# Lafferty1.net
KiCad netlist of a schematic drawn in EAGLE
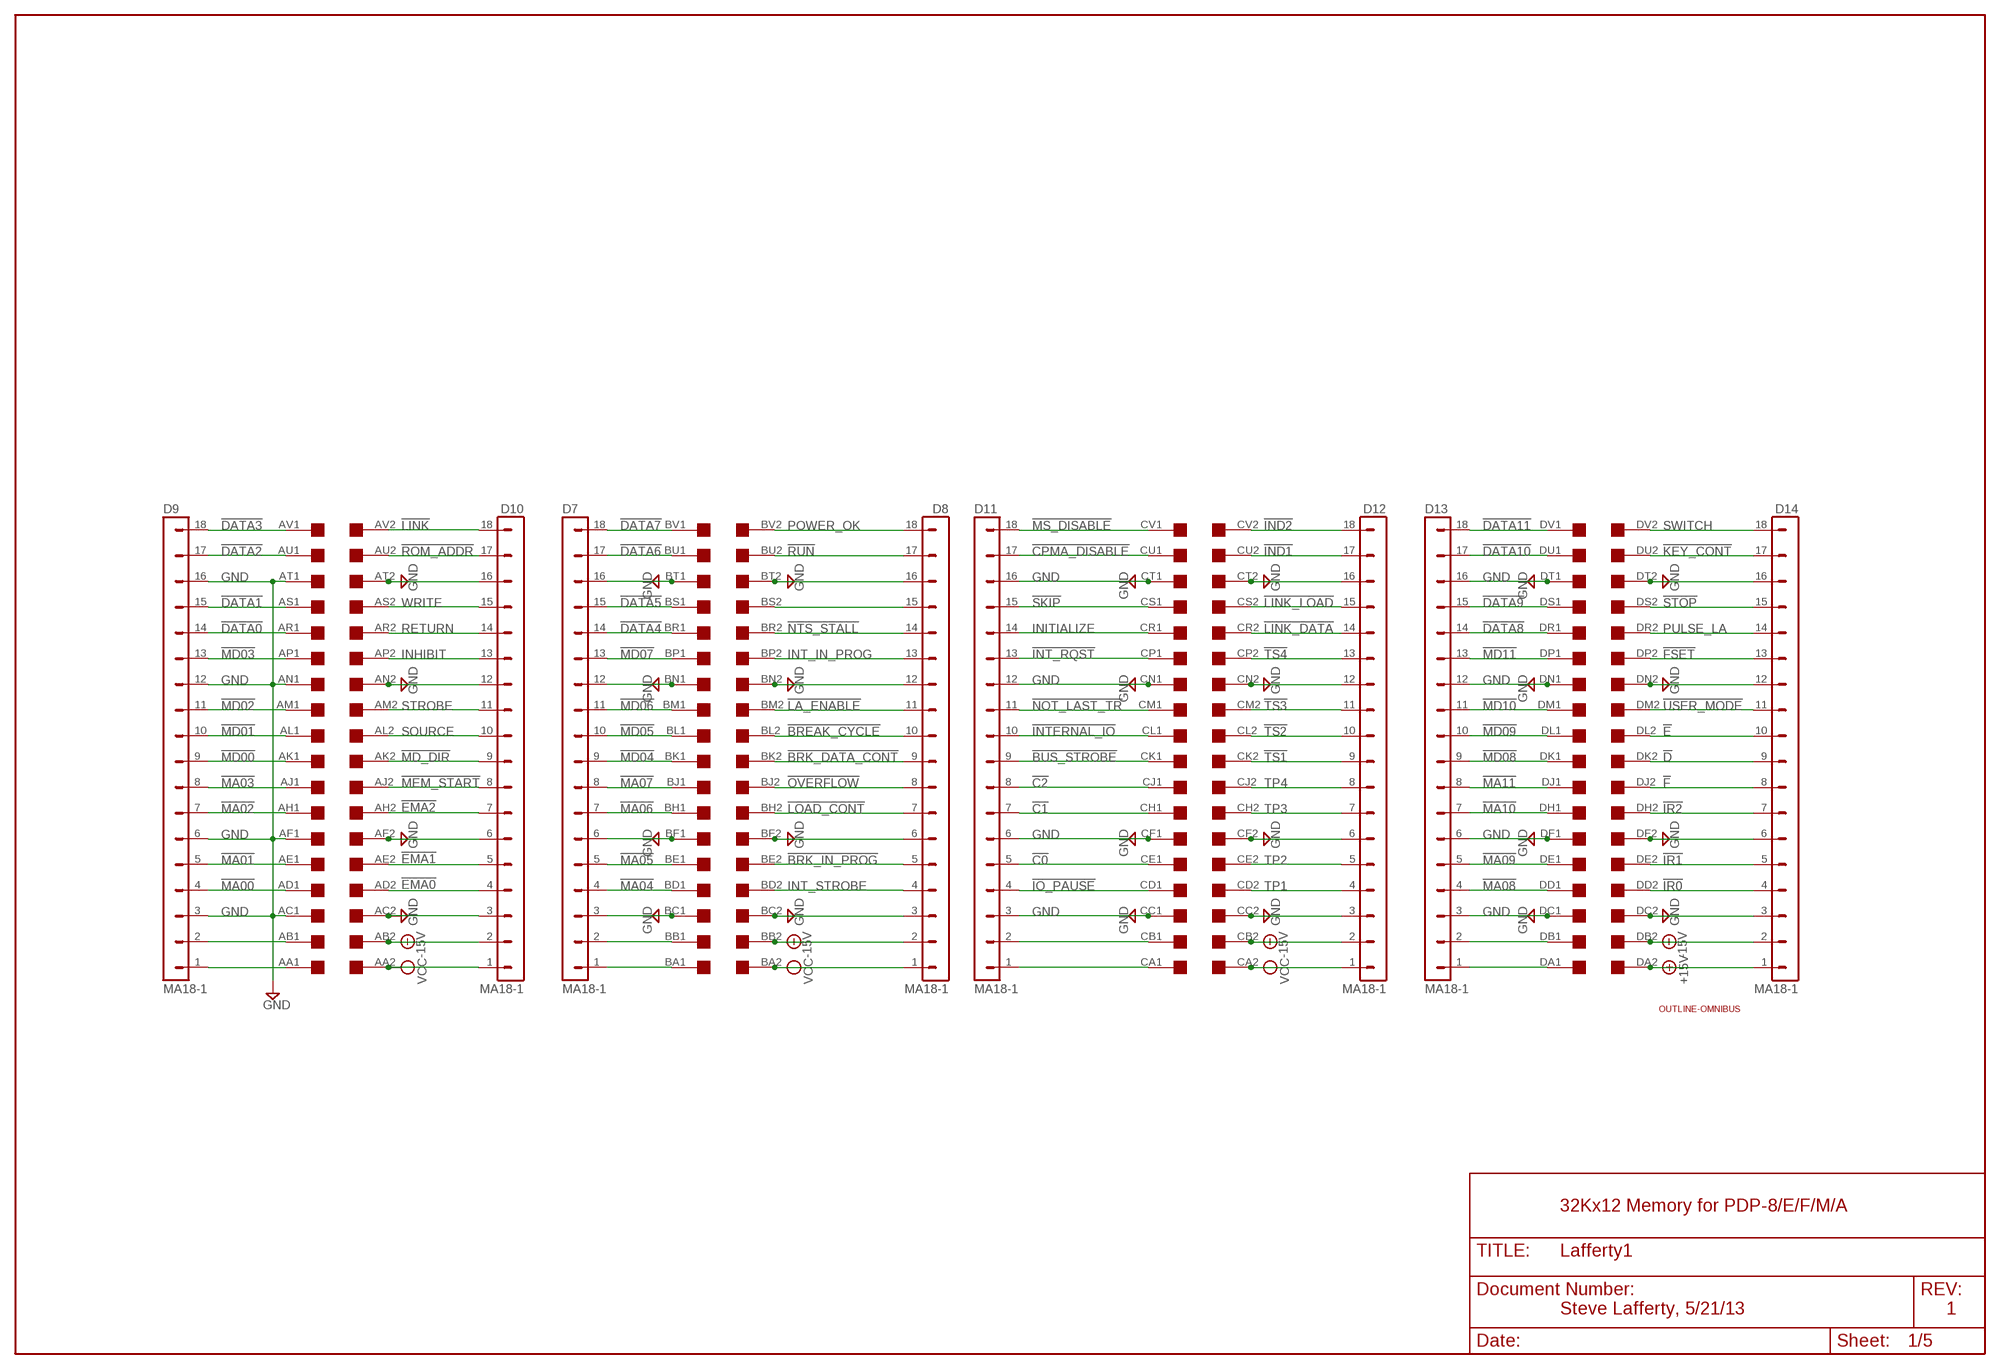
[diagram p0: schematic, sheet 1]
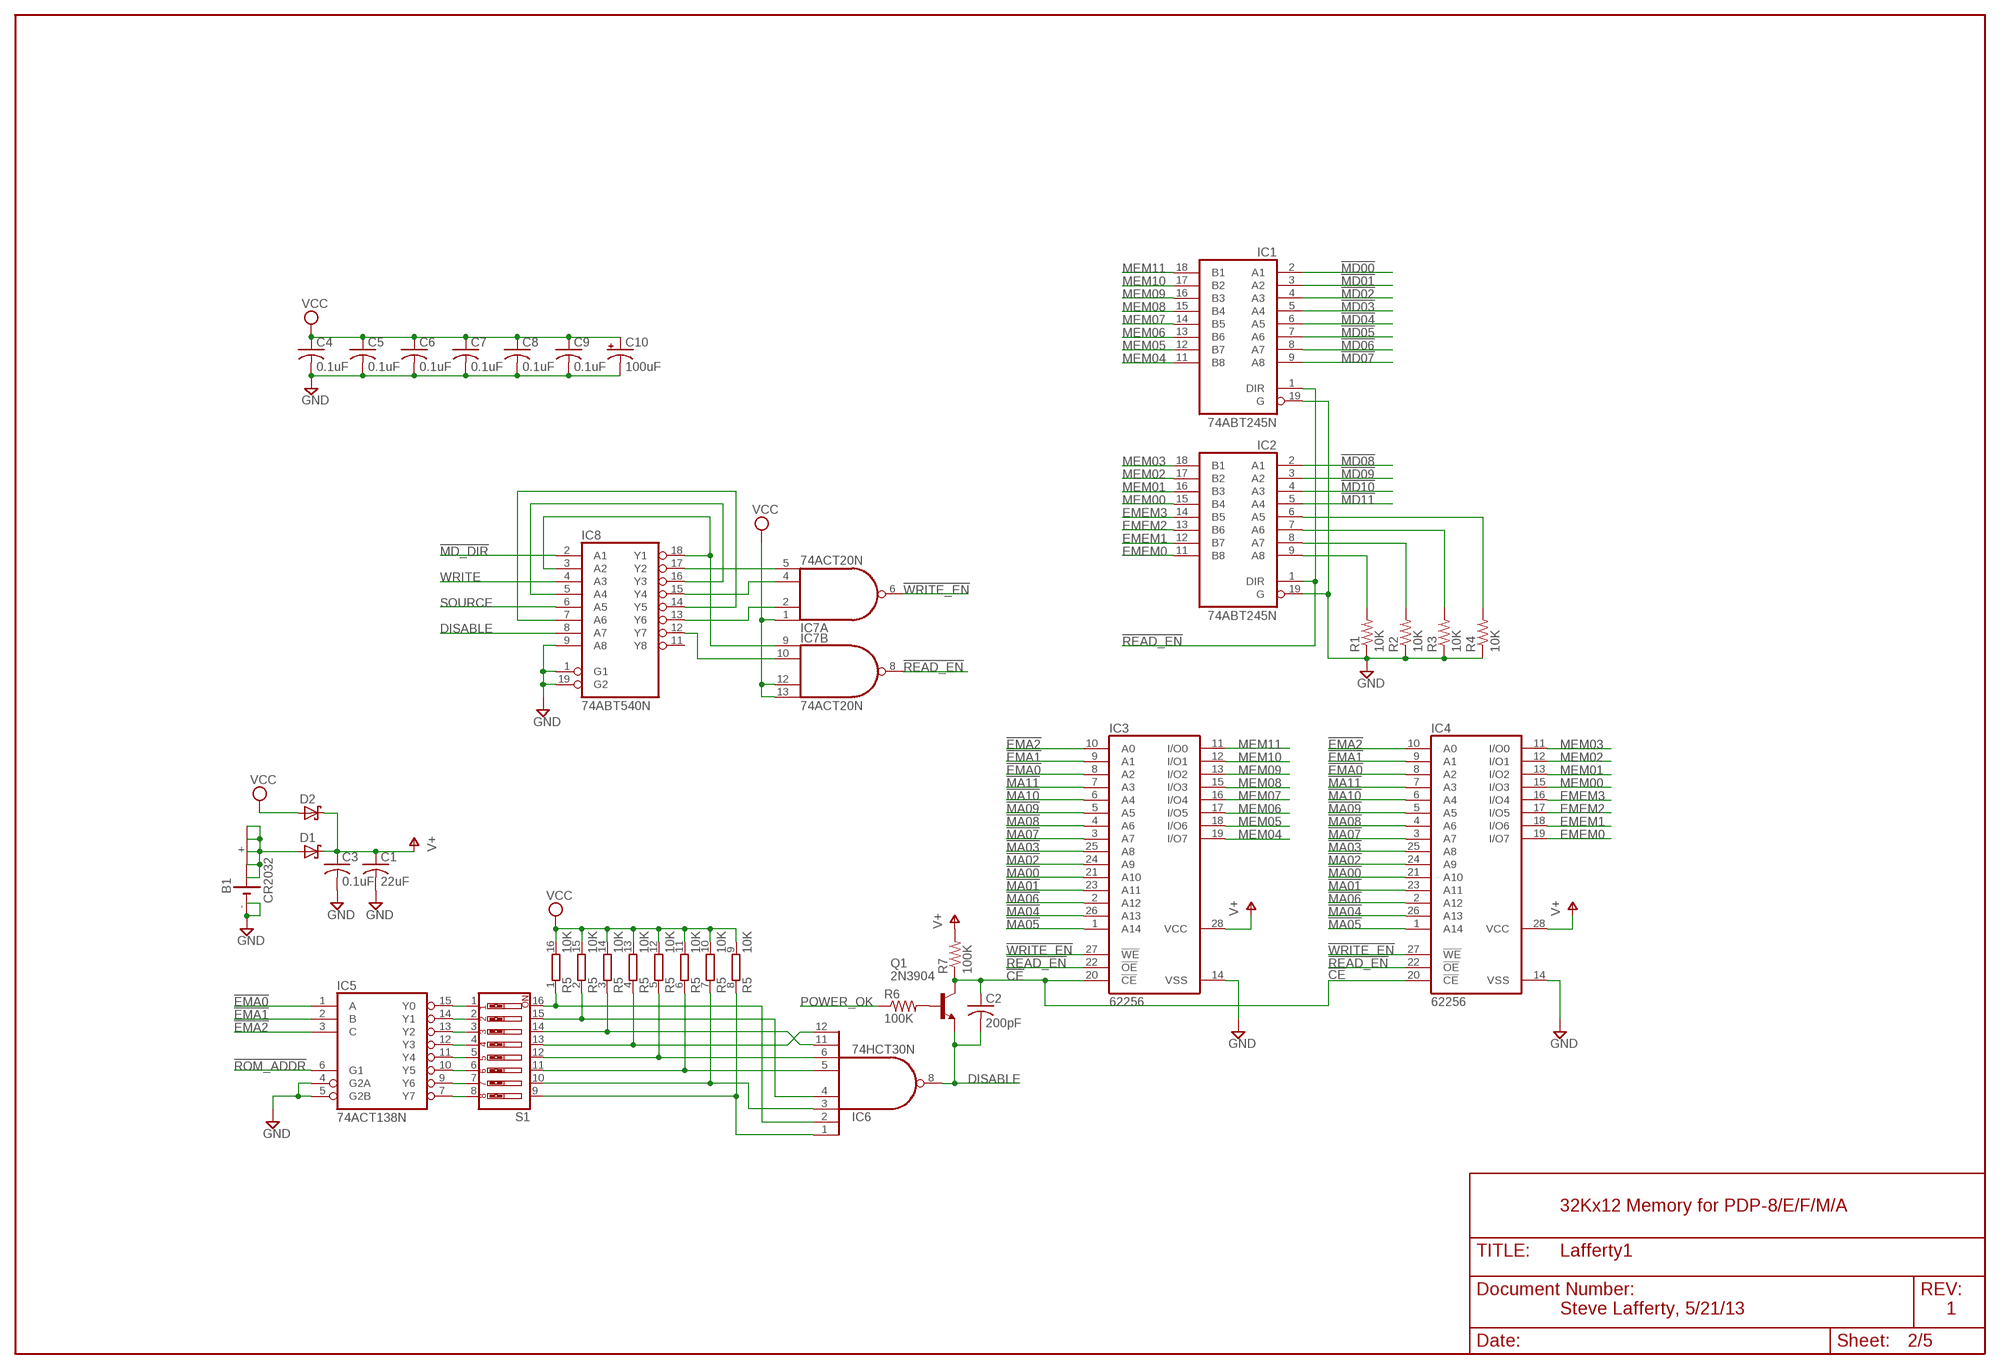
[diagram p1: schematic, sheet 2]
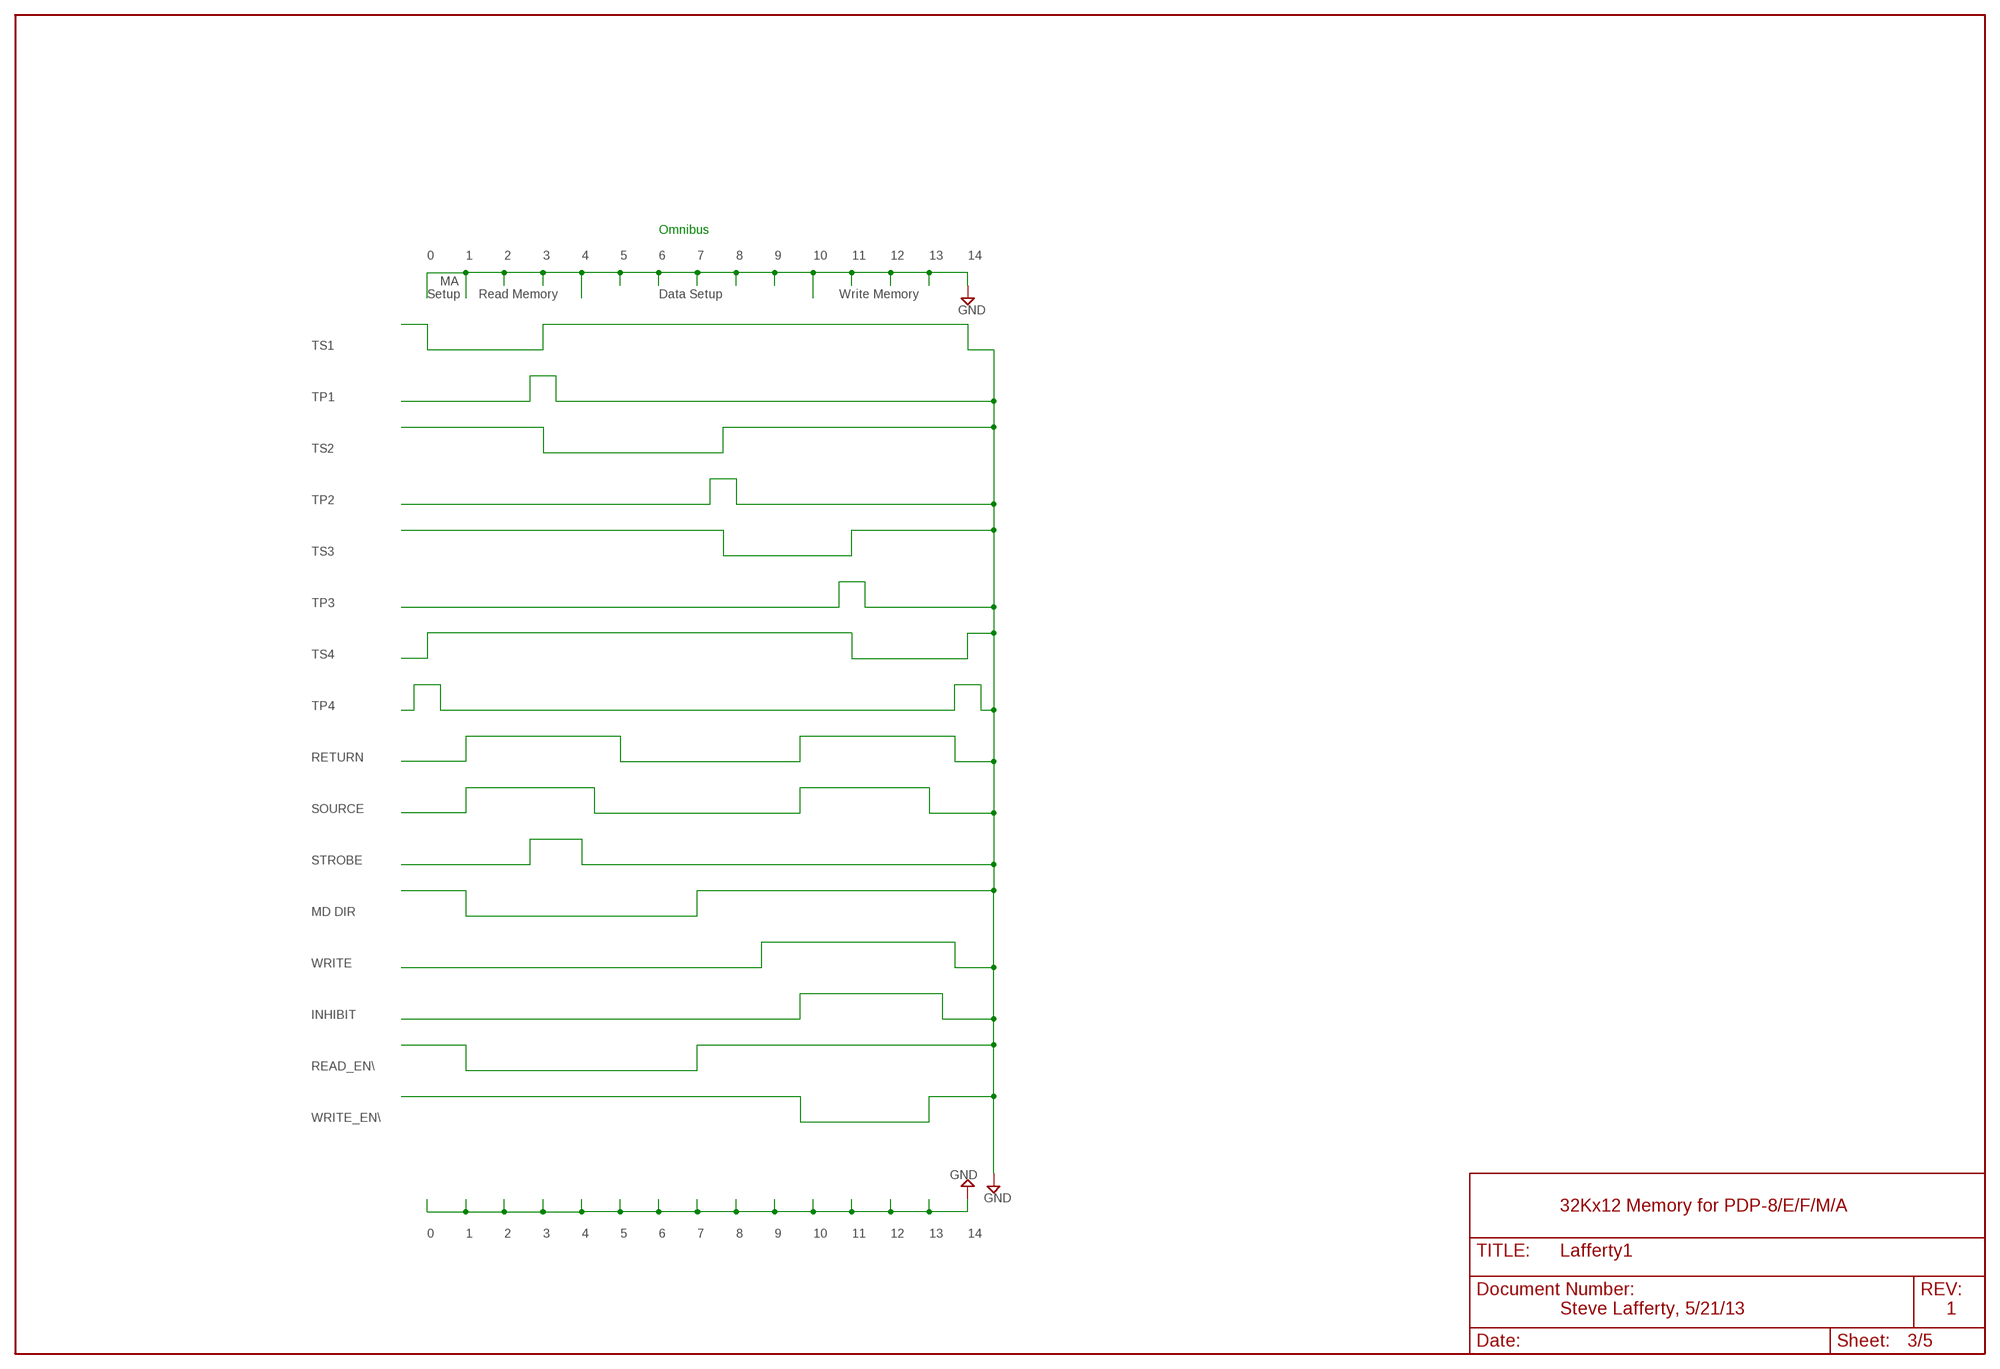
[diagram p2: schematic, sheet 3]
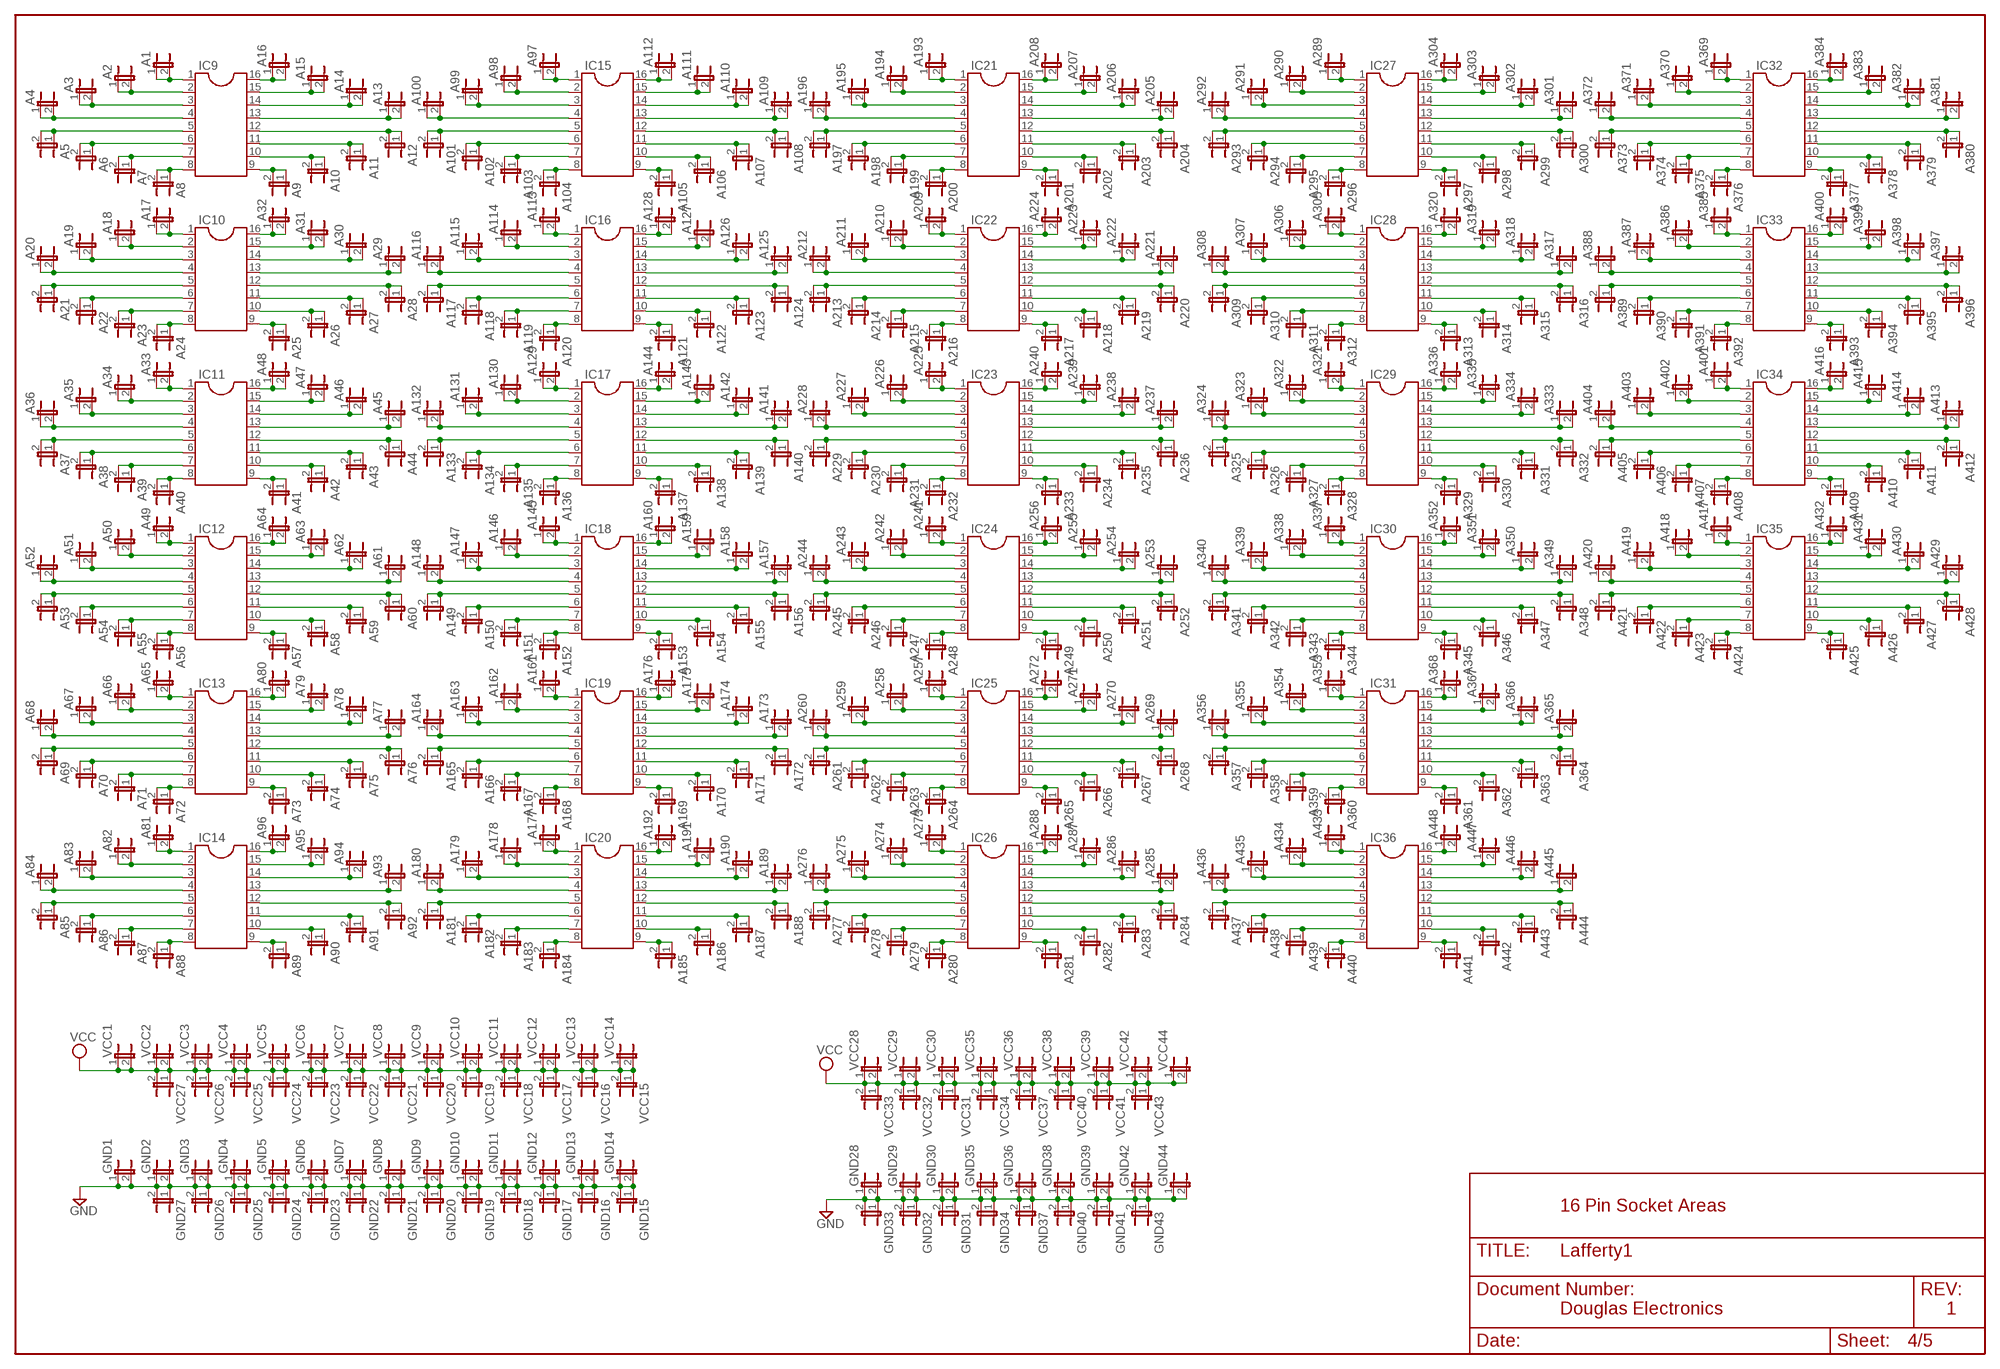
[diagram p3: schematic, sheet 4]
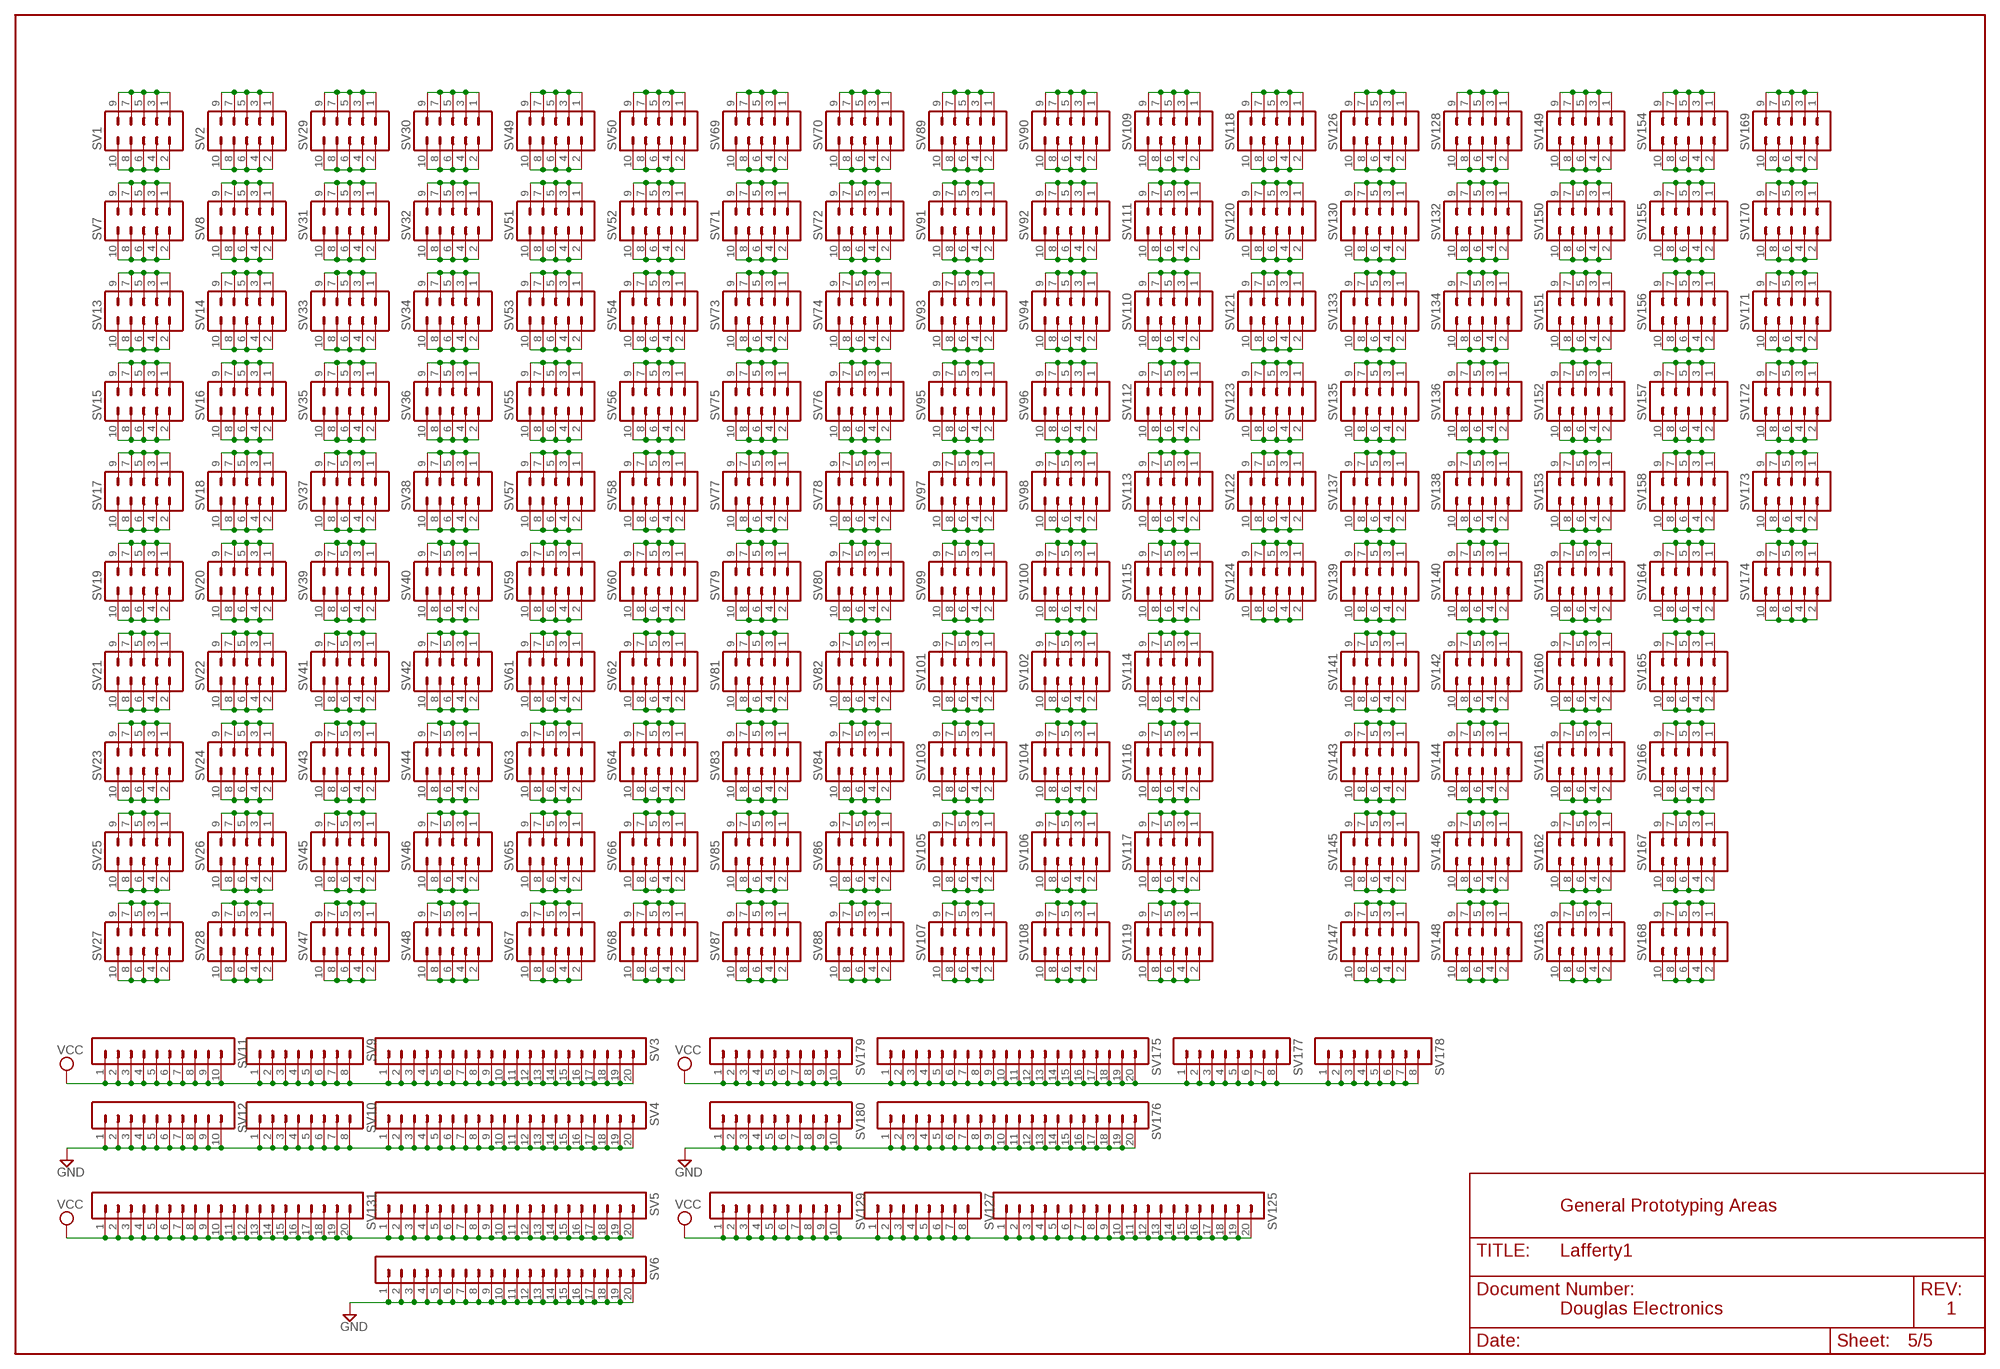
[diagram p4: schematic, sheet 5]

(export (version "E")
  (design (tool "Eeschema 10.0.6"))
  (components
    (comp (ref "B1")
      (value "CR2032")
      (footprint "eagle-import:B2430UNI")
      (libsource (lib "eagle-import") (part "B2430UNI"))
    )
    (comp (ref "C1")
      (value "22uF")
      (footprint "eagle-import:C050-025X075")
      (libsource (lib "eagle-import") (part "C-US050-025X075"))
    )
    (comp (ref "C2")
      (value "200pF")
      (footprint "eagle-import:C050-025X075")
      (libsource (lib "eagle-import") (part "C-US050-025X075"))
    )
    (comp (ref "C3")
      (value "0.1uF")
      (footprint "eagle-import:C050-025X075")
      (libsource (lib "eagle-import") (part "C-US050-025X075"))
    )
    (comp (ref "C4")
      (value "0.1uF")
      (footprint "eagle-import:C050-025X075")
      (libsource (lib "eagle-import") (part "C-US050-025X075"))
    )
    (comp (ref "C5")
      (value "0.1uF")
      (footprint "eagle-import:C050-025X075")
      (libsource (lib "eagle-import") (part "C-US050-025X075"))
    )
    (comp (ref "C6")
      (value "0.1uF")
      (footprint "eagle-import:C050-025X075")
      (libsource (lib "eagle-import") (part "C-US050-025X075"))
    )
    (comp (ref "C7")
      (value "0.1uF")
      (footprint "eagle-import:C050-025X075")
      (libsource (lib "eagle-import") (part "C-US050-025X075"))
    )
    (comp (ref "C8")
      (value "0.1uF")
      (footprint "eagle-import:C050-025X075")
      (libsource (lib "eagle-import") (part "C-US050-025X075"))
    )
    (comp (ref "C9")
      (value "0.1uF")
      (footprint "eagle-import:C050-025X075")
      (libsource (lib "eagle-import") (part "C-US050-025X075"))
    )
    (comp (ref "C10")
      (value "100uF")
      (footprint "eagle-import:E12-8")
      (libsource (lib "eagle-import") (part "CPOL-USE20-8AXIAL"))
    )
    (comp (ref "D1")
      (value "BAT19")
      (footprint "eagle-import:DO35-10")
      (libsource (lib "eagle-import") (part "BAT19"))
    )
    (comp (ref "D2")
      (value "BAT19")
      (footprint "eagle-import:DO35-10")
      (libsource (lib "eagle-import") (part "BAT19"))
    )
    (comp (ref "IC1")
      (value "74ABT245N")
      (footprint "eagle-import:DIL20")
      (libsource (lib "eagle-import") (part "74245NLS"))
    )
    (comp (ref "IC2")
      (value "74ABT245N")
      (footprint "eagle-import:DIL20")
      (libsource (lib "eagle-import") (part "74245NLS"))
    )
    (comp (ref "IC3")
      (value "62256")
      (footprint "eagle-import:DIL28-6")
      (libsource (lib "eagle-import") (part "58C256P"))
    )
    (comp (ref "IC4")
      (value "62256")
      (footprint "eagle-import:DIL28-6")
      (libsource (lib "eagle-import") (part "58C256P"))
    )
    (comp (ref "IC5")
      (value "74ACT138N")
      (footprint "eagle-import:DIL16")
      (libsource (lib "eagle-import") (part "74138NLS"))
    )
    (comp (ref "IC6")
      (value "74HCT30N")
      (footprint "eagle-import:DIL14")
      (libsource (lib "eagle-import") (part "7430NLS"))
    )
    (comp (ref "IC7")
      (value "74ACT20N")
      (footprint "eagle-import:DIL14")
      (libsource (lib "eagle-import") (part "7420NLS"))
    )
    (comp (ref "IC8")
      (value "74ABT540N")
      (footprint "eagle-import:DIL20")
      (libsource (lib "eagle-import") (part "74540NLS"))
    )
    (comp (ref "Q1")
      (value "2N3904")
      (footprint "eagle-import:TO92")
      (libsource (lib "eagle-import") (part "2N3904"))
    )
    (comp (ref "R1")
      (value "10K")
      (footprint "eagle-import:0207_10")
      (libsource (lib "eagle-import") (part "R-US_0207/10"))
    )
    (comp (ref "R2")
      (value "10K")
      (footprint "eagle-import:0207_10")
      (libsource (lib "eagle-import") (part "R-US_0207/10"))
    )
    (comp (ref "R3")
      (value "10K")
      (footprint "eagle-import:0207_10")
      (libsource (lib "eagle-import") (part "R-US_0207/10"))
    )
    (comp (ref "R4")
      (value "10K")
      (footprint "eagle-import:0207_10")
      (libsource (lib "eagle-import") (part "R-US_0207/10"))
    )
    (comp (ref "R5")
      (value "10K")
      (footprint "eagle-import:DIL16")
      (libsource (lib "eagle-import") (part "8R-P"))
    )
    (comp (ref "R6")
      (value "100K")
      (footprint "eagle-import:0207_10")
      (libsource (lib "eagle-import") (part "R-US_0207/10"))
    )
    (comp (ref "R7")
      (value "100K")
      (footprint "eagle-import:0207_10")
      (libsource (lib "eagle-import") (part "R-US_0207/10"))
    )
    (comp (ref "S1")
      (value "SW_DIP-8")
      (footprint "eagle-import:EDG-08")
      (libsource (lib "eagle-import") (part "SW_DIP-8"))
    )
    (comp (ref "D7")
      (value "MA18-1")
      (footprint "eagle-import:MA18-1")
      (libsource (lib "eagle-import") (part "MA18-1"))
    )
    (comp (ref "D8")
      (value "MA18-1")
      (footprint "eagle-import:MA18-1")
      (libsource (lib "eagle-import") (part "MA18-1"))
    )
    (comp (ref "D9")
      (value "MA18-1")
      (footprint "eagle-import:MA18-1")
      (libsource (lib "eagle-import") (part "MA18-1"))
    )
    (comp (ref "D10")
      (value "MA18-1")
      (footprint "eagle-import:MA18-1")
      (libsource (lib "eagle-import") (part "MA18-1"))
    )
    (comp (ref "D11")
      (value "MA18-1")
      (footprint "eagle-import:MA18-1")
      (libsource (lib "eagle-import") (part "MA18-1"))
    )
    (comp (ref "D12")
      (value "MA18-1")
      (footprint "eagle-import:MA18-1")
      (libsource (lib "eagle-import") (part "MA18-1"))
    )
    (comp (ref "D13")
      (value "MA18-1")
      (footprint "eagle-import:MA18-1")
      (libsource (lib "eagle-import") (part "MA18-1"))
    )
    (comp (ref "D14")
      (value "MA18-1")
      (footprint "eagle-import:MA18-1")
      (libsource (lib "eagle-import") (part "MA18-1"))
    )
    (comp (ref "U$1")
      (value "OUTLINE-OMNIBUS")
      (footprint "eagle-import:OMNIBUS")
      (libsource (lib "eagle-import") (part "OUTLINE-OMNIBUS"))
    )
    (comp (ref "U$2")
      (value "QUAD")
      (footprint "eagle-import:EDGE-CON8")
      (libsource (lib "eagle-import") (part "QUAD"))
    )
    (comp (ref "SV1")
      (value "MA05-2")
      (footprint "eagle-import:MA05-2")
      (libsource (lib "eagle-import") (part "MA05-2"))
    )
    (comp (ref "SV2")
      (value "MA05-2")
      (footprint "eagle-import:MA05-2")
      (libsource (lib "eagle-import") (part "MA05-2"))
    )
    (comp (ref "SV3")
      (value "MA20-1")
      (footprint "eagle-import:MA20-1")
      (libsource (lib "eagle-import") (part "MA20-1"))
    )
    (comp (ref "SV4")
      (value "MA20-1")
      (footprint "eagle-import:MA20-1")
      (libsource (lib "eagle-import") (part "MA20-1"))
    )
    (comp (ref "SV5")
      (value "MA20-1")
      (footprint "eagle-import:MA20-1")
      (libsource (lib "eagle-import") (part "MA20-1"))
    )
    (comp (ref "SV6")
      (value "MA20-1")
      (footprint "eagle-import:MA20-1")
      (libsource (lib "eagle-import") (part "MA20-1"))
    )
    (comp (ref "SV7")
      (value "MA05-2")
      (footprint "eagle-import:MA05-2")
      (libsource (lib "eagle-import") (part "MA05-2"))
    )
    (comp (ref "SV8")
      (value "MA05-2")
      (footprint "eagle-import:MA05-2")
      (libsource (lib "eagle-import") (part "MA05-2"))
    )
    (comp (ref "SV9")
      (value "MA08-1")
      (footprint "eagle-import:MA08-1")
      (libsource (lib "eagle-import") (part "MA08-1"))
    )
    (comp (ref "SV10")
      (value "MA08-1")
      (footprint "eagle-import:MA08-1")
      (libsource (lib "eagle-import") (part "MA08-1"))
    )
    (comp (ref "SV11")
      (value "MA10-1")
      (footprint "eagle-import:MA10-1")
      (libsource (lib "eagle-import") (part "MA10-1"))
    )
    (comp (ref "SV12")
      (value "MA10-1")
      (footprint "eagle-import:MA10-1")
      (libsource (lib "eagle-import") (part "MA10-1"))
    )
    (comp (ref "SV13")
      (value "MA05-2")
      (footprint "eagle-import:MA05-2")
      (libsource (lib "eagle-import") (part "MA05-2"))
    )
    (comp (ref "SV14")
      (value "MA05-2")
      (footprint "eagle-import:MA05-2")
      (libsource (lib "eagle-import") (part "MA05-2"))
    )
    (comp (ref "SV15")
      (value "MA05-2")
      (footprint "eagle-import:MA05-2")
      (libsource (lib "eagle-import") (part "MA05-2"))
    )
    (comp (ref "SV16")
      (value "MA05-2")
      (footprint "eagle-import:MA05-2")
      (libsource (lib "eagle-import") (part "MA05-2"))
    )
    (comp (ref "SV17")
      (value "MA05-2")
      (footprint "eagle-import:MA05-2")
      (libsource (lib "eagle-import") (part "MA05-2"))
    )
    (comp (ref "SV18")
      (value "MA05-2")
      (footprint "eagle-import:MA05-2")
      (libsource (lib "eagle-import") (part "MA05-2"))
    )
    (comp (ref "SV19")
      (value "MA05-2")
      (footprint "eagle-import:MA05-2")
      (libsource (lib "eagle-import") (part "MA05-2"))
    )
    (comp (ref "SV20")
      (value "MA05-2")
      (footprint "eagle-import:MA05-2")
      (libsource (lib "eagle-import") (part "MA05-2"))
    )
    (comp (ref "SV21")
      (value "MA05-2")
      (footprint "eagle-import:MA05-2")
      (libsource (lib "eagle-import") (part "MA05-2"))
    )
    (comp (ref "SV22")
      (value "MA05-2")
      (footprint "eagle-import:MA05-2")
      (libsource (lib "eagle-import") (part "MA05-2"))
    )
    (comp (ref "SV23")
      (value "MA05-2")
      (footprint "eagle-import:MA05-2")
      (libsource (lib "eagle-import") (part "MA05-2"))
    )
    (comp (ref "SV24")
      (value "MA05-2")
      (footprint "eagle-import:MA05-2")
      (libsource (lib "eagle-import") (part "MA05-2"))
    )
    (comp (ref "SV25")
      (value "MA05-2")
      (footprint "eagle-import:MA05-2")
      (libsource (lib "eagle-import") (part "MA05-2"))
    )
    (comp (ref "SV26")
      (value "MA05-2")
      (footprint "eagle-import:MA05-2")
      (libsource (lib "eagle-import") (part "MA05-2"))
    )
    (comp (ref "SV27")
      (value "MA05-2")
      (footprint "eagle-import:MA05-2")
      (libsource (lib "eagle-import") (part "MA05-2"))
    )
    (comp (ref "SV28")
      (value "MA05-2")
      (footprint "eagle-import:MA05-2")
      (libsource (lib "eagle-import") (part "MA05-2"))
    )
    (comp (ref "SV29")
      (value "MA05-2")
      (footprint "eagle-import:MA05-2")
      (libsource (lib "eagle-import") (part "MA05-2"))
    )
    (comp (ref "SV30")
      (value "MA05-2")
      (footprint "eagle-import:MA05-2")
      (libsource (lib "eagle-import") (part "MA05-2"))
    )
    (comp (ref "SV31")
      (value "MA05-2")
      (footprint "eagle-import:MA05-2")
      (libsource (lib "eagle-import") (part "MA05-2"))
    )
    (comp (ref "SV32")
      (value "MA05-2")
      (footprint "eagle-import:MA05-2")
      (libsource (lib "eagle-import") (part "MA05-2"))
    )
    (comp (ref "SV33")
      (value "MA05-2")
      (footprint "eagle-import:MA05-2")
      (libsource (lib "eagle-import") (part "MA05-2"))
    )
    (comp (ref "SV34")
      (value "MA05-2")
      (footprint "eagle-import:MA05-2")
      (libsource (lib "eagle-import") (part "MA05-2"))
    )
    (comp (ref "SV35")
      (value "MA05-2")
      (footprint "eagle-import:MA05-2")
      (libsource (lib "eagle-import") (part "MA05-2"))
    )
    (comp (ref "SV36")
      (value "MA05-2")
      (footprint "eagle-import:MA05-2")
      (libsource (lib "eagle-import") (part "MA05-2"))
    )
    (comp (ref "SV37")
      (value "MA05-2")
      (footprint "eagle-import:MA05-2")
      (libsource (lib "eagle-import") (part "MA05-2"))
    )
    (comp (ref "SV38")
      (value "MA05-2")
      (footprint "eagle-import:MA05-2")
      (libsource (lib "eagle-import") (part "MA05-2"))
    )
    (comp (ref "SV39")
      (value "MA05-2")
      (footprint "eagle-import:MA05-2")
      (libsource (lib "eagle-import") (part "MA05-2"))
    )
    (comp (ref "SV40")
      (value "MA05-2")
      (footprint "eagle-import:MA05-2")
      (libsource (lib "eagle-import") (part "MA05-2"))
    )
    (comp (ref "SV41")
      (value "MA05-2")
      (footprint "eagle-import:MA05-2")
      (libsource (lib "eagle-import") (part "MA05-2"))
    )
    (comp (ref "SV42")
      (value "MA05-2")
      (footprint "eagle-import:MA05-2")
      (libsource (lib "eagle-import") (part "MA05-2"))
    )
    (comp (ref "SV43")
      (value "MA05-2")
      (footprint "eagle-import:MA05-2")
      (libsource (lib "eagle-import") (part "MA05-2"))
    )
    (comp (ref "SV44")
      (value "MA05-2")
      (footprint "eagle-import:MA05-2")
      (libsource (lib "eagle-import") (part "MA05-2"))
    )
    (comp (ref "SV45")
      (value "MA05-2")
      (footprint "eagle-import:MA05-2")
      (libsource (lib "eagle-import") (part "MA05-2"))
    )
    (comp (ref "SV46")
      (value "MA05-2")
      (footprint "eagle-import:MA05-2")
      (libsource (lib "eagle-import") (part "MA05-2"))
    )
    (comp (ref "SV47")
      (value "MA05-2")
      (footprint "eagle-import:MA05-2")
      (libsource (lib "eagle-import") (part "MA05-2"))
    )
    (comp (ref "SV48")
      (value "MA05-2")
      (footprint "eagle-import:MA05-2")
      (libsource (lib "eagle-import") (part "MA05-2"))
    )
    (comp (ref "SV49")
      (value "MA05-2")
      (footprint "eagle-import:MA05-2")
      (libsource (lib "eagle-import") (part "MA05-2"))
    )
    (comp (ref "SV50")
      (value "MA05-2")
      (footprint "eagle-import:MA05-2")
      (libsource (lib "eagle-import") (part "MA05-2"))
    )
    (comp (ref "SV51")
      (value "MA05-2")
      (footprint "eagle-import:MA05-2")
      (libsource (lib "eagle-import") (part "MA05-2"))
    )
    (comp (ref "SV52")
      (value "MA05-2")
      (footprint "eagle-import:MA05-2")
      (libsource (lib "eagle-import") (part "MA05-2"))
    )
    (comp (ref "SV53")
      (value "MA05-2")
      (footprint "eagle-import:MA05-2")
      (libsource (lib "eagle-import") (part "MA05-2"))
    )
    (comp (ref "SV54")
      (value "MA05-2")
      (footprint "eagle-import:MA05-2")
      (libsource (lib "eagle-import") (part "MA05-2"))
    )
    (comp (ref "SV55")
      (value "MA05-2")
      (footprint "eagle-import:MA05-2")
      (libsource (lib "eagle-import") (part "MA05-2"))
    )
    (comp (ref "SV56")
      (value "MA05-2")
      (footprint "eagle-import:MA05-2")
      (libsource (lib "eagle-import") (part "MA05-2"))
    )
    (comp (ref "SV57")
      (value "MA05-2")
      (footprint "eagle-import:MA05-2")
      (libsource (lib "eagle-import") (part "MA05-2"))
    )
    (comp (ref "SV58")
      (value "MA05-2")
      (footprint "eagle-import:MA05-2")
      (libsource (lib "eagle-import") (part "MA05-2"))
    )
    (comp (ref "SV59")
      (value "MA05-2")
      (footprint "eagle-import:MA05-2")
      (libsource (lib "eagle-import") (part "MA05-2"))
    )
    (comp (ref "SV60")
      (value "MA05-2")
      (footprint "eagle-import:MA05-2")
      (libsource (lib "eagle-import") (part "MA05-2"))
    )
    (comp (ref "SV61")
      (value "MA05-2")
      (footprint "eagle-import:MA05-2")
      (libsource (lib "eagle-import") (part "MA05-2"))
    )
    (comp (ref "SV62")
      (value "MA05-2")
      (footprint "eagle-import:MA05-2")
      (libsource (lib "eagle-import") (part "MA05-2"))
    )
    (comp (ref "SV63")
      (value "MA05-2")
      (footprint "eagle-import:MA05-2")
      (libsource (lib "eagle-import") (part "MA05-2"))
    )
    (comp (ref "SV64")
      (value "MA05-2")
      (footprint "eagle-import:MA05-2")
      (libsource (lib "eagle-import") (part "MA05-2"))
    )
    (comp (ref "SV65")
      (value "MA05-2")
      (footprint "eagle-import:MA05-2")
      (libsource (lib "eagle-import") (part "MA05-2"))
    )
    (comp (ref "SV66")
      (value "MA05-2")
      (footprint "eagle-import:MA05-2")
      (libsource (lib "eagle-import") (part "MA05-2"))
    )
    (comp (ref "SV67")
      (value "MA05-2")
      (footprint "eagle-import:MA05-2")
      (libsource (lib "eagle-import") (part "MA05-2"))
    )
    (comp (ref "SV68")
      (value "MA05-2")
      (footprint "eagle-import:MA05-2")
      (libsource (lib "eagle-import") (part "MA05-2"))
    )
    (comp (ref "SV69")
      (value "MA05-2")
      (footprint "eagle-import:MA05-2")
      (libsource (lib "eagle-import") (part "MA05-2"))
    )
    (comp (ref "SV70")
      (value "MA05-2")
      (footprint "eagle-import:MA05-2")
      (libsource (lib "eagle-import") (part "MA05-2"))
    )
    (comp (ref "SV71")
      (value "MA05-2")
      (footprint "eagle-import:MA05-2")
      (libsource (lib "eagle-import") (part "MA05-2"))
    )
    (comp (ref "SV72")
      (value "MA05-2")
      (footprint "eagle-import:MA05-2")
      (libsource (lib "eagle-import") (part "MA05-2"))
    )
    (comp (ref "SV73")
      (value "MA05-2")
      (footprint "eagle-import:MA05-2")
      (libsource (lib "eagle-import") (part "MA05-2"))
    )
    (comp (ref "SV74")
      (value "MA05-2")
      (footprint "eagle-import:MA05-2")
      (libsource (lib "eagle-import") (part "MA05-2"))
    )
    (comp (ref "SV75")
      (value "MA05-2")
      (footprint "eagle-import:MA05-2")
      (libsource (lib "eagle-import") (part "MA05-2"))
    )
    (comp (ref "SV76")
      (value "MA05-2")
      (footprint "eagle-import:MA05-2")
      (libsource (lib "eagle-import") (part "MA05-2"))
    )
    (comp (ref "SV77")
      (value "MA05-2")
      (footprint "eagle-import:MA05-2")
      (libsource (lib "eagle-import") (part "MA05-2"))
    )
    (comp (ref "SV78")
      (value "MA05-2")
      (footprint "eagle-import:MA05-2")
      (libsource (lib "eagle-import") (part "MA05-2"))
    )
    (comp (ref "SV79")
      (value "MA05-2")
      (footprint "eagle-import:MA05-2")
      (libsource (lib "eagle-import") (part "MA05-2"))
    )
    (comp (ref "SV80")
      (value "MA05-2")
      (footprint "eagle-import:MA05-2")
      (libsource (lib "eagle-import") (part "MA05-2"))
    )
    (comp (ref "SV81")
      (value "MA05-2")
      (footprint "eagle-import:MA05-2")
      (libsource (lib "eagle-import") (part "MA05-2"))
    )
    (comp (ref "SV82")
      (value "MA05-2")
      (footprint "eagle-import:MA05-2")
      (libsource (lib "eagle-import") (part "MA05-2"))
    )
    (comp (ref "SV83")
      (value "MA05-2")
      (footprint "eagle-import:MA05-2")
      (libsource (lib "eagle-import") (part "MA05-2"))
    )
    (comp (ref "SV84")
      (value "MA05-2")
      (footprint "eagle-import:MA05-2")
      (libsource (lib "eagle-import") (part "MA05-2"))
    )
    (comp (ref "SV85")
      (value "MA05-2")
      (footprint "eagle-import:MA05-2")
      (libsource (lib "eagle-import") (part "MA05-2"))
    )
    (comp (ref "SV86")
      (value "MA05-2")
      (footprint "eagle-import:MA05-2")
      (libsource (lib "eagle-import") (part "MA05-2"))
    )
    (comp (ref "SV87")
      (value "MA05-2")
      (footprint "eagle-import:MA05-2")
      (libsource (lib "eagle-import") (part "MA05-2"))
    )
    (comp (ref "SV88")
      (value "MA05-2")
      (footprint "eagle-import:MA05-2")
      (libsource (lib "eagle-import") (part "MA05-2"))
    )
    (comp (ref "SV89")
      (value "MA05-2")
      (footprint "eagle-import:MA05-2")
      (libsource (lib "eagle-import") (part "MA05-2"))
    )
    (comp (ref "SV90")
      (value "MA05-2")
      (footprint "eagle-import:MA05-2")
      (libsource (lib "eagle-import") (part "MA05-2"))
    )
    (comp (ref "SV91")
      (value "MA05-2")
      (footprint "eagle-import:MA05-2")
      (libsource (lib "eagle-import") (part "MA05-2"))
    )
    (comp (ref "SV92")
      (value "MA05-2")
      (footprint "eagle-import:MA05-2")
      (libsource (lib "eagle-import") (part "MA05-2"))
    )
    (comp (ref "SV93")
      (value "MA05-2")
      (footprint "eagle-import:MA05-2")
      (libsource (lib "eagle-import") (part "MA05-2"))
    )
    (comp (ref "SV94")
      (value "MA05-2")
      (footprint "eagle-import:MA05-2")
      (libsource (lib "eagle-import") (part "MA05-2"))
    )
    (comp (ref "SV95")
      (value "MA05-2")
      (footprint "eagle-import:MA05-2")
      (libsource (lib "eagle-import") (part "MA05-2"))
    )
    (comp (ref "SV96")
      (value "MA05-2")
      (footprint "eagle-import:MA05-2")
      (libsource (lib "eagle-import") (part "MA05-2"))
    )
    (comp (ref "SV97")
      (value "MA05-2")
      (footprint "eagle-import:MA05-2")
      (libsource (lib "eagle-import") (part "MA05-2"))
    )
    (comp (ref "SV98")
      (value "MA05-2")
      (footprint "eagle-import:MA05-2")
      (libsource (lib "eagle-import") (part "MA05-2"))
    )
    (comp (ref "SV99")
      (value "MA05-2")
      (footprint "eagle-import:MA05-2")
      (libsource (lib "eagle-import") (part "MA05-2"))
    )
    (comp (ref "SV100")
      (value "MA05-2")
      (footprint "eagle-import:MA05-2")
      (libsource (lib "eagle-import") (part "MA05-2"))
    )
    (comp (ref "SV101")
      (value "MA05-2")
      (footprint "eagle-import:MA05-2")
      (libsource (lib "eagle-import") (part "MA05-2"))
    )
    (comp (ref "SV102")
      (value "MA05-2")
      (footprint "eagle-import:MA05-2")
      (libsource (lib "eagle-import") (part "MA05-2"))
    )
    (comp (ref "SV103")
      (value "MA05-2")
      (footprint "eagle-import:MA05-2")
      (libsource (lib "eagle-import") (part "MA05-2"))
    )
    (comp (ref "SV104")
      (value "MA05-2")
      (footprint "eagle-import:MA05-2")
      (libsource (lib "eagle-import") (part "MA05-2"))
    )
    (comp (ref "SV105")
      (value "MA05-2")
      (footprint "eagle-import:MA05-2")
      (libsource (lib "eagle-import") (part "MA05-2"))
    )
    (comp (ref "SV106")
      (value "MA05-2")
      (footprint "eagle-import:MA05-2")
      (libsource (lib "eagle-import") (part "MA05-2"))
    )
    (comp (ref "SV107")
      (value "MA05-2")
      (footprint "eagle-import:MA05-2")
      (libsource (lib "eagle-import") (part "MA05-2"))
    )
    (comp (ref "SV108")
      (value "MA05-2")
      (footprint "eagle-import:MA05-2")
      (libsource (lib "eagle-import") (part "MA05-2"))
    )
    (comp (ref "SV109")
      (value "MA05-2")
      (footprint "eagle-import:MA05-2")
      (libsource (lib "eagle-import") (part "MA05-2"))
    )
    (comp (ref "SV110")
      (value "MA05-2")
      (footprint "eagle-import:MA05-2")
      (libsource (lib "eagle-import") (part "MA05-2"))
    )
    (comp (ref "SV111")
      (value "MA05-2")
      (footprint "eagle-import:MA05-2")
      (libsource (lib "eagle-import") (part "MA05-2"))
    )
    (comp (ref "SV112")
      (value "MA05-2")
      (footprint "eagle-import:MA05-2")
      (libsource (lib "eagle-import") (part "MA05-2"))
    )
    (comp (ref "SV113")
      (value "MA05-2")
      (footprint "eagle-import:MA05-2")
      (libsource (lib "eagle-import") (part "MA05-2"))
    )
    (comp (ref "SV114")
      (value "MA05-2")
      (footprint "eagle-import:MA05-2")
      (libsource (lib "eagle-import") (part "MA05-2"))
    )
    (comp (ref "SV115")
      (value "MA05-2")
      (footprint "eagle-import:MA05-2")
      (libsource (lib "eagle-import") (part "MA05-2"))
    )
    (comp (ref "SV116")
      (value "MA05-2")
      (footprint "eagle-import:MA05-2")
      (libsource (lib "eagle-import") (part "MA05-2"))
    )
    (comp (ref "SV117")
      (value "MA05-2")
      (footprint "eagle-import:MA05-2")
      (libsource (lib "eagle-import") (part "MA05-2"))
    )
    (comp (ref "SV118")
      (value "MA05-2")
      (footprint "eagle-import:MA05-2")
      (libsource (lib "eagle-import") (part "MA05-2"))
    )
    (comp (ref "SV119")
      (value "MA05-2")
      (footprint "eagle-import:MA05-2")
      (libsource (lib "eagle-import") (part "MA05-2"))
    )
    (comp (ref "SV120")
      (value "MA05-2")
      (footprint "eagle-import:MA05-2")
      (libsource (lib "eagle-import") (part "MA05-2"))
    )
    (comp (ref "SV121")
      (value "MA05-2")
      (footprint "eagle-import:MA05-2")
      (libsource (lib "eagle-import") (part "MA05-2"))
    )
    (comp (ref "SV122")
      (value "MA05-2")
      (footprint "eagle-import:MA05-2")
      (libsource (lib "eagle-import") (part "MA05-2"))
    )
    (comp (ref "SV123")
      (value "MA05-2")
      (footprint "eagle-import:MA05-2")
      (libsource (lib "eagle-import") (part "MA05-2"))
    )
    (comp (ref "SV124")
      (value "MA05-2")
      (footprint "eagle-import:MA05-2")
      (libsource (lib "eagle-import") (part "MA05-2"))
    )
    (comp (ref "SV125")
      (value "MA20-1")
      (footprint "eagle-import:MA20-1")
      (libsource (lib "eagle-import") (part "MA20-1"))
    )
    (comp (ref "SV126")
      (value "MA05-2")
      (footprint "eagle-import:MA05-2")
      (libsource (lib "eagle-import") (part "MA05-2"))
    )
    (comp (ref "SV127")
      (value "MA08-1")
      (footprint "eagle-import:MA08-1")
      (libsource (lib "eagle-import") (part "MA08-1"))
    )
    (comp (ref "SV128")
      (value "MA05-2")
      (footprint "eagle-import:MA05-2")
      (libsource (lib "eagle-import") (part "MA05-2"))
    )
    (comp (ref "SV129")
      (value "MA10-1")
      (footprint "eagle-import:MA10-1")
      (libsource (lib "eagle-import") (part "MA10-1"))
    )
    (comp (ref "SV130")
      (value "MA05-2")
      (footprint "eagle-import:MA05-2")
      (libsource (lib "eagle-import") (part "MA05-2"))
    )
    (comp (ref "SV131")
      (value "MA20-1")
      (footprint "eagle-import:MA20-1")
      (libsource (lib "eagle-import") (part "MA20-1"))
    )
    (comp (ref "SV132")
      (value "MA05-2")
      (footprint "eagle-import:MA05-2")
      (libsource (lib "eagle-import") (part "MA05-2"))
    )
    (comp (ref "SV133")
      (value "MA05-2")
      (footprint "eagle-import:MA05-2")
      (libsource (lib "eagle-import") (part "MA05-2"))
    )
    (comp (ref "SV134")
      (value "MA05-2")
      (footprint "eagle-import:MA05-2")
      (libsource (lib "eagle-import") (part "MA05-2"))
    )
    (comp (ref "SV135")
      (value "MA05-2")
      (footprint "eagle-import:MA05-2")
      (libsource (lib "eagle-import") (part "MA05-2"))
    )
    (comp (ref "SV136")
      (value "MA05-2")
      (footprint "eagle-import:MA05-2")
      (libsource (lib "eagle-import") (part "MA05-2"))
    )
    (comp (ref "SV137")
      (value "MA05-2")
      (footprint "eagle-import:MA05-2")
      (libsource (lib "eagle-import") (part "MA05-2"))
    )
    (comp (ref "SV138")
      (value "MA05-2")
      (footprint "eagle-import:MA05-2")
      (libsource (lib "eagle-import") (part "MA05-2"))
    )
    (comp (ref "SV139")
      (value "MA05-2")
      (footprint "eagle-import:MA05-2")
      (libsource (lib "eagle-import") (part "MA05-2"))
    )
    (comp (ref "SV140")
      (value "MA05-2")
      (footprint "eagle-import:MA05-2")
      (libsource (lib "eagle-import") (part "MA05-2"))
    )
    (comp (ref "SV141")
      (value "MA05-2")
      (footprint "eagle-import:MA05-2")
      (libsource (lib "eagle-import") (part "MA05-2"))
    )
    (comp (ref "SV142")
      (value "MA05-2")
      (footprint "eagle-import:MA05-2")
      (libsource (lib "eagle-import") (part "MA05-2"))
    )
    (comp (ref "SV143")
      (value "MA05-2")
      (footprint "eagle-import:MA05-2")
      (libsource (lib "eagle-import") (part "MA05-2"))
    )
    (comp (ref "SV144")
      (value "MA05-2")
      (footprint "eagle-import:MA05-2")
      (libsource (lib "eagle-import") (part "MA05-2"))
    )
    (comp (ref "SV145")
      (value "MA05-2")
      (footprint "eagle-import:MA05-2")
      (libsource (lib "eagle-import") (part "MA05-2"))
    )
    (comp (ref "SV146")
      (value "MA05-2")
      (footprint "eagle-import:MA05-2")
      (libsource (lib "eagle-import") (part "MA05-2"))
    )
    (comp (ref "SV147")
      (value "MA05-2")
      (footprint "eagle-import:MA05-2")
      (libsource (lib "eagle-import") (part "MA05-2"))
    )
    (comp (ref "SV148")
      (value "MA05-2")
      (footprint "eagle-import:MA05-2")
      (libsource (lib "eagle-import") (part "MA05-2"))
    )
    (comp (ref "SV149")
      (value "MA05-2")
      (footprint "eagle-import:MA05-2")
      (libsource (lib "eagle-import") (part "MA05-2"))
    )
    (comp (ref "SV150")
      (value "MA05-2")
      (footprint "eagle-import:MA05-2")
      (libsource (lib "eagle-import") (part "MA05-2"))
    )
    (comp (ref "SV151")
      (value "MA05-2")
      (footprint "eagle-import:MA05-2")
      (libsource (lib "eagle-import") (part "MA05-2"))
    )
    (comp (ref "SV152")
      (value "MA05-2")
      (footprint "eagle-import:MA05-2")
      (libsource (lib "eagle-import") (part "MA05-2"))
    )
    (comp (ref "SV153")
      (value "MA05-2")
      (footprint "eagle-import:MA05-2")
      (libsource (lib "eagle-import") (part "MA05-2"))
    )
    (comp (ref "SV154")
      (value "MA05-2")
      (footprint "eagle-import:MA05-2")
      (libsource (lib "eagle-import") (part "MA05-2"))
    )
    (comp (ref "SV155")
      (value "MA05-2")
      (footprint "eagle-import:MA05-2")
      (libsource (lib "eagle-import") (part "MA05-2"))
    )
    (comp (ref "SV156")
      (value "MA05-2")
      (footprint "eagle-import:MA05-2")
      (libsource (lib "eagle-import") (part "MA05-2"))
    )
    (comp (ref "SV157")
      (value "MA05-2")
      (footprint "eagle-import:MA05-2")
      (libsource (lib "eagle-import") (part "MA05-2"))
    )
    (comp (ref "SV158")
      (value "MA05-2")
      (footprint "eagle-import:MA05-2")
      (libsource (lib "eagle-import") (part "MA05-2"))
    )
    (comp (ref "SV159")
      (value "MA05-2")
      (footprint "eagle-import:MA05-2")
      (libsource (lib "eagle-import") (part "MA05-2"))
    )
    (comp (ref "SV160")
      (value "MA05-2")
      (footprint "eagle-import:MA05-2")
      (libsource (lib "eagle-import") (part "MA05-2"))
    )
    (comp (ref "SV161")
      (value "MA05-2")
      (footprint "eagle-import:MA05-2")
      (libsource (lib "eagle-import") (part "MA05-2"))
    )
    (comp (ref "SV162")
      (value "MA05-2")
      (footprint "eagle-import:MA05-2")
      (libsource (lib "eagle-import") (part "MA05-2"))
    )
    (comp (ref "SV163")
      (value "MA05-2")
      (footprint "eagle-import:MA05-2")
      (libsource (lib "eagle-import") (part "MA05-2"))
    )
    (comp (ref "SV164")
      (value "MA05-2")
      (footprint "eagle-import:MA05-2")
      (libsource (lib "eagle-import") (part "MA05-2"))
    )
    (comp (ref "SV165")
      (value "MA05-2")
      (footprint "eagle-import:MA05-2")
      (libsource (lib "eagle-import") (part "MA05-2"))
    )
    (comp (ref "SV166")
      (value "MA05-2")
      (footprint "eagle-import:MA05-2")
      (libsource (lib "eagle-import") (part "MA05-2"))
    )
    (comp (ref "SV167")
      (value "MA05-2")
      (footprint "eagle-import:MA05-2")
      (libsource (lib "eagle-import") (part "MA05-2"))
    )
    (comp (ref "SV168")
      (value "MA05-2")
      (footprint "eagle-import:MA05-2")
      (libsource (lib "eagle-import") (part "MA05-2"))
    )
    (comp (ref "SV169")
      (value "MA05-2")
      (footprint "eagle-import:MA05-2")
      (libsource (lib "eagle-import") (part "MA05-2"))
    )
    (comp (ref "SV170")
      (value "MA05-2")
      (footprint "eagle-import:MA05-2")
      (libsource (lib "eagle-import") (part "MA05-2"))
    )
    (comp (ref "SV171")
      (value "MA05-2")
      (footprint "eagle-import:MA05-2")
      (libsource (lib "eagle-import") (part "MA05-2"))
    )
    (comp (ref "SV172")
      (value "MA05-2")
      (footprint "eagle-import:MA05-2")
      (libsource (lib "eagle-import") (part "MA05-2"))
    )
    (comp (ref "SV173")
      (value "MA05-2")
      (footprint "eagle-import:MA05-2")
      (libsource (lib "eagle-import") (part "MA05-2"))
    )
    (comp (ref "SV174")
      (value "MA05-2")
      (footprint "eagle-import:MA05-2")
      (libsource (lib "eagle-import") (part "MA05-2"))
    )
    (comp (ref "SV175")
      (value "MA20-1")
      (footprint "eagle-import:MA20-1")
      (libsource (lib "eagle-import") (part "MA20-1"))
    )
    (comp (ref "SV176")
      (value "MA20-1")
      (footprint "eagle-import:MA20-1")
      (libsource (lib "eagle-import") (part "MA20-1"))
    )
    (comp (ref "SV177")
      (value "MA08-1")
      (footprint "eagle-import:MA08-1")
      (libsource (lib "eagle-import") (part "MA08-1"))
    )
    (comp (ref "SV178")
      (value "MA08-1")
      (footprint "eagle-import:MA08-1")
      (libsource (lib "eagle-import") (part "MA08-1"))
    )
    (comp (ref "SV179")
      (value "MA10-1")
      (footprint "eagle-import:MA10-1")
      (libsource (lib "eagle-import") (part "MA10-1"))
    )
    (comp (ref "SV180")
      (value "MA10-1")
      (footprint "eagle-import:MA10-1")
      (libsource (lib "eagle-import") (part "MA10-1"))
    )
    (comp (ref "A1")
      (value "JP1E")
      (footprint "eagle-import:JP1")
      (libsource (lib "eagle-import") (part "JP1E"))
    )
    (comp (ref "A2")
      (value "JP1E")
      (footprint "eagle-import:JP1")
      (libsource (lib "eagle-import") (part "JP1E"))
    )
    (comp (ref "A3")
      (value "JP1E")
      (footprint "eagle-import:JP1")
      (libsource (lib "eagle-import") (part "JP1E"))
    )
    (comp (ref "A4")
      (value "JP1E")
      (footprint "eagle-import:JP1")
      (libsource (lib "eagle-import") (part "JP1E"))
    )
    (comp (ref "A5")
      (value "JP1E")
      (footprint "eagle-import:JP1")
      (libsource (lib "eagle-import") (part "JP1E"))
    )
    (comp (ref "A6")
      (value "JP1E")
      (footprint "eagle-import:JP1")
      (libsource (lib "eagle-import") (part "JP1E"))
    )
    (comp (ref "A7")
      (value "JP1E")
      (footprint "eagle-import:JP1")
      (libsource (lib "eagle-import") (part "JP1E"))
    )
    (comp (ref "A8")
      (value "JP1E")
      (footprint "eagle-import:JP1")
      (libsource (lib "eagle-import") (part "JP1E"))
    )
    (comp (ref "A9")
      (value "JP1E")
      (footprint "eagle-import:JP1")
      (libsource (lib "eagle-import") (part "JP1E"))
    )
    (comp (ref "A10")
      (value "JP1E")
      (footprint "eagle-import:JP1")
      (libsource (lib "eagle-import") (part "JP1E"))
    )
    (comp (ref "A11")
      (value "JP1E")
      (footprint "eagle-import:JP1")
      (libsource (lib "eagle-import") (part "JP1E"))
    )
    (comp (ref "A12")
      (value "JP1E")
      (footprint "eagle-import:JP1")
      (libsource (lib "eagle-import") (part "JP1E"))
    )
    (comp (ref "A13")
      (value "JP1E")
      (footprint "eagle-import:JP1")
      (libsource (lib "eagle-import") (part "JP1E"))
    )
    (comp (ref "A14")
      (value "JP1E")
      (footprint "eagle-import:JP1")
      (libsource (lib "eagle-import") (part "JP1E"))
    )
    (comp (ref "A15")
      (value "JP1E")
      (footprint "eagle-import:JP1")
      (libsource (lib "eagle-import") (part "JP1E"))
    )
    (comp (ref "A16")
      (value "JP1E")
      (footprint "eagle-import:JP1")
      (libsource (lib "eagle-import") (part "JP1E"))
    )
    (comp (ref "A17")
      (value "JP1E")
      (footprint "eagle-import:JP1")
      (libsource (lib "eagle-import") (part "JP1E"))
    )
    (comp (ref "A18")
      (value "JP1E")
      (footprint "eagle-import:JP1")
      (libsource (lib "eagle-import") (part "JP1E"))
    )
    (comp (ref "A19")
      (value "JP1E")
      (footprint "eagle-import:JP1")
      (libsource (lib "eagle-import") (part "JP1E"))
    )
    (comp (ref "A20")
      (value "JP1E")
      (footprint "eagle-import:JP1")
      (libsource (lib "eagle-import") (part "JP1E"))
    )
    (comp (ref "A21")
      (value "JP1E")
      (footprint "eagle-import:JP1")
      (libsource (lib "eagle-import") (part "JP1E"))
    )
    (comp (ref "A22")
      (value "JP1E")
      (footprint "eagle-import:JP1")
      (libsource (lib "eagle-import") (part "JP1E"))
    )
    (comp (ref "A23")
      (value "JP1E")
      (footprint "eagle-import:JP1")
      (libsource (lib "eagle-import") (part "JP1E"))
    )
    (comp (ref "A24")
      (value "JP1E")
      (footprint "eagle-import:JP1")
      (libsource (lib "eagle-import") (part "JP1E"))
    )
    (comp (ref "A25")
      (value "JP1E")
      (footprint "eagle-import:JP1")
      (libsource (lib "eagle-import") (part "JP1E"))
    )
    (comp (ref "A26")
      (value "JP1E")
      (footprint "eagle-import:JP1")
      (libsource (lib "eagle-import") (part "JP1E"))
    )
    (comp (ref "A27")
      (value "JP1E")
      (footprint "eagle-import:JP1")
      (libsource (lib "eagle-import") (part "JP1E"))
    )
    (comp (ref "A28")
      (value "JP1E")
      (footprint "eagle-import:JP1")
      (libsource (lib "eagle-import") (part "JP1E"))
    )
    (comp (ref "A29")
      (value "JP1E")
      (footprint "eagle-import:JP1")
      (libsource (lib "eagle-import") (part "JP1E"))
    )
    (comp (ref "A30")
      (value "JP1E")
      (footprint "eagle-import:JP1")
      (libsource (lib "eagle-import") (part "JP1E"))
    )
    (comp (ref "A31")
      (value "JP1E")
      (footprint "eagle-import:JP1")
      (libsource (lib "eagle-import") (part "JP1E"))
    )
    (comp (ref "A32")
      (value "JP1E")
      (footprint "eagle-import:JP1")
      (libsource (lib "eagle-import") (part "JP1E"))
    )
    (comp (ref "A33")
      (value "JP1E")
      (footprint "eagle-import:JP1")
      (libsource (lib "eagle-import") (part "JP1E"))
    )
    (comp (ref "A34")
      (value "JP1E")
      (footprint "eagle-import:JP1")
      (libsource (lib "eagle-import") (part "JP1E"))
    )
    (comp (ref "A35")
      (value "JP1E")
      (footprint "eagle-import:JP1")
      (libsource (lib "eagle-import") (part "JP1E"))
    )
    (comp (ref "A36")
      (value "JP1E")
      (footprint "eagle-import:JP1")
      (libsource (lib "eagle-import") (part "JP1E"))
    )
    (comp (ref "A37")
      (value "JP1E")
      (footprint "eagle-import:JP1")
      (libsource (lib "eagle-import") (part "JP1E"))
    )
    (comp (ref "A38")
      (value "JP1E")
      (footprint "eagle-import:JP1")
      (libsource (lib "eagle-import") (part "JP1E"))
    )
    (comp (ref "A39")
      (value "JP1E")
      (footprint "eagle-import:JP1")
      (libsource (lib "eagle-import") (part "JP1E"))
    )
    (comp (ref "A40")
      (value "JP1E")
      (footprint "eagle-import:JP1")
      (libsource (lib "eagle-import") (part "JP1E"))
    )
    (comp (ref "A41")
      (value "JP1E")
      (footprint "eagle-import:JP1")
      (libsource (lib "eagle-import") (part "JP1E"))
    )
    (comp (ref "A42")
      (value "JP1E")
      (footprint "eagle-import:JP1")
      (libsource (lib "eagle-import") (part "JP1E"))
    )
    (comp (ref "A43")
      (value "JP1E")
      (footprint "eagle-import:JP1")
      (libsource (lib "eagle-import") (part "JP1E"))
    )
    (comp (ref "A44")
      (value "JP1E")
      (footprint "eagle-import:JP1")
      (libsource (lib "eagle-import") (part "JP1E"))
    )
    (comp (ref "A45")
      (value "JP1E")
      (footprint "eagle-import:JP1")
      (libsource (lib "eagle-import") (part "JP1E"))
    )
    (comp (ref "A46")
      (value "JP1E")
      (footprint "eagle-import:JP1")
      (libsource (lib "eagle-import") (part "JP1E"))
    )
    (comp (ref "A47")
      (value "JP1E")
      (footprint "eagle-import:JP1")
      (libsource (lib "eagle-import") (part "JP1E"))
    )
    (comp (ref "A48")
      (value "JP1E")
      (footprint "eagle-import:JP1")
      (libsource (lib "eagle-import") (part "JP1E"))
    )
    (comp (ref "A49")
      (value "JP1E")
      (footprint "eagle-import:JP1")
      (libsource (lib "eagle-import") (part "JP1E"))
    )
    (comp (ref "A50")
      (value "JP1E")
      (footprint "eagle-import:JP1")
      (libsource (lib "eagle-import") (part "JP1E"))
    )
    (comp (ref "A51")
      (value "JP1E")
      (footprint "eagle-import:JP1")
      (libsource (lib "eagle-import") (part "JP1E"))
    )
    (comp (ref "A52")
      (value "JP1E")
      (footprint "eagle-import:JP1")
      (libsource (lib "eagle-import") (part "JP1E"))
    )
    (comp (ref "A53")
      (value "JP1E")
      (footprint "eagle-import:JP1")
      (libsource (lib "eagle-import") (part "JP1E"))
    )
    (comp (ref "A54")
      (value "JP1E")
      (footprint "eagle-import:JP1")
      (libsource (lib "eagle-import") (part "JP1E"))
    )
    (comp (ref "A55")
      (value "JP1E")
      (footprint "eagle-import:JP1")
      (libsource (lib "eagle-import") (part "JP1E"))
    )
    (comp (ref "A56")
      (value "JP1E")
      (footprint "eagle-import:JP1")
      (libsource (lib "eagle-import") (part "JP1E"))
    )
    (comp (ref "A57")
      (value "JP1E")
      (footprint "eagle-import:JP1")
      (libsource (lib "eagle-import") (part "JP1E"))
    )
    (comp (ref "A58")
      (value "JP1E")
      (footprint "eagle-import:JP1")
      (libsource (lib "eagle-import") (part "JP1E"))
    )
    (comp (ref "A59")
      (value "JP1E")
      (footprint "eagle-import:JP1")
      (libsource (lib "eagle-import") (part "JP1E"))
    )
    (comp (ref "A60")
      (value "JP1E")
      (footprint "eagle-import:JP1")
      (libsource (lib "eagle-import") (part "JP1E"))
    )
    (comp (ref "A61")
      (value "JP1E")
      (footprint "eagle-import:JP1")
      (libsource (lib "eagle-import") (part "JP1E"))
    )
    (comp (ref "A62")
      (value "JP1E")
      (footprint "eagle-import:JP1")
      (libsource (lib "eagle-import") (part "JP1E"))
    )
    (comp (ref "A63")
      (value "JP1E")
      (footprint "eagle-import:JP1")
      (libsource (lib "eagle-import") (part "JP1E"))
    )
    (comp (ref "A64")
      (value "JP1E")
      (footprint "eagle-import:JP1")
      (libsource (lib "eagle-import") (part "JP1E"))
    )
    (comp (ref "A65")
      (value "JP1E")
      (footprint "eagle-import:JP1")
      (libsource (lib "eagle-import") (part "JP1E"))
    )
    (comp (ref "A66")
      (value "JP1E")
      (footprint "eagle-import:JP1")
      (libsource (lib "eagle-import") (part "JP1E"))
    )
    (comp (ref "A67")
      (value "JP1E")
      (footprint "eagle-import:JP1")
      (libsource (lib "eagle-import") (part "JP1E"))
    )
    (comp (ref "A68")
      (value "JP1E")
      (footprint "eagle-import:JP1")
      (libsource (lib "eagle-import") (part "JP1E"))
    )
    (comp (ref "A69")
      (value "JP1E")
      (footprint "eagle-import:JP1")
      (libsource (lib "eagle-import") (part "JP1E"))
    )
    (comp (ref "A70")
      (value "JP1E")
      (footprint "eagle-import:JP1")
      (libsource (lib "eagle-import") (part "JP1E"))
    )
    (comp (ref "A71")
      (value "JP1E")
      (footprint "eagle-import:JP1")
      (libsource (lib "eagle-import") (part "JP1E"))
    )
    (comp (ref "A72")
      (value "JP1E")
      (footprint "eagle-import:JP1")
      (libsource (lib "eagle-import") (part "JP1E"))
    )
    (comp (ref "A73")
      (value "JP1E")
      (footprint "eagle-import:JP1")
      (libsource (lib "eagle-import") (part "JP1E"))
    )
    (comp (ref "A74")
      (value "JP1E")
      (footprint "eagle-import:JP1")
      (libsource (lib "eagle-import") (part "JP1E"))
    )
    (comp (ref "A75")
      (value "JP1E")
      (footprint "eagle-import:JP1")
      (libsource (lib "eagle-import") (part "JP1E"))
    )
    (comp (ref "A76")
      (value "JP1E")
      (footprint "eagle-import:JP1")
      (libsource (lib "eagle-import") (part "JP1E"))
    )
    (comp (ref "A77")
      (value "JP1E")
      (footprint "eagle-import:JP1")
      (libsource (lib "eagle-import") (part "JP1E"))
    )
    (comp (ref "A78")
      (value "JP1E")
      (footprint "eagle-import:JP1")
      (libsource (lib "eagle-import") (part "JP1E"))
    )
    (comp (ref "A79")
      (value "JP1E")
      (footprint "eagle-import:JP1")
      (libsource (lib "eagle-import") (part "JP1E"))
    )
    (comp (ref "A80")
      (value "JP1E")
      (footprint "eagle-import:JP1")
      (libsource (lib "eagle-import") (part "JP1E"))
    )
    (comp (ref "A81")
      (value "JP1E")
      (footprint "eagle-import:JP1")
      (libsource (lib "eagle-import") (part "JP1E"))
    )
    (comp (ref "A82")
      (value "JP1E")
      (footprint "eagle-import:JP1")
      (libsource (lib "eagle-import") (part "JP1E"))
    )
    (comp (ref "A83")
      (value "JP1E")
      (footprint "eagle-import:JP1")
      (libsource (lib "eagle-import") (part "JP1E"))
    )
    (comp (ref "A84")
      (value "JP1E")
      (footprint "eagle-import:JP1")
      (libsource (lib "eagle-import") (part "JP1E"))
    )
    (comp (ref "A85")
      (value "JP1E")
      (footprint "eagle-import:JP1")
      (libsource (lib "eagle-import") (part "JP1E"))
    )
    (comp (ref "A86")
      (value "JP1E")
      (footprint "eagle-import:JP1")
      (libsource (lib "eagle-import") (part "JP1E"))
    )
    (comp (ref "A87")
      (value "JP1E")
      (footprint "eagle-import:JP1")
      (libsource (lib "eagle-import") (part "JP1E"))
    )
    (comp (ref "A88")
      (value "JP1E")
      (footprint "eagle-import:JP1")
      (libsource (lib "eagle-import") (part "JP1E"))
    )
    (comp (ref "A89")
      (value "JP1E")
      (footprint "eagle-import:JP1")
      (libsource (lib "eagle-import") (part "JP1E"))
    )
    (comp (ref "A90")
      (value "JP1E")
      (footprint "eagle-import:JP1")
      (libsource (lib "eagle-import") (part "JP1E"))
    )
    (comp (ref "A91")
      (value "JP1E")
      (footprint "eagle-import:JP1")
      (libsource (lib "eagle-import") (part "JP1E"))
    )
    (comp (ref "A92")
      (value "JP1E")
      (footprint "eagle-import:JP1")
      (libsource (lib "eagle-import") (part "JP1E"))
    )
    (comp (ref "A93")
      (value "JP1E")
      (footprint "eagle-import:JP1")
      (libsource (lib "eagle-import") (part "JP1E"))
    )
    (comp (ref "A94")
      (value "JP1E")
      (footprint "eagle-import:JP1")
      (libsource (lib "eagle-import") (part "JP1E"))
    )
    (comp (ref "A95")
      (value "JP1E")
      (footprint "eagle-import:JP1")
      (libsource (lib "eagle-import") (part "JP1E"))
    )
    (comp (ref "A96")
      (value "JP1E")
      (footprint "eagle-import:JP1")
      (libsource (lib "eagle-import") (part "JP1E"))
    )
    (comp (ref "A97")
      (value "JP1E")
      (footprint "eagle-import:JP1")
      (libsource (lib "eagle-import") (part "JP1E"))
    )
    (comp (ref "A98")
      (value "JP1E")
      (footprint "eagle-import:JP1")
      (libsource (lib "eagle-import") (part "JP1E"))
    )
    (comp (ref "A99")
      (value "JP1E")
      (footprint "eagle-import:JP1")
      (libsource (lib "eagle-import") (part "JP1E"))
    )
    (comp (ref "A100")
      (value "JP1E")
      (footprint "eagle-import:JP1")
      (libsource (lib "eagle-import") (part "JP1E"))
    )
    (comp (ref "A101")
      (value "JP1E")
      (footprint "eagle-import:JP1")
      (libsource (lib "eagle-import") (part "JP1E"))
    )
    (comp (ref "A102")
      (value "JP1E")
      (footprint "eagle-import:JP1")
      (libsource (lib "eagle-import") (part "JP1E"))
    )
    (comp (ref "A103")
      (value "JP1E")
      (footprint "eagle-import:JP1")
      (libsource (lib "eagle-import") (part "JP1E"))
    )
    (comp (ref "A104")
      (value "JP1E")
      (footprint "eagle-import:JP1")
      (libsource (lib "eagle-import") (part "JP1E"))
    )
    (comp (ref "A105")
      (value "JP1E")
      (footprint "eagle-import:JP1")
      (libsource (lib "eagle-import") (part "JP1E"))
    )
    (comp (ref "A106")
      (value "JP1E")
      (footprint "eagle-import:JP1")
      (libsource (lib "eagle-import") (part "JP1E"))
    )
    (comp (ref "A107")
      (value "JP1E")
      (footprint "eagle-import:JP1")
      (libsource (lib "eagle-import") (part "JP1E"))
    )
    (comp (ref "A108")
      (value "JP1E")
      (footprint "eagle-import:JP1")
      (libsource (lib "eagle-import") (part "JP1E"))
    )
    (comp (ref "A109")
      (value "JP1E")
      (footprint "eagle-import:JP1")
      (libsource (lib "eagle-import") (part "JP1E"))
    )
    (comp (ref "A110")
      (value "JP1E")
      (footprint "eagle-import:JP1")
      (libsource (lib "eagle-import") (part "JP1E"))
    )
    (comp (ref "A111")
      (value "JP1E")
      (footprint "eagle-import:JP1")
      (libsource (lib "eagle-import") (part "JP1E"))
    )
    (comp (ref "A112")
      (value "JP1E")
      (footprint "eagle-import:JP1")
      (libsource (lib "eagle-import") (part "JP1E"))
    )
    (comp (ref "A113")
      (value "JP1E")
      (footprint "eagle-import:JP1")
      (libsource (lib "eagle-import") (part "JP1E"))
    )
    (comp (ref "A114")
      (value "JP1E")
      (footprint "eagle-import:JP1")
      (libsource (lib "eagle-import") (part "JP1E"))
    )
    (comp (ref "A115")
      (value "JP1E")
      (footprint "eagle-import:JP1")
      (libsource (lib "eagle-import") (part "JP1E"))
    )
    (comp (ref "A116")
      (value "JP1E")
      (footprint "eagle-import:JP1")
      (libsource (lib "eagle-import") (part "JP1E"))
    )
    (comp (ref "A117")
      (value "JP1E")
      (footprint "eagle-import:JP1")
      (libsource (lib "eagle-import") (part "JP1E"))
    )
    (comp (ref "A118")
      (value "JP1E")
      (footprint "eagle-import:JP1")
      (libsource (lib "eagle-import") (part "JP1E"))
    )
    (comp (ref "A119")
      (value "JP1E")
      (footprint "eagle-import:JP1")
      (libsource (lib "eagle-import") (part "JP1E"))
    )
    (comp (ref "A120")
      (value "JP1E")
      (footprint "eagle-import:JP1")
      (libsource (lib "eagle-import") (part "JP1E"))
    )
    (comp (ref "A121")
      (value "JP1E")
      (footprint "eagle-import:JP1")
      (libsource (lib "eagle-import") (part "JP1E"))
    )
    (comp (ref "A122")
      (value "JP1E")
      (footprint "eagle-import:JP1")
      (libsource (lib "eagle-import") (part "JP1E"))
    )
    (comp (ref "A123")
      (value "JP1E")
      (footprint "eagle-import:JP1")
      (libsource (lib "eagle-import") (part "JP1E"))
    )
    (comp (ref "A124")
      (value "JP1E")
      (footprint "eagle-import:JP1")
      (libsource (lib "eagle-import") (part "JP1E"))
    )
    (comp (ref "A125")
      (value "JP1E")
      (footprint "eagle-import:JP1")
      (libsource (lib "eagle-import") (part "JP1E"))
    )
    (comp (ref "A126")
      (value "JP1E")
      (footprint "eagle-import:JP1")
      (libsource (lib "eagle-import") (part "JP1E"))
    )
    (comp (ref "A127")
      (value "JP1E")
      (footprint "eagle-import:JP1")
      (libsource (lib "eagle-import") (part "JP1E"))
    )
    (comp (ref "A128")
      (value "JP1E")
      (footprint "eagle-import:JP1")
      (libsource (lib "eagle-import") (part "JP1E"))
    )
    (comp (ref "A129")
      (value "JP1E")
      (footprint "eagle-import:JP1")
      (libsource (lib "eagle-import") (part "JP1E"))
    )
    (comp (ref "A130")
      (value "JP1E")
      (footprint "eagle-import:JP1")
      (libsource (lib "eagle-import") (part "JP1E"))
    )
    (comp (ref "A131")
      (value "JP1E")
      (footprint "eagle-import:JP1")
      (libsource (lib "eagle-import") (part "JP1E"))
    )
    (comp (ref "A132")
      (value "JP1E")
      (footprint "eagle-import:JP1")
      (libsource (lib "eagle-import") (part "JP1E"))
    )
    (comp (ref "A133")
      (value "JP1E")
      (footprint "eagle-import:JP1")
      (libsource (lib "eagle-import") (part "JP1E"))
    )
    (comp (ref "A134")
      (value "JP1E")
      (footprint "eagle-import:JP1")
      (libsource (lib "eagle-import") (part "JP1E"))
    )
    (comp (ref "A135")
      (value "JP1E")
      (footprint "eagle-import:JP1")
      (libsource (lib "eagle-import") (part "JP1E"))
    )
    (comp (ref "A136")
      (value "JP1E")
      (footprint "eagle-import:JP1")
      (libsource (lib "eagle-import") (part "JP1E"))
    )
    (comp (ref "A137")
      (value "JP1E")
      (footprint "eagle-import:JP1")
      (libsource (lib "eagle-import") (part "JP1E"))
    )
    (comp (ref "A138")
      (value "JP1E")
      (footprint "eagle-import:JP1")
      (libsource (lib "eagle-import") (part "JP1E"))
    )
    (comp (ref "A139")
      (value "JP1E")
      (footprint "eagle-import:JP1")
      (libsource (lib "eagle-import") (part "JP1E"))
    )
    (comp (ref "A140")
      (value "JP1E")
      (footprint "eagle-import:JP1")
      (libsource (lib "eagle-import") (part "JP1E"))
    )
    (comp (ref "A141")
      (value "JP1E")
      (footprint "eagle-import:JP1")
      (libsource (lib "eagle-import") (part "JP1E"))
    )
    (comp (ref "A142")
      (value "JP1E")
      (footprint "eagle-import:JP1")
      (libsource (lib "eagle-import") (part "JP1E"))
    )
    (comp (ref "A143")
      (value "JP1E")
      (footprint "eagle-import:JP1")
      (libsource (lib "eagle-import") (part "JP1E"))
    )
    (comp (ref "A144")
      (value "JP1E")
      (footprint "eagle-import:JP1")
      (libsource (lib "eagle-import") (part "JP1E"))
    )
    (comp (ref "A145")
      (value "JP1E")
      (footprint "eagle-import:JP1")
      (libsource (lib "eagle-import") (part "JP1E"))
    )
    (comp (ref "A146")
      (value "JP1E")
      (footprint "eagle-import:JP1")
      (libsource (lib "eagle-import") (part "JP1E"))
    )
    (comp (ref "A147")
      (value "JP1E")
      (footprint "eagle-import:JP1")
      (libsource (lib "eagle-import") (part "JP1E"))
    )
    (comp (ref "A148")
      (value "JP1E")
      (footprint "eagle-import:JP1")
      (libsource (lib "eagle-import") (part "JP1E"))
    )
    (comp (ref "A149")
      (value "JP1E")
      (footprint "eagle-import:JP1")
      (libsource (lib "eagle-import") (part "JP1E"))
    )
    (comp (ref "A150")
      (value "JP1E")
      (footprint "eagle-import:JP1")
      (libsource (lib "eagle-import") (part "JP1E"))
    )
    (comp (ref "A151")
      (value "JP1E")
      (footprint "eagle-import:JP1")
      (libsource (lib "eagle-import") (part "JP1E"))
    )
    (comp (ref "A152")
      (value "JP1E")
      (footprint "eagle-import:JP1")
      (libsource (lib "eagle-import") (part "JP1E"))
    )
    (comp (ref "A153")
      (value "JP1E")
      (footprint "eagle-import:JP1")
      (libsource (lib "eagle-import") (part "JP1E"))
    )
    (comp (ref "A154")
      (value "JP1E")
      (footprint "eagle-import:JP1")
      (libsource (lib "eagle-import") (part "JP1E"))
    )
    (comp (ref "A155")
      (value "JP1E")
      (footprint "eagle-import:JP1")
      (libsource (lib "eagle-import") (part "JP1E"))
    )
    (comp (ref "A156")
      (value "JP1E")
      (footprint "eagle-import:JP1")
      (libsource (lib "eagle-import") (part "JP1E"))
    )
    (comp (ref "A157")
      (value "JP1E")
      (footprint "eagle-import:JP1")
      (libsource (lib "eagle-import") (part "JP1E"))
    )
    (comp (ref "A158")
      (value "JP1E")
      (footprint "eagle-import:JP1")
      (libsource (lib "eagle-import") (part "JP1E"))
    )
    (comp (ref "A159")
      (value "JP1E")
      (footprint "eagle-import:JP1")
      (libsource (lib "eagle-import") (part "JP1E"))
    )
    (comp (ref "A160")
      (value "JP1E")
      (footprint "eagle-import:JP1")
      (libsource (lib "eagle-import") (part "JP1E"))
    )
    (comp (ref "A161")
      (value "JP1E")
      (footprint "eagle-import:JP1")
      (libsource (lib "eagle-import") (part "JP1E"))
    )
    (comp (ref "A162")
      (value "JP1E")
      (footprint "eagle-import:JP1")
      (libsource (lib "eagle-import") (part "JP1E"))
    )
    (comp (ref "A163")
      (value "JP1E")
      (footprint "eagle-import:JP1")
      (libsource (lib "eagle-import") (part "JP1E"))
    )
    (comp (ref "A164")
      (value "JP1E")
      (footprint "eagle-import:JP1")
      (libsource (lib "eagle-import") (part "JP1E"))
    )
    (comp (ref "A165")
      (value "JP1E")
      (footprint "eagle-import:JP1")
      (libsource (lib "eagle-import") (part "JP1E"))
    )
    (comp (ref "A166")
      (value "JP1E")
      (footprint "eagle-import:JP1")
      (libsource (lib "eagle-import") (part "JP1E"))
    )
    (comp (ref "A167")
      (value "JP1E")
      (footprint "eagle-import:JP1")
      (libsource (lib "eagle-import") (part "JP1E"))
    )
    (comp (ref "A168")
      (value "JP1E")
      (footprint "eagle-import:JP1")
      (libsource (lib "eagle-import") (part "JP1E"))
    )
    (comp (ref "A169")
      (value "JP1E")
      (footprint "eagle-import:JP1")
      (libsource (lib "eagle-import") (part "JP1E"))
    )
    (comp (ref "A170")
      (value "JP1E")
      (footprint "eagle-import:JP1")
      (libsource (lib "eagle-import") (part "JP1E"))
    )
    (comp (ref "A171")
      (value "JP1E")
      (footprint "eagle-import:JP1")
      (libsource (lib "eagle-import") (part "JP1E"))
    )
    (comp (ref "A172")
      (value "JP1E")
      (footprint "eagle-import:JP1")
      (libsource (lib "eagle-import") (part "JP1E"))
    )
    (comp (ref "A173")
      (value "JP1E")
      (footprint "eagle-import:JP1")
      (libsource (lib "eagle-import") (part "JP1E"))
    )
    (comp (ref "A174")
      (value "JP1E")
      (footprint "eagle-import:JP1")
      (libsource (lib "eagle-import") (part "JP1E"))
    )
    (comp (ref "A175")
      (value "JP1E")
      (footprint "eagle-import:JP1")
      (libsource (lib "eagle-import") (part "JP1E"))
    )
    (comp (ref "A176")
      (value "JP1E")
      (footprint "eagle-import:JP1")
      (libsource (lib "eagle-import") (part "JP1E"))
    )
    (comp (ref "A177")
      (value "JP1E")
      (footprint "eagle-import:JP1")
      (libsource (lib "eagle-import") (part "JP1E"))
    )
    (comp (ref "A178")
      (value "JP1E")
      (footprint "eagle-import:JP1")
      (libsource (lib "eagle-import") (part "JP1E"))
    )
    (comp (ref "A179")
      (value "JP1E")
      (footprint "eagle-import:JP1")
      (libsource (lib "eagle-import") (part "JP1E"))
    )
    (comp (ref "A180")
      (value "JP1E")
      (footprint "eagle-import:JP1")
      (libsource (lib "eagle-import") (part "JP1E"))
    )
    (comp (ref "A181")
      (value "JP1E")
      (footprint "eagle-import:JP1")
      (libsource (lib "eagle-import") (part "JP1E"))
    )
    (comp (ref "A182")
      (value "JP1E")
      (footprint "eagle-import:JP1")
      (libsource (lib "eagle-import") (part "JP1E"))
    )
    (comp (ref "A183")
      (value "JP1E")
      (footprint "eagle-import:JP1")
      (libsource (lib "eagle-import") (part "JP1E"))
    )
    (comp (ref "A184")
      (value "JP1E")
      (footprint "eagle-import:JP1")
      (libsource (lib "eagle-import") (part "JP1E"))
    )
    (comp (ref "A185")
      (value "JP1E")
      (footprint "eagle-import:JP1")
      (libsource (lib "eagle-import") (part "JP1E"))
    )
    (comp (ref "A186")
      (value "JP1E")
      (footprint "eagle-import:JP1")
      (libsource (lib "eagle-import") (part "JP1E"))
    )
    (comp (ref "A187")
      (value "JP1E")
      (footprint "eagle-import:JP1")
      (libsource (lib "eagle-import") (part "JP1E"))
    )
    (comp (ref "A188")
      (value "JP1E")
      (footprint "eagle-import:JP1")
      (libsource (lib "eagle-import") (part "JP1E"))
    )
    (comp (ref "A189")
      (value "JP1E")
      (footprint "eagle-import:JP1")
      (libsource (lib "eagle-import") (part "JP1E"))
    )
    (comp (ref "A190")
      (value "JP1E")
      (footprint "eagle-import:JP1")
      (libsource (lib "eagle-import") (part "JP1E"))
    )
    (comp (ref "A191")
      (value "JP1E")
      (footprint "eagle-import:JP1")
      (libsource (lib "eagle-import") (part "JP1E"))
    )
    (comp (ref "A192")
      (value "JP1E")
      (footprint "eagle-import:JP1")
      (libsource (lib "eagle-import") (part "JP1E"))
    )
    (comp (ref "A193")
      (value "JP1E")
      (footprint "eagle-import:JP1")
      (libsource (lib "eagle-import") (part "JP1E"))
    )
    (comp (ref "A194")
      (value "JP1E")
      (footprint "eagle-import:JP1")
      (libsource (lib "eagle-import") (part "JP1E"))
    )
    (comp (ref "A195")
      (value "JP1E")
      (footprint "eagle-import:JP1")
      (libsource (lib "eagle-import") (part "JP1E"))
    )
    (comp (ref "A196")
      (value "JP1E")
      (footprint "eagle-import:JP1")
      (libsource (lib "eagle-import") (part "JP1E"))
    )
    (comp (ref "A197")
      (value "JP1E")
      (footprint "eagle-import:JP1")
      (libsource (lib "eagle-import") (part "JP1E"))
    )
    (comp (ref "A198")
      (value "JP1E")
      (footprint "eagle-import:JP1")
      (libsource (lib "eagle-import") (part "JP1E"))
    )
    (comp (ref "A199")
      (value "JP1E")
      (footprint "eagle-import:JP1")
      (libsource (lib "eagle-import") (part "JP1E"))
    )
    (comp (ref "A200")
      (value "JP1E")
      (footprint "eagle-import:JP1")
      (libsource (lib "eagle-import") (part "JP1E"))
    )
    (comp (ref "A201")
      (value "JP1E")
      (footprint "eagle-import:JP1")
      (libsource (lib "eagle-import") (part "JP1E"))
    )
    (comp (ref "A202")
      (value "JP1E")
      (footprint "eagle-import:JP1")
      (libsource (lib "eagle-import") (part "JP1E"))
    )
    (comp (ref "A203")
      (value "JP1E")
      (footprint "eagle-import:JP1")
      (libsource (lib "eagle-import") (part "JP1E"))
    )
    (comp (ref "A204")
      (value "JP1E")
      (footprint "eagle-import:JP1")
      (libsource (lib "eagle-import") (part "JP1E"))
    )
    (comp (ref "A205")
      (value "JP1E")
      (footprint "eagle-import:JP1")
      (libsource (lib "eagle-import") (part "JP1E"))
    )
    (comp (ref "A206")
      (value "JP1E")
      (footprint "eagle-import:JP1")
      (libsource (lib "eagle-import") (part "JP1E"))
    )
    (comp (ref "A207")
      (value "JP1E")
      (footprint "eagle-import:JP1")
      (libsource (lib "eagle-import") (part "JP1E"))
    )
    (comp (ref "A208")
      (value "JP1E")
      (footprint "eagle-import:JP1")
      (libsource (lib "eagle-import") (part "JP1E"))
    )
    (comp (ref "A209")
      (value "JP1E")
      (footprint "eagle-import:JP1")
      (libsource (lib "eagle-import") (part "JP1E"))
    )
    (comp (ref "A210")
      (value "JP1E")
      (footprint "eagle-import:JP1")
      (libsource (lib "eagle-import") (part "JP1E"))
    )
    (comp (ref "A211")
      (value "JP1E")
      (footprint "eagle-import:JP1")
      (libsource (lib "eagle-import") (part "JP1E"))
    )
    (comp (ref "A212")
      (value "JP1E")
      (footprint "eagle-import:JP1")
      (libsource (lib "eagle-import") (part "JP1E"))
    )
    (comp (ref "A213")
      (value "JP1E")
      (footprint "eagle-import:JP1")
      (libsource (lib "eagle-import") (part "JP1E"))
    )
    (comp (ref "A214")
      (value "JP1E")
      (footprint "eagle-import:JP1")
      (libsource (lib "eagle-import") (part "JP1E"))
    )
    (comp (ref "A215")
      (value "JP1E")
      (footprint "eagle-import:JP1")
      (libsource (lib "eagle-import") (part "JP1E"))
    )
    (comp (ref "A216")
      (value "JP1E")
      (footprint "eagle-import:JP1")
      (libsource (lib "eagle-import") (part "JP1E"))
    )
    (comp (ref "A217")
      (value "JP1E")
      (footprint "eagle-import:JP1")
      (libsource (lib "eagle-import") (part "JP1E"))
    )
    (comp (ref "A218")
      (value "JP1E")
      (footprint "eagle-import:JP1")
      (libsource (lib "eagle-import") (part "JP1E"))
    )
    (comp (ref "A219")
      (value "JP1E")
      (footprint "eagle-import:JP1")
      (libsource (lib "eagle-import") (part "JP1E"))
    )
    (comp (ref "A220")
      (value "JP1E")
      (footprint "eagle-import:JP1")
      (libsource (lib "eagle-import") (part "JP1E"))
    )
    (comp (ref "A221")
      (value "JP1E")
      (footprint "eagle-import:JP1")
      (libsource (lib "eagle-import") (part "JP1E"))
    )
    (comp (ref "A222")
      (value "JP1E")
      (footprint "eagle-import:JP1")
      (libsource (lib "eagle-import") (part "JP1E"))
    )
    (comp (ref "A223")
      (value "JP1E")
      (footprint "eagle-import:JP1")
      (libsource (lib "eagle-import") (part "JP1E"))
    )
    (comp (ref "A224")
      (value "JP1E")
      (footprint "eagle-import:JP1")
      (libsource (lib "eagle-import") (part "JP1E"))
    )
    (comp (ref "A225")
      (value "JP1E")
      (footprint "eagle-import:JP1")
      (libsource (lib "eagle-import") (part "JP1E"))
    )
    (comp (ref "A226")
      (value "JP1E")
      (footprint "eagle-import:JP1")
      (libsource (lib "eagle-import") (part "JP1E"))
    )
    (comp (ref "A227")
      (value "JP1E")
      (footprint "eagle-import:JP1")
      (libsource (lib "eagle-import") (part "JP1E"))
    )
    (comp (ref "A228")
      (value "JP1E")
      (footprint "eagle-import:JP1")
      (libsource (lib "eagle-import") (part "JP1E"))
    )
    (comp (ref "A229")
      (value "JP1E")
      (footprint "eagle-import:JP1")
      (libsource (lib "eagle-import") (part "JP1E"))
    )
    (comp (ref "A230")
      (value "JP1E")
      (footprint "eagle-import:JP1")
      (libsource (lib "eagle-import") (part "JP1E"))
    )
    (comp (ref "A231")
      (value "JP1E")
      (footprint "eagle-import:JP1")
      (libsource (lib "eagle-import") (part "JP1E"))
    )
    (comp (ref "A232")
      (value "JP1E")
      (footprint "eagle-import:JP1")
      (libsource (lib "eagle-import") (part "JP1E"))
    )
    (comp (ref "A233")
      (value "JP1E")
      (footprint "eagle-import:JP1")
      (libsource (lib "eagle-import") (part "JP1E"))
    )
    (comp (ref "A234")
      (value "JP1E")
      (footprint "eagle-import:JP1")
      (libsource (lib "eagle-import") (part "JP1E"))
    )
    (comp (ref "A235")
      (value "JP1E")
      (footprint "eagle-import:JP1")
      (libsource (lib "eagle-import") (part "JP1E"))
    )
    (comp (ref "A236")
      (value "JP1E")
      (footprint "eagle-import:JP1")
      (libsource (lib "eagle-import") (part "JP1E"))
    )
    (comp (ref "A237")
      (value "JP1E")
      (footprint "eagle-import:JP1")
      (libsource (lib "eagle-import") (part "JP1E"))
    )
    (comp (ref "A238")
      (value "JP1E")
      (footprint "eagle-import:JP1")
      (libsource (lib "eagle-import") (part "JP1E"))
    )
    (comp (ref "A239")
      (value "JP1E")
      (footprint "eagle-import:JP1")
      (libsource (lib "eagle-import") (part "JP1E"))
    )
    (comp (ref "A240")
      (value "JP1E")
      (footprint "eagle-import:JP1")
      (libsource (lib "eagle-import") (part "JP1E"))
    )
    (comp (ref "A241")
      (value "JP1E")
      (footprint "eagle-import:JP1")
      (libsource (lib "eagle-import") (part "JP1E"))
    )
    (comp (ref "A242")
      (value "JP1E")
      (footprint "eagle-import:JP1")
      (libsource (lib "eagle-import") (part "JP1E"))
    )
    (comp (ref "A243")
      (value "JP1E")
      (footprint "eagle-import:JP1")
      (libsource (lib "eagle-import") (part "JP1E"))
    )
    (comp (ref "A244")
      (value "JP1E")
      (footprint "eagle-import:JP1")
      (libsource (lib "eagle-import") (part "JP1E"))
    )
    (comp (ref "A245")
      (value "JP1E")
      (footprint "eagle-import:JP1")
      (libsource (lib "eagle-import") (part "JP1E"))
    )
    (comp (ref "A246")
      (value "JP1E")
      (footprint "eagle-import:JP1")
      (libsource (lib "eagle-import") (part "JP1E"))
    )
    (comp (ref "A247")
      (value "JP1E")
      (footprint "eagle-import:JP1")
      (libsource (lib "eagle-import") (part "JP1E"))
    )
    (comp (ref "A248")
      (value "JP1E")
      (footprint "eagle-import:JP1")
      (libsource (lib "eagle-import") (part "JP1E"))
    )
    (comp (ref "A249")
      (value "JP1E")
      (footprint "eagle-import:JP1")
      (libsource (lib "eagle-import") (part "JP1E"))
    )
    (comp (ref "A250")
      (value "JP1E")
      (footprint "eagle-import:JP1")
      (libsource (lib "eagle-import") (part "JP1E"))
    )
    (comp (ref "A251")
      (value "JP1E")
      (footprint "eagle-import:JP1")
      (libsource (lib "eagle-import") (part "JP1E"))
    )
    (comp (ref "A252")
      (value "JP1E")
      (footprint "eagle-import:JP1")
      (libsource (lib "eagle-import") (part "JP1E"))
    )
    (comp (ref "A253")
      (value "JP1E")
      (footprint "eagle-import:JP1")
      (libsource (lib "eagle-import") (part "JP1E"))
    )
    (comp (ref "A254")
      (value "JP1E")
      (footprint "eagle-import:JP1")
      (libsource (lib "eagle-import") (part "JP1E"))
    )
    (comp (ref "A255")
      (value "JP1E")
      (footprint "eagle-import:JP1")
      (libsource (lib "eagle-import") (part "JP1E"))
    )
    (comp (ref "A256")
      (value "JP1E")
      (footprint "eagle-import:JP1")
      (libsource (lib "eagle-import") (part "JP1E"))
    )
    (comp (ref "A257")
      (value "JP1E")
      (footprint "eagle-import:JP1")
      (libsource (lib "eagle-import") (part "JP1E"))
    )
    (comp (ref "A258")
      (value "JP1E")
      (footprint "eagle-import:JP1")
      (libsource (lib "eagle-import") (part "JP1E"))
    )
    (comp (ref "A259")
      (value "JP1E")
      (footprint "eagle-import:JP1")
      (libsource (lib "eagle-import") (part "JP1E"))
    )
    (comp (ref "A260")
      (value "JP1E")
      (footprint "eagle-import:JP1")
      (libsource (lib "eagle-import") (part "JP1E"))
    )
    (comp (ref "A261")
      (value "JP1E")
      (footprint "eagle-import:JP1")
      (libsource (lib "eagle-import") (part "JP1E"))
    )
    (comp (ref "A262")
      (value "JP1E")
      (footprint "eagle-import:JP1")
      (libsource (lib "eagle-import") (part "JP1E"))
    )
    (comp (ref "A263")
      (value "JP1E")
      (footprint "eagle-import:JP1")
      (libsource (lib "eagle-import") (part "JP1E"))
    )
    (comp (ref "A264")
      (value "JP1E")
      (footprint "eagle-import:JP1")
      (libsource (lib "eagle-import") (part "JP1E"))
    )
    (comp (ref "A265")
      (value "JP1E")
      (footprint "eagle-import:JP1")
      (libsource (lib "eagle-import") (part "JP1E"))
    )
    (comp (ref "A266")
      (value "JP1E")
      (footprint "eagle-import:JP1")
      (libsource (lib "eagle-import") (part "JP1E"))
    )
    (comp (ref "A267")
      (value "JP1E")
      (footprint "eagle-import:JP1")
      (libsource (lib "eagle-import") (part "JP1E"))
    )
    (comp (ref "A268")
      (value "JP1E")
      (footprint "eagle-import:JP1")
      (libsource (lib "eagle-import") (part "JP1E"))
    )
    (comp (ref "A269")
      (value "JP1E")
      (footprint "eagle-import:JP1")
      (libsource (lib "eagle-import") (part "JP1E"))
    )
    (comp (ref "A270")
      (value "JP1E")
      (footprint "eagle-import:JP1")
      (libsource (lib "eagle-import") (part "JP1E"))
    )
    (comp (ref "A271")
      (value "JP1E")
      (footprint "eagle-import:JP1")
      (libsource (lib "eagle-import") (part "JP1E"))
    )
    (comp (ref "A272")
      (value "JP1E")
      (footprint "eagle-import:JP1")
      (libsource (lib "eagle-import") (part "JP1E"))
    )
    (comp (ref "A273")
      (value "JP1E")
      (footprint "eagle-import:JP1")
      (libsource (lib "eagle-import") (part "JP1E"))
    )
    (comp (ref "A274")
      (value "JP1E")
      (footprint "eagle-import:JP1")
      (libsource (lib "eagle-import") (part "JP1E"))
    )
    (comp (ref "A275")
      (value "JP1E")
      (footprint "eagle-import:JP1")
      (libsource (lib "eagle-import") (part "JP1E"))
    )
    (comp (ref "A276")
      (value "JP1E")
      (footprint "eagle-import:JP1")
      (libsource (lib "eagle-import") (part "JP1E"))
    )
    (comp (ref "A277")
      (value "JP1E")
      (footprint "eagle-import:JP1")
      (libsource (lib "eagle-import") (part "JP1E"))
    )
    (comp (ref "A278")
      (value "JP1E")
      (footprint "eagle-import:JP1")
      (libsource (lib "eagle-import") (part "JP1E"))
    )
    (comp (ref "A279")
      (value "JP1E")
      (footprint "eagle-import:JP1")
      (libsource (lib "eagle-import") (part "JP1E"))
    )
    (comp (ref "A280")
      (value "JP1E")
      (footprint "eagle-import:JP1")
      (libsource (lib "eagle-import") (part "JP1E"))
    )
    (comp (ref "A281")
      (value "JP1E")
      (footprint "eagle-import:JP1")
      (libsource (lib "eagle-import") (part "JP1E"))
    )
    (comp (ref "A282")
      (value "JP1E")
      (footprint "eagle-import:JP1")
      (libsource (lib "eagle-import") (part "JP1E"))
    )
    (comp (ref "A283")
      (value "JP1E")
      (footprint "eagle-import:JP1")
      (libsource (lib "eagle-import") (part "JP1E"))
    )
    (comp (ref "A284")
      (value "JP1E")
      (footprint "eagle-import:JP1")
      (libsource (lib "eagle-import") (part "JP1E"))
    )
    (comp (ref "A285")
      (value "JP1E")
      (footprint "eagle-import:JP1")
      (libsource (lib "eagle-import") (part "JP1E"))
    )
    (comp (ref "A286")
      (value "JP1E")
      (footprint "eagle-import:JP1")
      (libsource (lib "eagle-import") (part "JP1E"))
    )
    (comp (ref "A287")
      (value "JP1E")
      (footprint "eagle-import:JP1")
      (libsource (lib "eagle-import") (part "JP1E"))
    )
    (comp (ref "A288")
      (value "JP1E")
      (footprint "eagle-import:JP1")
      (libsource (lib "eagle-import") (part "JP1E"))
    )
    (comp (ref "A289")
      (value "JP1E")
      (footprint "eagle-import:JP1")
      (libsource (lib "eagle-import") (part "JP1E"))
    )
    (comp (ref "A290")
      (value "JP1E")
      (footprint "eagle-import:JP1")
      (libsource (lib "eagle-import") (part "JP1E"))
    )
    (comp (ref "A291")
      (value "JP1E")
      (footprint "eagle-import:JP1")
      (libsource (lib "eagle-import") (part "JP1E"))
    )
    (comp (ref "A292")
      (value "JP1E")
      (footprint "eagle-import:JP1")
      (libsource (lib "eagle-import") (part "JP1E"))
    )
    (comp (ref "A293")
      (value "JP1E")
      (footprint "eagle-import:JP1")
      (libsource (lib "eagle-import") (part "JP1E"))
    )
    (comp (ref "A294")
      (value "JP1E")
      (footprint "eagle-import:JP1")
      (libsource (lib "eagle-import") (part "JP1E"))
    )
    (comp (ref "A295")
      (value "JP1E")
      (footprint "eagle-import:JP1")
      (libsource (lib "eagle-import") (part "JP1E"))
    )
    (comp (ref "A296")
      (value "JP1E")
      (footprint "eagle-import:JP1")
      (libsource (lib "eagle-import") (part "JP1E"))
    )
    (comp (ref "A297")
      (value "JP1E")
      (footprint "eagle-import:JP1")
      (libsource (lib "eagle-import") (part "JP1E"))
    )
    (comp (ref "A298")
      (value "JP1E")
      (footprint "eagle-import:JP1")
      (libsource (lib "eagle-import") (part "JP1E"))
    )
    (comp (ref "A299")
      (value "JP1E")
      (footprint "eagle-import:JP1")
      (libsource (lib "eagle-import") (part "JP1E"))
    )
    (comp (ref "A300")
      (value "JP1E")
      (footprint "eagle-import:JP1")
      (libsource (lib "eagle-import") (part "JP1E"))
    )
    (comp (ref "A301")
      (value "JP1E")
      (footprint "eagle-import:JP1")
      (libsource (lib "eagle-import") (part "JP1E"))
    )
    (comp (ref "A302")
      (value "JP1E")
      (footprint "eagle-import:JP1")
      (libsource (lib "eagle-import") (part "JP1E"))
    )
    (comp (ref "A303")
      (value "JP1E")
      (footprint "eagle-import:JP1")
      (libsource (lib "eagle-import") (part "JP1E"))
    )
    (comp (ref "A304")
      (value "JP1E")
      (footprint "eagle-import:JP1")
      (libsource (lib "eagle-import") (part "JP1E"))
    )
    (comp (ref "A305")
      (value "JP1E")
      (footprint "eagle-import:JP1")
      (libsource (lib "eagle-import") (part "JP1E"))
    )
    (comp (ref "A306")
      (value "JP1E")
      (footprint "eagle-import:JP1")
      (libsource (lib "eagle-import") (part "JP1E"))
    )
    (comp (ref "A307")
      (value "JP1E")
      (footprint "eagle-import:JP1")
      (libsource (lib "eagle-import") (part "JP1E"))
    )
    (comp (ref "A308")
      (value "JP1E")
      (footprint "eagle-import:JP1")
      (libsource (lib "eagle-import") (part "JP1E"))
    )
    (comp (ref "A309")
      (value "JP1E")
      (footprint "eagle-import:JP1")
      (libsource (lib "eagle-import") (part "JP1E"))
    )
    (comp (ref "A310")
      (value "JP1E")
      (footprint "eagle-import:JP1")
      (libsource (lib "eagle-import") (part "JP1E"))
    )
    (comp (ref "A311")
      (value "JP1E")
      (footprint "eagle-import:JP1")
      (libsource (lib "eagle-import") (part "JP1E"))
    )
    (comp (ref "A312")
      (value "JP1E")
      (footprint "eagle-import:JP1")
      (libsource (lib "eagle-import") (part "JP1E"))
    )
    (comp (ref "A313")
      (value "JP1E")
      (footprint "eagle-import:JP1")
      (libsource (lib "eagle-import") (part "JP1E"))
    )
    (comp (ref "A314")
      (value "JP1E")
      (footprint "eagle-import:JP1")
      (libsource (lib "eagle-import") (part "JP1E"))
    )
    (comp (ref "A315")
      (value "JP1E")
      (footprint "eagle-import:JP1")
      (libsource (lib "eagle-import") (part "JP1E"))
    )
    (comp (ref "A316")
      (value "JP1E")
      (footprint "eagle-import:JP1")
      (libsource (lib "eagle-import") (part "JP1E"))
    )
    (comp (ref "A317")
      (value "JP1E")
      (footprint "eagle-import:JP1")
      (libsource (lib "eagle-import") (part "JP1E"))
    )
    (comp (ref "A318")
      (value "JP1E")
      (footprint "eagle-import:JP1")
      (libsource (lib "eagle-import") (part "JP1E"))
    )
    (comp (ref "A319")
      (value "JP1E")
      (footprint "eagle-import:JP1")
      (libsource (lib "eagle-import") (part "JP1E"))
    )
    (comp (ref "A320")
      (value "JP1E")
      (footprint "eagle-import:JP1")
      (libsource (lib "eagle-import") (part "JP1E"))
    )
    (comp (ref "A321")
      (value "JP1E")
      (footprint "eagle-import:JP1")
      (libsource (lib "eagle-import") (part "JP1E"))
    )
    (comp (ref "A322")
      (value "JP1E")
      (footprint "eagle-import:JP1")
      (libsource (lib "eagle-import") (part "JP1E"))
    )
    (comp (ref "A323")
      (value "JP1E")
      (footprint "eagle-import:JP1")
      (libsource (lib "eagle-import") (part "JP1E"))
    )
    (comp (ref "A324")
      (value "JP1E")
      (footprint "eagle-import:JP1")
      (libsource (lib "eagle-import") (part "JP1E"))
    )
    (comp (ref "A325")
      (value "JP1E")
      (footprint "eagle-import:JP1")
      (libsource (lib "eagle-import") (part "JP1E"))
    )
    (comp (ref "A326")
      (value "JP1E")
      (footprint "eagle-import:JP1")
      (libsource (lib "eagle-import") (part "JP1E"))
    )
    (comp (ref "A327")
      (value "JP1E")
      (footprint "eagle-import:JP1")
      (libsource (lib "eagle-import") (part "JP1E"))
    )
    (comp (ref "A328")
      (value "JP1E")
      (footprint "eagle-import:JP1")
      (libsource (lib "eagle-import") (part "JP1E"))
    )
    (comp (ref "A329")
      (value "JP1E")
      (footprint "eagle-import:JP1")
      (libsource (lib "eagle-import") (part "JP1E"))
    )
    (comp (ref "A330")
      (value "JP1E")
      (footprint "eagle-import:JP1")
      (libsource (lib "eagle-import") (part "JP1E"))
    )
    (comp (ref "A331")
      (value "JP1E")
      (footprint "eagle-import:JP1")
      (libsource (lib "eagle-import") (part "JP1E"))
    )
    (comp (ref "A332")
      (value "JP1E")
      (footprint "eagle-import:JP1")
      (libsource (lib "eagle-import") (part "JP1E"))
    )
    (comp (ref "A333")
      (value "JP1E")
      (footprint "eagle-import:JP1")
      (libsource (lib "eagle-import") (part "JP1E"))
    )
    (comp (ref "A334")
      (value "JP1E")
      (footprint "eagle-import:JP1")
      (libsource (lib "eagle-import") (part "JP1E"))
    )
    (comp (ref "A335")
      (value "JP1E")
      (footprint "eagle-import:JP1")
      (libsource (lib "eagle-import") (part "JP1E"))
    )
    (comp (ref "A336")
      (value "JP1E")
      (footprint "eagle-import:JP1")
      (libsource (lib "eagle-import") (part "JP1E"))
    )
    (comp (ref "A337")
      (value "JP1E")
      (footprint "eagle-import:JP1")
      (libsource (lib "eagle-import") (part "JP1E"))
    )
    (comp (ref "A338")
      (value "JP1E")
      (footprint "eagle-import:JP1")
      (libsource (lib "eagle-import") (part "JP1E"))
    )
    (comp (ref "A339")
      (value "JP1E")
      (footprint "eagle-import:JP1")
      (libsource (lib "eagle-import") (part "JP1E"))
    )
    (comp (ref "A340")
      (value "JP1E")
      (footprint "eagle-import:JP1")
      (libsource (lib "eagle-import") (part "JP1E"))
    )
    (comp (ref "A341")
      (value "JP1E")
      (footprint "eagle-import:JP1")
      (libsource (lib "eagle-import") (part "JP1E"))
    )
    (comp (ref "A342")
      (value "JP1E")
      (footprint "eagle-import:JP1")
      (libsource (lib "eagle-import") (part "JP1E"))
    )
    (comp (ref "A343")
      (value "JP1E")
      (footprint "eagle-import:JP1")
      (libsource (lib "eagle-import") (part "JP1E"))
    )
    (comp (ref "A344")
      (value "JP1E")
      (footprint "eagle-import:JP1")
      (libsource (lib "eagle-import") (part "JP1E"))
    )
    (comp (ref "A345")
      (value "JP1E")
      (footprint "eagle-import:JP1")
      (libsource (lib "eagle-import") (part "JP1E"))
    )
    (comp (ref "A346")
      (value "JP1E")
      (footprint "eagle-import:JP1")
      (libsource (lib "eagle-import") (part "JP1E"))
    )
    (comp (ref "A347")
      (value "JP1E")
      (footprint "eagle-import:JP1")
      (libsource (lib "eagle-import") (part "JP1E"))
    )
    (comp (ref "A348")
      (value "JP1E")
      (footprint "eagle-import:JP1")
      (libsource (lib "eagle-import") (part "JP1E"))
    )
    (comp (ref "A349")
      (value "JP1E")
      (footprint "eagle-import:JP1")
      (libsource (lib "eagle-import") (part "JP1E"))
    )
    (comp (ref "A350")
      (value "JP1E")
      (footprint "eagle-import:JP1")
      (libsource (lib "eagle-import") (part "JP1E"))
    )
    (comp (ref "A351")
      (value "JP1E")
      (footprint "eagle-import:JP1")
      (libsource (lib "eagle-import") (part "JP1E"))
    )
    (comp (ref "A352")
      (value "JP1E")
      (footprint "eagle-import:JP1")
      (libsource (lib "eagle-import") (part "JP1E"))
    )
    (comp (ref "A353")
      (value "JP1E")
      (footprint "eagle-import:JP1")
      (libsource (lib "eagle-import") (part "JP1E"))
    )
    (comp (ref "A354")
      (value "JP1E")
      (footprint "eagle-import:JP1")
      (libsource (lib "eagle-import") (part "JP1E"))
    )
    (comp (ref "A355")
      (value "JP1E")
      (footprint "eagle-import:JP1")
      (libsource (lib "eagle-import") (part "JP1E"))
    )
    (comp (ref "A356")
      (value "JP1E")
      (footprint "eagle-import:JP1")
      (libsource (lib "eagle-import") (part "JP1E"))
    )
    (comp (ref "A357")
      (value "JP1E")
      (footprint "eagle-import:JP1")
      (libsource (lib "eagle-import") (part "JP1E"))
    )
    (comp (ref "A358")
      (value "JP1E")
      (footprint "eagle-import:JP1")
      (libsource (lib "eagle-import") (part "JP1E"))
    )
    (comp (ref "A359")
      (value "JP1E")
      (footprint "eagle-import:JP1")
      (libsource (lib "eagle-import") (part "JP1E"))
    )
    (comp (ref "A360")
      (value "JP1E")
      (footprint "eagle-import:JP1")
      (libsource (lib "eagle-import") (part "JP1E"))
    )
    (comp (ref "A361")
      (value "JP1E")
      (footprint "eagle-import:JP1")
      (libsource (lib "eagle-import") (part "JP1E"))
    )
    (comp (ref "A362")
      (value "JP1E")
      (footprint "eagle-import:JP1")
      (libsource (lib "eagle-import") (part "JP1E"))
    )
    (comp (ref "A363")
      (value "JP1E")
      (footprint "eagle-import:JP1")
      (libsource (lib "eagle-import") (part "JP1E"))
    )
    (comp (ref "A364")
      (value "JP1E")
      (footprint "eagle-import:JP1")
      (libsource (lib "eagle-import") (part "JP1E"))
    )
    (comp (ref "A365")
      (value "JP1E")
      (footprint "eagle-import:JP1")
      (libsource (lib "eagle-import") (part "JP1E"))
    )
    (comp (ref "A366")
      (value "JP1E")
      (footprint "eagle-import:JP1")
      (libsource (lib "eagle-import") (part "JP1E"))
    )
    (comp (ref "A367")
      (value "JP1E")
      (footprint "eagle-import:JP1")
      (libsource (lib "eagle-import") (part "JP1E"))
    )
    (comp (ref "A368")
      (value "JP1E")
      (footprint "eagle-import:JP1")
      (libsource (lib "eagle-import") (part "JP1E"))
    )
    (comp (ref "A369")
      (value "JP1E")
      (footprint "eagle-import:JP1")
      (libsource (lib "eagle-import") (part "JP1E"))
    )
    (comp (ref "A370")
      (value "JP1E")
      (footprint "eagle-import:JP1")
      (libsource (lib "eagle-import") (part "JP1E"))
    )
    (comp (ref "A371")
      (value "JP1E")
      (footprint "eagle-import:JP1")
      (libsource (lib "eagle-import") (part "JP1E"))
    )
    (comp (ref "A372")
      (value "JP1E")
      (footprint "eagle-import:JP1")
      (libsource (lib "eagle-import") (part "JP1E"))
    )
    (comp (ref "A373")
      (value "JP1E")
      (footprint "eagle-import:JP1")
      (libsource (lib "eagle-import") (part "JP1E"))
    )
    (comp (ref "A374")
      (value "JP1E")
      (footprint "eagle-import:JP1")
      (libsource (lib "eagle-import") (part "JP1E"))
    )
    (comp (ref "A375")
      (value "JP1E")
      (footprint "eagle-import:JP1")
      (libsource (lib "eagle-import") (part "JP1E"))
    )
    (comp (ref "A376")
      (value "JP1E")
      (footprint "eagle-import:JP1")
      (libsource (lib "eagle-import") (part "JP1E"))
    )
    (comp (ref "A377")
      (value "JP1E")
      (footprint "eagle-import:JP1")
      (libsource (lib "eagle-import") (part "JP1E"))
    )
    (comp (ref "A378")
      (value "JP1E")
      (footprint "eagle-import:JP1")
      (libsource (lib "eagle-import") (part "JP1E"))
    )
    (comp (ref "A379")
      (value "JP1E")
      (footprint "eagle-import:JP1")
      (libsource (lib "eagle-import") (part "JP1E"))
    )
    (comp (ref "A380")
      (value "JP1E")
      (footprint "eagle-import:JP1")
      (libsource (lib "eagle-import") (part "JP1E"))
    )
    (comp (ref "A381")
      (value "JP1E")
      (footprint "eagle-import:JP1")
      (libsource (lib "eagle-import") (part "JP1E"))
    )
    (comp (ref "A382")
      (value "JP1E")
      (footprint "eagle-import:JP1")
      (libsource (lib "eagle-import") (part "JP1E"))
    )
    (comp (ref "A383")
      (value "JP1E")
      (footprint "eagle-import:JP1")
      (libsource (lib "eagle-import") (part "JP1E"))
    )
    (comp (ref "A384")
      (value "JP1E")
      (footprint "eagle-import:JP1")
      (libsource (lib "eagle-import") (part "JP1E"))
    )
    (comp (ref "A385")
      (value "JP1E")
      (footprint "eagle-import:JP1")
      (libsource (lib "eagle-import") (part "JP1E"))
    )
    (comp (ref "A386")
      (value "JP1E")
      (footprint "eagle-import:JP1")
      (libsource (lib "eagle-import") (part "JP1E"))
    )
    (comp (ref "A387")
      (value "JP1E")
      (footprint "eagle-import:JP1")
      (libsource (lib "eagle-import") (part "JP1E"))
    )
    (comp (ref "A388")
      (value "JP1E")
      (footprint "eagle-import:JP1")
      (libsource (lib "eagle-import") (part "JP1E"))
    )
    (comp (ref "A389")
      (value "JP1E")
      (footprint "eagle-import:JP1")
      (libsource (lib "eagle-import") (part "JP1E"))
    )
    (comp (ref "A390")
      (value "JP1E")
      (footprint "eagle-import:JP1")
      (libsource (lib "eagle-import") (part "JP1E"))
    )
    (comp (ref "A391")
      (value "JP1E")
      (footprint "eagle-import:JP1")
      (libsource (lib "eagle-import") (part "JP1E"))
    )
    (comp (ref "A392")
      (value "JP1E")
      (footprint "eagle-import:JP1")
      (libsource (lib "eagle-import") (part "JP1E"))
    )
    (comp (ref "A393")
      (value "JP1E")
      (footprint "eagle-import:JP1")
      (libsource (lib "eagle-import") (part "JP1E"))
    )
    (comp (ref "A394")
      (value "JP1E")
      (footprint "eagle-import:JP1")
      (libsource (lib "eagle-import") (part "JP1E"))
    )
    (comp (ref "A395")
      (value "JP1E")
      (footprint "eagle-import:JP1")
      (libsource (lib "eagle-import") (part "JP1E"))
    )
    (comp (ref "A396")
      (value "JP1E")
      (footprint "eagle-import:JP1")
      (libsource (lib "eagle-import") (part "JP1E"))
    )
    (comp (ref "A397")
      (value "JP1E")
      (footprint "eagle-import:JP1")
      (libsource (lib "eagle-import") (part "JP1E"))
    )
    (comp (ref "A398")
      (value "JP1E")
      (footprint "eagle-import:JP1")
      (libsource (lib "eagle-import") (part "JP1E"))
    )
    (comp (ref "A399")
      (value "JP1E")
      (footprint "eagle-import:JP1")
      (libsource (lib "eagle-import") (part "JP1E"))
    )
    (comp (ref "A400")
      (value "JP1E")
      (footprint "eagle-import:JP1")
      (libsource (lib "eagle-import") (part "JP1E"))
    )
    (comp (ref "A401")
      (value "JP1E")
      (footprint "eagle-import:JP1")
      (libsource (lib "eagle-import") (part "JP1E"))
    )
    (comp (ref "A402")
      (value "JP1E")
      (footprint "eagle-import:JP1")
      (libsource (lib "eagle-import") (part "JP1E"))
    )
    (comp (ref "A403")
      (value "JP1E")
      (footprint "eagle-import:JP1")
      (libsource (lib "eagle-import") (part "JP1E"))
    )
    (comp (ref "A404")
      (value "JP1E")
      (footprint "eagle-import:JP1")
      (libsource (lib "eagle-import") (part "JP1E"))
    )
    (comp (ref "A405")
      (value "JP1E")
      (footprint "eagle-import:JP1")
      (libsource (lib "eagle-import") (part "JP1E"))
    )
    (comp (ref "A406")
      (value "JP1E")
      (footprint "eagle-import:JP1")
      (libsource (lib "eagle-import") (part "JP1E"))
    )
    (comp (ref "A407")
      (value "JP1E")
      (footprint "eagle-import:JP1")
      (libsource (lib "eagle-import") (part "JP1E"))
    )
    (comp (ref "A408")
      (value "JP1E")
      (footprint "eagle-import:JP1")
      (libsource (lib "eagle-import") (part "JP1E"))
    )
    (comp (ref "A409")
      (value "JP1E")
      (footprint "eagle-import:JP1")
      (libsource (lib "eagle-import") (part "JP1E"))
    )
    (comp (ref "A410")
      (value "JP1E")
      (footprint "eagle-import:JP1")
      (libsource (lib "eagle-import") (part "JP1E"))
    )
    (comp (ref "A411")
      (value "JP1E")
      (footprint "eagle-import:JP1")
      (libsource (lib "eagle-import") (part "JP1E"))
    )
    (comp (ref "A412")
      (value "JP1E")
      (footprint "eagle-import:JP1")
      (libsource (lib "eagle-import") (part "JP1E"))
    )
    (comp (ref "A413")
      (value "JP1E")
      (footprint "eagle-import:JP1")
      (libsource (lib "eagle-import") (part "JP1E"))
    )
    (comp (ref "A414")
      (value "JP1E")
      (footprint "eagle-import:JP1")
      (libsource (lib "eagle-import") (part "JP1E"))
    )
    (comp (ref "A415")
      (value "JP1E")
      (footprint "eagle-import:JP1")
      (libsource (lib "eagle-import") (part "JP1E"))
    )
    (comp (ref "A416")
      (value "JP1E")
      (footprint "eagle-import:JP1")
      (libsource (lib "eagle-import") (part "JP1E"))
    )
    (comp (ref "A417")
      (value "JP1E")
      (footprint "eagle-import:JP1")
      (libsource (lib "eagle-import") (part "JP1E"))
    )
    (comp (ref "A418")
      (value "JP1E")
      (footprint "eagle-import:JP1")
      (libsource (lib "eagle-import") (part "JP1E"))
    )
    (comp (ref "A419")
      (value "JP1E")
      (footprint "eagle-import:JP1")
      (libsource (lib "eagle-import") (part "JP1E"))
    )
    (comp (ref "A420")
      (value "JP1E")
      (footprint "eagle-import:JP1")
      (libsource (lib "eagle-import") (part "JP1E"))
    )
    (comp (ref "A421")
      (value "JP1E")
      (footprint "eagle-import:JP1")
      (libsource (lib "eagle-import") (part "JP1E"))
    )
    (comp (ref "A422")
      (value "JP1E")
      (footprint "eagle-import:JP1")
      (libsource (lib "eagle-import") (part "JP1E"))
    )
    (comp (ref "A423")
      (value "JP1E")
      (footprint "eagle-import:JP1")
      (libsource (lib "eagle-import") (part "JP1E"))
    )
    (comp (ref "A424")
      (value "JP1E")
      (footprint "eagle-import:JP1")
      (libsource (lib "eagle-import") (part "JP1E"))
    )
    (comp (ref "A425")
      (value "JP1E")
      (footprint "eagle-import:JP1")
      (libsource (lib "eagle-import") (part "JP1E"))
    )
    (comp (ref "A426")
      (value "JP1E")
      (footprint "eagle-import:JP1")
      (libsource (lib "eagle-import") (part "JP1E"))
    )
    (comp (ref "A427")
      (value "JP1E")
      (footprint "eagle-import:JP1")
      (libsource (lib "eagle-import") (part "JP1E"))
    )
    (comp (ref "A428")
      (value "JP1E")
      (footprint "eagle-import:JP1")
      (libsource (lib "eagle-import") (part "JP1E"))
    )
    (comp (ref "A429")
      (value "JP1E")
      (footprint "eagle-import:JP1")
      (libsource (lib "eagle-import") (part "JP1E"))
    )
    (comp (ref "A430")
      (value "JP1E")
      (footprint "eagle-import:JP1")
      (libsource (lib "eagle-import") (part "JP1E"))
    )
    (comp (ref "A431")
      (value "JP1E")
      (footprint "eagle-import:JP1")
      (libsource (lib "eagle-import") (part "JP1E"))
    )
    (comp (ref "A432")
      (value "JP1E")
      (footprint "eagle-import:JP1")
      (libsource (lib "eagle-import") (part "JP1E"))
    )
    (comp (ref "A433")
      (value "JP1E")
      (footprint "eagle-import:JP1")
      (libsource (lib "eagle-import") (part "JP1E"))
    )
    (comp (ref "A434")
      (value "JP1E")
      (footprint "eagle-import:JP1")
      (libsource (lib "eagle-import") (part "JP1E"))
    )
    (comp (ref "A435")
      (value "JP1E")
      (footprint "eagle-import:JP1")
      (libsource (lib "eagle-import") (part "JP1E"))
    )
    (comp (ref "A436")
      (value "JP1E")
      (footprint "eagle-import:JP1")
      (libsource (lib "eagle-import") (part "JP1E"))
    )
    (comp (ref "A437")
      (value "JP1E")
      (footprint "eagle-import:JP1")
      (libsource (lib "eagle-import") (part "JP1E"))
    )
    (comp (ref "A438")
      (value "JP1E")
      (footprint "eagle-import:JP1")
      (libsource (lib "eagle-import") (part "JP1E"))
    )
    (comp (ref "A439")
      (value "JP1E")
      (footprint "eagle-import:JP1")
      (libsource (lib "eagle-import") (part "JP1E"))
    )
    (comp (ref "A440")
      (value "JP1E")
      (footprint "eagle-import:JP1")
      (libsource (lib "eagle-import") (part "JP1E"))
    )
    (comp (ref "A441")
      (value "JP1E")
      (footprint "eagle-import:JP1")
      (libsource (lib "eagle-import") (part "JP1E"))
    )
    (comp (ref "A442")
      (value "JP1E")
      (footprint "eagle-import:JP1")
      (libsource (lib "eagle-import") (part "JP1E"))
    )
    (comp (ref "A443")
      (value "JP1E")
      (footprint "eagle-import:JP1")
      (libsource (lib "eagle-import") (part "JP1E"))
    )
    (comp (ref "A444")
      (value "JP1E")
      (footprint "eagle-import:JP1")
      (libsource (lib "eagle-import") (part "JP1E"))
    )
    (comp (ref "A445")
      (value "JP1E")
      (footprint "eagle-import:JP1")
      (libsource (lib "eagle-import") (part "JP1E"))
    )
    (comp (ref "A446")
      (value "JP1E")
      (footprint "eagle-import:JP1")
      (libsource (lib "eagle-import") (part "JP1E"))
    )
    (comp (ref "A447")
      (value "JP1E")
      (footprint "eagle-import:JP1")
      (libsource (lib "eagle-import") (part "JP1E"))
    )
    (comp (ref "A448")
      (value "JP1E")
      (footprint "eagle-import:JP1")
      (libsource (lib "eagle-import") (part "JP1E"))
    )
    (comp (ref "GND1")
      (value "JP1E")
      (footprint "eagle-import:JP1")
      (libsource (lib "eagle-import") (part "JP1E"))
    )
    (comp (ref "GND2")
      (value "JP1E")
      (footprint "eagle-import:JP1")
      (libsource (lib "eagle-import") (part "JP1E"))
    )
    (comp (ref "GND3")
      (value "JP1E")
      (footprint "eagle-import:JP1")
      (libsource (lib "eagle-import") (part "JP1E"))
    )
    (comp (ref "GND4")
      (value "JP1E")
      (footprint "eagle-import:JP1")
      (libsource (lib "eagle-import") (part "JP1E"))
    )
    (comp (ref "GND5")
      (value "JP1E")
      (footprint "eagle-import:JP1")
      (libsource (lib "eagle-import") (part "JP1E"))
    )
    (comp (ref "GND6")
      (value "JP1E")
      (footprint "eagle-import:JP1")
      (libsource (lib "eagle-import") (part "JP1E"))
    )
    (comp (ref "GND7")
      (value "JP1E")
      (footprint "eagle-import:JP1")
      (libsource (lib "eagle-import") (part "JP1E"))
    )
    (comp (ref "GND8")
      (value "JP1E")
      (footprint "eagle-import:JP1")
      (libsource (lib "eagle-import") (part "JP1E"))
    )
    (comp (ref "GND9")
      (value "JP1E")
      (footprint "eagle-import:JP1")
      (libsource (lib "eagle-import") (part "JP1E"))
    )
    (comp (ref "GND10")
      (value "JP1E")
      (footprint "eagle-import:JP1")
      (libsource (lib "eagle-import") (part "JP1E"))
    )
    (comp (ref "GND11")
      (value "JP1E")
      (footprint "eagle-import:JP1")
      (libsource (lib "eagle-import") (part "JP1E"))
    )
    (comp (ref "GND12")
      (value "JP1E")
      (footprint "eagle-import:JP1")
      (libsource (lib "eagle-import") (part "JP1E"))
    )
    (comp (ref "GND13")
      (value "JP1E")
      (footprint "eagle-import:JP1")
      (libsource (lib "eagle-import") (part "JP1E"))
    )
    (comp (ref "GND14")
      (value "JP1E")
      (footprint "eagle-import:JP1")
      (libsource (lib "eagle-import") (part "JP1E"))
    )
    (comp (ref "GND15")
      (value "JP1E")
      (footprint "eagle-import:JP1")
      (libsource (lib "eagle-import") (part "JP1E"))
    )
    (comp (ref "GND16")
      (value "JP1E")
      (footprint "eagle-import:JP1")
      (libsource (lib "eagle-import") (part "JP1E"))
    )
    (comp (ref "GND17")
      (value "JP1E")
      (footprint "eagle-import:JP1")
      (libsource (lib "eagle-import") (part "JP1E"))
    )
    (comp (ref "GND18")
      (value "JP1E")
      (footprint "eagle-import:JP1")
      (libsource (lib "eagle-import") (part "JP1E"))
    )
    (comp (ref "GND19")
      (value "JP1E")
      (footprint "eagle-import:JP1")
      (libsource (lib "eagle-import") (part "JP1E"))
    )
    (comp (ref "GND20")
      (value "JP1E")
      (footprint "eagle-import:JP1")
      (libsource (lib "eagle-import") (part "JP1E"))
    )
    (comp (ref "GND21")
      (value "JP1E")
      (footprint "eagle-import:JP1")
      (libsource (lib "eagle-import") (part "JP1E"))
    )
    (comp (ref "GND22")
      (value "JP1E")
      (footprint "eagle-import:JP1")
      (libsource (lib "eagle-import") (part "JP1E"))
    )
    (comp (ref "GND23")
      (value "JP1E")
      (footprint "eagle-import:JP1")
      (libsource (lib "eagle-import") (part "JP1E"))
    )
    (comp (ref "GND24")
      (value "JP1E")
      (footprint "eagle-import:JP1")
      (libsource (lib "eagle-import") (part "JP1E"))
    )
    (comp (ref "GND25")
      (value "JP1E")
      (footprint "eagle-import:JP1")
      (libsource (lib "eagle-import") (part "JP1E"))
    )
    (comp (ref "GND26")
      (value "JP1E")
      (footprint "eagle-import:JP1")
      (libsource (lib "eagle-import") (part "JP1E"))
    )
    (comp (ref "GND27")
      (value "JP1E")
      (footprint "eagle-import:JP1")
      (libsource (lib "eagle-import") (part "JP1E"))
    )
    (comp (ref "GND28")
      (value "JP1E")
      (footprint "eagle-import:JP1")
      (libsource (lib "eagle-import") (part "JP1E"))
    )
    (comp (ref "GND29")
      (value "JP1E")
      (footprint "eagle-import:JP1")
      (libsource (lib "eagle-import") (part "JP1E"))
    )
    (comp (ref "GND30")
      (value "JP1E")
      (footprint "eagle-import:JP1")
      (libsource (lib "eagle-import") (part "JP1E"))
    )
    (comp (ref "GND31")
      (value "JP1E")
      (footprint "eagle-import:JP1")
      (libsource (lib "eagle-import") (part "JP1E"))
    )
    (comp (ref "GND32")
      (value "JP1E")
      (footprint "eagle-import:JP1")
      (libsource (lib "eagle-import") (part "JP1E"))
    )
    (comp (ref "GND33")
      (value "JP1E")
      (footprint "eagle-import:JP1")
      (libsource (lib "eagle-import") (part "JP1E"))
    )
    (comp (ref "GND34")
      (value "JP1E")
      (footprint "eagle-import:JP1")
      (libsource (lib "eagle-import") (part "JP1E"))
    )
    (comp (ref "GND35")
      (value "JP1E")
      (footprint "eagle-import:JP1")
      (libsource (lib "eagle-import") (part "JP1E"))
    )
    (comp (ref "GND36")
      (value "JP1E")
      (footprint "eagle-import:JP1")
      (libsource (lib "eagle-import") (part "JP1E"))
    )
    (comp (ref "GND37")
      (value "JP1E")
      (footprint "eagle-import:JP1")
      (libsource (lib "eagle-import") (part "JP1E"))
    )
    (comp (ref "GND38")
      (value "JP1E")
      (footprint "eagle-import:JP1")
      (libsource (lib "eagle-import") (part "JP1E"))
    )
    (comp (ref "GND39")
      (value "JP1E")
      (footprint "eagle-import:JP1")
      (libsource (lib "eagle-import") (part "JP1E"))
    )
    (comp (ref "GND40")
      (value "JP1E")
      (footprint "eagle-import:JP1")
      (libsource (lib "eagle-import") (part "JP1E"))
    )
    (comp (ref "GND41")
      (value "JP1E")
      (footprint "eagle-import:JP1")
      (libsource (lib "eagle-import") (part "JP1E"))
    )
    (comp (ref "GND42")
      (value "JP1E")
      (footprint "eagle-import:JP1")
      (libsource (lib "eagle-import") (part "JP1E"))
    )
    (comp (ref "GND43")
      (value "JP1E")
      (footprint "eagle-import:JP1")
      (libsource (lib "eagle-import") (part "JP1E"))
    )
    (comp (ref "GND44")
      (value "JP1E")
      (footprint "eagle-import:JP1")
      (libsource (lib "eagle-import") (part "JP1E"))
    )
    (comp (ref "IC9")
      (value "DIL16")
      (footprint "eagle-import:DIL16")
      (libsource (lib "eagle-import") (part "DIL16"))
    )
    (comp (ref "IC10")
      (value "DIL16")
      (footprint "eagle-import:DIL16")
      (libsource (lib "eagle-import") (part "DIL16"))
    )
    (comp (ref "IC11")
      (value "DIL16")
      (footprint "eagle-import:DIL16")
      (libsource (lib "eagle-import") (part "DIL16"))
    )
    (comp (ref "IC12")
      (value "DIL16")
      (footprint "eagle-import:DIL16")
      (libsource (lib "eagle-import") (part "DIL16"))
    )
    (comp (ref "IC13")
      (value "DIL16")
      (footprint "eagle-import:DIL16")
      (libsource (lib "eagle-import") (part "DIL16"))
    )
    (comp (ref "IC14")
      (value "DIL16")
      (footprint "eagle-import:DIL16")
      (libsource (lib "eagle-import") (part "DIL16"))
    )
    (comp (ref "IC15")
      (value "DIL16")
      (footprint "eagle-import:DIL16")
      (libsource (lib "eagle-import") (part "DIL16"))
    )
    (comp (ref "IC16")
      (value "DIL16")
      (footprint "eagle-import:DIL16")
      (libsource (lib "eagle-import") (part "DIL16"))
    )
    (comp (ref "IC17")
      (value "DIL16")
      (footprint "eagle-import:DIL16")
      (libsource (lib "eagle-import") (part "DIL16"))
    )
    (comp (ref "IC18")
      (value "DIL16")
      (footprint "eagle-import:DIL16")
      (libsource (lib "eagle-import") (part "DIL16"))
    )
    (comp (ref "IC19")
      (value "DIL16")
      (footprint "eagle-import:DIL16")
      (libsource (lib "eagle-import") (part "DIL16"))
    )
    (comp (ref "IC20")
      (value "DIL16")
      (footprint "eagle-import:DIL16")
      (libsource (lib "eagle-import") (part "DIL16"))
    )
    (comp (ref "IC21")
      (value "DIL16")
      (footprint "eagle-import:DIL16")
      (libsource (lib "eagle-import") (part "DIL16"))
    )
    (comp (ref "IC22")
      (value "DIL16")
      (footprint "eagle-import:DIL16")
      (libsource (lib "eagle-import") (part "DIL16"))
    )
    (comp (ref "IC23")
      (value "DIL16")
      (footprint "eagle-import:DIL16")
      (libsource (lib "eagle-import") (part "DIL16"))
    )
    (comp (ref "IC24")
      (value "DIL16")
      (footprint "eagle-import:DIL16")
      (libsource (lib "eagle-import") (part "DIL16"))
    )
    (comp (ref "IC25")
      (value "DIL16")
      (footprint "eagle-import:DIL16")
      (libsource (lib "eagle-import") (part "DIL16"))
    )
    (comp (ref "IC26")
      (value "DIL16")
      (footprint "eagle-import:DIL16")
      (libsource (lib "eagle-import") (part "DIL16"))
    )
    (comp (ref "IC27")
      (value "DIL16")
      (footprint "eagle-import:DIL16")
      (libsource (lib "eagle-import") (part "DIL16"))
    )
    (comp (ref "IC28")
      (value "DIL16")
      (footprint "eagle-import:DIL16")
      (libsource (lib "eagle-import") (part "DIL16"))
    )
    (comp (ref "IC29")
      (value "DIL16")
      (footprint "eagle-import:DIL16")
      (libsource (lib "eagle-import") (part "DIL16"))
    )
    (comp (ref "IC30")
      (value "DIL16")
      (footprint "eagle-import:DIL16")
      (libsource (lib "eagle-import") (part "DIL16"))
    )
    (comp (ref "IC31")
      (value "DIL16")
      (footprint "eagle-import:DIL16")
      (libsource (lib "eagle-import") (part "DIL16"))
    )
    (comp (ref "IC32")
      (value "DIL16")
      (footprint "eagle-import:DIL16")
      (libsource (lib "eagle-import") (part "DIL16"))
    )
    (comp (ref "IC33")
      (value "DIL16")
      (footprint "eagle-import:DIL16")
      (libsource (lib "eagle-import") (part "DIL16"))
    )
    (comp (ref "IC34")
      (value "DIL16")
      (footprint "eagle-import:DIL16")
      (libsource (lib "eagle-import") (part "DIL16"))
    )
    (comp (ref "IC35")
      (value "DIL16")
      (footprint "eagle-import:DIL16")
      (libsource (lib "eagle-import") (part "DIL16"))
    )
    (comp (ref "IC36")
      (value "DIL16")
      (footprint "eagle-import:DIL16")
      (libsource (lib "eagle-import") (part "DIL16"))
    )
    (comp (ref "VCC1")
      (value "JP1E")
      (footprint "eagle-import:JP1")
      (libsource (lib "eagle-import") (part "JP1E"))
    )
    (comp (ref "VCC2")
      (value "JP1E")
      (footprint "eagle-import:JP1")
      (libsource (lib "eagle-import") (part "JP1E"))
    )
    (comp (ref "VCC3")
      (value "JP1E")
      (footprint "eagle-import:JP1")
      (libsource (lib "eagle-import") (part "JP1E"))
    )
    (comp (ref "VCC4")
      (value "JP1E")
      (footprint "eagle-import:JP1")
      (libsource (lib "eagle-import") (part "JP1E"))
    )
    (comp (ref "VCC5")
      (value "JP1E")
      (footprint "eagle-import:JP1")
      (libsource (lib "eagle-import") (part "JP1E"))
    )
    (comp (ref "VCC6")
      (value "JP1E")
      (footprint "eagle-import:JP1")
      (libsource (lib "eagle-import") (part "JP1E"))
    )
    (comp (ref "VCC7")
      (value "JP1E")
      (footprint "eagle-import:JP1")
      (libsource (lib "eagle-import") (part "JP1E"))
    )
    (comp (ref "VCC8")
      (value "JP1E")
      (footprint "eagle-import:JP1")
      (libsource (lib "eagle-import") (part "JP1E"))
    )
    (comp (ref "VCC9")
      (value "JP1E")
      (footprint "eagle-import:JP1")
      (libsource (lib "eagle-import") (part "JP1E"))
    )
    (comp (ref "VCC10")
      (value "JP1E")
      (footprint "eagle-import:JP1")
      (libsource (lib "eagle-import") (part "JP1E"))
    )
    (comp (ref "VCC11")
      (value "JP1E")
      (footprint "eagle-import:JP1")
      (libsource (lib "eagle-import") (part "JP1E"))
    )
    (comp (ref "VCC12")
      (value "JP1E")
      (footprint "eagle-import:JP1")
      (libsource (lib "eagle-import") (part "JP1E"))
    )
    (comp (ref "VCC13")
      (value "JP1E")
      (footprint "eagle-import:JP1")
      (libsource (lib "eagle-import") (part "JP1E"))
    )
    (comp (ref "VCC14")
      (value "JP1E")
      (footprint "eagle-import:JP1")
      (libsource (lib "eagle-import") (part "JP1E"))
    )
    (comp (ref "VCC15")
      (value "JP1E")
      (footprint "eagle-import:JP1")
      (libsource (lib "eagle-import") (part "JP1E"))
    )
    (comp (ref "VCC16")
      (value "JP1E")
      (footprint "eagle-import:JP1")
      (libsource (lib "eagle-import") (part "JP1E"))
    )
    (comp (ref "VCC17")
      (value "JP1E")
      (footprint "eagle-import:JP1")
      (libsource (lib "eagle-import") (part "JP1E"))
    )
    (comp (ref "VCC18")
      (value "JP1E")
      (footprint "eagle-import:JP1")
      (libsource (lib "eagle-import") (part "JP1E"))
    )
    (comp (ref "VCC19")
      (value "JP1E")
      (footprint "eagle-import:JP1")
      (libsource (lib "eagle-import") (part "JP1E"))
    )
    (comp (ref "VCC20")
      (value "JP1E")
      (footprint "eagle-import:JP1")
      (libsource (lib "eagle-import") (part "JP1E"))
    )
    (comp (ref "VCC21")
      (value "JP1E")
      (footprint "eagle-import:JP1")
      (libsource (lib "eagle-import") (part "JP1E"))
    )
    (comp (ref "VCC22")
      (value "JP1E")
      (footprint "eagle-import:JP1")
      (libsource (lib "eagle-import") (part "JP1E"))
    )
    (comp (ref "VCC23")
      (value "JP1E")
      (footprint "eagle-import:JP1")
      (libsource (lib "eagle-import") (part "JP1E"))
    )
    (comp (ref "VCC24")
      (value "JP1E")
      (footprint "eagle-import:JP1")
      (libsource (lib "eagle-import") (part "JP1E"))
    )
    (comp (ref "VCC25")
      (value "JP1E")
      (footprint "eagle-import:JP1")
      (libsource (lib "eagle-import") (part "JP1E"))
    )
    (comp (ref "VCC26")
      (value "JP1E")
      (footprint "eagle-import:JP1")
      (libsource (lib "eagle-import") (part "JP1E"))
    )
    (comp (ref "VCC27")
      (value "JP1E")
      (footprint "eagle-import:JP1")
      (libsource (lib "eagle-import") (part "JP1E"))
    )
    (comp (ref "VCC28")
      (value "JP1E")
      (footprint "eagle-import:JP1")
      (libsource (lib "eagle-import") (part "JP1E"))
    )
    (comp (ref "VCC29")
      (value "JP1E")
      (footprint "eagle-import:JP1")
      (libsource (lib "eagle-import") (part "JP1E"))
    )
    (comp (ref "VCC30")
      (value "JP1E")
      (footprint "eagle-import:JP1")
      (libsource (lib "eagle-import") (part "JP1E"))
    )
    (comp (ref "VCC31")
      (value "JP1E")
      (footprint "eagle-import:JP1")
      (libsource (lib "eagle-import") (part "JP1E"))
    )
    (comp (ref "VCC32")
      (value "JP1E")
      (footprint "eagle-import:JP1")
      (libsource (lib "eagle-import") (part "JP1E"))
    )
    (comp (ref "VCC33")
      (value "JP1E")
      (footprint "eagle-import:JP1")
      (libsource (lib "eagle-import") (part "JP1E"))
    )
    (comp (ref "VCC34")
      (value "JP1E")
      (footprint "eagle-import:JP1")
      (libsource (lib "eagle-import") (part "JP1E"))
    )
    (comp (ref "VCC35")
      (value "JP1E")
      (footprint "eagle-import:JP1")
      (libsource (lib "eagle-import") (part "JP1E"))
    )
    (comp (ref "VCC36")
      (value "JP1E")
      (footprint "eagle-import:JP1")
      (libsource (lib "eagle-import") (part "JP1E"))
    )
    (comp (ref "VCC37")
      (value "JP1E")
      (footprint "eagle-import:JP1")
      (libsource (lib "eagle-import") (part "JP1E"))
    )
    (comp (ref "VCC38")
      (value "JP1E")
      (footprint "eagle-import:JP1")
      (libsource (lib "eagle-import") (part "JP1E"))
    )
    (comp (ref "VCC39")
      (value "JP1E")
      (footprint "eagle-import:JP1")
      (libsource (lib "eagle-import") (part "JP1E"))
    )
    (comp (ref "VCC40")
      (value "JP1E")
      (footprint "eagle-import:JP1")
      (libsource (lib "eagle-import") (part "JP1E"))
    )
    (comp (ref "VCC41")
      (value "JP1E")
      (footprint "eagle-import:JP1")
      (libsource (lib "eagle-import") (part "JP1E"))
    )
    (comp (ref "VCC42")
      (value "JP1E")
      (footprint "eagle-import:JP1")
      (libsource (lib "eagle-import") (part "JP1E"))
    )
    (comp (ref "VCC43")
      (value "JP1E")
      (footprint "eagle-import:JP1")
      (libsource (lib "eagle-import") (part "JP1E"))
    )
    (comp (ref "VCC44")
      (value "JP1E")
      (footprint "eagle-import:JP1")
      (libsource (lib "eagle-import") (part "JP1E"))
    )
  )
  (nets
    (net (code "1") (name "+15V") (class "Default")
      (node (ref "D14") (pin "1") (pinfunction "1_1") (pintype "passive"))
      (node (ref "U$2") (pin "DA2") (pinfunction "1_DA2") (pintype "passive"))
    )
    (net (code "2") (name "-15V") (class "Default")
      (node (ref "D10") (pin "2") (pinfunction "2_2") (pintype "passive"))
      (node (ref "D12") (pin "2") (pinfunction "2_2") (pintype "passive"))
      (node (ref "D14") (pin "2") (pinfunction "2_2") (pintype "passive"))
      (node (ref "D8") (pin "2") (pinfunction "2_2") (pintype "passive"))
      (node (ref "U$2") (pin "AB2") (pinfunction "1_AB2") (pintype "passive"))
      (node (ref "U$2") (pin "BB2") (pinfunction "1_BB2") (pintype "passive"))
      (node (ref "U$2") (pin "CB2") (pinfunction "1_CB2") (pintype "passive"))
      (node (ref "U$2") (pin "DB2") (pinfunction "1_DB2") (pintype "passive"))
    )
    (net (code "3") (name "DISABLE") (class "Default")
      (node (ref "C2") (pin "2") (pinfunction "2_2") (pintype "passive"))
      (node (ref "IC6") (pin "8") (pinfunction "O_8") (pintype "output"))
      (node (ref "IC8") (pin "8") (pinfunction "A7_8") (pintype "input"))
      (node (ref "Q1") (pin "3") (pinfunction "E_3") (pintype "passive"))
    )
    (net (code "4") (name "EMEM0") (class "Default")
      (node (ref "IC2") (pin "11") (pinfunction "B8_11") (pintype "bidirectional"))
      (node (ref "IC4") (pin "19") (pinfunction "I/O7_19") (pintype "tri_state"))
    )
    (net (code "5") (name "EMEM1") (class "Default")
      (node (ref "IC2") (pin "12") (pinfunction "B7_12") (pintype "bidirectional"))
      (node (ref "IC4") (pin "18") (pinfunction "I/O6_18") (pintype "tri_state"))
    )
    (net (code "6") (name "EMEM2") (class "Default")
      (node (ref "IC2") (pin "13") (pinfunction "B6_13") (pintype "bidirectional"))
      (node (ref "IC4") (pin "17") (pinfunction "I/O5_17") (pintype "tri_state"))
    )
    (net (code "7") (name "EMEM3") (class "Default")
      (node (ref "IC2") (pin "14") (pinfunction "B5_14") (pintype "bidirectional"))
      (node (ref "IC4") (pin "16") (pinfunction "I/O4_16") (pintype "tri_state"))
    )
    (net (code "8") (name "GND") (class "Default")
      (node (ref "B1") (pin "-") (pinfunction "-_-") (pintype "passive"))
      (node (ref "B1") (pin "-@1") (pinfunction "-_-@1") (pintype "passive"))
      (node (ref "C1") (pin "2") (pinfunction "2_2") (pintype "passive"))
      (node (ref "C10") (pin "-") (pinfunction "-_-") (pintype "passive"))
      (node (ref "C3") (pin "2") (pinfunction "2_2") (pintype "passive"))
      (node (ref "C4") (pin "2") (pinfunction "2_2") (pintype "passive"))
      (node (ref "C5") (pin "2") (pinfunction "2_2") (pintype "passive"))
      (node (ref "C6") (pin "2") (pinfunction "2_2") (pintype "passive"))
      (node (ref "C7") (pin "2") (pinfunction "2_2") (pintype "passive"))
      (node (ref "C8") (pin "2") (pinfunction "2_2") (pintype "passive"))
      (node (ref "C9") (pin "2") (pinfunction "2_2") (pintype "passive"))
      (node (ref "D10") (pin "12") (pinfunction "12_12") (pintype "passive"))
      (node (ref "D10") (pin "16") (pinfunction "16_16") (pintype "passive"))
      (node (ref "D10") (pin "3") (pinfunction "3_3") (pintype "passive"))
      (node (ref "D10") (pin "6") (pinfunction "6_6") (pintype "passive"))
      (node (ref "D11") (pin "12") (pinfunction "12_12") (pintype "passive"))
      (node (ref "D11") (pin "16") (pinfunction "16_16") (pintype "passive"))
      (node (ref "D11") (pin "3") (pinfunction "3_3") (pintype "passive"))
      (node (ref "D11") (pin "6") (pinfunction "6_6") (pintype "passive"))
      (node (ref "D12") (pin "12") (pinfunction "12_12") (pintype "passive"))
      (node (ref "D12") (pin "16") (pinfunction "16_16") (pintype "passive"))
      (node (ref "D12") (pin "3") (pinfunction "3_3") (pintype "passive"))
      (node (ref "D12") (pin "6") (pinfunction "6_6") (pintype "passive"))
      (node (ref "D13") (pin "12") (pinfunction "12_12") (pintype "passive"))
      (node (ref "D13") (pin "16") (pinfunction "16_16") (pintype "passive"))
      (node (ref "D13") (pin "3") (pinfunction "3_3") (pintype "passive"))
      (node (ref "D13") (pin "6") (pinfunction "6_6") (pintype "passive"))
      (node (ref "D14") (pin "12") (pinfunction "12_12") (pintype "passive"))
      (node (ref "D14") (pin "16") (pinfunction "16_16") (pintype "passive"))
      (node (ref "D14") (pin "3") (pinfunction "3_3") (pintype "passive"))
      (node (ref "D14") (pin "6") (pinfunction "6_6") (pintype "passive"))
      (node (ref "D7") (pin "12") (pinfunction "12_12") (pintype "passive"))
      (node (ref "D7") (pin "16") (pinfunction "16_16") (pintype "passive"))
      (node (ref "D7") (pin "3") (pinfunction "3_3") (pintype "passive"))
      (node (ref "D7") (pin "6") (pinfunction "6_6") (pintype "passive"))
      (node (ref "D8") (pin "12") (pinfunction "12_12") (pintype "passive"))
      (node (ref "D8") (pin "16") (pinfunction "16_16") (pintype "passive"))
      (node (ref "D8") (pin "3") (pinfunction "3_3") (pintype "passive"))
      (node (ref "D8") (pin "6") (pinfunction "6_6") (pintype "passive"))
      (node (ref "D9") (pin "12") (pinfunction "12_12") (pintype "passive"))
      (node (ref "D9") (pin "16") (pinfunction "16_16") (pintype "passive"))
      (node (ref "D9") (pin "3") (pinfunction "3_3") (pintype "passive"))
      (node (ref "D9") (pin "6") (pinfunction "6_6") (pintype "passive"))
      (node (ref "GND1") (pin "1") (pinfunction "1_1") (pintype "passive"))
      (node (ref "GND1") (pin "2") (pinfunction "2_2") (pintype "passive"))
      (node (ref "GND10") (pin "1") (pinfunction "1_1") (pintype "passive"))
      (node (ref "GND10") (pin "2") (pinfunction "2_2") (pintype "passive"))
      (node (ref "GND11") (pin "1") (pinfunction "1_1") (pintype "passive"))
      (node (ref "GND11") (pin "2") (pinfunction "2_2") (pintype "passive"))
      (node (ref "GND12") (pin "1") (pinfunction "1_1") (pintype "passive"))
      (node (ref "GND12") (pin "2") (pinfunction "2_2") (pintype "passive"))
      (node (ref "GND13") (pin "1") (pinfunction "1_1") (pintype "passive"))
      (node (ref "GND13") (pin "2") (pinfunction "2_2") (pintype "passive"))
      (node (ref "GND14") (pin "1") (pinfunction "1_1") (pintype "passive"))
      (node (ref "GND14") (pin "2") (pinfunction "2_2") (pintype "passive"))
      (node (ref "GND15") (pin "1") (pinfunction "1_1") (pintype "passive"))
      (node (ref "GND15") (pin "2") (pinfunction "2_2") (pintype "passive"))
      (node (ref "GND16") (pin "1") (pinfunction "1_1") (pintype "passive"))
      (node (ref "GND16") (pin "2") (pinfunction "2_2") (pintype "passive"))
      (node (ref "GND17") (pin "1") (pinfunction "1_1") (pintype "passive"))
      (node (ref "GND17") (pin "2") (pinfunction "2_2") (pintype "passive"))
      (node (ref "GND18") (pin "1") (pinfunction "1_1") (pintype "passive"))
      (node (ref "GND18") (pin "2") (pinfunction "2_2") (pintype "passive"))
      (node (ref "GND19") (pin "1") (pinfunction "1_1") (pintype "passive"))
      (node (ref "GND19") (pin "2") (pinfunction "2_2") (pintype "passive"))
      (node (ref "GND2") (pin "1") (pinfunction "1_1") (pintype "passive"))
      (node (ref "GND2") (pin "2") (pinfunction "2_2") (pintype "passive"))
      (node (ref "GND20") (pin "1") (pinfunction "1_1") (pintype "passive"))
      (node (ref "GND20") (pin "2") (pinfunction "2_2") (pintype "passive"))
      (node (ref "GND21") (pin "1") (pinfunction "1_1") (pintype "passive"))
      (node (ref "GND21") (pin "2") (pinfunction "2_2") (pintype "passive"))
      (node (ref "GND22") (pin "1") (pinfunction "1_1") (pintype "passive"))
      (node (ref "GND22") (pin "2") (pinfunction "2_2") (pintype "passive"))
      (node (ref "GND23") (pin "1") (pinfunction "1_1") (pintype "passive"))
      (node (ref "GND23") (pin "2") (pinfunction "2_2") (pintype "passive"))
      (node (ref "GND24") (pin "1") (pinfunction "1_1") (pintype "passive"))
      (node (ref "GND24") (pin "2") (pinfunction "2_2") (pintype "passive"))
      (node (ref "GND25") (pin "1") (pinfunction "1_1") (pintype "passive"))
      (node (ref "GND25") (pin "2") (pinfunction "2_2") (pintype "passive"))
      (node (ref "GND26") (pin "1") (pinfunction "1_1") (pintype "passive"))
      (node (ref "GND26") (pin "2") (pinfunction "2_2") (pintype "passive"))
      (node (ref "GND27") (pin "1") (pinfunction "1_1") (pintype "passive"))
      (node (ref "GND27") (pin "2") (pinfunction "2_2") (pintype "passive"))
      (node (ref "GND28") (pin "1") (pinfunction "1_1") (pintype "passive"))
      (node (ref "GND28") (pin "2") (pinfunction "2_2") (pintype "passive"))
      (node (ref "GND29") (pin "1") (pinfunction "1_1") (pintype "passive"))
      (node (ref "GND29") (pin "2") (pinfunction "2_2") (pintype "passive"))
      (node (ref "GND3") (pin "1") (pinfunction "1_1") (pintype "passive"))
      (node (ref "GND3") (pin "2") (pinfunction "2_2") (pintype "passive"))
      (node (ref "GND30") (pin "1") (pinfunction "1_1") (pintype "passive"))
      (node (ref "GND30") (pin "2") (pinfunction "2_2") (pintype "passive"))
      (node (ref "GND31") (pin "1") (pinfunction "1_1") (pintype "passive"))
      (node (ref "GND31") (pin "2") (pinfunction "2_2") (pintype "passive"))
      (node (ref "GND32") (pin "1") (pinfunction "1_1") (pintype "passive"))
      (node (ref "GND32") (pin "2") (pinfunction "2_2") (pintype "passive"))
      (node (ref "GND33") (pin "1") (pinfunction "1_1") (pintype "passive"))
      (node (ref "GND33") (pin "2") (pinfunction "2_2") (pintype "passive"))
      (node (ref "GND34") (pin "1") (pinfunction "1_1") (pintype "passive"))
      (node (ref "GND34") (pin "2") (pinfunction "2_2") (pintype "passive"))
      (node (ref "GND35") (pin "1") (pinfunction "1_1") (pintype "passive"))
      (node (ref "GND35") (pin "2") (pinfunction "2_2") (pintype "passive"))
      (node (ref "GND36") (pin "1") (pinfunction "1_1") (pintype "passive"))
      (node (ref "GND36") (pin "2") (pinfunction "2_2") (pintype "passive"))
      (node (ref "GND37") (pin "1") (pinfunction "1_1") (pintype "passive"))
      (node (ref "GND37") (pin "2") (pinfunction "2_2") (pintype "passive"))
      (node (ref "GND38") (pin "1") (pinfunction "1_1") (pintype "passive"))
      (node (ref "GND38") (pin "2") (pinfunction "2_2") (pintype "passive"))
      (node (ref "GND39") (pin "1") (pinfunction "1_1") (pintype "passive"))
      (node (ref "GND39") (pin "2") (pinfunction "2_2") (pintype "passive"))
      (node (ref "GND4") (pin "1") (pinfunction "1_1") (pintype "passive"))
      (node (ref "GND4") (pin "2") (pinfunction "2_2") (pintype "passive"))
      (node (ref "GND40") (pin "1") (pinfunction "1_1") (pintype "passive"))
      (node (ref "GND40") (pin "2") (pinfunction "2_2") (pintype "passive"))
      (node (ref "GND41") (pin "1") (pinfunction "1_1") (pintype "passive"))
      (node (ref "GND41") (pin "2") (pinfunction "2_2") (pintype "passive"))
      (node (ref "GND42") (pin "1") (pinfunction "1_1") (pintype "passive"))
      (node (ref "GND42") (pin "2") (pinfunction "2_2") (pintype "passive"))
      (node (ref "GND43") (pin "1") (pinfunction "1_1") (pintype "passive"))
      (node (ref "GND43") (pin "2") (pinfunction "2_2") (pintype "passive"))
      (node (ref "GND44") (pin "1") (pinfunction "1_1") (pintype "passive"))
      (node (ref "GND44") (pin "2") (pinfunction "2_2") (pintype "passive"))
      (node (ref "GND5") (pin "1") (pinfunction "1_1") (pintype "passive"))
      (node (ref "GND5") (pin "2") (pinfunction "2_2") (pintype "passive"))
      (node (ref "GND6") (pin "1") (pinfunction "1_1") (pintype "passive"))
      (node (ref "GND6") (pin "2") (pinfunction "2_2") (pintype "passive"))
      (node (ref "GND7") (pin "1") (pinfunction "1_1") (pintype "passive"))
      (node (ref "GND7") (pin "2") (pinfunction "2_2") (pintype "passive"))
      (node (ref "GND8") (pin "1") (pinfunction "1_1") (pintype "passive"))
      (node (ref "GND8") (pin "2") (pinfunction "2_2") (pintype "passive"))
      (node (ref "GND9") (pin "1") (pinfunction "1_1") (pintype "passive"))
      (node (ref "GND9") (pin "2") (pinfunction "2_2") (pintype "passive"))
      (node (ref "IC1") (pin "19") (pinfunction "G_19") (pintype "input"))
      (node (ref "IC2") (pin "19") (pinfunction "G_19") (pintype "input"))
      (node (ref "IC3") (pin "14") (pinfunction "VSS_14") (pintype "power_in"))
      (node (ref "IC4") (pin "14") (pinfunction "VSS_14") (pintype "power_in"))
      (node (ref "IC5") (pin "4") (pinfunction "G2A_4") (pintype "input"))
      (node (ref "IC5") (pin "5") (pinfunction "G2B_5") (pintype "input"))
      (node (ref "IC8") (pin "1") (pinfunction "G1_1") (pintype "input"))
      (node (ref "IC8") (pin "19") (pinfunction "G2_19") (pintype "input"))
      (node (ref "IC8") (pin "9") (pinfunction "A8_9") (pintype "input"))
      (node (ref "R1") (pin "1") (pinfunction "1_1") (pintype "passive"))
      (node (ref "R2") (pin "1") (pinfunction "1_1") (pintype "passive"))
      (node (ref "R3") (pin "1") (pinfunction "1_1") (pintype "passive"))
      (node (ref "R4") (pin "1") (pinfunction "1_1") (pintype "passive"))
      (node (ref "SV10") (pin "1") (pinfunction "1_1") (pintype "passive"))
      (node (ref "SV10") (pin "2") (pinfunction "2_2") (pintype "passive"))
      (node (ref "SV10") (pin "3") (pinfunction "3_3") (pintype "passive"))
      (node (ref "SV10") (pin "4") (pinfunction "4_4") (pintype "passive"))
      (node (ref "SV10") (pin "5") (pinfunction "5_5") (pintype "passive"))
      (node (ref "SV10") (pin "6") (pinfunction "6_6") (pintype "passive"))
      (node (ref "SV10") (pin "7") (pinfunction "7_7") (pintype "passive"))
      (node (ref "SV10") (pin "8") (pinfunction "8_8") (pintype "passive"))
      (node (ref "SV12") (pin "1") (pinfunction "1_1") (pintype "passive"))
      (node (ref "SV12") (pin "10") (pinfunction "10_10") (pintype "passive"))
      (node (ref "SV12") (pin "2") (pinfunction "2_2") (pintype "passive"))
      (node (ref "SV12") (pin "3") (pinfunction "3_3") (pintype "passive"))
      (node (ref "SV12") (pin "4") (pinfunction "4_4") (pintype "passive"))
      (node (ref "SV12") (pin "5") (pinfunction "5_5") (pintype "passive"))
      (node (ref "SV12") (pin "6") (pinfunction "6_6") (pintype "passive"))
      (node (ref "SV12") (pin "7") (pinfunction "7_7") (pintype "passive"))
      (node (ref "SV12") (pin "8") (pinfunction "8_8") (pintype "passive"))
      (node (ref "SV12") (pin "9") (pinfunction "9_9") (pintype "passive"))
      (node (ref "SV176") (pin "1") (pinfunction "1_1") (pintype "passive"))
      (node (ref "SV176") (pin "10") (pinfunction "10_10") (pintype "passive"))
      (node (ref "SV176") (pin "11") (pinfunction "11_11") (pintype "passive"))
      (node (ref "SV176") (pin "12") (pinfunction "12_12") (pintype "passive"))
      (node (ref "SV176") (pin "13") (pinfunction "13_13") (pintype "passive"))
      (node (ref "SV176") (pin "14") (pinfunction "14_14") (pintype "passive"))
      (node (ref "SV176") (pin "15") (pinfunction "15_15") (pintype "passive"))
      (node (ref "SV176") (pin "16") (pinfunction "16_16") (pintype "passive"))
      (node (ref "SV176") (pin "17") (pinfunction "17_17") (pintype "passive"))
      (node (ref "SV176") (pin "18") (pinfunction "18_18") (pintype "passive"))
      (node (ref "SV176") (pin "19") (pinfunction "19_19") (pintype "passive"))
      (node (ref "SV176") (pin "2") (pinfunction "2_2") (pintype "passive"))
      (node (ref "SV176") (pin "20") (pinfunction "20_20") (pintype "passive"))
      (node (ref "SV176") (pin "3") (pinfunction "3_3") (pintype "passive"))
      (node (ref "SV176") (pin "4") (pinfunction "4_4") (pintype "passive"))
      (node (ref "SV176") (pin "5") (pinfunction "5_5") (pintype "passive"))
      (node (ref "SV176") (pin "6") (pinfunction "6_6") (pintype "passive"))
      (node (ref "SV176") (pin "7") (pinfunction "7_7") (pintype "passive"))
      (node (ref "SV176") (pin "8") (pinfunction "8_8") (pintype "passive"))
      (node (ref "SV176") (pin "9") (pinfunction "9_9") (pintype "passive"))
      (node (ref "SV180") (pin "1") (pinfunction "1_1") (pintype "passive"))
      (node (ref "SV180") (pin "10") (pinfunction "10_10") (pintype "passive"))
      (node (ref "SV180") (pin "2") (pinfunction "2_2") (pintype "passive"))
      (node (ref "SV180") (pin "3") (pinfunction "3_3") (pintype "passive"))
      (node (ref "SV180") (pin "4") (pinfunction "4_4") (pintype "passive"))
      (node (ref "SV180") (pin "5") (pinfunction "5_5") (pintype "passive"))
      (node (ref "SV180") (pin "6") (pinfunction "6_6") (pintype "passive"))
      (node (ref "SV180") (pin "7") (pinfunction "7_7") (pintype "passive"))
      (node (ref "SV180") (pin "8") (pinfunction "8_8") (pintype "passive"))
      (node (ref "SV180") (pin "9") (pinfunction "9_9") (pintype "passive"))
      (node (ref "SV4") (pin "1") (pinfunction "1_1") (pintype "passive"))
      (node (ref "SV4") (pin "10") (pinfunction "10_10") (pintype "passive"))
      (node (ref "SV4") (pin "11") (pinfunction "11_11") (pintype "passive"))
      (node (ref "SV4") (pin "12") (pinfunction "12_12") (pintype "passive"))
      (node (ref "SV4") (pin "13") (pinfunction "13_13") (pintype "passive"))
      (node (ref "SV4") (pin "14") (pinfunction "14_14") (pintype "passive"))
      (node (ref "SV4") (pin "15") (pinfunction "15_15") (pintype "passive"))
      (node (ref "SV4") (pin "16") (pinfunction "16_16") (pintype "passive"))
      (node (ref "SV4") (pin "17") (pinfunction "17_17") (pintype "passive"))
      (node (ref "SV4") (pin "18") (pinfunction "18_18") (pintype "passive"))
      (node (ref "SV4") (pin "19") (pinfunction "19_19") (pintype "passive"))
      (node (ref "SV4") (pin "2") (pinfunction "2_2") (pintype "passive"))
      (node (ref "SV4") (pin "20") (pinfunction "20_20") (pintype "passive"))
      (node (ref "SV4") (pin "3") (pinfunction "3_3") (pintype "passive"))
      (node (ref "SV4") (pin "4") (pinfunction "4_4") (pintype "passive"))
      (node (ref "SV4") (pin "5") (pinfunction "5_5") (pintype "passive"))
      (node (ref "SV4") (pin "6") (pinfunction "6_6") (pintype "passive"))
      (node (ref "SV4") (pin "7") (pinfunction "7_7") (pintype "passive"))
      (node (ref "SV4") (pin "8") (pinfunction "8_8") (pintype "passive"))
      (node (ref "SV4") (pin "9") (pinfunction "9_9") (pintype "passive"))
      (node (ref "SV6") (pin "1") (pinfunction "1_1") (pintype "passive"))
      (node (ref "SV6") (pin "10") (pinfunction "10_10") (pintype "passive"))
      (node (ref "SV6") (pin "11") (pinfunction "11_11") (pintype "passive"))
      (node (ref "SV6") (pin "12") (pinfunction "12_12") (pintype "passive"))
      (node (ref "SV6") (pin "13") (pinfunction "13_13") (pintype "passive"))
      (node (ref "SV6") (pin "14") (pinfunction "14_14") (pintype "passive"))
      (node (ref "SV6") (pin "15") (pinfunction "15_15") (pintype "passive"))
      (node (ref "SV6") (pin "16") (pinfunction "16_16") (pintype "passive"))
      (node (ref "SV6") (pin "17") (pinfunction "17_17") (pintype "passive"))
      (node (ref "SV6") (pin "18") (pinfunction "18_18") (pintype "passive"))
      (node (ref "SV6") (pin "19") (pinfunction "19_19") (pintype "passive"))
      (node (ref "SV6") (pin "2") (pinfunction "2_2") (pintype "passive"))
      (node (ref "SV6") (pin "20") (pinfunction "20_20") (pintype "passive"))
      (node (ref "SV6") (pin "3") (pinfunction "3_3") (pintype "passive"))
      (node (ref "SV6") (pin "4") (pinfunction "4_4") (pintype "passive"))
      (node (ref "SV6") (pin "5") (pinfunction "5_5") (pintype "passive"))
      (node (ref "SV6") (pin "6") (pinfunction "6_6") (pintype "passive"))
      (node (ref "SV6") (pin "7") (pinfunction "7_7") (pintype "passive"))
      (node (ref "SV6") (pin "8") (pinfunction "8_8") (pintype "passive"))
      (node (ref "SV6") (pin "9") (pinfunction "9_9") (pintype "passive"))
      (node (ref "U$2") (pin "AC1") (pinfunction "1_AC1") (pintype "passive"))
      (node (ref "U$2") (pin "AC2") (pinfunction "1_AC2") (pintype "passive"))
      (node (ref "U$2") (pin "AF1") (pinfunction "1_AF1") (pintype "passive"))
      (node (ref "U$2") (pin "AF2") (pinfunction "1_AF2") (pintype "passive"))
      (node (ref "U$2") (pin "AN1") (pinfunction "1_AN1") (pintype "passive"))
      (node (ref "U$2") (pin "AN2") (pinfunction "1_AN2") (pintype "passive"))
      (node (ref "U$2") (pin "AT1") (pinfunction "1_AT1") (pintype "passive"))
      (node (ref "U$2") (pin "AT2") (pinfunction "1_AT2") (pintype "passive"))
      (node (ref "U$2") (pin "BC1") (pinfunction "1_BC1") (pintype "passive"))
      (node (ref "U$2") (pin "BC2") (pinfunction "1_BC2") (pintype "passive"))
      (node (ref "U$2") (pin "BF1") (pinfunction "1_BF1") (pintype "passive"))
      (node (ref "U$2") (pin "BF2") (pinfunction "1_BF2") (pintype "passive"))
      (node (ref "U$2") (pin "BN1") (pinfunction "1_BN1") (pintype "passive"))
      (node (ref "U$2") (pin "BN2") (pinfunction "1_BN2") (pintype "passive"))
      (node (ref "U$2") (pin "BT1") (pinfunction "1_BT1") (pintype "passive"))
      (node (ref "U$2") (pin "BT2") (pinfunction "1_BT2") (pintype "passive"))
      (node (ref "U$2") (pin "CC1") (pinfunction "1_CC1") (pintype "passive"))
      (node (ref "U$2") (pin "CC2") (pinfunction "1_CC2") (pintype "passive"))
      (node (ref "U$2") (pin "CF1") (pinfunction "1_CF1") (pintype "passive"))
      (node (ref "U$2") (pin "CF2") (pinfunction "1_CF2") (pintype "passive"))
      (node (ref "U$2") (pin "CN1") (pinfunction "1_CN1") (pintype "passive"))
      (node (ref "U$2") (pin "CN2") (pinfunction "1_CN2") (pintype "passive"))
      (node (ref "U$2") (pin "CT1") (pinfunction "1_CT1") (pintype "passive"))
      (node (ref "U$2") (pin "CT2") (pinfunction "1_CT2") (pintype "passive"))
      (node (ref "U$2") (pin "DC1") (pinfunction "1_DC1") (pintype "passive"))
      (node (ref "U$2") (pin "DC2") (pinfunction "1_DC2") (pintype "passive"))
      (node (ref "U$2") (pin "DF1") (pinfunction "1_DF1") (pintype "passive"))
      (node (ref "U$2") (pin "DF2") (pinfunction "1_DF2") (pintype "passive"))
      (node (ref "U$2") (pin "DN1") (pinfunction "1_DN1") (pintype "passive"))
      (node (ref "U$2") (pin "DN2") (pinfunction "1_DN2") (pintype "passive"))
      (node (ref "U$2") (pin "DT1") (pinfunction "1_DT1") (pintype "passive"))
      (node (ref "U$2") (pin "DT2") (pinfunction "1_DT2") (pintype "passive"))
    )
    (net (code "9") (name "INHIBIT") (class "Default")
      (node (ref "D10") (pin "13") (pinfunction "13_13") (pintype "passive"))
      (node (ref "U$2") (pin "AP2") (pinfunction "1_AP2") (pintype "passive"))
    )
    (net (code "10") (name "INITIALIZE") (class "Default")
      (node (ref "D11") (pin "14") (pinfunction "14_14") (pintype "passive"))
      (node (ref "U$2") (pin "CR1") (pinfunction "1_CR1") (pintype "passive"))
    )
    (net (code "11") (name "INT_IN_PROG") (class "Default")
      (node (ref "D8") (pin "13") (pinfunction "13_13") (pintype "passive"))
      (node (ref "U$2") (pin "BP2") (pinfunction "1_BP2") (pintype "passive"))
    )
    (net (code "12") (name "INT_STROBE") (class "Default")
      (node (ref "D8") (pin "4") (pinfunction "4_4") (pintype "passive"))
      (node (ref "U$2") (pin "BD2") (pinfunction "1_BD2") (pintype "passive"))
    )
    (net (code "13") (name "MEM00") (class "Default")
      (node (ref "IC2") (pin "15") (pinfunction "B4_15") (pintype "bidirectional"))
      (node (ref "IC4") (pin "15") (pinfunction "I/O3_15") (pintype "tri_state"))
    )
    (net (code "14") (name "MEM01") (class "Default")
      (node (ref "IC2") (pin "16") (pinfunction "B3_16") (pintype "bidirectional"))
      (node (ref "IC4") (pin "13") (pinfunction "I/O2_13") (pintype "tri_state"))
    )
    (net (code "15") (name "MEM02") (class "Default")
      (node (ref "IC2") (pin "17") (pinfunction "B2_17") (pintype "bidirectional"))
      (node (ref "IC4") (pin "12") (pinfunction "I/O1_12") (pintype "tri_state"))
    )
    (net (code "16") (name "MEM03") (class "Default")
      (node (ref "IC2") (pin "18") (pinfunction "B1_18") (pintype "bidirectional"))
      (node (ref "IC4") (pin "11") (pinfunction "I/O0_11") (pintype "tri_state"))
    )
    (net (code "17") (name "MEM04") (class "Default")
      (node (ref "IC1") (pin "11") (pinfunction "B8_11") (pintype "bidirectional"))
      (node (ref "IC3") (pin "19") (pinfunction "I/O7_19") (pintype "tri_state"))
    )
    (net (code "18") (name "MEM05") (class "Default")
      (node (ref "IC1") (pin "12") (pinfunction "B7_12") (pintype "bidirectional"))
      (node (ref "IC3") (pin "18") (pinfunction "I/O6_18") (pintype "tri_state"))
    )
    (net (code "19") (name "MEM06") (class "Default")
      (node (ref "IC1") (pin "13") (pinfunction "B6_13") (pintype "bidirectional"))
      (node (ref "IC3") (pin "17") (pinfunction "I/O5_17") (pintype "tri_state"))
    )
    (net (code "20") (name "MEM07") (class "Default")
      (node (ref "IC1") (pin "14") (pinfunction "B5_14") (pintype "bidirectional"))
      (node (ref "IC3") (pin "16") (pinfunction "I/O4_16") (pintype "tri_state"))
    )
    (net (code "21") (name "MEM08") (class "Default")
      (node (ref "IC1") (pin "15") (pinfunction "B4_15") (pintype "bidirectional"))
      (node (ref "IC3") (pin "15") (pinfunction "I/O3_15") (pintype "tri_state"))
    )
    (net (code "22") (name "MEM09") (class "Default")
      (node (ref "IC1") (pin "16") (pinfunction "B3_16") (pintype "bidirectional"))
      (node (ref "IC3") (pin "13") (pinfunction "I/O2_13") (pintype "tri_state"))
    )
    (net (code "23") (name "MEM10") (class "Default")
      (node (ref "IC1") (pin "17") (pinfunction "B2_17") (pintype "bidirectional"))
      (node (ref "IC3") (pin "12") (pinfunction "I/O1_12") (pintype "tri_state"))
    )
    (net (code "24") (name "MEM11") (class "Default")
      (node (ref "IC1") (pin "18") (pinfunction "B1_18") (pintype "bidirectional"))
      (node (ref "IC3") (pin "11") (pinfunction "I/O0_11") (pintype "tri_state"))
    )
    (net (code "25") (name "Net-(A1-Pad1)") (class "Default")
      (node (ref "A1") (pin "1") (pinfunction "1_1") (pintype "passive"))
      (node (ref "A1") (pin "2") (pinfunction "2_2") (pintype "passive"))
      (node (ref "IC9") (pin "1") (pinfunction "1_1") (pintype "passive"))
    )
    (net (code "26") (name "Net-(A2-Pad1)") (class "Default")
      (node (ref "A2") (pin "1") (pinfunction "1_1") (pintype "passive"))
      (node (ref "A2") (pin "2") (pinfunction "2_2") (pintype "passive"))
      (node (ref "IC9") (pin "2") (pinfunction "2_2") (pintype "passive"))
    )
    (net (code "27") (name "Net-(A3-Pad1)") (class "Default")
      (node (ref "A3") (pin "1") (pinfunction "1_1") (pintype "passive"))
      (node (ref "A3") (pin "2") (pinfunction "2_2") (pintype "passive"))
      (node (ref "IC9") (pin "3") (pinfunction "3_3") (pintype "passive"))
    )
    (net (code "28") (name "Net-(A4-Pad1)") (class "Default")
      (node (ref "A4") (pin "1") (pinfunction "1_1") (pintype "passive"))
      (node (ref "A4") (pin "2") (pinfunction "2_2") (pintype "passive"))
      (node (ref "IC9") (pin "4") (pinfunction "4_4") (pintype "passive"))
    )
    (net (code "29") (name "Net-(A5-Pad1)") (class "Default")
      (node (ref "A5") (pin "1") (pinfunction "1_1") (pintype "passive"))
      (node (ref "A5") (pin "2") (pinfunction "2_2") (pintype "passive"))
      (node (ref "IC9") (pin "5") (pinfunction "5_5") (pintype "passive"))
    )
    (net (code "30") (name "Net-(A6-Pad1)") (class "Default")
      (node (ref "A6") (pin "1") (pinfunction "1_1") (pintype "passive"))
      (node (ref "A6") (pin "2") (pinfunction "2_2") (pintype "passive"))
      (node (ref "IC9") (pin "6") (pinfunction "6_6") (pintype "passive"))
    )
    (net (code "31") (name "Net-(A7-Pad1)") (class "Default")
      (node (ref "A7") (pin "1") (pinfunction "1_1") (pintype "passive"))
      (node (ref "A7") (pin "2") (pinfunction "2_2") (pintype "passive"))
      (node (ref "IC9") (pin "7") (pinfunction "7_7") (pintype "passive"))
    )
    (net (code "32") (name "Net-(A8-Pad1)") (class "Default")
      (node (ref "A8") (pin "1") (pinfunction "1_1") (pintype "passive"))
      (node (ref "A8") (pin "2") (pinfunction "2_2") (pintype "passive"))
      (node (ref "IC9") (pin "8") (pinfunction "8_8") (pintype "passive"))
    )
    (net (code "33") (name "Net-(A9-Pad1)") (class "Default")
      (node (ref "A9") (pin "1") (pinfunction "1_1") (pintype "passive"))
      (node (ref "A9") (pin "2") (pinfunction "2_2") (pintype "passive"))
      (node (ref "IC9") (pin "9") (pinfunction "9_9") (pintype "passive"))
    )
    (net (code "34") (name "Net-(A10-Pad1)") (class "Default")
      (node (ref "A10") (pin "1") (pinfunction "1_1") (pintype "passive"))
      (node (ref "A10") (pin "2") (pinfunction "2_2") (pintype "passive"))
      (node (ref "IC9") (pin "10") (pinfunction "10_10") (pintype "passive"))
    )
    (net (code "35") (name "Net-(A11-Pad1)") (class "Default")
      (node (ref "A11") (pin "1") (pinfunction "1_1") (pintype "passive"))
      (node (ref "A11") (pin "2") (pinfunction "2_2") (pintype "passive"))
      (node (ref "IC9") (pin "11") (pinfunction "11_11") (pintype "passive"))
    )
    (net (code "36") (name "Net-(A12-Pad1)") (class "Default")
      (node (ref "A12") (pin "1") (pinfunction "1_1") (pintype "passive"))
      (node (ref "A12") (pin "2") (pinfunction "2_2") (pintype "passive"))
      (node (ref "IC9") (pin "12") (pinfunction "12_12") (pintype "passive"))
    )
    (net (code "37") (name "Net-(A13-Pad1)") (class "Default")
      (node (ref "A13") (pin "1") (pinfunction "1_1") (pintype "passive"))
      (node (ref "A13") (pin "2") (pinfunction "2_2") (pintype "passive"))
      (node (ref "IC9") (pin "13") (pinfunction "13_13") (pintype "passive"))
    )
    (net (code "38") (name "Net-(A14-Pad1)") (class "Default")
      (node (ref "A14") (pin "1") (pinfunction "1_1") (pintype "passive"))
      (node (ref "A14") (pin "2") (pinfunction "2_2") (pintype "passive"))
      (node (ref "IC9") (pin "14") (pinfunction "14_14") (pintype "passive"))
    )
    (net (code "39") (name "Net-(A15-Pad1)") (class "Default")
      (node (ref "A15") (pin "1") (pinfunction "1_1") (pintype "passive"))
      (node (ref "A15") (pin "2") (pinfunction "2_2") (pintype "passive"))
      (node (ref "IC9") (pin "15") (pinfunction "15_15") (pintype "passive"))
    )
    (net (code "40") (name "Net-(A16-Pad1)") (class "Default")
      (node (ref "A16") (pin "1") (pinfunction "1_1") (pintype "passive"))
      (node (ref "A16") (pin "2") (pinfunction "2_2") (pintype "passive"))
      (node (ref "IC9") (pin "16") (pinfunction "16_16") (pintype "passive"))
    )
    (net (code "41") (name "Net-(A17-Pad1)") (class "Default")
      (node (ref "A17") (pin "1") (pinfunction "1_1") (pintype "passive"))
      (node (ref "A17") (pin "2") (pinfunction "2_2") (pintype "passive"))
      (node (ref "IC10") (pin "1") (pinfunction "1_1") (pintype "passive"))
    )
    (net (code "42") (name "Net-(A18-Pad1)") (class "Default")
      (node (ref "A18") (pin "1") (pinfunction "1_1") (pintype "passive"))
      (node (ref "A18") (pin "2") (pinfunction "2_2") (pintype "passive"))
      (node (ref "IC10") (pin "2") (pinfunction "2_2") (pintype "passive"))
    )
    (net (code "43") (name "Net-(A19-Pad1)") (class "Default")
      (node (ref "A19") (pin "1") (pinfunction "1_1") (pintype "passive"))
      (node (ref "A19") (pin "2") (pinfunction "2_2") (pintype "passive"))
      (node (ref "IC10") (pin "3") (pinfunction "3_3") (pintype "passive"))
    )
    (net (code "44") (name "Net-(A20-Pad1)") (class "Default")
      (node (ref "A20") (pin "1") (pinfunction "1_1") (pintype "passive"))
      (node (ref "A20") (pin "2") (pinfunction "2_2") (pintype "passive"))
      (node (ref "IC10") (pin "4") (pinfunction "4_4") (pintype "passive"))
    )
    (net (code "45") (name "Net-(A21-Pad1)") (class "Default")
      (node (ref "A21") (pin "1") (pinfunction "1_1") (pintype "passive"))
      (node (ref "A21") (pin "2") (pinfunction "2_2") (pintype "passive"))
      (node (ref "IC10") (pin "5") (pinfunction "5_5") (pintype "passive"))
    )
    (net (code "46") (name "Net-(A22-Pad1)") (class "Default")
      (node (ref "A22") (pin "1") (pinfunction "1_1") (pintype "passive"))
      (node (ref "A22") (pin "2") (pinfunction "2_2") (pintype "passive"))
      (node (ref "IC10") (pin "6") (pinfunction "6_6") (pintype "passive"))
    )
    (net (code "47") (name "Net-(A23-Pad1)") (class "Default")
      (node (ref "A23") (pin "1") (pinfunction "1_1") (pintype "passive"))
      (node (ref "A23") (pin "2") (pinfunction "2_2") (pintype "passive"))
      (node (ref "IC10") (pin "7") (pinfunction "7_7") (pintype "passive"))
    )
    (net (code "48") (name "Net-(A24-Pad1)") (class "Default")
      (node (ref "A24") (pin "1") (pinfunction "1_1") (pintype "passive"))
      (node (ref "A24") (pin "2") (pinfunction "2_2") (pintype "passive"))
      (node (ref "IC10") (pin "8") (pinfunction "8_8") (pintype "passive"))
    )
    (net (code "49") (name "Net-(A25-Pad1)") (class "Default")
      (node (ref "A25") (pin "1") (pinfunction "1_1") (pintype "passive"))
      (node (ref "A25") (pin "2") (pinfunction "2_2") (pintype "passive"))
      (node (ref "IC10") (pin "9") (pinfunction "9_9") (pintype "passive"))
    )
    (net (code "50") (name "Net-(A26-Pad1)") (class "Default")
      (node (ref "A26") (pin "1") (pinfunction "1_1") (pintype "passive"))
      (node (ref "A26") (pin "2") (pinfunction "2_2") (pintype "passive"))
      (node (ref "IC10") (pin "10") (pinfunction "10_10") (pintype "passive"))
    )
    (net (code "51") (name "Net-(A27-Pad1)") (class "Default")
      (node (ref "A27") (pin "1") (pinfunction "1_1") (pintype "passive"))
      (node (ref "A27") (pin "2") (pinfunction "2_2") (pintype "passive"))
      (node (ref "IC10") (pin "11") (pinfunction "11_11") (pintype "passive"))
    )
    (net (code "52") (name "Net-(A28-Pad1)") (class "Default")
      (node (ref "A28") (pin "1") (pinfunction "1_1") (pintype "passive"))
      (node (ref "A28") (pin "2") (pinfunction "2_2") (pintype "passive"))
      (node (ref "IC10") (pin "12") (pinfunction "12_12") (pintype "passive"))
    )
    (net (code "53") (name "Net-(A29-Pad1)") (class "Default")
      (node (ref "A29") (pin "1") (pinfunction "1_1") (pintype "passive"))
      (node (ref "A29") (pin "2") (pinfunction "2_2") (pintype "passive"))
      (node (ref "IC10") (pin "13") (pinfunction "13_13") (pintype "passive"))
    )
    (net (code "54") (name "Net-(A30-Pad1)") (class "Default")
      (node (ref "A30") (pin "1") (pinfunction "1_1") (pintype "passive"))
      (node (ref "A30") (pin "2") (pinfunction "2_2") (pintype "passive"))
      (node (ref "IC10") (pin "14") (pinfunction "14_14") (pintype "passive"))
    )
    (net (code "55") (name "Net-(A31-Pad1)") (class "Default")
      (node (ref "A31") (pin "1") (pinfunction "1_1") (pintype "passive"))
      (node (ref "A31") (pin "2") (pinfunction "2_2") (pintype "passive"))
      (node (ref "IC10") (pin "15") (pinfunction "15_15") (pintype "passive"))
    )
    (net (code "56") (name "Net-(A32-Pad1)") (class "Default")
      (node (ref "A32") (pin "1") (pinfunction "1_1") (pintype "passive"))
      (node (ref "A32") (pin "2") (pinfunction "2_2") (pintype "passive"))
      (node (ref "IC10") (pin "16") (pinfunction "16_16") (pintype "passive"))
    )
    (net (code "57") (name "Net-(A33-Pad1)") (class "Default")
      (node (ref "A33") (pin "1") (pinfunction "1_1") (pintype "passive"))
      (node (ref "A33") (pin "2") (pinfunction "2_2") (pintype "passive"))
      (node (ref "IC11") (pin "1") (pinfunction "1_1") (pintype "passive"))
    )
    (net (code "58") (name "Net-(A34-Pad1)") (class "Default")
      (node (ref "A34") (pin "1") (pinfunction "1_1") (pintype "passive"))
      (node (ref "A34") (pin "2") (pinfunction "2_2") (pintype "passive"))
      (node (ref "IC11") (pin "2") (pinfunction "2_2") (pintype "passive"))
    )
    (net (code "59") (name "Net-(A35-Pad1)") (class "Default")
      (node (ref "A35") (pin "1") (pinfunction "1_1") (pintype "passive"))
      (node (ref "A35") (pin "2") (pinfunction "2_2") (pintype "passive"))
      (node (ref "IC11") (pin "3") (pinfunction "3_3") (pintype "passive"))
    )
    (net (code "60") (name "Net-(A36-Pad1)") (class "Default")
      (node (ref "A36") (pin "1") (pinfunction "1_1") (pintype "passive"))
      (node (ref "A36") (pin "2") (pinfunction "2_2") (pintype "passive"))
      (node (ref "IC11") (pin "4") (pinfunction "4_4") (pintype "passive"))
    )
    (net (code "61") (name "Net-(A37-Pad1)") (class "Default")
      (node (ref "A37") (pin "1") (pinfunction "1_1") (pintype "passive"))
      (node (ref "A37") (pin "2") (pinfunction "2_2") (pintype "passive"))
      (node (ref "IC11") (pin "5") (pinfunction "5_5") (pintype "passive"))
    )
    (net (code "62") (name "Net-(A38-Pad1)") (class "Default")
      (node (ref "A38") (pin "1") (pinfunction "1_1") (pintype "passive"))
      (node (ref "A38") (pin "2") (pinfunction "2_2") (pintype "passive"))
      (node (ref "IC11") (pin "6") (pinfunction "6_6") (pintype "passive"))
    )
    (net (code "63") (name "Net-(A39-Pad1)") (class "Default")
      (node (ref "A39") (pin "1") (pinfunction "1_1") (pintype "passive"))
      (node (ref "A39") (pin "2") (pinfunction "2_2") (pintype "passive"))
      (node (ref "IC11") (pin "7") (pinfunction "7_7") (pintype "passive"))
    )
    (net (code "64") (name "Net-(A40-Pad1)") (class "Default")
      (node (ref "A40") (pin "1") (pinfunction "1_1") (pintype "passive"))
      (node (ref "A40") (pin "2") (pinfunction "2_2") (pintype "passive"))
      (node (ref "IC11") (pin "8") (pinfunction "8_8") (pintype "passive"))
    )
    (net (code "65") (name "Net-(A41-Pad1)") (class "Default")
      (node (ref "A41") (pin "1") (pinfunction "1_1") (pintype "passive"))
      (node (ref "A41") (pin "2") (pinfunction "2_2") (pintype "passive"))
      (node (ref "IC11") (pin "9") (pinfunction "9_9") (pintype "passive"))
    )
    (net (code "66") (name "Net-(A42-Pad1)") (class "Default")
      (node (ref "A42") (pin "1") (pinfunction "1_1") (pintype "passive"))
      (node (ref "A42") (pin "2") (pinfunction "2_2") (pintype "passive"))
      (node (ref "IC11") (pin "10") (pinfunction "10_10") (pintype "passive"))
    )
    (net (code "67") (name "Net-(A43-Pad1)") (class "Default")
      (node (ref "A43") (pin "1") (pinfunction "1_1") (pintype "passive"))
      (node (ref "A43") (pin "2") (pinfunction "2_2") (pintype "passive"))
      (node (ref "IC11") (pin "11") (pinfunction "11_11") (pintype "passive"))
    )
    (net (code "68") (name "Net-(A44-Pad1)") (class "Default")
      (node (ref "A44") (pin "1") (pinfunction "1_1") (pintype "passive"))
      (node (ref "A44") (pin "2") (pinfunction "2_2") (pintype "passive"))
      (node (ref "IC11") (pin "12") (pinfunction "12_12") (pintype "passive"))
    )
    (net (code "69") (name "Net-(A45-Pad1)") (class "Default")
      (node (ref "A45") (pin "1") (pinfunction "1_1") (pintype "passive"))
      (node (ref "A45") (pin "2") (pinfunction "2_2") (pintype "passive"))
      (node (ref "IC11") (pin "13") (pinfunction "13_13") (pintype "passive"))
    )
    (net (code "70") (name "Net-(A46-Pad1)") (class "Default")
      (node (ref "A46") (pin "1") (pinfunction "1_1") (pintype "passive"))
      (node (ref "A46") (pin "2") (pinfunction "2_2") (pintype "passive"))
      (node (ref "IC11") (pin "14") (pinfunction "14_14") (pintype "passive"))
    )
    (net (code "71") (name "Net-(A47-Pad1)") (class "Default")
      (node (ref "A47") (pin "1") (pinfunction "1_1") (pintype "passive"))
      (node (ref "A47") (pin "2") (pinfunction "2_2") (pintype "passive"))
      (node (ref "IC11") (pin "15") (pinfunction "15_15") (pintype "passive"))
    )
    (net (code "72") (name "Net-(A48-Pad1)") (class "Default")
      (node (ref "A48") (pin "1") (pinfunction "1_1") (pintype "passive"))
      (node (ref "A48") (pin "2") (pinfunction "2_2") (pintype "passive"))
      (node (ref "IC11") (pin "16") (pinfunction "16_16") (pintype "passive"))
    )
    (net (code "73") (name "Net-(A49-Pad1)") (class "Default")
      (node (ref "A49") (pin "1") (pinfunction "1_1") (pintype "passive"))
      (node (ref "A49") (pin "2") (pinfunction "2_2") (pintype "passive"))
      (node (ref "IC12") (pin "1") (pinfunction "1_1") (pintype "passive"))
    )
    (net (code "74") (name "Net-(A50-Pad1)") (class "Default")
      (node (ref "A50") (pin "1") (pinfunction "1_1") (pintype "passive"))
      (node (ref "A50") (pin "2") (pinfunction "2_2") (pintype "passive"))
      (node (ref "IC12") (pin "2") (pinfunction "2_2") (pintype "passive"))
    )
    (net (code "75") (name "Net-(A51-Pad1)") (class "Default")
      (node (ref "A51") (pin "1") (pinfunction "1_1") (pintype "passive"))
      (node (ref "A51") (pin "2") (pinfunction "2_2") (pintype "passive"))
      (node (ref "IC12") (pin "3") (pinfunction "3_3") (pintype "passive"))
    )
    (net (code "76") (name "Net-(A52-Pad1)") (class "Default")
      (node (ref "A52") (pin "1") (pinfunction "1_1") (pintype "passive"))
      (node (ref "A52") (pin "2") (pinfunction "2_2") (pintype "passive"))
      (node (ref "IC12") (pin "4") (pinfunction "4_4") (pintype "passive"))
    )
    (net (code "77") (name "Net-(A53-Pad1)") (class "Default")
      (node (ref "A53") (pin "1") (pinfunction "1_1") (pintype "passive"))
      (node (ref "A53") (pin "2") (pinfunction "2_2") (pintype "passive"))
      (node (ref "IC12") (pin "5") (pinfunction "5_5") (pintype "passive"))
    )
    (net (code "78") (name "Net-(A54-Pad1)") (class "Default")
      (node (ref "A54") (pin "1") (pinfunction "1_1") (pintype "passive"))
      (node (ref "A54") (pin "2") (pinfunction "2_2") (pintype "passive"))
      (node (ref "IC12") (pin "6") (pinfunction "6_6") (pintype "passive"))
    )
    (net (code "79") (name "Net-(A55-Pad1)") (class "Default")
      (node (ref "A55") (pin "1") (pinfunction "1_1") (pintype "passive"))
      (node (ref "A55") (pin "2") (pinfunction "2_2") (pintype "passive"))
      (node (ref "IC12") (pin "7") (pinfunction "7_7") (pintype "passive"))
    )
    (net (code "80") (name "Net-(A56-Pad1)") (class "Default")
      (node (ref "A56") (pin "1") (pinfunction "1_1") (pintype "passive"))
      (node (ref "A56") (pin "2") (pinfunction "2_2") (pintype "passive"))
      (node (ref "IC12") (pin "8") (pinfunction "8_8") (pintype "passive"))
    )
    (net (code "81") (name "Net-(A57-Pad1)") (class "Default")
      (node (ref "A57") (pin "1") (pinfunction "1_1") (pintype "passive"))
      (node (ref "A57") (pin "2") (pinfunction "2_2") (pintype "passive"))
      (node (ref "IC12") (pin "9") (pinfunction "9_9") (pintype "passive"))
    )
    (net (code "82") (name "Net-(A58-Pad1)") (class "Default")
      (node (ref "A58") (pin "1") (pinfunction "1_1") (pintype "passive"))
      (node (ref "A58") (pin "2") (pinfunction "2_2") (pintype "passive"))
      (node (ref "IC12") (pin "10") (pinfunction "10_10") (pintype "passive"))
    )
    (net (code "83") (name "Net-(A59-Pad1)") (class "Default")
      (node (ref "A59") (pin "1") (pinfunction "1_1") (pintype "passive"))
      (node (ref "A59") (pin "2") (pinfunction "2_2") (pintype "passive"))
      (node (ref "IC12") (pin "11") (pinfunction "11_11") (pintype "passive"))
    )
    (net (code "84") (name "Net-(A60-Pad1)") (class "Default")
      (node (ref "A60") (pin "1") (pinfunction "1_1") (pintype "passive"))
      (node (ref "A60") (pin "2") (pinfunction "2_2") (pintype "passive"))
      (node (ref "IC12") (pin "12") (pinfunction "12_12") (pintype "passive"))
    )
    (net (code "85") (name "Net-(A61-Pad1)") (class "Default")
      (node (ref "A61") (pin "1") (pinfunction "1_1") (pintype "passive"))
      (node (ref "A61") (pin "2") (pinfunction "2_2") (pintype "passive"))
      (node (ref "IC12") (pin "13") (pinfunction "13_13") (pintype "passive"))
    )
    (net (code "86") (name "Net-(A62-Pad1)") (class "Default")
      (node (ref "A62") (pin "1") (pinfunction "1_1") (pintype "passive"))
      (node (ref "A62") (pin "2") (pinfunction "2_2") (pintype "passive"))
      (node (ref "IC12") (pin "14") (pinfunction "14_14") (pintype "passive"))
    )
    (net (code "87") (name "Net-(A63-Pad1)") (class "Default")
      (node (ref "A63") (pin "1") (pinfunction "1_1") (pintype "passive"))
      (node (ref "A63") (pin "2") (pinfunction "2_2") (pintype "passive"))
      (node (ref "IC12") (pin "15") (pinfunction "15_15") (pintype "passive"))
    )
    (net (code "88") (name "Net-(A64-Pad1)") (class "Default")
      (node (ref "A64") (pin "1") (pinfunction "1_1") (pintype "passive"))
      (node (ref "A64") (pin "2") (pinfunction "2_2") (pintype "passive"))
      (node (ref "IC12") (pin "16") (pinfunction "16_16") (pintype "passive"))
    )
    (net (code "89") (name "Net-(A65-Pad1)") (class "Default")
      (node (ref "A65") (pin "1") (pinfunction "1_1") (pintype "passive"))
      (node (ref "A65") (pin "2") (pinfunction "2_2") (pintype "passive"))
      (node (ref "IC13") (pin "1") (pinfunction "1_1") (pintype "passive"))
    )
    (net (code "90") (name "Net-(A66-Pad1)") (class "Default")
      (node (ref "A66") (pin "1") (pinfunction "1_1") (pintype "passive"))
      (node (ref "A66") (pin "2") (pinfunction "2_2") (pintype "passive"))
      (node (ref "IC13") (pin "2") (pinfunction "2_2") (pintype "passive"))
    )
    (net (code "91") (name "Net-(A67-Pad1)") (class "Default")
      (node (ref "A67") (pin "1") (pinfunction "1_1") (pintype "passive"))
      (node (ref "A67") (pin "2") (pinfunction "2_2") (pintype "passive"))
      (node (ref "IC13") (pin "3") (pinfunction "3_3") (pintype "passive"))
    )
    (net (code "92") (name "Net-(A68-Pad1)") (class "Default")
      (node (ref "A68") (pin "1") (pinfunction "1_1") (pintype "passive"))
      (node (ref "A68") (pin "2") (pinfunction "2_2") (pintype "passive"))
      (node (ref "IC13") (pin "4") (pinfunction "4_4") (pintype "passive"))
    )
    (net (code "93") (name "Net-(A69-Pad1)") (class "Default")
      (node (ref "A69") (pin "1") (pinfunction "1_1") (pintype "passive"))
      (node (ref "A69") (pin "2") (pinfunction "2_2") (pintype "passive"))
      (node (ref "IC13") (pin "5") (pinfunction "5_5") (pintype "passive"))
    )
    (net (code "94") (name "Net-(A70-Pad1)") (class "Default")
      (node (ref "A70") (pin "1") (pinfunction "1_1") (pintype "passive"))
      (node (ref "A70") (pin "2") (pinfunction "2_2") (pintype "passive"))
      (node (ref "IC13") (pin "6") (pinfunction "6_6") (pintype "passive"))
    )
    (net (code "95") (name "Net-(A71-Pad1)") (class "Default")
      (node (ref "A71") (pin "1") (pinfunction "1_1") (pintype "passive"))
      (node (ref "A71") (pin "2") (pinfunction "2_2") (pintype "passive"))
      (node (ref "IC13") (pin "7") (pinfunction "7_7") (pintype "passive"))
    )
    (net (code "96") (name "Net-(A72-Pad1)") (class "Default")
      (node (ref "A72") (pin "1") (pinfunction "1_1") (pintype "passive"))
      (node (ref "A72") (pin "2") (pinfunction "2_2") (pintype "passive"))
      (node (ref "IC13") (pin "8") (pinfunction "8_8") (pintype "passive"))
    )
    (net (code "97") (name "Net-(A73-Pad1)") (class "Default")
      (node (ref "A73") (pin "1") (pinfunction "1_1") (pintype "passive"))
      (node (ref "A73") (pin "2") (pinfunction "2_2") (pintype "passive"))
      (node (ref "IC13") (pin "9") (pinfunction "9_9") (pintype "passive"))
    )
    (net (code "98") (name "Net-(A74-Pad1)") (class "Default")
      (node (ref "A74") (pin "1") (pinfunction "1_1") (pintype "passive"))
      (node (ref "A74") (pin "2") (pinfunction "2_2") (pintype "passive"))
      (node (ref "IC13") (pin "10") (pinfunction "10_10") (pintype "passive"))
    )
    (net (code "99") (name "Net-(A75-Pad1)") (class "Default")
      (node (ref "A75") (pin "1") (pinfunction "1_1") (pintype "passive"))
      (node (ref "A75") (pin "2") (pinfunction "2_2") (pintype "passive"))
      (node (ref "IC13") (pin "11") (pinfunction "11_11") (pintype "passive"))
    )
    (net (code "100") (name "Net-(A76-Pad1)") (class "Default")
      (node (ref "A76") (pin "1") (pinfunction "1_1") (pintype "passive"))
      (node (ref "A76") (pin "2") (pinfunction "2_2") (pintype "passive"))
      (node (ref "IC13") (pin "12") (pinfunction "12_12") (pintype "passive"))
    )
    (net (code "101") (name "Net-(A77-Pad1)") (class "Default")
      (node (ref "A77") (pin "1") (pinfunction "1_1") (pintype "passive"))
      (node (ref "A77") (pin "2") (pinfunction "2_2") (pintype "passive"))
      (node (ref "IC13") (pin "13") (pinfunction "13_13") (pintype "passive"))
    )
    (net (code "102") (name "Net-(A78-Pad1)") (class "Default")
      (node (ref "A78") (pin "1") (pinfunction "1_1") (pintype "passive"))
      (node (ref "A78") (pin "2") (pinfunction "2_2") (pintype "passive"))
      (node (ref "IC13") (pin "14") (pinfunction "14_14") (pintype "passive"))
    )
    (net (code "103") (name "Net-(A79-Pad1)") (class "Default")
      (node (ref "A79") (pin "1") (pinfunction "1_1") (pintype "passive"))
      (node (ref "A79") (pin "2") (pinfunction "2_2") (pintype "passive"))
      (node (ref "IC13") (pin "15") (pinfunction "15_15") (pintype "passive"))
    )
    (net (code "104") (name "Net-(A80-Pad1)") (class "Default")
      (node (ref "A80") (pin "1") (pinfunction "1_1") (pintype "passive"))
      (node (ref "A80") (pin "2") (pinfunction "2_2") (pintype "passive"))
      (node (ref "IC13") (pin "16") (pinfunction "16_16") (pintype "passive"))
    )
    (net (code "105") (name "Net-(A81-Pad1)") (class "Default")
      (node (ref "A81") (pin "1") (pinfunction "1_1") (pintype "passive"))
      (node (ref "A81") (pin "2") (pinfunction "2_2") (pintype "passive"))
      (node (ref "IC14") (pin "1") (pinfunction "1_1") (pintype "passive"))
    )
    (net (code "106") (name "Net-(A82-Pad1)") (class "Default")
      (node (ref "A82") (pin "1") (pinfunction "1_1") (pintype "passive"))
      (node (ref "A82") (pin "2") (pinfunction "2_2") (pintype "passive"))
      (node (ref "IC14") (pin "2") (pinfunction "2_2") (pintype "passive"))
    )
    (net (code "107") (name "Net-(A83-Pad1)") (class "Default")
      (node (ref "A83") (pin "1") (pinfunction "1_1") (pintype "passive"))
      (node (ref "A83") (pin "2") (pinfunction "2_2") (pintype "passive"))
      (node (ref "IC14") (pin "3") (pinfunction "3_3") (pintype "passive"))
    )
    (net (code "108") (name "Net-(A84-Pad1)") (class "Default")
      (node (ref "A84") (pin "1") (pinfunction "1_1") (pintype "passive"))
      (node (ref "A84") (pin "2") (pinfunction "2_2") (pintype "passive"))
      (node (ref "IC14") (pin "4") (pinfunction "4_4") (pintype "passive"))
    )
    (net (code "109") (name "Net-(A85-Pad1)") (class "Default")
      (node (ref "A85") (pin "1") (pinfunction "1_1") (pintype "passive"))
      (node (ref "A85") (pin "2") (pinfunction "2_2") (pintype "passive"))
      (node (ref "IC14") (pin "5") (pinfunction "5_5") (pintype "passive"))
    )
    (net (code "110") (name "Net-(A86-Pad1)") (class "Default")
      (node (ref "A86") (pin "1") (pinfunction "1_1") (pintype "passive"))
      (node (ref "A86") (pin "2") (pinfunction "2_2") (pintype "passive"))
      (node (ref "IC14") (pin "6") (pinfunction "6_6") (pintype "passive"))
    )
    (net (code "111") (name "Net-(A87-Pad1)") (class "Default")
      (node (ref "A87") (pin "1") (pinfunction "1_1") (pintype "passive"))
      (node (ref "A87") (pin "2") (pinfunction "2_2") (pintype "passive"))
      (node (ref "IC14") (pin "7") (pinfunction "7_7") (pintype "passive"))
    )
    (net (code "112") (name "Net-(A88-Pad1)") (class "Default")
      (node (ref "A88") (pin "1") (pinfunction "1_1") (pintype "passive"))
      (node (ref "A88") (pin "2") (pinfunction "2_2") (pintype "passive"))
      (node (ref "IC14") (pin "8") (pinfunction "8_8") (pintype "passive"))
    )
    (net (code "113") (name "Net-(A89-Pad1)") (class "Default")
      (node (ref "A89") (pin "1") (pinfunction "1_1") (pintype "passive"))
      (node (ref "A89") (pin "2") (pinfunction "2_2") (pintype "passive"))
      (node (ref "IC14") (pin "9") (pinfunction "9_9") (pintype "passive"))
    )
    (net (code "114") (name "Net-(A90-Pad1)") (class "Default")
      (node (ref "A90") (pin "1") (pinfunction "1_1") (pintype "passive"))
      (node (ref "A90") (pin "2") (pinfunction "2_2") (pintype "passive"))
      (node (ref "IC14") (pin "10") (pinfunction "10_10") (pintype "passive"))
    )
    (net (code "115") (name "Net-(A91-Pad1)") (class "Default")
      (node (ref "A91") (pin "1") (pinfunction "1_1") (pintype "passive"))
      (node (ref "A91") (pin "2") (pinfunction "2_2") (pintype "passive"))
      (node (ref "IC14") (pin "11") (pinfunction "11_11") (pintype "passive"))
    )
    (net (code "116") (name "Net-(A92-Pad1)") (class "Default")
      (node (ref "A92") (pin "1") (pinfunction "1_1") (pintype "passive"))
      (node (ref "A92") (pin "2") (pinfunction "2_2") (pintype "passive"))
      (node (ref "IC14") (pin "12") (pinfunction "12_12") (pintype "passive"))
    )
    (net (code "117") (name "Net-(A93-Pad1)") (class "Default")
      (node (ref "A93") (pin "1") (pinfunction "1_1") (pintype "passive"))
      (node (ref "A93") (pin "2") (pinfunction "2_2") (pintype "passive"))
      (node (ref "IC14") (pin "13") (pinfunction "13_13") (pintype "passive"))
    )
    (net (code "118") (name "Net-(A94-Pad1)") (class "Default")
      (node (ref "A94") (pin "1") (pinfunction "1_1") (pintype "passive"))
      (node (ref "A94") (pin "2") (pinfunction "2_2") (pintype "passive"))
      (node (ref "IC14") (pin "14") (pinfunction "14_14") (pintype "passive"))
    )
    (net (code "119") (name "Net-(A95-Pad1)") (class "Default")
      (node (ref "A95") (pin "1") (pinfunction "1_1") (pintype "passive"))
      (node (ref "A95") (pin "2") (pinfunction "2_2") (pintype "passive"))
      (node (ref "IC14") (pin "15") (pinfunction "15_15") (pintype "passive"))
    )
    (net (code "120") (name "Net-(A96-Pad1)") (class "Default")
      (node (ref "A96") (pin "1") (pinfunction "1_1") (pintype "passive"))
      (node (ref "A96") (pin "2") (pinfunction "2_2") (pintype "passive"))
      (node (ref "IC14") (pin "16") (pinfunction "16_16") (pintype "passive"))
    )
    (net (code "121") (name "Net-(A97-Pad1)") (class "Default")
      (node (ref "A97") (pin "1") (pinfunction "1_1") (pintype "passive"))
      (node (ref "A97") (pin "2") (pinfunction "2_2") (pintype "passive"))
      (node (ref "IC15") (pin "1") (pinfunction "1_1") (pintype "passive"))
    )
    (net (code "122") (name "Net-(A98-Pad1)") (class "Default")
      (node (ref "A98") (pin "1") (pinfunction "1_1") (pintype "passive"))
      (node (ref "A98") (pin "2") (pinfunction "2_2") (pintype "passive"))
      (node (ref "IC15") (pin "2") (pinfunction "2_2") (pintype "passive"))
    )
    (net (code "123") (name "Net-(A99-Pad1)") (class "Default")
      (node (ref "A99") (pin "1") (pinfunction "1_1") (pintype "passive"))
      (node (ref "A99") (pin "2") (pinfunction "2_2") (pintype "passive"))
      (node (ref "IC15") (pin "3") (pinfunction "3_3") (pintype "passive"))
    )
    (net (code "124") (name "Net-(A100-Pad1)") (class "Default")
      (node (ref "A100") (pin "1") (pinfunction "1_1") (pintype "passive"))
      (node (ref "A100") (pin "2") (pinfunction "2_2") (pintype "passive"))
      (node (ref "IC15") (pin "4") (pinfunction "4_4") (pintype "passive"))
    )
    (net (code "125") (name "Net-(A101-Pad1)") (class "Default")
      (node (ref "A101") (pin "1") (pinfunction "1_1") (pintype "passive"))
      (node (ref "A101") (pin "2") (pinfunction "2_2") (pintype "passive"))
      (node (ref "IC15") (pin "5") (pinfunction "5_5") (pintype "passive"))
    )
    (net (code "126") (name "Net-(A102-Pad1)") (class "Default")
      (node (ref "A102") (pin "1") (pinfunction "1_1") (pintype "passive"))
      (node (ref "A102") (pin "2") (pinfunction "2_2") (pintype "passive"))
      (node (ref "IC15") (pin "6") (pinfunction "6_6") (pintype "passive"))
    )
    (net (code "127") (name "Net-(A103-Pad1)") (class "Default")
      (node (ref "A103") (pin "1") (pinfunction "1_1") (pintype "passive"))
      (node (ref "A103") (pin "2") (pinfunction "2_2") (pintype "passive"))
      (node (ref "IC15") (pin "7") (pinfunction "7_7") (pintype "passive"))
    )
    (net (code "128") (name "Net-(A104-Pad1)") (class "Default")
      (node (ref "A104") (pin "1") (pinfunction "1_1") (pintype "passive"))
      (node (ref "A104") (pin "2") (pinfunction "2_2") (pintype "passive"))
      (node (ref "IC15") (pin "8") (pinfunction "8_8") (pintype "passive"))
    )
    (net (code "129") (name "Net-(A105-Pad1)") (class "Default")
      (node (ref "A105") (pin "1") (pinfunction "1_1") (pintype "passive"))
      (node (ref "A105") (pin "2") (pinfunction "2_2") (pintype "passive"))
      (node (ref "IC15") (pin "9") (pinfunction "9_9") (pintype "passive"))
    )
    (net (code "130") (name "Net-(A106-Pad1)") (class "Default")
      (node (ref "A106") (pin "1") (pinfunction "1_1") (pintype "passive"))
      (node (ref "A106") (pin "2") (pinfunction "2_2") (pintype "passive"))
      (node (ref "IC15") (pin "10") (pinfunction "10_10") (pintype "passive"))
    )
    (net (code "131") (name "Net-(A107-Pad1)") (class "Default")
      (node (ref "A107") (pin "1") (pinfunction "1_1") (pintype "passive"))
      (node (ref "A107") (pin "2") (pinfunction "2_2") (pintype "passive"))
      (node (ref "IC15") (pin "11") (pinfunction "11_11") (pintype "passive"))
    )
    (net (code "132") (name "Net-(A108-Pad1)") (class "Default")
      (node (ref "A108") (pin "1") (pinfunction "1_1") (pintype "passive"))
      (node (ref "A108") (pin "2") (pinfunction "2_2") (pintype "passive"))
      (node (ref "IC15") (pin "12") (pinfunction "12_12") (pintype "passive"))
    )
    (net (code "133") (name "Net-(A109-Pad1)") (class "Default")
      (node (ref "A109") (pin "1") (pinfunction "1_1") (pintype "passive"))
      (node (ref "A109") (pin "2") (pinfunction "2_2") (pintype "passive"))
      (node (ref "IC15") (pin "13") (pinfunction "13_13") (pintype "passive"))
    )
    (net (code "134") (name "Net-(A110-Pad1)") (class "Default")
      (node (ref "A110") (pin "1") (pinfunction "1_1") (pintype "passive"))
      (node (ref "A110") (pin "2") (pinfunction "2_2") (pintype "passive"))
      (node (ref "IC15") (pin "14") (pinfunction "14_14") (pintype "passive"))
    )
    (net (code "135") (name "Net-(A111-Pad1)") (class "Default")
      (node (ref "A111") (pin "1") (pinfunction "1_1") (pintype "passive"))
      (node (ref "A111") (pin "2") (pinfunction "2_2") (pintype "passive"))
      (node (ref "IC15") (pin "15") (pinfunction "15_15") (pintype "passive"))
    )
    (net (code "136") (name "Net-(A112-Pad1)") (class "Default")
      (node (ref "A112") (pin "1") (pinfunction "1_1") (pintype "passive"))
      (node (ref "A112") (pin "2") (pinfunction "2_2") (pintype "passive"))
      (node (ref "IC15") (pin "16") (pinfunction "16_16") (pintype "passive"))
    )
    (net (code "137") (name "Net-(A113-Pad1)") (class "Default")
      (node (ref "A113") (pin "1") (pinfunction "1_1") (pintype "passive"))
      (node (ref "A113") (pin "2") (pinfunction "2_2") (pintype "passive"))
      (node (ref "IC16") (pin "1") (pinfunction "1_1") (pintype "passive"))
    )
    (net (code "138") (name "Net-(A114-Pad1)") (class "Default")
      (node (ref "A114") (pin "1") (pinfunction "1_1") (pintype "passive"))
      (node (ref "A114") (pin "2") (pinfunction "2_2") (pintype "passive"))
      (node (ref "IC16") (pin "2") (pinfunction "2_2") (pintype "passive"))
    )
    (net (code "139") (name "Net-(A115-Pad1)") (class "Default")
      (node (ref "A115") (pin "1") (pinfunction "1_1") (pintype "passive"))
      (node (ref "A115") (pin "2") (pinfunction "2_2") (pintype "passive"))
      (node (ref "IC16") (pin "3") (pinfunction "3_3") (pintype "passive"))
    )
    (net (code "140") (name "Net-(A116-Pad1)") (class "Default")
      (node (ref "A116") (pin "1") (pinfunction "1_1") (pintype "passive"))
      (node (ref "A116") (pin "2") (pinfunction "2_2") (pintype "passive"))
      (node (ref "IC16") (pin "4") (pinfunction "4_4") (pintype "passive"))
    )
    (net (code "141") (name "Net-(A117-Pad1)") (class "Default")
      (node (ref "A117") (pin "1") (pinfunction "1_1") (pintype "passive"))
      (node (ref "A117") (pin "2") (pinfunction "2_2") (pintype "passive"))
      (node (ref "IC16") (pin "5") (pinfunction "5_5") (pintype "passive"))
    )
    (net (code "142") (name "Net-(A118-Pad1)") (class "Default")
      (node (ref "A118") (pin "1") (pinfunction "1_1") (pintype "passive"))
      (node (ref "A118") (pin "2") (pinfunction "2_2") (pintype "passive"))
      (node (ref "IC16") (pin "6") (pinfunction "6_6") (pintype "passive"))
    )
    (net (code "143") (name "Net-(A119-Pad1)") (class "Default")
      (node (ref "A119") (pin "1") (pinfunction "1_1") (pintype "passive"))
      (node (ref "A119") (pin "2") (pinfunction "2_2") (pintype "passive"))
      (node (ref "IC16") (pin "7") (pinfunction "7_7") (pintype "passive"))
    )
    (net (code "144") (name "Net-(A120-Pad1)") (class "Default")
      (node (ref "A120") (pin "1") (pinfunction "1_1") (pintype "passive"))
      (node (ref "A120") (pin "2") (pinfunction "2_2") (pintype "passive"))
      (node (ref "IC16") (pin "8") (pinfunction "8_8") (pintype "passive"))
    )
    (net (code "145") (name "Net-(A121-Pad1)") (class "Default")
      (node (ref "A121") (pin "1") (pinfunction "1_1") (pintype "passive"))
      (node (ref "A121") (pin "2") (pinfunction "2_2") (pintype "passive"))
      (node (ref "IC16") (pin "9") (pinfunction "9_9") (pintype "passive"))
    )
    (net (code "146") (name "Net-(A122-Pad1)") (class "Default")
      (node (ref "A122") (pin "1") (pinfunction "1_1") (pintype "passive"))
      (node (ref "A122") (pin "2") (pinfunction "2_2") (pintype "passive"))
      (node (ref "IC16") (pin "10") (pinfunction "10_10") (pintype "passive"))
    )
    (net (code "147") (name "Net-(A123-Pad1)") (class "Default")
      (node (ref "A123") (pin "1") (pinfunction "1_1") (pintype "passive"))
      (node (ref "A123") (pin "2") (pinfunction "2_2") (pintype "passive"))
      (node (ref "IC16") (pin "11") (pinfunction "11_11") (pintype "passive"))
    )
    (net (code "148") (name "Net-(A124-Pad1)") (class "Default")
      (node (ref "A124") (pin "1") (pinfunction "1_1") (pintype "passive"))
      (node (ref "A124") (pin "2") (pinfunction "2_2") (pintype "passive"))
      (node (ref "IC16") (pin "12") (pinfunction "12_12") (pintype "passive"))
    )
    (net (code "149") (name "Net-(A125-Pad1)") (class "Default")
      (node (ref "A125") (pin "1") (pinfunction "1_1") (pintype "passive"))
      (node (ref "A125") (pin "2") (pinfunction "2_2") (pintype "passive"))
      (node (ref "IC16") (pin "13") (pinfunction "13_13") (pintype "passive"))
    )
    (net (code "150") (name "Net-(A126-Pad1)") (class "Default")
      (node (ref "A126") (pin "1") (pinfunction "1_1") (pintype "passive"))
      (node (ref "A126") (pin "2") (pinfunction "2_2") (pintype "passive"))
      (node (ref "IC16") (pin "14") (pinfunction "14_14") (pintype "passive"))
    )
    (net (code "151") (name "Net-(A127-Pad1)") (class "Default")
      (node (ref "A127") (pin "1") (pinfunction "1_1") (pintype "passive"))
      (node (ref "A127") (pin "2") (pinfunction "2_2") (pintype "passive"))
      (node (ref "IC16") (pin "15") (pinfunction "15_15") (pintype "passive"))
    )
    (net (code "152") (name "Net-(A128-Pad1)") (class "Default")
      (node (ref "A128") (pin "1") (pinfunction "1_1") (pintype "passive"))
      (node (ref "A128") (pin "2") (pinfunction "2_2") (pintype "passive"))
      (node (ref "IC16") (pin "16") (pinfunction "16_16") (pintype "passive"))
    )
    (net (code "153") (name "Net-(A129-Pad1)") (class "Default")
      (node (ref "A129") (pin "1") (pinfunction "1_1") (pintype "passive"))
      (node (ref "A129") (pin "2") (pinfunction "2_2") (pintype "passive"))
      (node (ref "IC17") (pin "1") (pinfunction "1_1") (pintype "passive"))
    )
    (net (code "154") (name "Net-(A130-Pad1)") (class "Default")
      (node (ref "A130") (pin "1") (pinfunction "1_1") (pintype "passive"))
      (node (ref "A130") (pin "2") (pinfunction "2_2") (pintype "passive"))
      (node (ref "IC17") (pin "2") (pinfunction "2_2") (pintype "passive"))
    )
    (net (code "155") (name "Net-(A131-Pad1)") (class "Default")
      (node (ref "A131") (pin "1") (pinfunction "1_1") (pintype "passive"))
      (node (ref "A131") (pin "2") (pinfunction "2_2") (pintype "passive"))
      (node (ref "IC17") (pin "3") (pinfunction "3_3") (pintype "passive"))
    )
    (net (code "156") (name "Net-(A132-Pad1)") (class "Default")
      (node (ref "A132") (pin "1") (pinfunction "1_1") (pintype "passive"))
      (node (ref "A132") (pin "2") (pinfunction "2_2") (pintype "passive"))
      (node (ref "IC17") (pin "4") (pinfunction "4_4") (pintype "passive"))
    )
    (net (code "157") (name "Net-(A133-Pad1)") (class "Default")
      (node (ref "A133") (pin "1") (pinfunction "1_1") (pintype "passive"))
      (node (ref "A133") (pin "2") (pinfunction "2_2") (pintype "passive"))
      (node (ref "IC17") (pin "5") (pinfunction "5_5") (pintype "passive"))
    )
    (net (code "158") (name "Net-(A134-Pad1)") (class "Default")
      (node (ref "A134") (pin "1") (pinfunction "1_1") (pintype "passive"))
      (node (ref "A134") (pin "2") (pinfunction "2_2") (pintype "passive"))
      (node (ref "IC17") (pin "6") (pinfunction "6_6") (pintype "passive"))
    )
    (net (code "159") (name "Net-(A135-Pad1)") (class "Default")
      (node (ref "A135") (pin "1") (pinfunction "1_1") (pintype "passive"))
      (node (ref "A135") (pin "2") (pinfunction "2_2") (pintype "passive"))
      (node (ref "IC17") (pin "7") (pinfunction "7_7") (pintype "passive"))
    )
    (net (code "160") (name "Net-(A136-Pad1)") (class "Default")
      (node (ref "A136") (pin "1") (pinfunction "1_1") (pintype "passive"))
      (node (ref "A136") (pin "2") (pinfunction "2_2") (pintype "passive"))
      (node (ref "IC17") (pin "8") (pinfunction "8_8") (pintype "passive"))
    )
    (net (code "161") (name "Net-(A137-Pad1)") (class "Default")
      (node (ref "A137") (pin "1") (pinfunction "1_1") (pintype "passive"))
      (node (ref "A137") (pin "2") (pinfunction "2_2") (pintype "passive"))
      (node (ref "IC17") (pin "9") (pinfunction "9_9") (pintype "passive"))
    )
    (net (code "162") (name "Net-(A138-Pad1)") (class "Default")
      (node (ref "A138") (pin "1") (pinfunction "1_1") (pintype "passive"))
      (node (ref "A138") (pin "2") (pinfunction "2_2") (pintype "passive"))
      (node (ref "IC17") (pin "10") (pinfunction "10_10") (pintype "passive"))
    )
    (net (code "163") (name "Net-(A139-Pad1)") (class "Default")
      (node (ref "A139") (pin "1") (pinfunction "1_1") (pintype "passive"))
      (node (ref "A139") (pin "2") (pinfunction "2_2") (pintype "passive"))
      (node (ref "IC17") (pin "11") (pinfunction "11_11") (pintype "passive"))
    )
    (net (code "164") (name "Net-(A140-Pad1)") (class "Default")
      (node (ref "A140") (pin "1") (pinfunction "1_1") (pintype "passive"))
      (node (ref "A140") (pin "2") (pinfunction "2_2") (pintype "passive"))
      (node (ref "IC17") (pin "12") (pinfunction "12_12") (pintype "passive"))
    )
    (net (code "165") (name "Net-(A141-Pad1)") (class "Default")
      (node (ref "A141") (pin "1") (pinfunction "1_1") (pintype "passive"))
      (node (ref "A141") (pin "2") (pinfunction "2_2") (pintype "passive"))
      (node (ref "IC17") (pin "13") (pinfunction "13_13") (pintype "passive"))
    )
    (net (code "166") (name "Net-(A142-Pad1)") (class "Default")
      (node (ref "A142") (pin "1") (pinfunction "1_1") (pintype "passive"))
      (node (ref "A142") (pin "2") (pinfunction "2_2") (pintype "passive"))
      (node (ref "IC17") (pin "14") (pinfunction "14_14") (pintype "passive"))
    )
    (net (code "167") (name "Net-(A143-Pad1)") (class "Default")
      (node (ref "A143") (pin "1") (pinfunction "1_1") (pintype "passive"))
      (node (ref "A143") (pin "2") (pinfunction "2_2") (pintype "passive"))
      (node (ref "IC17") (pin "15") (pinfunction "15_15") (pintype "passive"))
    )
    (net (code "168") (name "Net-(A144-Pad1)") (class "Default")
      (node (ref "A144") (pin "1") (pinfunction "1_1") (pintype "passive"))
      (node (ref "A144") (pin "2") (pinfunction "2_2") (pintype "passive"))
      (node (ref "IC17") (pin "16") (pinfunction "16_16") (pintype "passive"))
    )
    (net (code "169") (name "Net-(A145-Pad1)") (class "Default")
      (node (ref "A145") (pin "1") (pinfunction "1_1") (pintype "passive"))
      (node (ref "A145") (pin "2") (pinfunction "2_2") (pintype "passive"))
      (node (ref "IC18") (pin "1") (pinfunction "1_1") (pintype "passive"))
    )
    (net (code "170") (name "Net-(A146-Pad1)") (class "Default")
      (node (ref "A146") (pin "1") (pinfunction "1_1") (pintype "passive"))
      (node (ref "A146") (pin "2") (pinfunction "2_2") (pintype "passive"))
      (node (ref "IC18") (pin "2") (pinfunction "2_2") (pintype "passive"))
    )
    (net (code "171") (name "Net-(A147-Pad1)") (class "Default")
      (node (ref "A147") (pin "1") (pinfunction "1_1") (pintype "passive"))
      (node (ref "A147") (pin "2") (pinfunction "2_2") (pintype "passive"))
      (node (ref "IC18") (pin "3") (pinfunction "3_3") (pintype "passive"))
    )
    (net (code "172") (name "Net-(A148-Pad1)") (class "Default")
      (node (ref "A148") (pin "1") (pinfunction "1_1") (pintype "passive"))
      (node (ref "A148") (pin "2") (pinfunction "2_2") (pintype "passive"))
      (node (ref "IC18") (pin "4") (pinfunction "4_4") (pintype "passive"))
    )
    (net (code "173") (name "Net-(A149-Pad1)") (class "Default")
      (node (ref "A149") (pin "1") (pinfunction "1_1") (pintype "passive"))
      (node (ref "A149") (pin "2") (pinfunction "2_2") (pintype "passive"))
      (node (ref "IC18") (pin "5") (pinfunction "5_5") (pintype "passive"))
    )
    (net (code "174") (name "Net-(A150-Pad1)") (class "Default")
      (node (ref "A150") (pin "1") (pinfunction "1_1") (pintype "passive"))
      (node (ref "A150") (pin "2") (pinfunction "2_2") (pintype "passive"))
      (node (ref "IC18") (pin "6") (pinfunction "6_6") (pintype "passive"))
    )
    (net (code "175") (name "Net-(A151-Pad1)") (class "Default")
      (node (ref "A151") (pin "1") (pinfunction "1_1") (pintype "passive"))
      (node (ref "A151") (pin "2") (pinfunction "2_2") (pintype "passive"))
      (node (ref "IC18") (pin "7") (pinfunction "7_7") (pintype "passive"))
    )
    (net (code "176") (name "Net-(A152-Pad1)") (class "Default")
      (node (ref "A152") (pin "1") (pinfunction "1_1") (pintype "passive"))
      (node (ref "A152") (pin "2") (pinfunction "2_2") (pintype "passive"))
      (node (ref "IC18") (pin "8") (pinfunction "8_8") (pintype "passive"))
    )
    (net (code "177") (name "Net-(A153-Pad1)") (class "Default")
      (node (ref "A153") (pin "1") (pinfunction "1_1") (pintype "passive"))
      (node (ref "A153") (pin "2") (pinfunction "2_2") (pintype "passive"))
      (node (ref "IC18") (pin "9") (pinfunction "9_9") (pintype "passive"))
    )
    (net (code "178") (name "Net-(A154-Pad1)") (class "Default")
      (node (ref "A154") (pin "1") (pinfunction "1_1") (pintype "passive"))
      (node (ref "A154") (pin "2") (pinfunction "2_2") (pintype "passive"))
      (node (ref "IC18") (pin "10") (pinfunction "10_10") (pintype "passive"))
    )
    (net (code "179") (name "Net-(A155-Pad1)") (class "Default")
      (node (ref "A155") (pin "1") (pinfunction "1_1") (pintype "passive"))
      (node (ref "A155") (pin "2") (pinfunction "2_2") (pintype "passive"))
      (node (ref "IC18") (pin "11") (pinfunction "11_11") (pintype "passive"))
    )
    (net (code "180") (name "Net-(A156-Pad1)") (class "Default")
      (node (ref "A156") (pin "1") (pinfunction "1_1") (pintype "passive"))
      (node (ref "A156") (pin "2") (pinfunction "2_2") (pintype "passive"))
      (node (ref "IC18") (pin "12") (pinfunction "12_12") (pintype "passive"))
    )
    (net (code "181") (name "Net-(A157-Pad1)") (class "Default")
      (node (ref "A157") (pin "1") (pinfunction "1_1") (pintype "passive"))
      (node (ref "A157") (pin "2") (pinfunction "2_2") (pintype "passive"))
      (node (ref "IC18") (pin "13") (pinfunction "13_13") (pintype "passive"))
    )
    (net (code "182") (name "Net-(A158-Pad1)") (class "Default")
      (node (ref "A158") (pin "1") (pinfunction "1_1") (pintype "passive"))
      (node (ref "A158") (pin "2") (pinfunction "2_2") (pintype "passive"))
      (node (ref "IC18") (pin "14") (pinfunction "14_14") (pintype "passive"))
    )
    (net (code "183") (name "Net-(A159-Pad1)") (class "Default")
      (node (ref "A159") (pin "1") (pinfunction "1_1") (pintype "passive"))
      (node (ref "A159") (pin "2") (pinfunction "2_2") (pintype "passive"))
      (node (ref "IC18") (pin "15") (pinfunction "15_15") (pintype "passive"))
    )
    (net (code "184") (name "Net-(A160-Pad1)") (class "Default")
      (node (ref "A160") (pin "1") (pinfunction "1_1") (pintype "passive"))
      (node (ref "A160") (pin "2") (pinfunction "2_2") (pintype "passive"))
      (node (ref "IC18") (pin "16") (pinfunction "16_16") (pintype "passive"))
    )
    (net (code "185") (name "Net-(A161-Pad1)") (class "Default")
      (node (ref "A161") (pin "1") (pinfunction "1_1") (pintype "passive"))
      (node (ref "A161") (pin "2") (pinfunction "2_2") (pintype "passive"))
      (node (ref "IC19") (pin "1") (pinfunction "1_1") (pintype "passive"))
    )
    (net (code "186") (name "Net-(A162-Pad1)") (class "Default")
      (node (ref "A162") (pin "1") (pinfunction "1_1") (pintype "passive"))
      (node (ref "A162") (pin "2") (pinfunction "2_2") (pintype "passive"))
      (node (ref "IC19") (pin "2") (pinfunction "2_2") (pintype "passive"))
    )
    (net (code "187") (name "Net-(A163-Pad1)") (class "Default")
      (node (ref "A163") (pin "1") (pinfunction "1_1") (pintype "passive"))
      (node (ref "A163") (pin "2") (pinfunction "2_2") (pintype "passive"))
      (node (ref "IC19") (pin "3") (pinfunction "3_3") (pintype "passive"))
    )
    (net (code "188") (name "Net-(A164-Pad1)") (class "Default")
      (node (ref "A164") (pin "1") (pinfunction "1_1") (pintype "passive"))
      (node (ref "A164") (pin "2") (pinfunction "2_2") (pintype "passive"))
      (node (ref "IC19") (pin "4") (pinfunction "4_4") (pintype "passive"))
    )
    (net (code "189") (name "Net-(A165-Pad1)") (class "Default")
      (node (ref "A165") (pin "1") (pinfunction "1_1") (pintype "passive"))
      (node (ref "A165") (pin "2") (pinfunction "2_2") (pintype "passive"))
      (node (ref "IC19") (pin "5") (pinfunction "5_5") (pintype "passive"))
    )
    (net (code "190") (name "Net-(A166-Pad1)") (class "Default")
      (node (ref "A166") (pin "1") (pinfunction "1_1") (pintype "passive"))
      (node (ref "A166") (pin "2") (pinfunction "2_2") (pintype "passive"))
      (node (ref "IC19") (pin "6") (pinfunction "6_6") (pintype "passive"))
    )
    (net (code "191") (name "Net-(A167-Pad1)") (class "Default")
      (node (ref "A167") (pin "1") (pinfunction "1_1") (pintype "passive"))
      (node (ref "A167") (pin "2") (pinfunction "2_2") (pintype "passive"))
      (node (ref "IC19") (pin "7") (pinfunction "7_7") (pintype "passive"))
    )
    (net (code "192") (name "Net-(A168-Pad1)") (class "Default")
      (node (ref "A168") (pin "1") (pinfunction "1_1") (pintype "passive"))
      (node (ref "A168") (pin "2") (pinfunction "2_2") (pintype "passive"))
      (node (ref "IC19") (pin "8") (pinfunction "8_8") (pintype "passive"))
    )
    (net (code "193") (name "Net-(A169-Pad1)") (class "Default")
      (node (ref "A169") (pin "1") (pinfunction "1_1") (pintype "passive"))
      (node (ref "A169") (pin "2") (pinfunction "2_2") (pintype "passive"))
      (node (ref "IC19") (pin "9") (pinfunction "9_9") (pintype "passive"))
    )
    (net (code "194") (name "Net-(A170-Pad1)") (class "Default")
      (node (ref "A170") (pin "1") (pinfunction "1_1") (pintype "passive"))
      (node (ref "A170") (pin "2") (pinfunction "2_2") (pintype "passive"))
      (node (ref "IC19") (pin "10") (pinfunction "10_10") (pintype "passive"))
    )
    (net (code "195") (name "Net-(A171-Pad1)") (class "Default")
      (node (ref "A171") (pin "1") (pinfunction "1_1") (pintype "passive"))
      (node (ref "A171") (pin "2") (pinfunction "2_2") (pintype "passive"))
      (node (ref "IC19") (pin "11") (pinfunction "11_11") (pintype "passive"))
    )
    (net (code "196") (name "Net-(A172-Pad1)") (class "Default")
      (node (ref "A172") (pin "1") (pinfunction "1_1") (pintype "passive"))
      (node (ref "A172") (pin "2") (pinfunction "2_2") (pintype "passive"))
      (node (ref "IC19") (pin "12") (pinfunction "12_12") (pintype "passive"))
    )
    (net (code "197") (name "Net-(A173-Pad1)") (class "Default")
      (node (ref "A173") (pin "1") (pinfunction "1_1") (pintype "passive"))
      (node (ref "A173") (pin "2") (pinfunction "2_2") (pintype "passive"))
      (node (ref "IC19") (pin "13") (pinfunction "13_13") (pintype "passive"))
    )
    (net (code "198") (name "Net-(A174-Pad1)") (class "Default")
      (node (ref "A174") (pin "1") (pinfunction "1_1") (pintype "passive"))
      (node (ref "A174") (pin "2") (pinfunction "2_2") (pintype "passive"))
      (node (ref "IC19") (pin "14") (pinfunction "14_14") (pintype "passive"))
    )
    (net (code "199") (name "Net-(A175-Pad1)") (class "Default")
      (node (ref "A175") (pin "1") (pinfunction "1_1") (pintype "passive"))
      (node (ref "A175") (pin "2") (pinfunction "2_2") (pintype "passive"))
      (node (ref "IC19") (pin "15") (pinfunction "15_15") (pintype "passive"))
    )
    (net (code "200") (name "Net-(A176-Pad1)") (class "Default")
      (node (ref "A176") (pin "1") (pinfunction "1_1") (pintype "passive"))
      (node (ref "A176") (pin "2") (pinfunction "2_2") (pintype "passive"))
      (node (ref "IC19") (pin "16") (pinfunction "16_16") (pintype "passive"))
    )
    (net (code "201") (name "Net-(A177-Pad1)") (class "Default")
      (node (ref "A177") (pin "1") (pinfunction "1_1") (pintype "passive"))
      (node (ref "A177") (pin "2") (pinfunction "2_2") (pintype "passive"))
      (node (ref "IC20") (pin "1") (pinfunction "1_1") (pintype "passive"))
    )
    (net (code "202") (name "Net-(A178-Pad1)") (class "Default")
      (node (ref "A178") (pin "1") (pinfunction "1_1") (pintype "passive"))
      (node (ref "A178") (pin "2") (pinfunction "2_2") (pintype "passive"))
      (node (ref "IC20") (pin "2") (pinfunction "2_2") (pintype "passive"))
    )
    (net (code "203") (name "Net-(A179-Pad1)") (class "Default")
      (node (ref "A179") (pin "1") (pinfunction "1_1") (pintype "passive"))
      (node (ref "A179") (pin "2") (pinfunction "2_2") (pintype "passive"))
      (node (ref "IC20") (pin "3") (pinfunction "3_3") (pintype "passive"))
    )
    (net (code "204") (name "Net-(A180-Pad1)") (class "Default")
      (node (ref "A180") (pin "1") (pinfunction "1_1") (pintype "passive"))
      (node (ref "A180") (pin "2") (pinfunction "2_2") (pintype "passive"))
      (node (ref "IC20") (pin "4") (pinfunction "4_4") (pintype "passive"))
    )
    (net (code "205") (name "Net-(A181-Pad1)") (class "Default")
      (node (ref "A181") (pin "1") (pinfunction "1_1") (pintype "passive"))
      (node (ref "A181") (pin "2") (pinfunction "2_2") (pintype "passive"))
      (node (ref "IC20") (pin "5") (pinfunction "5_5") (pintype "passive"))
    )
    (net (code "206") (name "Net-(A182-Pad1)") (class "Default")
      (node (ref "A182") (pin "1") (pinfunction "1_1") (pintype "passive"))
      (node (ref "A182") (pin "2") (pinfunction "2_2") (pintype "passive"))
      (node (ref "IC20") (pin "6") (pinfunction "6_6") (pintype "passive"))
    )
    (net (code "207") (name "Net-(A183-Pad1)") (class "Default")
      (node (ref "A183") (pin "1") (pinfunction "1_1") (pintype "passive"))
      (node (ref "A183") (pin "2") (pinfunction "2_2") (pintype "passive"))
      (node (ref "IC20") (pin "7") (pinfunction "7_7") (pintype "passive"))
    )
    (net (code "208") (name "Net-(A184-Pad1)") (class "Default")
      (node (ref "A184") (pin "1") (pinfunction "1_1") (pintype "passive"))
      (node (ref "A184") (pin "2") (pinfunction "2_2") (pintype "passive"))
      (node (ref "IC20") (pin "8") (pinfunction "8_8") (pintype "passive"))
    )
    (net (code "209") (name "Net-(A185-Pad1)") (class "Default")
      (node (ref "A185") (pin "1") (pinfunction "1_1") (pintype "passive"))
      (node (ref "A185") (pin "2") (pinfunction "2_2") (pintype "passive"))
      (node (ref "IC20") (pin "9") (pinfunction "9_9") (pintype "passive"))
    )
    (net (code "210") (name "Net-(A186-Pad1)") (class "Default")
      (node (ref "A186") (pin "1") (pinfunction "1_1") (pintype "passive"))
      (node (ref "A186") (pin "2") (pinfunction "2_2") (pintype "passive"))
      (node (ref "IC20") (pin "10") (pinfunction "10_10") (pintype "passive"))
    )
    (net (code "211") (name "Net-(A187-Pad1)") (class "Default")
      (node (ref "A187") (pin "1") (pinfunction "1_1") (pintype "passive"))
      (node (ref "A187") (pin "2") (pinfunction "2_2") (pintype "passive"))
      (node (ref "IC20") (pin "11") (pinfunction "11_11") (pintype "passive"))
    )
    (net (code "212") (name "Net-(A188-Pad1)") (class "Default")
      (node (ref "A188") (pin "1") (pinfunction "1_1") (pintype "passive"))
      (node (ref "A188") (pin "2") (pinfunction "2_2") (pintype "passive"))
      (node (ref "IC20") (pin "12") (pinfunction "12_12") (pintype "passive"))
    )
    (net (code "213") (name "Net-(A189-Pad1)") (class "Default")
      (node (ref "A189") (pin "1") (pinfunction "1_1") (pintype "passive"))
      (node (ref "A189") (pin "2") (pinfunction "2_2") (pintype "passive"))
      (node (ref "IC20") (pin "13") (pinfunction "13_13") (pintype "passive"))
    )
    (net (code "214") (name "Net-(A190-Pad1)") (class "Default")
      (node (ref "A190") (pin "1") (pinfunction "1_1") (pintype "passive"))
      (node (ref "A190") (pin "2") (pinfunction "2_2") (pintype "passive"))
      (node (ref "IC20") (pin "14") (pinfunction "14_14") (pintype "passive"))
    )
    (net (code "215") (name "Net-(A191-Pad1)") (class "Default")
      (node (ref "A191") (pin "1") (pinfunction "1_1") (pintype "passive"))
      (node (ref "A191") (pin "2") (pinfunction "2_2") (pintype "passive"))
      (node (ref "IC20") (pin "15") (pinfunction "15_15") (pintype "passive"))
    )
    (net (code "216") (name "Net-(A192-Pad1)") (class "Default")
      (node (ref "A192") (pin "1") (pinfunction "1_1") (pintype "passive"))
      (node (ref "A192") (pin "2") (pinfunction "2_2") (pintype "passive"))
      (node (ref "IC20") (pin "16") (pinfunction "16_16") (pintype "passive"))
    )
    (net (code "217") (name "Net-(A193-Pad1)") (class "Default")
      (node (ref "A193") (pin "1") (pinfunction "1_1") (pintype "passive"))
      (node (ref "A193") (pin "2") (pinfunction "2_2") (pintype "passive"))
      (node (ref "IC21") (pin "1") (pinfunction "1_1") (pintype "passive"))
    )
    (net (code "218") (name "Net-(A194-Pad1)") (class "Default")
      (node (ref "A194") (pin "1") (pinfunction "1_1") (pintype "passive"))
      (node (ref "A194") (pin "2") (pinfunction "2_2") (pintype "passive"))
      (node (ref "IC21") (pin "2") (pinfunction "2_2") (pintype "passive"))
    )
    (net (code "219") (name "Net-(A195-Pad1)") (class "Default")
      (node (ref "A195") (pin "1") (pinfunction "1_1") (pintype "passive"))
      (node (ref "A195") (pin "2") (pinfunction "2_2") (pintype "passive"))
      (node (ref "IC21") (pin "3") (pinfunction "3_3") (pintype "passive"))
    )
    (net (code "220") (name "Net-(A196-Pad1)") (class "Default")
      (node (ref "A196") (pin "1") (pinfunction "1_1") (pintype "passive"))
      (node (ref "A196") (pin "2") (pinfunction "2_2") (pintype "passive"))
      (node (ref "IC21") (pin "4") (pinfunction "4_4") (pintype "passive"))
    )
    (net (code "221") (name "Net-(A197-Pad1)") (class "Default")
      (node (ref "A197") (pin "1") (pinfunction "1_1") (pintype "passive"))
      (node (ref "A197") (pin "2") (pinfunction "2_2") (pintype "passive"))
      (node (ref "IC21") (pin "5") (pinfunction "5_5") (pintype "passive"))
    )
    (net (code "222") (name "Net-(A198-Pad1)") (class "Default")
      (node (ref "A198") (pin "1") (pinfunction "1_1") (pintype "passive"))
      (node (ref "A198") (pin "2") (pinfunction "2_2") (pintype "passive"))
      (node (ref "IC21") (pin "6") (pinfunction "6_6") (pintype "passive"))
    )
    (net (code "223") (name "Net-(A199-Pad1)") (class "Default")
      (node (ref "A199") (pin "1") (pinfunction "1_1") (pintype "passive"))
      (node (ref "A199") (pin "2") (pinfunction "2_2") (pintype "passive"))
      (node (ref "IC21") (pin "7") (pinfunction "7_7") (pintype "passive"))
    )
    (net (code "224") (name "Net-(A200-Pad1)") (class "Default")
      (node (ref "A200") (pin "1") (pinfunction "1_1") (pintype "passive"))
      (node (ref "A200") (pin "2") (pinfunction "2_2") (pintype "passive"))
      (node (ref "IC21") (pin "8") (pinfunction "8_8") (pintype "passive"))
    )
    (net (code "225") (name "Net-(A201-Pad1)") (class "Default")
      (node (ref "A201") (pin "1") (pinfunction "1_1") (pintype "passive"))
      (node (ref "A201") (pin "2") (pinfunction "2_2") (pintype "passive"))
      (node (ref "IC21") (pin "9") (pinfunction "9_9") (pintype "passive"))
    )
    (net (code "226") (name "Net-(A202-Pad1)") (class "Default")
      (node (ref "A202") (pin "1") (pinfunction "1_1") (pintype "passive"))
      (node (ref "A202") (pin "2") (pinfunction "2_2") (pintype "passive"))
      (node (ref "IC21") (pin "10") (pinfunction "10_10") (pintype "passive"))
    )
    (net (code "227") (name "Net-(A203-Pad1)") (class "Default")
      (node (ref "A203") (pin "1") (pinfunction "1_1") (pintype "passive"))
      (node (ref "A203") (pin "2") (pinfunction "2_2") (pintype "passive"))
      (node (ref "IC21") (pin "11") (pinfunction "11_11") (pintype "passive"))
    )
    (net (code "228") (name "Net-(A204-Pad1)") (class "Default")
      (node (ref "A204") (pin "1") (pinfunction "1_1") (pintype "passive"))
      (node (ref "A204") (pin "2") (pinfunction "2_2") (pintype "passive"))
      (node (ref "IC21") (pin "12") (pinfunction "12_12") (pintype "passive"))
    )
    (net (code "229") (name "Net-(A205-Pad1)") (class "Default")
      (node (ref "A205") (pin "1") (pinfunction "1_1") (pintype "passive"))
      (node (ref "A205") (pin "2") (pinfunction "2_2") (pintype "passive"))
      (node (ref "IC21") (pin "13") (pinfunction "13_13") (pintype "passive"))
    )
    (net (code "230") (name "Net-(A206-Pad1)") (class "Default")
      (node (ref "A206") (pin "1") (pinfunction "1_1") (pintype "passive"))
      (node (ref "A206") (pin "2") (pinfunction "2_2") (pintype "passive"))
      (node (ref "IC21") (pin "14") (pinfunction "14_14") (pintype "passive"))
    )
    (net (code "231") (name "Net-(A207-Pad1)") (class "Default")
      (node (ref "A207") (pin "1") (pinfunction "1_1") (pintype "passive"))
      (node (ref "A207") (pin "2") (pinfunction "2_2") (pintype "passive"))
      (node (ref "IC21") (pin "15") (pinfunction "15_15") (pintype "passive"))
    )
    (net (code "232") (name "Net-(A208-Pad1)") (class "Default")
      (node (ref "A208") (pin "1") (pinfunction "1_1") (pintype "passive"))
      (node (ref "A208") (pin "2") (pinfunction "2_2") (pintype "passive"))
      (node (ref "IC21") (pin "16") (pinfunction "16_16") (pintype "passive"))
    )
    (net (code "233") (name "Net-(A209-Pad1)") (class "Default")
      (node (ref "A209") (pin "1") (pinfunction "1_1") (pintype "passive"))
      (node (ref "A209") (pin "2") (pinfunction "2_2") (pintype "passive"))
      (node (ref "IC22") (pin "1") (pinfunction "1_1") (pintype "passive"))
    )
    (net (code "234") (name "Net-(A210-Pad1)") (class "Default")
      (node (ref "A210") (pin "1") (pinfunction "1_1") (pintype "passive"))
      (node (ref "A210") (pin "2") (pinfunction "2_2") (pintype "passive"))
      (node (ref "IC22") (pin "2") (pinfunction "2_2") (pintype "passive"))
    )
    (net (code "235") (name "Net-(A211-Pad1)") (class "Default")
      (node (ref "A211") (pin "1") (pinfunction "1_1") (pintype "passive"))
      (node (ref "A211") (pin "2") (pinfunction "2_2") (pintype "passive"))
      (node (ref "IC22") (pin "3") (pinfunction "3_3") (pintype "passive"))
    )
    (net (code "236") (name "Net-(A212-Pad1)") (class "Default")
      (node (ref "A212") (pin "1") (pinfunction "1_1") (pintype "passive"))
      (node (ref "A212") (pin "2") (pinfunction "2_2") (pintype "passive"))
      (node (ref "IC22") (pin "4") (pinfunction "4_4") (pintype "passive"))
    )
    (net (code "237") (name "Net-(A213-Pad1)") (class "Default")
      (node (ref "A213") (pin "1") (pinfunction "1_1") (pintype "passive"))
      (node (ref "A213") (pin "2") (pinfunction "2_2") (pintype "passive"))
      (node (ref "IC22") (pin "5") (pinfunction "5_5") (pintype "passive"))
    )
    (net (code "238") (name "Net-(A214-Pad1)") (class "Default")
      (node (ref "A214") (pin "1") (pinfunction "1_1") (pintype "passive"))
      (node (ref "A214") (pin "2") (pinfunction "2_2") (pintype "passive"))
      (node (ref "IC22") (pin "6") (pinfunction "6_6") (pintype "passive"))
    )
    (net (code "239") (name "Net-(A215-Pad1)") (class "Default")
      (node (ref "A215") (pin "1") (pinfunction "1_1") (pintype "passive"))
      (node (ref "A215") (pin "2") (pinfunction "2_2") (pintype "passive"))
      (node (ref "IC22") (pin "7") (pinfunction "7_7") (pintype "passive"))
    )
    (net (code "240") (name "Net-(A216-Pad1)") (class "Default")
      (node (ref "A216") (pin "1") (pinfunction "1_1") (pintype "passive"))
      (node (ref "A216") (pin "2") (pinfunction "2_2") (pintype "passive"))
      (node (ref "IC22") (pin "8") (pinfunction "8_8") (pintype "passive"))
    )
    (net (code "241") (name "Net-(A217-Pad1)") (class "Default")
      (node (ref "A217") (pin "1") (pinfunction "1_1") (pintype "passive"))
      (node (ref "A217") (pin "2") (pinfunction "2_2") (pintype "passive"))
      (node (ref "IC22") (pin "9") (pinfunction "9_9") (pintype "passive"))
    )
    (net (code "242") (name "Net-(A218-Pad1)") (class "Default")
      (node (ref "A218") (pin "1") (pinfunction "1_1") (pintype "passive"))
      (node (ref "A218") (pin "2") (pinfunction "2_2") (pintype "passive"))
      (node (ref "IC22") (pin "10") (pinfunction "10_10") (pintype "passive"))
    )
    (net (code "243") (name "Net-(A219-Pad1)") (class "Default")
      (node (ref "A219") (pin "1") (pinfunction "1_1") (pintype "passive"))
      (node (ref "A219") (pin "2") (pinfunction "2_2") (pintype "passive"))
      (node (ref "IC22") (pin "11") (pinfunction "11_11") (pintype "passive"))
    )
    (net (code "244") (name "Net-(A220-Pad1)") (class "Default")
      (node (ref "A220") (pin "1") (pinfunction "1_1") (pintype "passive"))
      (node (ref "A220") (pin "2") (pinfunction "2_2") (pintype "passive"))
      (node (ref "IC22") (pin "12") (pinfunction "12_12") (pintype "passive"))
    )
    (net (code "245") (name "Net-(A221-Pad1)") (class "Default")
      (node (ref "A221") (pin "1") (pinfunction "1_1") (pintype "passive"))
      (node (ref "A221") (pin "2") (pinfunction "2_2") (pintype "passive"))
      (node (ref "IC22") (pin "13") (pinfunction "13_13") (pintype "passive"))
    )
    (net (code "246") (name "Net-(A222-Pad1)") (class "Default")
      (node (ref "A222") (pin "1") (pinfunction "1_1") (pintype "passive"))
      (node (ref "A222") (pin "2") (pinfunction "2_2") (pintype "passive"))
      (node (ref "IC22") (pin "14") (pinfunction "14_14") (pintype "passive"))
    )
    (net (code "247") (name "Net-(A223-Pad1)") (class "Default")
      (node (ref "A223") (pin "1") (pinfunction "1_1") (pintype "passive"))
      (node (ref "A223") (pin "2") (pinfunction "2_2") (pintype "passive"))
      (node (ref "IC22") (pin "15") (pinfunction "15_15") (pintype "passive"))
    )
    (net (code "248") (name "Net-(A224-Pad1)") (class "Default")
      (node (ref "A224") (pin "1") (pinfunction "1_1") (pintype "passive"))
      (node (ref "A224") (pin "2") (pinfunction "2_2") (pintype "passive"))
      (node (ref "IC22") (pin "16") (pinfunction "16_16") (pintype "passive"))
    )
    (net (code "249") (name "Net-(A225-Pad1)") (class "Default")
      (node (ref "A225") (pin "1") (pinfunction "1_1") (pintype "passive"))
      (node (ref "A225") (pin "2") (pinfunction "2_2") (pintype "passive"))
      (node (ref "IC23") (pin "1") (pinfunction "1_1") (pintype "passive"))
    )
    (net (code "250") (name "Net-(A226-Pad1)") (class "Default")
      (node (ref "A226") (pin "1") (pinfunction "1_1") (pintype "passive"))
      (node (ref "A226") (pin "2") (pinfunction "2_2") (pintype "passive"))
      (node (ref "IC23") (pin "2") (pinfunction "2_2") (pintype "passive"))
    )
    (net (code "251") (name "Net-(A227-Pad1)") (class "Default")
      (node (ref "A227") (pin "1") (pinfunction "1_1") (pintype "passive"))
      (node (ref "A227") (pin "2") (pinfunction "2_2") (pintype "passive"))
      (node (ref "IC23") (pin "3") (pinfunction "3_3") (pintype "passive"))
    )
    (net (code "252") (name "Net-(A228-Pad1)") (class "Default")
      (node (ref "A228") (pin "1") (pinfunction "1_1") (pintype "passive"))
      (node (ref "A228") (pin "2") (pinfunction "2_2") (pintype "passive"))
      (node (ref "IC23") (pin "4") (pinfunction "4_4") (pintype "passive"))
    )
    (net (code "253") (name "Net-(A229-Pad1)") (class "Default")
      (node (ref "A229") (pin "1") (pinfunction "1_1") (pintype "passive"))
      (node (ref "A229") (pin "2") (pinfunction "2_2") (pintype "passive"))
      (node (ref "IC23") (pin "5") (pinfunction "5_5") (pintype "passive"))
    )
    (net (code "254") (name "Net-(A230-Pad1)") (class "Default")
      (node (ref "A230") (pin "1") (pinfunction "1_1") (pintype "passive"))
      (node (ref "A230") (pin "2") (pinfunction "2_2") (pintype "passive"))
      (node (ref "IC23") (pin "6") (pinfunction "6_6") (pintype "passive"))
    )
    (net (code "255") (name "Net-(A231-Pad1)") (class "Default")
      (node (ref "A231") (pin "1") (pinfunction "1_1") (pintype "passive"))
      (node (ref "A231") (pin "2") (pinfunction "2_2") (pintype "passive"))
      (node (ref "IC23") (pin "7") (pinfunction "7_7") (pintype "passive"))
    )
    (net (code "256") (name "Net-(A232-Pad1)") (class "Default")
      (node (ref "A232") (pin "1") (pinfunction "1_1") (pintype "passive"))
      (node (ref "A232") (pin "2") (pinfunction "2_2") (pintype "passive"))
      (node (ref "IC23") (pin "8") (pinfunction "8_8") (pintype "passive"))
    )
    (net (code "257") (name "Net-(A233-Pad1)") (class "Default")
      (node (ref "A233") (pin "1") (pinfunction "1_1") (pintype "passive"))
      (node (ref "A233") (pin "2") (pinfunction "2_2") (pintype "passive"))
      (node (ref "IC23") (pin "9") (pinfunction "9_9") (pintype "passive"))
    )
    (net (code "258") (name "Net-(A234-Pad1)") (class "Default")
      (node (ref "A234") (pin "1") (pinfunction "1_1") (pintype "passive"))
      (node (ref "A234") (pin "2") (pinfunction "2_2") (pintype "passive"))
      (node (ref "IC23") (pin "10") (pinfunction "10_10") (pintype "passive"))
    )
    (net (code "259") (name "Net-(A235-Pad1)") (class "Default")
      (node (ref "A235") (pin "1") (pinfunction "1_1") (pintype "passive"))
      (node (ref "A235") (pin "2") (pinfunction "2_2") (pintype "passive"))
      (node (ref "IC23") (pin "11") (pinfunction "11_11") (pintype "passive"))
    )
    (net (code "260") (name "Net-(A236-Pad1)") (class "Default")
      (node (ref "A236") (pin "1") (pinfunction "1_1") (pintype "passive"))
      (node (ref "A236") (pin "2") (pinfunction "2_2") (pintype "passive"))
      (node (ref "IC23") (pin "12") (pinfunction "12_12") (pintype "passive"))
    )
    (net (code "261") (name "Net-(A237-Pad1)") (class "Default")
      (node (ref "A237") (pin "1") (pinfunction "1_1") (pintype "passive"))
      (node (ref "A237") (pin "2") (pinfunction "2_2") (pintype "passive"))
      (node (ref "IC23") (pin "13") (pinfunction "13_13") (pintype "passive"))
    )
    (net (code "262") (name "Net-(A238-Pad1)") (class "Default")
      (node (ref "A238") (pin "1") (pinfunction "1_1") (pintype "passive"))
      (node (ref "A238") (pin "2") (pinfunction "2_2") (pintype "passive"))
      (node (ref "IC23") (pin "14") (pinfunction "14_14") (pintype "passive"))
    )
    (net (code "263") (name "Net-(A239-Pad1)") (class "Default")
      (node (ref "A239") (pin "1") (pinfunction "1_1") (pintype "passive"))
      (node (ref "A239") (pin "2") (pinfunction "2_2") (pintype "passive"))
      (node (ref "IC23") (pin "15") (pinfunction "15_15") (pintype "passive"))
    )
    (net (code "264") (name "Net-(A240-Pad1)") (class "Default")
      (node (ref "A240") (pin "1") (pinfunction "1_1") (pintype "passive"))
      (node (ref "A240") (pin "2") (pinfunction "2_2") (pintype "passive"))
      (node (ref "IC23") (pin "16") (pinfunction "16_16") (pintype "passive"))
    )
    (net (code "265") (name "Net-(A241-Pad1)") (class "Default")
      (node (ref "A241") (pin "1") (pinfunction "1_1") (pintype "passive"))
      (node (ref "A241") (pin "2") (pinfunction "2_2") (pintype "passive"))
      (node (ref "IC24") (pin "1") (pinfunction "1_1") (pintype "passive"))
    )
    (net (code "266") (name "Net-(A242-Pad1)") (class "Default")
      (node (ref "A242") (pin "1") (pinfunction "1_1") (pintype "passive"))
      (node (ref "A242") (pin "2") (pinfunction "2_2") (pintype "passive"))
      (node (ref "IC24") (pin "2") (pinfunction "2_2") (pintype "passive"))
    )
    (net (code "267") (name "Net-(A243-Pad1)") (class "Default")
      (node (ref "A243") (pin "1") (pinfunction "1_1") (pintype "passive"))
      (node (ref "A243") (pin "2") (pinfunction "2_2") (pintype "passive"))
      (node (ref "IC24") (pin "3") (pinfunction "3_3") (pintype "passive"))
    )
    (net (code "268") (name "Net-(A244-Pad1)") (class "Default")
      (node (ref "A244") (pin "1") (pinfunction "1_1") (pintype "passive"))
      (node (ref "A244") (pin "2") (pinfunction "2_2") (pintype "passive"))
      (node (ref "IC24") (pin "4") (pinfunction "4_4") (pintype "passive"))
    )
    (net (code "269") (name "Net-(A245-Pad1)") (class "Default")
      (node (ref "A245") (pin "1") (pinfunction "1_1") (pintype "passive"))
      (node (ref "A245") (pin "2") (pinfunction "2_2") (pintype "passive"))
      (node (ref "IC24") (pin "5") (pinfunction "5_5") (pintype "passive"))
    )
    (net (code "270") (name "Net-(A246-Pad1)") (class "Default")
      (node (ref "A246") (pin "1") (pinfunction "1_1") (pintype "passive"))
      (node (ref "A246") (pin "2") (pinfunction "2_2") (pintype "passive"))
      (node (ref "IC24") (pin "6") (pinfunction "6_6") (pintype "passive"))
    )
    (net (code "271") (name "Net-(A247-Pad1)") (class "Default")
      (node (ref "A247") (pin "1") (pinfunction "1_1") (pintype "passive"))
      (node (ref "A247") (pin "2") (pinfunction "2_2") (pintype "passive"))
      (node (ref "IC24") (pin "7") (pinfunction "7_7") (pintype "passive"))
    )
    (net (code "272") (name "Net-(A248-Pad1)") (class "Default")
      (node (ref "A248") (pin "1") (pinfunction "1_1") (pintype "passive"))
      (node (ref "A248") (pin "2") (pinfunction "2_2") (pintype "passive"))
      (node (ref "IC24") (pin "8") (pinfunction "8_8") (pintype "passive"))
    )
    (net (code "273") (name "Net-(A249-Pad1)") (class "Default")
      (node (ref "A249") (pin "1") (pinfunction "1_1") (pintype "passive"))
      (node (ref "A249") (pin "2") (pinfunction "2_2") (pintype "passive"))
      (node (ref "IC24") (pin "9") (pinfunction "9_9") (pintype "passive"))
    )
    (net (code "274") (name "Net-(A250-Pad1)") (class "Default")
      (node (ref "A250") (pin "1") (pinfunction "1_1") (pintype "passive"))
      (node (ref "A250") (pin "2") (pinfunction "2_2") (pintype "passive"))
      (node (ref "IC24") (pin "10") (pinfunction "10_10") (pintype "passive"))
    )
    (net (code "275") (name "Net-(A251-Pad1)") (class "Default")
      (node (ref "A251") (pin "1") (pinfunction "1_1") (pintype "passive"))
      (node (ref "A251") (pin "2") (pinfunction "2_2") (pintype "passive"))
      (node (ref "IC24") (pin "11") (pinfunction "11_11") (pintype "passive"))
    )
    (net (code "276") (name "Net-(A252-Pad1)") (class "Default")
      (node (ref "A252") (pin "1") (pinfunction "1_1") (pintype "passive"))
      (node (ref "A252") (pin "2") (pinfunction "2_2") (pintype "passive"))
      (node (ref "IC24") (pin "12") (pinfunction "12_12") (pintype "passive"))
    )
    (net (code "277") (name "Net-(A253-Pad1)") (class "Default")
      (node (ref "A253") (pin "1") (pinfunction "1_1") (pintype "passive"))
      (node (ref "A253") (pin "2") (pinfunction "2_2") (pintype "passive"))
      (node (ref "IC24") (pin "13") (pinfunction "13_13") (pintype "passive"))
    )
    (net (code "278") (name "Net-(A254-Pad1)") (class "Default")
      (node (ref "A254") (pin "1") (pinfunction "1_1") (pintype "passive"))
      (node (ref "A254") (pin "2") (pinfunction "2_2") (pintype "passive"))
      (node (ref "IC24") (pin "14") (pinfunction "14_14") (pintype "passive"))
    )
    (net (code "279") (name "Net-(A255-Pad1)") (class "Default")
      (node (ref "A255") (pin "1") (pinfunction "1_1") (pintype "passive"))
      (node (ref "A255") (pin "2") (pinfunction "2_2") (pintype "passive"))
      (node (ref "IC24") (pin "15") (pinfunction "15_15") (pintype "passive"))
    )
    (net (code "280") (name "Net-(A256-Pad1)") (class "Default")
      (node (ref "A256") (pin "1") (pinfunction "1_1") (pintype "passive"))
      (node (ref "A256") (pin "2") (pinfunction "2_2") (pintype "passive"))
      (node (ref "IC24") (pin "16") (pinfunction "16_16") (pintype "passive"))
    )
    (net (code "281") (name "Net-(A257-Pad1)") (class "Default")
      (node (ref "A257") (pin "1") (pinfunction "1_1") (pintype "passive"))
      (node (ref "A257") (pin "2") (pinfunction "2_2") (pintype "passive"))
      (node (ref "IC25") (pin "1") (pinfunction "1_1") (pintype "passive"))
    )
    (net (code "282") (name "Net-(A258-Pad1)") (class "Default")
      (node (ref "A258") (pin "1") (pinfunction "1_1") (pintype "passive"))
      (node (ref "A258") (pin "2") (pinfunction "2_2") (pintype "passive"))
      (node (ref "IC25") (pin "2") (pinfunction "2_2") (pintype "passive"))
    )
    (net (code "283") (name "Net-(A259-Pad1)") (class "Default")
      (node (ref "A259") (pin "1") (pinfunction "1_1") (pintype "passive"))
      (node (ref "A259") (pin "2") (pinfunction "2_2") (pintype "passive"))
      (node (ref "IC25") (pin "3") (pinfunction "3_3") (pintype "passive"))
    )
    (net (code "284") (name "Net-(A260-Pad1)") (class "Default")
      (node (ref "A260") (pin "1") (pinfunction "1_1") (pintype "passive"))
      (node (ref "A260") (pin "2") (pinfunction "2_2") (pintype "passive"))
      (node (ref "IC25") (pin "4") (pinfunction "4_4") (pintype "passive"))
    )
    (net (code "285") (name "Net-(A261-Pad1)") (class "Default")
      (node (ref "A261") (pin "1") (pinfunction "1_1") (pintype "passive"))
      (node (ref "A261") (pin "2") (pinfunction "2_2") (pintype "passive"))
      (node (ref "IC25") (pin "5") (pinfunction "5_5") (pintype "passive"))
    )
    (net (code "286") (name "Net-(A262-Pad1)") (class "Default")
      (node (ref "A262") (pin "1") (pinfunction "1_1") (pintype "passive"))
      (node (ref "A262") (pin "2") (pinfunction "2_2") (pintype "passive"))
      (node (ref "IC25") (pin "6") (pinfunction "6_6") (pintype "passive"))
    )
    (net (code "287") (name "Net-(A263-Pad1)") (class "Default")
      (node (ref "A263") (pin "1") (pinfunction "1_1") (pintype "passive"))
      (node (ref "A263") (pin "2") (pinfunction "2_2") (pintype "passive"))
      (node (ref "IC25") (pin "7") (pinfunction "7_7") (pintype "passive"))
    )
    (net (code "288") (name "Net-(A264-Pad1)") (class "Default")
      (node (ref "A264") (pin "1") (pinfunction "1_1") (pintype "passive"))
      (node (ref "A264") (pin "2") (pinfunction "2_2") (pintype "passive"))
      (node (ref "IC25") (pin "8") (pinfunction "8_8") (pintype "passive"))
    )
    (net (code "289") (name "Net-(A265-Pad1)") (class "Default")
      (node (ref "A265") (pin "1") (pinfunction "1_1") (pintype "passive"))
      (node (ref "A265") (pin "2") (pinfunction "2_2") (pintype "passive"))
      (node (ref "IC25") (pin "9") (pinfunction "9_9") (pintype "passive"))
    )
    (net (code "290") (name "Net-(A266-Pad1)") (class "Default")
      (node (ref "A266") (pin "1") (pinfunction "1_1") (pintype "passive"))
      (node (ref "A266") (pin "2") (pinfunction "2_2") (pintype "passive"))
      (node (ref "IC25") (pin "10") (pinfunction "10_10") (pintype "passive"))
    )
    (net (code "291") (name "Net-(A267-Pad1)") (class "Default")
      (node (ref "A267") (pin "1") (pinfunction "1_1") (pintype "passive"))
      (node (ref "A267") (pin "2") (pinfunction "2_2") (pintype "passive"))
      (node (ref "IC25") (pin "11") (pinfunction "11_11") (pintype "passive"))
    )
    (net (code "292") (name "Net-(A268-Pad1)") (class "Default")
      (node (ref "A268") (pin "1") (pinfunction "1_1") (pintype "passive"))
      (node (ref "A268") (pin "2") (pinfunction "2_2") (pintype "passive"))
      (node (ref "IC25") (pin "12") (pinfunction "12_12") (pintype "passive"))
    )
    (net (code "293") (name "Net-(A269-Pad1)") (class "Default")
      (node (ref "A269") (pin "1") (pinfunction "1_1") (pintype "passive"))
      (node (ref "A269") (pin "2") (pinfunction "2_2") (pintype "passive"))
      (node (ref "IC25") (pin "13") (pinfunction "13_13") (pintype "passive"))
    )
    (net (code "294") (name "Net-(A270-Pad1)") (class "Default")
      (node (ref "A270") (pin "1") (pinfunction "1_1") (pintype "passive"))
      (node (ref "A270") (pin "2") (pinfunction "2_2") (pintype "passive"))
      (node (ref "IC25") (pin "14") (pinfunction "14_14") (pintype "passive"))
    )
    (net (code "295") (name "Net-(A271-Pad1)") (class "Default")
      (node (ref "A271") (pin "1") (pinfunction "1_1") (pintype "passive"))
      (node (ref "A271") (pin "2") (pinfunction "2_2") (pintype "passive"))
      (node (ref "IC25") (pin "15") (pinfunction "15_15") (pintype "passive"))
    )
    (net (code "296") (name "Net-(A272-Pad1)") (class "Default")
      (node (ref "A272") (pin "1") (pinfunction "1_1") (pintype "passive"))
      (node (ref "A272") (pin "2") (pinfunction "2_2") (pintype "passive"))
      (node (ref "IC25") (pin "16") (pinfunction "16_16") (pintype "passive"))
    )
    (net (code "297") (name "Net-(A273-Pad1)") (class "Default")
      (node (ref "A273") (pin "1") (pinfunction "1_1") (pintype "passive"))
      (node (ref "A273") (pin "2") (pinfunction "2_2") (pintype "passive"))
      (node (ref "IC26") (pin "1") (pinfunction "1_1") (pintype "passive"))
    )
    (net (code "298") (name "Net-(A274-Pad1)") (class "Default")
      (node (ref "A274") (pin "1") (pinfunction "1_1") (pintype "passive"))
      (node (ref "A274") (pin "2") (pinfunction "2_2") (pintype "passive"))
      (node (ref "IC26") (pin "2") (pinfunction "2_2") (pintype "passive"))
    )
    (net (code "299") (name "Net-(A275-Pad1)") (class "Default")
      (node (ref "A275") (pin "1") (pinfunction "1_1") (pintype "passive"))
      (node (ref "A275") (pin "2") (pinfunction "2_2") (pintype "passive"))
      (node (ref "IC26") (pin "3") (pinfunction "3_3") (pintype "passive"))
    )
    (net (code "300") (name "Net-(A276-Pad1)") (class "Default")
      (node (ref "A276") (pin "1") (pinfunction "1_1") (pintype "passive"))
      (node (ref "A276") (pin "2") (pinfunction "2_2") (pintype "passive"))
      (node (ref "IC26") (pin "4") (pinfunction "4_4") (pintype "passive"))
    )
    (net (code "301") (name "Net-(A277-Pad1)") (class "Default")
      (node (ref "A277") (pin "1") (pinfunction "1_1") (pintype "passive"))
      (node (ref "A277") (pin "2") (pinfunction "2_2") (pintype "passive"))
      (node (ref "IC26") (pin "5") (pinfunction "5_5") (pintype "passive"))
    )
    (net (code "302") (name "Net-(A278-Pad1)") (class "Default")
      (node (ref "A278") (pin "1") (pinfunction "1_1") (pintype "passive"))
      (node (ref "A278") (pin "2") (pinfunction "2_2") (pintype "passive"))
      (node (ref "IC26") (pin "6") (pinfunction "6_6") (pintype "passive"))
    )
    (net (code "303") (name "Net-(A279-Pad1)") (class "Default")
      (node (ref "A279") (pin "1") (pinfunction "1_1") (pintype "passive"))
      (node (ref "A279") (pin "2") (pinfunction "2_2") (pintype "passive"))
      (node (ref "IC26") (pin "7") (pinfunction "7_7") (pintype "passive"))
    )
    (net (code "304") (name "Net-(A280-Pad1)") (class "Default")
      (node (ref "A280") (pin "1") (pinfunction "1_1") (pintype "passive"))
      (node (ref "A280") (pin "2") (pinfunction "2_2") (pintype "passive"))
      (node (ref "IC26") (pin "8") (pinfunction "8_8") (pintype "passive"))
    )
    (net (code "305") (name "Net-(A281-Pad1)") (class "Default")
      (node (ref "A281") (pin "1") (pinfunction "1_1") (pintype "passive"))
      (node (ref "A281") (pin "2") (pinfunction "2_2") (pintype "passive"))
      (node (ref "IC26") (pin "9") (pinfunction "9_9") (pintype "passive"))
    )
    (net (code "306") (name "Net-(A282-Pad1)") (class "Default")
      (node (ref "A282") (pin "1") (pinfunction "1_1") (pintype "passive"))
      (node (ref "A282") (pin "2") (pinfunction "2_2") (pintype "passive"))
      (node (ref "IC26") (pin "10") (pinfunction "10_10") (pintype "passive"))
    )
    (net (code "307") (name "Net-(A283-Pad1)") (class "Default")
      (node (ref "A283") (pin "1") (pinfunction "1_1") (pintype "passive"))
      (node (ref "A283") (pin "2") (pinfunction "2_2") (pintype "passive"))
      (node (ref "IC26") (pin "11") (pinfunction "11_11") (pintype "passive"))
    )
    (net (code "308") (name "Net-(A284-Pad1)") (class "Default")
      (node (ref "A284") (pin "1") (pinfunction "1_1") (pintype "passive"))
      (node (ref "A284") (pin "2") (pinfunction "2_2") (pintype "passive"))
      (node (ref "IC26") (pin "12") (pinfunction "12_12") (pintype "passive"))
    )
    (net (code "309") (name "Net-(A285-Pad1)") (class "Default")
      (node (ref "A285") (pin "1") (pinfunction "1_1") (pintype "passive"))
      (node (ref "A285") (pin "2") (pinfunction "2_2") (pintype "passive"))
      (node (ref "IC26") (pin "13") (pinfunction "13_13") (pintype "passive"))
    )
    (net (code "310") (name "Net-(A286-Pad1)") (class "Default")
      (node (ref "A286") (pin "1") (pinfunction "1_1") (pintype "passive"))
      (node (ref "A286") (pin "2") (pinfunction "2_2") (pintype "passive"))
      (node (ref "IC26") (pin "14") (pinfunction "14_14") (pintype "passive"))
    )
    (net (code "311") (name "Net-(A287-Pad1)") (class "Default")
      (node (ref "A287") (pin "1") (pinfunction "1_1") (pintype "passive"))
      (node (ref "A287") (pin "2") (pinfunction "2_2") (pintype "passive"))
      (node (ref "IC26") (pin "15") (pinfunction "15_15") (pintype "passive"))
    )
    (net (code "312") (name "Net-(A288-Pad1)") (class "Default")
      (node (ref "A288") (pin "1") (pinfunction "1_1") (pintype "passive"))
      (node (ref "A288") (pin "2") (pinfunction "2_2") (pintype "passive"))
      (node (ref "IC26") (pin "16") (pinfunction "16_16") (pintype "passive"))
    )
    (net (code "313") (name "Net-(A289-Pad1)") (class "Default")
      (node (ref "A289") (pin "1") (pinfunction "1_1") (pintype "passive"))
      (node (ref "A289") (pin "2") (pinfunction "2_2") (pintype "passive"))
      (node (ref "IC27") (pin "1") (pinfunction "1_1") (pintype "passive"))
    )
    (net (code "314") (name "Net-(A290-Pad1)") (class "Default")
      (node (ref "A290") (pin "1") (pinfunction "1_1") (pintype "passive"))
      (node (ref "A290") (pin "2") (pinfunction "2_2") (pintype "passive"))
      (node (ref "IC27") (pin "2") (pinfunction "2_2") (pintype "passive"))
    )
    (net (code "315") (name "Net-(A291-Pad1)") (class "Default")
      (node (ref "A291") (pin "1") (pinfunction "1_1") (pintype "passive"))
      (node (ref "A291") (pin "2") (pinfunction "2_2") (pintype "passive"))
      (node (ref "IC27") (pin "3") (pinfunction "3_3") (pintype "passive"))
    )
    (net (code "316") (name "Net-(A292-Pad1)") (class "Default")
      (node (ref "A292") (pin "1") (pinfunction "1_1") (pintype "passive"))
      (node (ref "A292") (pin "2") (pinfunction "2_2") (pintype "passive"))
      (node (ref "IC27") (pin "4") (pinfunction "4_4") (pintype "passive"))
    )
    (net (code "317") (name "Net-(A293-Pad1)") (class "Default")
      (node (ref "A293") (pin "1") (pinfunction "1_1") (pintype "passive"))
      (node (ref "A293") (pin "2") (pinfunction "2_2") (pintype "passive"))
      (node (ref "IC27") (pin "5") (pinfunction "5_5") (pintype "passive"))
    )
    (net (code "318") (name "Net-(A294-Pad1)") (class "Default")
      (node (ref "A294") (pin "1") (pinfunction "1_1") (pintype "passive"))
      (node (ref "A294") (pin "2") (pinfunction "2_2") (pintype "passive"))
      (node (ref "IC27") (pin "6") (pinfunction "6_6") (pintype "passive"))
    )
    (net (code "319") (name "Net-(A295-Pad1)") (class "Default")
      (node (ref "A295") (pin "1") (pinfunction "1_1") (pintype "passive"))
      (node (ref "A295") (pin "2") (pinfunction "2_2") (pintype "passive"))
      (node (ref "IC27") (pin "7") (pinfunction "7_7") (pintype "passive"))
    )
    (net (code "320") (name "Net-(A296-Pad1)") (class "Default")
      (node (ref "A296") (pin "1") (pinfunction "1_1") (pintype "passive"))
      (node (ref "A296") (pin "2") (pinfunction "2_2") (pintype "passive"))
      (node (ref "IC27") (pin "8") (pinfunction "8_8") (pintype "passive"))
    )
    (net (code "321") (name "Net-(A297-Pad1)") (class "Default")
      (node (ref "A297") (pin "1") (pinfunction "1_1") (pintype "passive"))
      (node (ref "A297") (pin "2") (pinfunction "2_2") (pintype "passive"))
      (node (ref "IC27") (pin "9") (pinfunction "9_9") (pintype "passive"))
    )
    (net (code "322") (name "Net-(A298-Pad1)") (class "Default")
      (node (ref "A298") (pin "1") (pinfunction "1_1") (pintype "passive"))
      (node (ref "A298") (pin "2") (pinfunction "2_2") (pintype "passive"))
      (node (ref "IC27") (pin "10") (pinfunction "10_10") (pintype "passive"))
    )
    (net (code "323") (name "Net-(A299-Pad1)") (class "Default")
      (node (ref "A299") (pin "1") (pinfunction "1_1") (pintype "passive"))
      (node (ref "A299") (pin "2") (pinfunction "2_2") (pintype "passive"))
      (node (ref "IC27") (pin "11") (pinfunction "11_11") (pintype "passive"))
    )
    (net (code "324") (name "Net-(A300-Pad1)") (class "Default")
      (node (ref "A300") (pin "1") (pinfunction "1_1") (pintype "passive"))
      (node (ref "A300") (pin "2") (pinfunction "2_2") (pintype "passive"))
      (node (ref "IC27") (pin "12") (pinfunction "12_12") (pintype "passive"))
    )
    (net (code "325") (name "Net-(A301-Pad1)") (class "Default")
      (node (ref "A301") (pin "1") (pinfunction "1_1") (pintype "passive"))
      (node (ref "A301") (pin "2") (pinfunction "2_2") (pintype "passive"))
      (node (ref "IC27") (pin "13") (pinfunction "13_13") (pintype "passive"))
    )
    (net (code "326") (name "Net-(A302-Pad1)") (class "Default")
      (node (ref "A302") (pin "1") (pinfunction "1_1") (pintype "passive"))
      (node (ref "A302") (pin "2") (pinfunction "2_2") (pintype "passive"))
      (node (ref "IC27") (pin "14") (pinfunction "14_14") (pintype "passive"))
    )
    (net (code "327") (name "Net-(A303-Pad1)") (class "Default")
      (node (ref "A303") (pin "1") (pinfunction "1_1") (pintype "passive"))
      (node (ref "A303") (pin "2") (pinfunction "2_2") (pintype "passive"))
      (node (ref "IC27") (pin "15") (pinfunction "15_15") (pintype "passive"))
    )
    (net (code "328") (name "Net-(A304-Pad1)") (class "Default")
      (node (ref "A304") (pin "1") (pinfunction "1_1") (pintype "passive"))
      (node (ref "A304") (pin "2") (pinfunction "2_2") (pintype "passive"))
      (node (ref "IC27") (pin "16") (pinfunction "16_16") (pintype "passive"))
    )
    (net (code "329") (name "Net-(A305-Pad1)") (class "Default")
      (node (ref "A305") (pin "1") (pinfunction "1_1") (pintype "passive"))
      (node (ref "A305") (pin "2") (pinfunction "2_2") (pintype "passive"))
      (node (ref "IC28") (pin "1") (pinfunction "1_1") (pintype "passive"))
    )
    (net (code "330") (name "Net-(A306-Pad1)") (class "Default")
      (node (ref "A306") (pin "1") (pinfunction "1_1") (pintype "passive"))
      (node (ref "A306") (pin "2") (pinfunction "2_2") (pintype "passive"))
      (node (ref "IC28") (pin "2") (pinfunction "2_2") (pintype "passive"))
    )
    (net (code "331") (name "Net-(A307-Pad1)") (class "Default")
      (node (ref "A307") (pin "1") (pinfunction "1_1") (pintype "passive"))
      (node (ref "A307") (pin "2") (pinfunction "2_2") (pintype "passive"))
      (node (ref "IC28") (pin "3") (pinfunction "3_3") (pintype "passive"))
    )
    (net (code "332") (name "Net-(A308-Pad1)") (class "Default")
      (node (ref "A308") (pin "1") (pinfunction "1_1") (pintype "passive"))
      (node (ref "A308") (pin "2") (pinfunction "2_2") (pintype "passive"))
      (node (ref "IC28") (pin "4") (pinfunction "4_4") (pintype "passive"))
    )
    (net (code "333") (name "Net-(A309-Pad1)") (class "Default")
      (node (ref "A309") (pin "1") (pinfunction "1_1") (pintype "passive"))
      (node (ref "A309") (pin "2") (pinfunction "2_2") (pintype "passive"))
      (node (ref "IC28") (pin "5") (pinfunction "5_5") (pintype "passive"))
    )
    (net (code "334") (name "Net-(A310-Pad1)") (class "Default")
      (node (ref "A310") (pin "1") (pinfunction "1_1") (pintype "passive"))
      (node (ref "A310") (pin "2") (pinfunction "2_2") (pintype "passive"))
      (node (ref "IC28") (pin "6") (pinfunction "6_6") (pintype "passive"))
    )
    (net (code "335") (name "Net-(A311-Pad1)") (class "Default")
      (node (ref "A311") (pin "1") (pinfunction "1_1") (pintype "passive"))
      (node (ref "A311") (pin "2") (pinfunction "2_2") (pintype "passive"))
      (node (ref "IC28") (pin "7") (pinfunction "7_7") (pintype "passive"))
    )
    (net (code "336") (name "Net-(A312-Pad1)") (class "Default")
      (node (ref "A312") (pin "1") (pinfunction "1_1") (pintype "passive"))
      (node (ref "A312") (pin "2") (pinfunction "2_2") (pintype "passive"))
      (node (ref "IC28") (pin "8") (pinfunction "8_8") (pintype "passive"))
    )
    (net (code "337") (name "Net-(A313-Pad1)") (class "Default")
      (node (ref "A313") (pin "1") (pinfunction "1_1") (pintype "passive"))
      (node (ref "A313") (pin "2") (pinfunction "2_2") (pintype "passive"))
      (node (ref "IC28") (pin "9") (pinfunction "9_9") (pintype "passive"))
    )
    (net (code "338") (name "Net-(A314-Pad1)") (class "Default")
      (node (ref "A314") (pin "1") (pinfunction "1_1") (pintype "passive"))
      (node (ref "A314") (pin "2") (pinfunction "2_2") (pintype "passive"))
      (node (ref "IC28") (pin "10") (pinfunction "10_10") (pintype "passive"))
    )
    (net (code "339") (name "Net-(A315-Pad1)") (class "Default")
      (node (ref "A315") (pin "1") (pinfunction "1_1") (pintype "passive"))
      (node (ref "A315") (pin "2") (pinfunction "2_2") (pintype "passive"))
      (node (ref "IC28") (pin "11") (pinfunction "11_11") (pintype "passive"))
    )
    (net (code "340") (name "Net-(A316-Pad1)") (class "Default")
      (node (ref "A316") (pin "1") (pinfunction "1_1") (pintype "passive"))
      (node (ref "A316") (pin "2") (pinfunction "2_2") (pintype "passive"))
      (node (ref "IC28") (pin "12") (pinfunction "12_12") (pintype "passive"))
    )
    (net (code "341") (name "Net-(A317-Pad1)") (class "Default")
      (node (ref "A317") (pin "1") (pinfunction "1_1") (pintype "passive"))
      (node (ref "A317") (pin "2") (pinfunction "2_2") (pintype "passive"))
      (node (ref "IC28") (pin "13") (pinfunction "13_13") (pintype "passive"))
    )
    (net (code "342") (name "Net-(A318-Pad1)") (class "Default")
      (node (ref "A318") (pin "1") (pinfunction "1_1") (pintype "passive"))
      (node (ref "A318") (pin "2") (pinfunction "2_2") (pintype "passive"))
      (node (ref "IC28") (pin "14") (pinfunction "14_14") (pintype "passive"))
    )
    (net (code "343") (name "Net-(A319-Pad1)") (class "Default")
      (node (ref "A319") (pin "1") (pinfunction "1_1") (pintype "passive"))
      (node (ref "A319") (pin "2") (pinfunction "2_2") (pintype "passive"))
      (node (ref "IC28") (pin "15") (pinfunction "15_15") (pintype "passive"))
    )
    (net (code "344") (name "Net-(A320-Pad1)") (class "Default")
      (node (ref "A320") (pin "1") (pinfunction "1_1") (pintype "passive"))
      (node (ref "A320") (pin "2") (pinfunction "2_2") (pintype "passive"))
      (node (ref "IC28") (pin "16") (pinfunction "16_16") (pintype "passive"))
    )
    (net (code "345") (name "Net-(A321-Pad1)") (class "Default")
      (node (ref "A321") (pin "1") (pinfunction "1_1") (pintype "passive"))
      (node (ref "A321") (pin "2") (pinfunction "2_2") (pintype "passive"))
      (node (ref "IC29") (pin "1") (pinfunction "1_1") (pintype "passive"))
    )
    (net (code "346") (name "Net-(A322-Pad1)") (class "Default")
      (node (ref "A322") (pin "1") (pinfunction "1_1") (pintype "passive"))
      (node (ref "A322") (pin "2") (pinfunction "2_2") (pintype "passive"))
      (node (ref "IC29") (pin "2") (pinfunction "2_2") (pintype "passive"))
    )
    (net (code "347") (name "Net-(A323-Pad1)") (class "Default")
      (node (ref "A323") (pin "1") (pinfunction "1_1") (pintype "passive"))
      (node (ref "A323") (pin "2") (pinfunction "2_2") (pintype "passive"))
      (node (ref "IC29") (pin "3") (pinfunction "3_3") (pintype "passive"))
    )
    (net (code "348") (name "Net-(A324-Pad1)") (class "Default")
      (node (ref "A324") (pin "1") (pinfunction "1_1") (pintype "passive"))
      (node (ref "A324") (pin "2") (pinfunction "2_2") (pintype "passive"))
      (node (ref "IC29") (pin "4") (pinfunction "4_4") (pintype "passive"))
    )
    (net (code "349") (name "Net-(A325-Pad1)") (class "Default")
      (node (ref "A325") (pin "1") (pinfunction "1_1") (pintype "passive"))
      (node (ref "A325") (pin "2") (pinfunction "2_2") (pintype "passive"))
      (node (ref "IC29") (pin "5") (pinfunction "5_5") (pintype "passive"))
    )
    (net (code "350") (name "Net-(A326-Pad1)") (class "Default")
      (node (ref "A326") (pin "1") (pinfunction "1_1") (pintype "passive"))
      (node (ref "A326") (pin "2") (pinfunction "2_2") (pintype "passive"))
      (node (ref "IC29") (pin "6") (pinfunction "6_6") (pintype "passive"))
    )
    (net (code "351") (name "Net-(A327-Pad1)") (class "Default")
      (node (ref "A327") (pin "1") (pinfunction "1_1") (pintype "passive"))
      (node (ref "A327") (pin "2") (pinfunction "2_2") (pintype "passive"))
      (node (ref "IC29") (pin "7") (pinfunction "7_7") (pintype "passive"))
    )
    (net (code "352") (name "Net-(A328-Pad1)") (class "Default")
      (node (ref "A328") (pin "1") (pinfunction "1_1") (pintype "passive"))
      (node (ref "A328") (pin "2") (pinfunction "2_2") (pintype "passive"))
      (node (ref "IC29") (pin "8") (pinfunction "8_8") (pintype "passive"))
    )
    (net (code "353") (name "Net-(A329-Pad1)") (class "Default")
      (node (ref "A329") (pin "1") (pinfunction "1_1") (pintype "passive"))
      (node (ref "A329") (pin "2") (pinfunction "2_2") (pintype "passive"))
      (node (ref "IC29") (pin "9") (pinfunction "9_9") (pintype "passive"))
    )
    (net (code "354") (name "Net-(A330-Pad1)") (class "Default")
      (node (ref "A330") (pin "1") (pinfunction "1_1") (pintype "passive"))
      (node (ref "A330") (pin "2") (pinfunction "2_2") (pintype "passive"))
      (node (ref "IC29") (pin "10") (pinfunction "10_10") (pintype "passive"))
    )
    (net (code "355") (name "Net-(A331-Pad1)") (class "Default")
      (node (ref "A331") (pin "1") (pinfunction "1_1") (pintype "passive"))
      (node (ref "A331") (pin "2") (pinfunction "2_2") (pintype "passive"))
      (node (ref "IC29") (pin "11") (pinfunction "11_11") (pintype "passive"))
    )
    (net (code "356") (name "Net-(A332-Pad1)") (class "Default")
      (node (ref "A332") (pin "1") (pinfunction "1_1") (pintype "passive"))
      (node (ref "A332") (pin "2") (pinfunction "2_2") (pintype "passive"))
      (node (ref "IC29") (pin "12") (pinfunction "12_12") (pintype "passive"))
    )
    (net (code "357") (name "Net-(A333-Pad1)") (class "Default")
      (node (ref "A333") (pin "1") (pinfunction "1_1") (pintype "passive"))
      (node (ref "A333") (pin "2") (pinfunction "2_2") (pintype "passive"))
      (node (ref "IC29") (pin "13") (pinfunction "13_13") (pintype "passive"))
    )
    (net (code "358") (name "Net-(A334-Pad1)") (class "Default")
      (node (ref "A334") (pin "1") (pinfunction "1_1") (pintype "passive"))
      (node (ref "A334") (pin "2") (pinfunction "2_2") (pintype "passive"))
      (node (ref "IC29") (pin "14") (pinfunction "14_14") (pintype "passive"))
    )
    (net (code "359") (name "Net-(A335-Pad1)") (class "Default")
      (node (ref "A335") (pin "1") (pinfunction "1_1") (pintype "passive"))
      (node (ref "A335") (pin "2") (pinfunction "2_2") (pintype "passive"))
      (node (ref "IC29") (pin "15") (pinfunction "15_15") (pintype "passive"))
    )
    (net (code "360") (name "Net-(A336-Pad1)") (class "Default")
      (node (ref "A336") (pin "1") (pinfunction "1_1") (pintype "passive"))
      (node (ref "A336") (pin "2") (pinfunction "2_2") (pintype "passive"))
      (node (ref "IC29") (pin "16") (pinfunction "16_16") (pintype "passive"))
    )
    (net (code "361") (name "Net-(A337-Pad1)") (class "Default")
      (node (ref "A337") (pin "1") (pinfunction "1_1") (pintype "passive"))
      (node (ref "A337") (pin "2") (pinfunction "2_2") (pintype "passive"))
      (node (ref "IC30") (pin "1") (pinfunction "1_1") (pintype "passive"))
    )
    (net (code "362") (name "Net-(A338-Pad1)") (class "Default")
      (node (ref "A338") (pin "1") (pinfunction "1_1") (pintype "passive"))
      (node (ref "A338") (pin "2") (pinfunction "2_2") (pintype "passive"))
      (node (ref "IC30") (pin "2") (pinfunction "2_2") (pintype "passive"))
    )
    (net (code "363") (name "Net-(A339-Pad1)") (class "Default")
      (node (ref "A339") (pin "1") (pinfunction "1_1") (pintype "passive"))
      (node (ref "A339") (pin "2") (pinfunction "2_2") (pintype "passive"))
      (node (ref "IC30") (pin "3") (pinfunction "3_3") (pintype "passive"))
    )
    (net (code "364") (name "Net-(A340-Pad1)") (class "Default")
      (node (ref "A340") (pin "1") (pinfunction "1_1") (pintype "passive"))
      (node (ref "A340") (pin "2") (pinfunction "2_2") (pintype "passive"))
      (node (ref "IC30") (pin "4") (pinfunction "4_4") (pintype "passive"))
    )
    (net (code "365") (name "Net-(A341-Pad1)") (class "Default")
      (node (ref "A341") (pin "1") (pinfunction "1_1") (pintype "passive"))
      (node (ref "A341") (pin "2") (pinfunction "2_2") (pintype "passive"))
      (node (ref "IC30") (pin "5") (pinfunction "5_5") (pintype "passive"))
    )
    (net (code "366") (name "Net-(A342-Pad1)") (class "Default")
      (node (ref "A342") (pin "1") (pinfunction "1_1") (pintype "passive"))
      (node (ref "A342") (pin "2") (pinfunction "2_2") (pintype "passive"))
      (node (ref "IC30") (pin "6") (pinfunction "6_6") (pintype "passive"))
    )
    (net (code "367") (name "Net-(A343-Pad1)") (class "Default")
      (node (ref "A343") (pin "1") (pinfunction "1_1") (pintype "passive"))
      (node (ref "A343") (pin "2") (pinfunction "2_2") (pintype "passive"))
      (node (ref "IC30") (pin "7") (pinfunction "7_7") (pintype "passive"))
    )
    (net (code "368") (name "Net-(A344-Pad1)") (class "Default")
      (node (ref "A344") (pin "1") (pinfunction "1_1") (pintype "passive"))
      (node (ref "A344") (pin "2") (pinfunction "2_2") (pintype "passive"))
      (node (ref "IC30") (pin "8") (pinfunction "8_8") (pintype "passive"))
    )
    (net (code "369") (name "Net-(A345-Pad1)") (class "Default")
      (node (ref "A345") (pin "1") (pinfunction "1_1") (pintype "passive"))
      (node (ref "A345") (pin "2") (pinfunction "2_2") (pintype "passive"))
      (node (ref "IC30") (pin "9") (pinfunction "9_9") (pintype "passive"))
    )
    (net (code "370") (name "Net-(A346-Pad1)") (class "Default")
      (node (ref "A346") (pin "1") (pinfunction "1_1") (pintype "passive"))
      (node (ref "A346") (pin "2") (pinfunction "2_2") (pintype "passive"))
      (node (ref "IC30") (pin "10") (pinfunction "10_10") (pintype "passive"))
    )
    (net (code "371") (name "Net-(A347-Pad1)") (class "Default")
      (node (ref "A347") (pin "1") (pinfunction "1_1") (pintype "passive"))
      (node (ref "A347") (pin "2") (pinfunction "2_2") (pintype "passive"))
      (node (ref "IC30") (pin "11") (pinfunction "11_11") (pintype "passive"))
    )
    (net (code "372") (name "Net-(A348-Pad1)") (class "Default")
      (node (ref "A348") (pin "1") (pinfunction "1_1") (pintype "passive"))
      (node (ref "A348") (pin "2") (pinfunction "2_2") (pintype "passive"))
      (node (ref "IC30") (pin "12") (pinfunction "12_12") (pintype "passive"))
    )
    (net (code "373") (name "Net-(A349-Pad1)") (class "Default")
      (node (ref "A349") (pin "1") (pinfunction "1_1") (pintype "passive"))
      (node (ref "A349") (pin "2") (pinfunction "2_2") (pintype "passive"))
      (node (ref "IC30") (pin "13") (pinfunction "13_13") (pintype "passive"))
    )
    (net (code "374") (name "Net-(A350-Pad1)") (class "Default")
      (node (ref "A350") (pin "1") (pinfunction "1_1") (pintype "passive"))
      (node (ref "A350") (pin "2") (pinfunction "2_2") (pintype "passive"))
      (node (ref "IC30") (pin "14") (pinfunction "14_14") (pintype "passive"))
    )
    (net (code "375") (name "Net-(A351-Pad1)") (class "Default")
      (node (ref "A351") (pin "1") (pinfunction "1_1") (pintype "passive"))
      (node (ref "A351") (pin "2") (pinfunction "2_2") (pintype "passive"))
      (node (ref "IC30") (pin "15") (pinfunction "15_15") (pintype "passive"))
    )
    (net (code "376") (name "Net-(A352-Pad1)") (class "Default")
      (node (ref "A352") (pin "1") (pinfunction "1_1") (pintype "passive"))
      (node (ref "A352") (pin "2") (pinfunction "2_2") (pintype "passive"))
      (node (ref "IC30") (pin "16") (pinfunction "16_16") (pintype "passive"))
    )
    (net (code "377") (name "Net-(A353-Pad1)") (class "Default")
      (node (ref "A353") (pin "1") (pinfunction "1_1") (pintype "passive"))
      (node (ref "A353") (pin "2") (pinfunction "2_2") (pintype "passive"))
      (node (ref "IC31") (pin "1") (pinfunction "1_1") (pintype "passive"))
    )
    (net (code "378") (name "Net-(A354-Pad1)") (class "Default")
      (node (ref "A354") (pin "1") (pinfunction "1_1") (pintype "passive"))
      (node (ref "A354") (pin "2") (pinfunction "2_2") (pintype "passive"))
      (node (ref "IC31") (pin "2") (pinfunction "2_2") (pintype "passive"))
    )
    (net (code "379") (name "Net-(A355-Pad1)") (class "Default")
      (node (ref "A355") (pin "1") (pinfunction "1_1") (pintype "passive"))
      (node (ref "A355") (pin "2") (pinfunction "2_2") (pintype "passive"))
      (node (ref "IC31") (pin "3") (pinfunction "3_3") (pintype "passive"))
    )
    (net (code "380") (name "Net-(A356-Pad1)") (class "Default")
      (node (ref "A356") (pin "1") (pinfunction "1_1") (pintype "passive"))
      (node (ref "A356") (pin "2") (pinfunction "2_2") (pintype "passive"))
      (node (ref "IC31") (pin "4") (pinfunction "4_4") (pintype "passive"))
    )
    (net (code "381") (name "Net-(A357-Pad1)") (class "Default")
      (node (ref "A357") (pin "1") (pinfunction "1_1") (pintype "passive"))
      (node (ref "A357") (pin "2") (pinfunction "2_2") (pintype "passive"))
      (node (ref "IC31") (pin "5") (pinfunction "5_5") (pintype "passive"))
    )
    (net (code "382") (name "Net-(A358-Pad1)") (class "Default")
      (node (ref "A358") (pin "1") (pinfunction "1_1") (pintype "passive"))
      (node (ref "A358") (pin "2") (pinfunction "2_2") (pintype "passive"))
      (node (ref "IC31") (pin "6") (pinfunction "6_6") (pintype "passive"))
    )
    (net (code "383") (name "Net-(A359-Pad1)") (class "Default")
      (node (ref "A359") (pin "1") (pinfunction "1_1") (pintype "passive"))
      (node (ref "A359") (pin "2") (pinfunction "2_2") (pintype "passive"))
      (node (ref "IC31") (pin "7") (pinfunction "7_7") (pintype "passive"))
    )
    (net (code "384") (name "Net-(A360-Pad1)") (class "Default")
      (node (ref "A360") (pin "1") (pinfunction "1_1") (pintype "passive"))
      (node (ref "A360") (pin "2") (pinfunction "2_2") (pintype "passive"))
      (node (ref "IC31") (pin "8") (pinfunction "8_8") (pintype "passive"))
    )
    (net (code "385") (name "Net-(A361-Pad1)") (class "Default")
      (node (ref "A361") (pin "1") (pinfunction "1_1") (pintype "passive"))
      (node (ref "A361") (pin "2") (pinfunction "2_2") (pintype "passive"))
      (node (ref "IC31") (pin "9") (pinfunction "9_9") (pintype "passive"))
    )
    (net (code "386") (name "Net-(A362-Pad1)") (class "Default")
      (node (ref "A362") (pin "1") (pinfunction "1_1") (pintype "passive"))
      (node (ref "A362") (pin "2") (pinfunction "2_2") (pintype "passive"))
      (node (ref "IC31") (pin "10") (pinfunction "10_10") (pintype "passive"))
    )
    (net (code "387") (name "Net-(A363-Pad1)") (class "Default")
      (node (ref "A363") (pin "1") (pinfunction "1_1") (pintype "passive"))
      (node (ref "A363") (pin "2") (pinfunction "2_2") (pintype "passive"))
      (node (ref "IC31") (pin "11") (pinfunction "11_11") (pintype "passive"))
    )
    (net (code "388") (name "Net-(A364-Pad1)") (class "Default")
      (node (ref "A364") (pin "1") (pinfunction "1_1") (pintype "passive"))
      (node (ref "A364") (pin "2") (pinfunction "2_2") (pintype "passive"))
      (node (ref "IC31") (pin "12") (pinfunction "12_12") (pintype "passive"))
    )
    (net (code "389") (name "Net-(A365-Pad1)") (class "Default")
      (node (ref "A365") (pin "1") (pinfunction "1_1") (pintype "passive"))
      (node (ref "A365") (pin "2") (pinfunction "2_2") (pintype "passive"))
      (node (ref "IC31") (pin "13") (pinfunction "13_13") (pintype "passive"))
    )
    (net (code "390") (name "Net-(A366-Pad1)") (class "Default")
      (node (ref "A366") (pin "1") (pinfunction "1_1") (pintype "passive"))
      (node (ref "A366") (pin "2") (pinfunction "2_2") (pintype "passive"))
      (node (ref "IC31") (pin "14") (pinfunction "14_14") (pintype "passive"))
    )
    (net (code "391") (name "Net-(A367-Pad1)") (class "Default")
      (node (ref "A367") (pin "1") (pinfunction "1_1") (pintype "passive"))
      (node (ref "A367") (pin "2") (pinfunction "2_2") (pintype "passive"))
      (node (ref "IC31") (pin "15") (pinfunction "15_15") (pintype "passive"))
    )
    (net (code "392") (name "Net-(A368-Pad1)") (class "Default")
      (node (ref "A368") (pin "1") (pinfunction "1_1") (pintype "passive"))
      (node (ref "A368") (pin "2") (pinfunction "2_2") (pintype "passive"))
      (node (ref "IC31") (pin "16") (pinfunction "16_16") (pintype "passive"))
    )
    (net (code "393") (name "Net-(A369-Pad1)") (class "Default")
      (node (ref "A369") (pin "1") (pinfunction "1_1") (pintype "passive"))
      (node (ref "A369") (pin "2") (pinfunction "2_2") (pintype "passive"))
      (node (ref "IC32") (pin "1") (pinfunction "1_1") (pintype "passive"))
    )
    (net (code "394") (name "Net-(A370-Pad1)") (class "Default")
      (node (ref "A370") (pin "1") (pinfunction "1_1") (pintype "passive"))
      (node (ref "A370") (pin "2") (pinfunction "2_2") (pintype "passive"))
      (node (ref "IC32") (pin "2") (pinfunction "2_2") (pintype "passive"))
    )
    (net (code "395") (name "Net-(A371-Pad1)") (class "Default")
      (node (ref "A371") (pin "1") (pinfunction "1_1") (pintype "passive"))
      (node (ref "A371") (pin "2") (pinfunction "2_2") (pintype "passive"))
      (node (ref "IC32") (pin "3") (pinfunction "3_3") (pintype "passive"))
    )
    (net (code "396") (name "Net-(A372-Pad1)") (class "Default")
      (node (ref "A372") (pin "1") (pinfunction "1_1") (pintype "passive"))
      (node (ref "A372") (pin "2") (pinfunction "2_2") (pintype "passive"))
      (node (ref "IC32") (pin "4") (pinfunction "4_4") (pintype "passive"))
    )
    (net (code "397") (name "Net-(A373-Pad1)") (class "Default")
      (node (ref "A373") (pin "1") (pinfunction "1_1") (pintype "passive"))
      (node (ref "A373") (pin "2") (pinfunction "2_2") (pintype "passive"))
      (node (ref "IC32") (pin "5") (pinfunction "5_5") (pintype "passive"))
    )
    (net (code "398") (name "Net-(A374-Pad1)") (class "Default")
      (node (ref "A374") (pin "1") (pinfunction "1_1") (pintype "passive"))
      (node (ref "A374") (pin "2") (pinfunction "2_2") (pintype "passive"))
      (node (ref "IC32") (pin "6") (pinfunction "6_6") (pintype "passive"))
    )
    (net (code "399") (name "Net-(A375-Pad1)") (class "Default")
      (node (ref "A375") (pin "1") (pinfunction "1_1") (pintype "passive"))
      (node (ref "A375") (pin "2") (pinfunction "2_2") (pintype "passive"))
      (node (ref "IC32") (pin "7") (pinfunction "7_7") (pintype "passive"))
    )
    (net (code "400") (name "Net-(A376-Pad1)") (class "Default")
      (node (ref "A376") (pin "1") (pinfunction "1_1") (pintype "passive"))
      (node (ref "A376") (pin "2") (pinfunction "2_2") (pintype "passive"))
      (node (ref "IC32") (pin "8") (pinfunction "8_8") (pintype "passive"))
    )
    (net (code "401") (name "Net-(A377-Pad1)") (class "Default")
      (node (ref "A377") (pin "1") (pinfunction "1_1") (pintype "passive"))
      (node (ref "A377") (pin "2") (pinfunction "2_2") (pintype "passive"))
      (node (ref "IC32") (pin "9") (pinfunction "9_9") (pintype "passive"))
    )
    (net (code "402") (name "Net-(A378-Pad1)") (class "Default")
      (node (ref "A378") (pin "1") (pinfunction "1_1") (pintype "passive"))
      (node (ref "A378") (pin "2") (pinfunction "2_2") (pintype "passive"))
      (node (ref "IC32") (pin "10") (pinfunction "10_10") (pintype "passive"))
    )
    (net (code "403") (name "Net-(A379-Pad1)") (class "Default")
      (node (ref "A379") (pin "1") (pinfunction "1_1") (pintype "passive"))
      (node (ref "A379") (pin "2") (pinfunction "2_2") (pintype "passive"))
      (node (ref "IC32") (pin "11") (pinfunction "11_11") (pintype "passive"))
    )
    (net (code "404") (name "Net-(A380-Pad1)") (class "Default")
      (node (ref "A380") (pin "1") (pinfunction "1_1") (pintype "passive"))
      (node (ref "A380") (pin "2") (pinfunction "2_2") (pintype "passive"))
      (node (ref "IC32") (pin "12") (pinfunction "12_12") (pintype "passive"))
    )
    (net (code "405") (name "Net-(A381-Pad1)") (class "Default")
      (node (ref "A381") (pin "1") (pinfunction "1_1") (pintype "passive"))
      (node (ref "A381") (pin "2") (pinfunction "2_2") (pintype "passive"))
      (node (ref "IC32") (pin "13") (pinfunction "13_13") (pintype "passive"))
    )
    (net (code "406") (name "Net-(A382-Pad1)") (class "Default")
      (node (ref "A382") (pin "1") (pinfunction "1_1") (pintype "passive"))
      (node (ref "A382") (pin "2") (pinfunction "2_2") (pintype "passive"))
      (node (ref "IC32") (pin "14") (pinfunction "14_14") (pintype "passive"))
    )
    (net (code "407") (name "Net-(A383-Pad1)") (class "Default")
      (node (ref "A383") (pin "1") (pinfunction "1_1") (pintype "passive"))
      (node (ref "A383") (pin "2") (pinfunction "2_2") (pintype "passive"))
      (node (ref "IC32") (pin "15") (pinfunction "15_15") (pintype "passive"))
    )
    (net (code "408") (name "Net-(A384-Pad1)") (class "Default")
      (node (ref "A384") (pin "1") (pinfunction "1_1") (pintype "passive"))
      (node (ref "A384") (pin "2") (pinfunction "2_2") (pintype "passive"))
      (node (ref "IC32") (pin "16") (pinfunction "16_16") (pintype "passive"))
    )
    (net (code "409") (name "Net-(A385-Pad1)") (class "Default")
      (node (ref "A385") (pin "1") (pinfunction "1_1") (pintype "passive"))
      (node (ref "A385") (pin "2") (pinfunction "2_2") (pintype "passive"))
      (node (ref "IC33") (pin "1") (pinfunction "1_1") (pintype "passive"))
    )
    (net (code "410") (name "Net-(A386-Pad1)") (class "Default")
      (node (ref "A386") (pin "1") (pinfunction "1_1") (pintype "passive"))
      (node (ref "A386") (pin "2") (pinfunction "2_2") (pintype "passive"))
      (node (ref "IC33") (pin "2") (pinfunction "2_2") (pintype "passive"))
    )
    (net (code "411") (name "Net-(A387-Pad1)") (class "Default")
      (node (ref "A387") (pin "1") (pinfunction "1_1") (pintype "passive"))
      (node (ref "A387") (pin "2") (pinfunction "2_2") (pintype "passive"))
      (node (ref "IC33") (pin "3") (pinfunction "3_3") (pintype "passive"))
    )
    (net (code "412") (name "Net-(A388-Pad1)") (class "Default")
      (node (ref "A388") (pin "1") (pinfunction "1_1") (pintype "passive"))
      (node (ref "A388") (pin "2") (pinfunction "2_2") (pintype "passive"))
      (node (ref "IC33") (pin "4") (pinfunction "4_4") (pintype "passive"))
    )
    (net (code "413") (name "Net-(A389-Pad1)") (class "Default")
      (node (ref "A389") (pin "1") (pinfunction "1_1") (pintype "passive"))
      (node (ref "A389") (pin "2") (pinfunction "2_2") (pintype "passive"))
      (node (ref "IC33") (pin "5") (pinfunction "5_5") (pintype "passive"))
    )
    (net (code "414") (name "Net-(A390-Pad1)") (class "Default")
      (node (ref "A390") (pin "1") (pinfunction "1_1") (pintype "passive"))
      (node (ref "A390") (pin "2") (pinfunction "2_2") (pintype "passive"))
      (node (ref "IC33") (pin "6") (pinfunction "6_6") (pintype "passive"))
    )
    (net (code "415") (name "Net-(A391-Pad1)") (class "Default")
      (node (ref "A391") (pin "1") (pinfunction "1_1") (pintype "passive"))
      (node (ref "A391") (pin "2") (pinfunction "2_2") (pintype "passive"))
      (node (ref "IC33") (pin "7") (pinfunction "7_7") (pintype "passive"))
    )
    (net (code "416") (name "Net-(A392-Pad1)") (class "Default")
      (node (ref "A392") (pin "1") (pinfunction "1_1") (pintype "passive"))
      (node (ref "A392") (pin "2") (pinfunction "2_2") (pintype "passive"))
      (node (ref "IC33") (pin "8") (pinfunction "8_8") (pintype "passive"))
    )
    (net (code "417") (name "Net-(A393-Pad1)") (class "Default")
      (node (ref "A393") (pin "1") (pinfunction "1_1") (pintype "passive"))
      (node (ref "A393") (pin "2") (pinfunction "2_2") (pintype "passive"))
      (node (ref "IC33") (pin "9") (pinfunction "9_9") (pintype "passive"))
    )
    (net (code "418") (name "Net-(A394-Pad1)") (class "Default")
      (node (ref "A394") (pin "1") (pinfunction "1_1") (pintype "passive"))
      (node (ref "A394") (pin "2") (pinfunction "2_2") (pintype "passive"))
      (node (ref "IC33") (pin "10") (pinfunction "10_10") (pintype "passive"))
    )
    (net (code "419") (name "Net-(A395-Pad1)") (class "Default")
      (node (ref "A395") (pin "1") (pinfunction "1_1") (pintype "passive"))
      (node (ref "A395") (pin "2") (pinfunction "2_2") (pintype "passive"))
      (node (ref "IC33") (pin "11") (pinfunction "11_11") (pintype "passive"))
    )
    (net (code "420") (name "Net-(A396-Pad1)") (class "Default")
      (node (ref "A396") (pin "1") (pinfunction "1_1") (pintype "passive"))
      (node (ref "A396") (pin "2") (pinfunction "2_2") (pintype "passive"))
      (node (ref "IC33") (pin "12") (pinfunction "12_12") (pintype "passive"))
    )
    (net (code "421") (name "Net-(A397-Pad1)") (class "Default")
      (node (ref "A397") (pin "1") (pinfunction "1_1") (pintype "passive"))
      (node (ref "A397") (pin "2") (pinfunction "2_2") (pintype "passive"))
      (node (ref "IC33") (pin "13") (pinfunction "13_13") (pintype "passive"))
    )
    (net (code "422") (name "Net-(A398-Pad1)") (class "Default")
      (node (ref "A398") (pin "1") (pinfunction "1_1") (pintype "passive"))
      (node (ref "A398") (pin "2") (pinfunction "2_2") (pintype "passive"))
      (node (ref "IC33") (pin "14") (pinfunction "14_14") (pintype "passive"))
    )
    (net (code "423") (name "Net-(A399-Pad1)") (class "Default")
      (node (ref "A399") (pin "1") (pinfunction "1_1") (pintype "passive"))
      (node (ref "A399") (pin "2") (pinfunction "2_2") (pintype "passive"))
      (node (ref "IC33") (pin "15") (pinfunction "15_15") (pintype "passive"))
    )
    (net (code "424") (name "Net-(A400-Pad1)") (class "Default")
      (node (ref "A400") (pin "1") (pinfunction "1_1") (pintype "passive"))
      (node (ref "A400") (pin "2") (pinfunction "2_2") (pintype "passive"))
      (node (ref "IC33") (pin "16") (pinfunction "16_16") (pintype "passive"))
    )
    (net (code "425") (name "Net-(A401-Pad1)") (class "Default")
      (node (ref "A401") (pin "1") (pinfunction "1_1") (pintype "passive"))
      (node (ref "A401") (pin "2") (pinfunction "2_2") (pintype "passive"))
      (node (ref "IC34") (pin "1") (pinfunction "1_1") (pintype "passive"))
    )
    (net (code "426") (name "Net-(A402-Pad1)") (class "Default")
      (node (ref "A402") (pin "1") (pinfunction "1_1") (pintype "passive"))
      (node (ref "A402") (pin "2") (pinfunction "2_2") (pintype "passive"))
      (node (ref "IC34") (pin "2") (pinfunction "2_2") (pintype "passive"))
    )
    (net (code "427") (name "Net-(A403-Pad1)") (class "Default")
      (node (ref "A403") (pin "1") (pinfunction "1_1") (pintype "passive"))
      (node (ref "A403") (pin "2") (pinfunction "2_2") (pintype "passive"))
      (node (ref "IC34") (pin "3") (pinfunction "3_3") (pintype "passive"))
    )
    (net (code "428") (name "Net-(A404-Pad1)") (class "Default")
      (node (ref "A404") (pin "1") (pinfunction "1_1") (pintype "passive"))
      (node (ref "A404") (pin "2") (pinfunction "2_2") (pintype "passive"))
      (node (ref "IC34") (pin "4") (pinfunction "4_4") (pintype "passive"))
    )
    (net (code "429") (name "Net-(A405-Pad1)") (class "Default")
      (node (ref "A405") (pin "1") (pinfunction "1_1") (pintype "passive"))
      (node (ref "A405") (pin "2") (pinfunction "2_2") (pintype "passive"))
      (node (ref "IC34") (pin "5") (pinfunction "5_5") (pintype "passive"))
    )
    (net (code "430") (name "Net-(A406-Pad1)") (class "Default")
      (node (ref "A406") (pin "1") (pinfunction "1_1") (pintype "passive"))
      (node (ref "A406") (pin "2") (pinfunction "2_2") (pintype "passive"))
      (node (ref "IC34") (pin "6") (pinfunction "6_6") (pintype "passive"))
    )
    (net (code "431") (name "Net-(A407-Pad1)") (class "Default")
      (node (ref "A407") (pin "1") (pinfunction "1_1") (pintype "passive"))
      (node (ref "A407") (pin "2") (pinfunction "2_2") (pintype "passive"))
      (node (ref "IC34") (pin "7") (pinfunction "7_7") (pintype "passive"))
    )
    (net (code "432") (name "Net-(A408-Pad1)") (class "Default")
      (node (ref "A408") (pin "1") (pinfunction "1_1") (pintype "passive"))
      (node (ref "A408") (pin "2") (pinfunction "2_2") (pintype "passive"))
      (node (ref "IC34") (pin "8") (pinfunction "8_8") (pintype "passive"))
    )
    (net (code "433") (name "Net-(A409-Pad1)") (class "Default")
      (node (ref "A409") (pin "1") (pinfunction "1_1") (pintype "passive"))
      (node (ref "A409") (pin "2") (pinfunction "2_2") (pintype "passive"))
      (node (ref "IC34") (pin "9") (pinfunction "9_9") (pintype "passive"))
    )
    (net (code "434") (name "Net-(A410-Pad1)") (class "Default")
      (node (ref "A410") (pin "1") (pinfunction "1_1") (pintype "passive"))
      (node (ref "A410") (pin "2") (pinfunction "2_2") (pintype "passive"))
      (node (ref "IC34") (pin "10") (pinfunction "10_10") (pintype "passive"))
    )
    (net (code "435") (name "Net-(A411-Pad1)") (class "Default")
      (node (ref "A411") (pin "1") (pinfunction "1_1") (pintype "passive"))
      (node (ref "A411") (pin "2") (pinfunction "2_2") (pintype "passive"))
      (node (ref "IC34") (pin "11") (pinfunction "11_11") (pintype "passive"))
    )
    (net (code "436") (name "Net-(A412-Pad1)") (class "Default")
      (node (ref "A412") (pin "1") (pinfunction "1_1") (pintype "passive"))
      (node (ref "A412") (pin "2") (pinfunction "2_2") (pintype "passive"))
      (node (ref "IC34") (pin "12") (pinfunction "12_12") (pintype "passive"))
    )
    (net (code "437") (name "Net-(A413-Pad1)") (class "Default")
      (node (ref "A413") (pin "1") (pinfunction "1_1") (pintype "passive"))
      (node (ref "A413") (pin "2") (pinfunction "2_2") (pintype "passive"))
      (node (ref "IC34") (pin "13") (pinfunction "13_13") (pintype "passive"))
    )
    (net (code "438") (name "Net-(A414-Pad1)") (class "Default")
      (node (ref "A414") (pin "1") (pinfunction "1_1") (pintype "passive"))
      (node (ref "A414") (pin "2") (pinfunction "2_2") (pintype "passive"))
      (node (ref "IC34") (pin "14") (pinfunction "14_14") (pintype "passive"))
    )
    (net (code "439") (name "Net-(A415-Pad1)") (class "Default")
      (node (ref "A415") (pin "1") (pinfunction "1_1") (pintype "passive"))
      (node (ref "A415") (pin "2") (pinfunction "2_2") (pintype "passive"))
      (node (ref "IC34") (pin "15") (pinfunction "15_15") (pintype "passive"))
    )
    (net (code "440") (name "Net-(A416-Pad1)") (class "Default")
      (node (ref "A416") (pin "1") (pinfunction "1_1") (pintype "passive"))
      (node (ref "A416") (pin "2") (pinfunction "2_2") (pintype "passive"))
      (node (ref "IC34") (pin "16") (pinfunction "16_16") (pintype "passive"))
    )
    (net (code "441") (name "Net-(A417-Pad1)") (class "Default")
      (node (ref "A417") (pin "1") (pinfunction "1_1") (pintype "passive"))
      (node (ref "A417") (pin "2") (pinfunction "2_2") (pintype "passive"))
      (node (ref "IC35") (pin "1") (pinfunction "1_1") (pintype "passive"))
    )
    (net (code "442") (name "Net-(A418-Pad1)") (class "Default")
      (node (ref "A418") (pin "1") (pinfunction "1_1") (pintype "passive"))
      (node (ref "A418") (pin "2") (pinfunction "2_2") (pintype "passive"))
      (node (ref "IC35") (pin "2") (pinfunction "2_2") (pintype "passive"))
    )
    (net (code "443") (name "Net-(A419-Pad1)") (class "Default")
      (node (ref "A419") (pin "1") (pinfunction "1_1") (pintype "passive"))
      (node (ref "A419") (pin "2") (pinfunction "2_2") (pintype "passive"))
      (node (ref "IC35") (pin "3") (pinfunction "3_3") (pintype "passive"))
    )
    (net (code "444") (name "Net-(A420-Pad1)") (class "Default")
      (node (ref "A420") (pin "1") (pinfunction "1_1") (pintype "passive"))
      (node (ref "A420") (pin "2") (pinfunction "2_2") (pintype "passive"))
      (node (ref "IC35") (pin "4") (pinfunction "4_4") (pintype "passive"))
    )
    (net (code "445") (name "Net-(A421-Pad1)") (class "Default")
      (node (ref "A421") (pin "1") (pinfunction "1_1") (pintype "passive"))
      (node (ref "A421") (pin "2") (pinfunction "2_2") (pintype "passive"))
      (node (ref "IC35") (pin "5") (pinfunction "5_5") (pintype "passive"))
    )
    (net (code "446") (name "Net-(A422-Pad1)") (class "Default")
      (node (ref "A422") (pin "1") (pinfunction "1_1") (pintype "passive"))
      (node (ref "A422") (pin "2") (pinfunction "2_2") (pintype "passive"))
      (node (ref "IC35") (pin "6") (pinfunction "6_6") (pintype "passive"))
    )
    (net (code "447") (name "Net-(A423-Pad1)") (class "Default")
      (node (ref "A423") (pin "1") (pinfunction "1_1") (pintype "passive"))
      (node (ref "A423") (pin "2") (pinfunction "2_2") (pintype "passive"))
      (node (ref "IC35") (pin "7") (pinfunction "7_7") (pintype "passive"))
    )
    (net (code "448") (name "Net-(A424-Pad1)") (class "Default")
      (node (ref "A424") (pin "1") (pinfunction "1_1") (pintype "passive"))
      (node (ref "A424") (pin "2") (pinfunction "2_2") (pintype "passive"))
      (node (ref "IC35") (pin "8") (pinfunction "8_8") (pintype "passive"))
    )
    (net (code "449") (name "Net-(A425-Pad1)") (class "Default")
      (node (ref "A425") (pin "1") (pinfunction "1_1") (pintype "passive"))
      (node (ref "A425") (pin "2") (pinfunction "2_2") (pintype "passive"))
      (node (ref "IC35") (pin "9") (pinfunction "9_9") (pintype "passive"))
    )
    (net (code "450") (name "Net-(A426-Pad1)") (class "Default")
      (node (ref "A426") (pin "1") (pinfunction "1_1") (pintype "passive"))
      (node (ref "A426") (pin "2") (pinfunction "2_2") (pintype "passive"))
      (node (ref "IC35") (pin "10") (pinfunction "10_10") (pintype "passive"))
    )
    (net (code "451") (name "Net-(A427-Pad1)") (class "Default")
      (node (ref "A427") (pin "1") (pinfunction "1_1") (pintype "passive"))
      (node (ref "A427") (pin "2") (pinfunction "2_2") (pintype "passive"))
      (node (ref "IC35") (pin "11") (pinfunction "11_11") (pintype "passive"))
    )
    (net (code "452") (name "Net-(A428-Pad1)") (class "Default")
      (node (ref "A428") (pin "1") (pinfunction "1_1") (pintype "passive"))
      (node (ref "A428") (pin "2") (pinfunction "2_2") (pintype "passive"))
      (node (ref "IC35") (pin "12") (pinfunction "12_12") (pintype "passive"))
    )
    (net (code "453") (name "Net-(A429-Pad1)") (class "Default")
      (node (ref "A429") (pin "1") (pinfunction "1_1") (pintype "passive"))
      (node (ref "A429") (pin "2") (pinfunction "2_2") (pintype "passive"))
      (node (ref "IC35") (pin "13") (pinfunction "13_13") (pintype "passive"))
    )
    (net (code "454") (name "Net-(A430-Pad1)") (class "Default")
      (node (ref "A430") (pin "1") (pinfunction "1_1") (pintype "passive"))
      (node (ref "A430") (pin "2") (pinfunction "2_2") (pintype "passive"))
      (node (ref "IC35") (pin "14") (pinfunction "14_14") (pintype "passive"))
    )
    (net (code "455") (name "Net-(A431-Pad1)") (class "Default")
      (node (ref "A431") (pin "1") (pinfunction "1_1") (pintype "passive"))
      (node (ref "A431") (pin "2") (pinfunction "2_2") (pintype "passive"))
      (node (ref "IC35") (pin "15") (pinfunction "15_15") (pintype "passive"))
    )
    (net (code "456") (name "Net-(A432-Pad1)") (class "Default")
      (node (ref "A432") (pin "1") (pinfunction "1_1") (pintype "passive"))
      (node (ref "A432") (pin "2") (pinfunction "2_2") (pintype "passive"))
      (node (ref "IC35") (pin "16") (pinfunction "16_16") (pintype "passive"))
    )
    (net (code "457") (name "Net-(A433-Pad1)") (class "Default")
      (node (ref "A433") (pin "1") (pinfunction "1_1") (pintype "passive"))
      (node (ref "A433") (pin "2") (pinfunction "2_2") (pintype "passive"))
      (node (ref "IC36") (pin "1") (pinfunction "1_1") (pintype "passive"))
    )
    (net (code "458") (name "Net-(A434-Pad1)") (class "Default")
      (node (ref "A434") (pin "1") (pinfunction "1_1") (pintype "passive"))
      (node (ref "A434") (pin "2") (pinfunction "2_2") (pintype "passive"))
      (node (ref "IC36") (pin "2") (pinfunction "2_2") (pintype "passive"))
    )
    (net (code "459") (name "Net-(A435-Pad1)") (class "Default")
      (node (ref "A435") (pin "1") (pinfunction "1_1") (pintype "passive"))
      (node (ref "A435") (pin "2") (pinfunction "2_2") (pintype "passive"))
      (node (ref "IC36") (pin "3") (pinfunction "3_3") (pintype "passive"))
    )
    (net (code "460") (name "Net-(A436-Pad1)") (class "Default")
      (node (ref "A436") (pin "1") (pinfunction "1_1") (pintype "passive"))
      (node (ref "A436") (pin "2") (pinfunction "2_2") (pintype "passive"))
      (node (ref "IC36") (pin "4") (pinfunction "4_4") (pintype "passive"))
    )
    (net (code "461") (name "Net-(A437-Pad1)") (class "Default")
      (node (ref "A437") (pin "1") (pinfunction "1_1") (pintype "passive"))
      (node (ref "A437") (pin "2") (pinfunction "2_2") (pintype "passive"))
      (node (ref "IC36") (pin "5") (pinfunction "5_5") (pintype "passive"))
    )
    (net (code "462") (name "Net-(A438-Pad1)") (class "Default")
      (node (ref "A438") (pin "1") (pinfunction "1_1") (pintype "passive"))
      (node (ref "A438") (pin "2") (pinfunction "2_2") (pintype "passive"))
      (node (ref "IC36") (pin "6") (pinfunction "6_6") (pintype "passive"))
    )
    (net (code "463") (name "Net-(A439-Pad1)") (class "Default")
      (node (ref "A439") (pin "1") (pinfunction "1_1") (pintype "passive"))
      (node (ref "A439") (pin "2") (pinfunction "2_2") (pintype "passive"))
      (node (ref "IC36") (pin "7") (pinfunction "7_7") (pintype "passive"))
    )
    (net (code "464") (name "Net-(A440-Pad1)") (class "Default")
      (node (ref "A440") (pin "1") (pinfunction "1_1") (pintype "passive"))
      (node (ref "A440") (pin "2") (pinfunction "2_2") (pintype "passive"))
      (node (ref "IC36") (pin "8") (pinfunction "8_8") (pintype "passive"))
    )
    (net (code "465") (name "Net-(A441-Pad1)") (class "Default")
      (node (ref "A441") (pin "1") (pinfunction "1_1") (pintype "passive"))
      (node (ref "A441") (pin "2") (pinfunction "2_2") (pintype "passive"))
      (node (ref "IC36") (pin "9") (pinfunction "9_9") (pintype "passive"))
    )
    (net (code "466") (name "Net-(A442-Pad1)") (class "Default")
      (node (ref "A442") (pin "1") (pinfunction "1_1") (pintype "passive"))
      (node (ref "A442") (pin "2") (pinfunction "2_2") (pintype "passive"))
      (node (ref "IC36") (pin "10") (pinfunction "10_10") (pintype "passive"))
    )
    (net (code "467") (name "Net-(A443-Pad1)") (class "Default")
      (node (ref "A443") (pin "1") (pinfunction "1_1") (pintype "passive"))
      (node (ref "A443") (pin "2") (pinfunction "2_2") (pintype "passive"))
      (node (ref "IC36") (pin "11") (pinfunction "11_11") (pintype "passive"))
    )
    (net (code "468") (name "Net-(A444-Pad1)") (class "Default")
      (node (ref "A444") (pin "1") (pinfunction "1_1") (pintype "passive"))
      (node (ref "A444") (pin "2") (pinfunction "2_2") (pintype "passive"))
      (node (ref "IC36") (pin "12") (pinfunction "12_12") (pintype "passive"))
    )
    (net (code "469") (name "Net-(A445-Pad1)") (class "Default")
      (node (ref "A445") (pin "1") (pinfunction "1_1") (pintype "passive"))
      (node (ref "A445") (pin "2") (pinfunction "2_2") (pintype "passive"))
      (node (ref "IC36") (pin "13") (pinfunction "13_13") (pintype "passive"))
    )
    (net (code "470") (name "Net-(A446-Pad1)") (class "Default")
      (node (ref "A446") (pin "1") (pinfunction "1_1") (pintype "passive"))
      (node (ref "A446") (pin "2") (pinfunction "2_2") (pintype "passive"))
      (node (ref "IC36") (pin "14") (pinfunction "14_14") (pintype "passive"))
    )
    (net (code "471") (name "Net-(A447-Pad1)") (class "Default")
      (node (ref "A447") (pin "1") (pinfunction "1_1") (pintype "passive"))
      (node (ref "A447") (pin "2") (pinfunction "2_2") (pintype "passive"))
      (node (ref "IC36") (pin "15") (pinfunction "15_15") (pintype "passive"))
    )
    (net (code "472") (name "Net-(A448-Pad1)") (class "Default")
      (node (ref "A448") (pin "1") (pinfunction "1_1") (pintype "passive"))
      (node (ref "A448") (pin "2") (pinfunction "2_2") (pintype "passive"))
      (node (ref "IC36") (pin "16") (pinfunction "16_16") (pintype "passive"))
    )
    (net (code "473") (name "Net-(B1-+-Pad+@1)") (class "Default")
      (node (ref "B1") (pin "+") (pinfunction "+_+") (pintype "passive"))
      (node (ref "B1") (pin "+@1") (pinfunction "+_+@1") (pintype "passive"))
      (node (ref "B1") (pin "+@2") (pinfunction "+_+@2") (pintype "passive"))
      (node (ref "B1") (pin "+@3") (pinfunction "+_+@3") (pintype "passive"))
      (node (ref "B1") (pin "+@4") (pinfunction "+_+@4") (pintype "passive"))
      (node (ref "D1") (pin "A") (pinfunction "A_A") (pintype "passive"))
    )
    (net (code "474") (name "Net-(IC2A-A5)") (class "Default")
      (node (ref "IC2") (pin "6") (pinfunction "A5_6") (pintype "bidirectional"))
      (node (ref "R4") (pin "2") (pinfunction "2_2") (pintype "passive"))
    )
    (net (code "475") (name "Net-(IC2A-A6)") (class "Default")
      (node (ref "IC2") (pin "7") (pinfunction "A6_7") (pintype "bidirectional"))
      (node (ref "R3") (pin "2") (pinfunction "2_2") (pintype "passive"))
    )
    (net (code "476") (name "Net-(IC2A-A7)") (class "Default")
      (node (ref "IC2") (pin "8") (pinfunction "A7_8") (pintype "bidirectional"))
      (node (ref "R2") (pin "2") (pinfunction "2_2") (pintype "passive"))
    )
    (net (code "477") (name "Net-(IC2A-A8)") (class "Default")
      (node (ref "IC2") (pin "9") (pinfunction "A8_9") (pintype "bidirectional"))
      (node (ref "R1") (pin "2") (pinfunction "2_2") (pintype "passive"))
    )
    (net (code "478") (name "Net-(IC5A-Y0)") (class "Default")
      (node (ref "IC5") (pin "15") (pinfunction "Y0_15") (pintype "output"))
      (node (ref "S1") (pin "1") (pinfunction "1_1") (pintype "passive"))
    )
    (net (code "479") (name "Net-(IC5A-Y1)") (class "Default")
      (node (ref "IC5") (pin "14") (pinfunction "Y1_14") (pintype "output"))
      (node (ref "S1") (pin "2") (pinfunction "2_2") (pintype "passive"))
    )
    (net (code "480") (name "Net-(IC5A-Y2)") (class "Default")
      (node (ref "IC5") (pin "13") (pinfunction "Y2_13") (pintype "output"))
      (node (ref "S1") (pin "3") (pinfunction "3_3") (pintype "passive"))
    )
    (net (code "481") (name "Net-(IC5A-Y3)") (class "Default")
      (node (ref "IC5") (pin "12") (pinfunction "Y3_12") (pintype "output"))
      (node (ref "S1") (pin "4") (pinfunction "4_4") (pintype "passive"))
    )
    (net (code "482") (name "Net-(IC5A-Y4)") (class "Default")
      (node (ref "IC5") (pin "11") (pinfunction "Y4_11") (pintype "output"))
      (node (ref "S1") (pin "5") (pinfunction "5_5") (pintype "passive"))
    )
    (net (code "483") (name "Net-(IC5A-Y5)") (class "Default")
      (node (ref "IC5") (pin "10") (pinfunction "Y5_10") (pintype "output"))
      (node (ref "S1") (pin "6") (pinfunction "6_6") (pintype "passive"))
    )
    (net (code "484") (name "Net-(IC5A-Y6)") (class "Default")
      (node (ref "IC5") (pin "9") (pinfunction "Y6_9") (pintype "output"))
      (node (ref "S1") (pin "7") (pinfunction "7_7") (pintype "passive"))
    )
    (net (code "485") (name "Net-(IC5A-Y7)") (class "Default")
      (node (ref "IC5") (pin "7") (pinfunction "Y7_7") (pintype "output"))
      (node (ref "S1") (pin "8") (pinfunction "8_8") (pintype "passive"))
    )
    (net (code "486") (name "Net-(IC6A-I0)") (class "Default")
      (node (ref "IC6") (pin "1") (pinfunction "I0_1") (pintype "input"))
      (node (ref "R5") (pin "8") (pinfunction "1_8") (pintype "passive"))
      (node (ref "S1") (pin "9") (pinfunction "9_9") (pintype "passive"))
    )
    (net (code "487") (name "Net-(IC6A-I1)") (class "Default")
      (node (ref "IC6") (pin "2") (pinfunction "I1_2") (pintype "input"))
      (node (ref "R5") (pin "1") (pinfunction "1_1") (pintype "passive"))
      (node (ref "S1") (pin "16") (pinfunction "16_16") (pintype "passive"))
    )
    (net (code "488") (name "Net-(IC6A-I2)") (class "Default")
      (node (ref "IC6") (pin "3") (pinfunction "I2_3") (pintype "input"))
      (node (ref "R5") (pin "7") (pinfunction "1_7") (pintype "passive"))
      (node (ref "S1") (pin "10") (pinfunction "10_10") (pintype "passive"))
    )
    (net (code "489") (name "Net-(IC6A-I3)") (class "Default")
      (node (ref "IC6") (pin "4") (pinfunction "I3_4") (pintype "input"))
      (node (ref "R5") (pin "2") (pinfunction "1_2") (pintype "passive"))
      (node (ref "S1") (pin "15") (pinfunction "15_15") (pintype "passive"))
    )
    (net (code "490") (name "Net-(IC6A-I4)") (class "Default")
      (node (ref "IC6") (pin "5") (pinfunction "I4_5") (pintype "input"))
      (node (ref "R5") (pin "6") (pinfunction "1_6") (pintype "passive"))
      (node (ref "S1") (pin "11") (pinfunction "11_11") (pintype "passive"))
    )
    (net (code "491") (name "Net-(IC6A-I5)") (class "Default")
      (node (ref "IC6") (pin "6") (pinfunction "I5_6") (pintype "input"))
      (node (ref "R5") (pin "5") (pinfunction "1_5") (pintype "passive"))
      (node (ref "S1") (pin "12") (pinfunction "12_12") (pintype "passive"))
    )
    (net (code "492") (name "Net-(IC6A-I6)") (class "Default")
      (node (ref "IC6") (pin "11") (pinfunction "I6_11") (pintype "input"))
      (node (ref "R5") (pin "3") (pinfunction "1_3") (pintype "passive"))
      (node (ref "S1") (pin "14") (pinfunction "14_14") (pintype "passive"))
    )
    (net (code "493") (name "Net-(IC6A-I7)") (class "Default")
      (node (ref "IC6") (pin "12") (pinfunction "I7_12") (pintype "input"))
      (node (ref "R5") (pin "4") (pinfunction "1_4") (pintype "passive"))
      (node (ref "S1") (pin "13") (pinfunction "13_13") (pintype "passive"))
    )
    (net (code "494") (name "Net-(IC7A-I1)") (class "Default")
      (node (ref "IC7") (pin "2") (pinfunction "I1_2") (pintype "input"))
      (node (ref "IC8") (pin "13") (pinfunction "Y6_13") (pintype "tri_state"))
    )
    (net (code "495") (name "Net-(IC7A-I2)") (class "Default")
      (node (ref "IC7") (pin "4") (pinfunction "I2_4") (pintype "input"))
      (node (ref "IC8") (pin "15") (pinfunction "Y4_15") (pintype "tri_state"))
    )
    (net (code "496") (name "Net-(IC7A-I3)") (class "Default")
      (node (ref "IC7") (pin "5") (pinfunction "I3_5") (pintype "input"))
      (node (ref "IC8") (pin "17") (pinfunction "Y2_17") (pintype "tri_state"))
    )
    (net (code "497") (name "Net-(IC7B-I0)") (class "Default")
      (node (ref "IC7") (pin "9") (pinfunction "I0_9") (pintype "input"))
      (node (ref "IC8") (pin "18") (pinfunction "Y1_18") (pintype "tri_state"))
      (node (ref "IC8") (pin "3") (pinfunction "A2_3") (pintype "input"))
    )
    (net (code "498") (name "Net-(IC7B-I1)") (class "Default")
      (node (ref "IC7") (pin "10") (pinfunction "I1_10") (pintype "input"))
      (node (ref "IC8") (pin "12") (pinfunction "Y7_12") (pintype "tri_state"))
    )
    (net (code "499") (name "Net-(IC8A-A4)") (class "Default")
      (node (ref "IC8") (pin "16") (pinfunction "Y3_16") (pintype "tri_state"))
      (node (ref "IC8") (pin "5") (pinfunction "A4_5") (pintype "input"))
    )
    (net (code "500") (name "Net-(IC8A-A6)") (class "Default")
      (node (ref "IC8") (pin "14") (pinfunction "Y5_14") (pintype "tri_state"))
      (node (ref "IC8") (pin "7") (pinfunction "A6_7") (pintype "input"))
    )
    (net (code "501") (name "Net-(Q1-B)") (class "Default")
      (node (ref "Q1") (pin "2") (pinfunction "B_2") (pintype "passive"))
      (node (ref "R6") (pin "2") (pinfunction "2_2") (pintype "passive"))
    )
    (net (code "502") (name "Net-(SV1-Pad1)") (class "Default")
      (node (ref "SV1") (pin "1") (pinfunction "1_1") (pintype "passive"))
      (node (ref "SV1") (pin "3") (pinfunction "3_3") (pintype "passive"))
      (node (ref "SV1") (pin "5") (pinfunction "5_5") (pintype "passive"))
      (node (ref "SV1") (pin "7") (pinfunction "7_7") (pintype "passive"))
      (node (ref "SV1") (pin "9") (pinfunction "9_9") (pintype "passive"))
    )
    (net (code "503") (name "Net-(SV1-Pad10)") (class "Default")
      (node (ref "SV1") (pin "10") (pinfunction "10_10") (pintype "passive"))
      (node (ref "SV1") (pin "2") (pinfunction "2_2") (pintype "passive"))
      (node (ref "SV1") (pin "4") (pinfunction "4_4") (pintype "passive"))
      (node (ref "SV1") (pin "6") (pinfunction "6_6") (pintype "passive"))
      (node (ref "SV1") (pin "8") (pinfunction "8_8") (pintype "passive"))
    )
    (net (code "504") (name "Net-(SV2-Pad1)") (class "Default")
      (node (ref "SV2") (pin "1") (pinfunction "1_1") (pintype "passive"))
      (node (ref "SV2") (pin "3") (pinfunction "3_3") (pintype "passive"))
      (node (ref "SV2") (pin "5") (pinfunction "5_5") (pintype "passive"))
      (node (ref "SV2") (pin "7") (pinfunction "7_7") (pintype "passive"))
      (node (ref "SV2") (pin "9") (pinfunction "9_9") (pintype "passive"))
    )
    (net (code "505") (name "Net-(SV2-Pad10)") (class "Default")
      (node (ref "SV2") (pin "10") (pinfunction "10_10") (pintype "passive"))
      (node (ref "SV2") (pin "2") (pinfunction "2_2") (pintype "passive"))
      (node (ref "SV2") (pin "4") (pinfunction "4_4") (pintype "passive"))
      (node (ref "SV2") (pin "6") (pinfunction "6_6") (pintype "passive"))
      (node (ref "SV2") (pin "8") (pinfunction "8_8") (pintype "passive"))
    )
    (net (code "506") (name "Net-(SV7-Pad1)") (class "Default")
      (node (ref "SV7") (pin "1") (pinfunction "1_1") (pintype "passive"))
      (node (ref "SV7") (pin "3") (pinfunction "3_3") (pintype "passive"))
      (node (ref "SV7") (pin "5") (pinfunction "5_5") (pintype "passive"))
      (node (ref "SV7") (pin "7") (pinfunction "7_7") (pintype "passive"))
      (node (ref "SV7") (pin "9") (pinfunction "9_9") (pintype "passive"))
    )
    (net (code "507") (name "Net-(SV7-Pad10)") (class "Default")
      (node (ref "SV7") (pin "10") (pinfunction "10_10") (pintype "passive"))
      (node (ref "SV7") (pin "2") (pinfunction "2_2") (pintype "passive"))
      (node (ref "SV7") (pin "4") (pinfunction "4_4") (pintype "passive"))
      (node (ref "SV7") (pin "6") (pinfunction "6_6") (pintype "passive"))
      (node (ref "SV7") (pin "8") (pinfunction "8_8") (pintype "passive"))
    )
    (net (code "508") (name "Net-(SV8-Pad1)") (class "Default")
      (node (ref "SV8") (pin "1") (pinfunction "1_1") (pintype "passive"))
      (node (ref "SV8") (pin "3") (pinfunction "3_3") (pintype "passive"))
      (node (ref "SV8") (pin "5") (pinfunction "5_5") (pintype "passive"))
      (node (ref "SV8") (pin "7") (pinfunction "7_7") (pintype "passive"))
      (node (ref "SV8") (pin "9") (pinfunction "9_9") (pintype "passive"))
    )
    (net (code "509") (name "Net-(SV8-Pad10)") (class "Default")
      (node (ref "SV8") (pin "10") (pinfunction "10_10") (pintype "passive"))
      (node (ref "SV8") (pin "2") (pinfunction "2_2") (pintype "passive"))
      (node (ref "SV8") (pin "4") (pinfunction "4_4") (pintype "passive"))
      (node (ref "SV8") (pin "6") (pinfunction "6_6") (pintype "passive"))
      (node (ref "SV8") (pin "8") (pinfunction "8_8") (pintype "passive"))
    )
    (net (code "510") (name "Net-(SV13-Pad1)") (class "Default")
      (node (ref "SV13") (pin "1") (pinfunction "1_1") (pintype "passive"))
      (node (ref "SV13") (pin "3") (pinfunction "3_3") (pintype "passive"))
      (node (ref "SV13") (pin "5") (pinfunction "5_5") (pintype "passive"))
      (node (ref "SV13") (pin "7") (pinfunction "7_7") (pintype "passive"))
      (node (ref "SV13") (pin "9") (pinfunction "9_9") (pintype "passive"))
    )
    (net (code "511") (name "Net-(SV13-Pad10)") (class "Default")
      (node (ref "SV13") (pin "10") (pinfunction "10_10") (pintype "passive"))
      (node (ref "SV13") (pin "2") (pinfunction "2_2") (pintype "passive"))
      (node (ref "SV13") (pin "4") (pinfunction "4_4") (pintype "passive"))
      (node (ref "SV13") (pin "6") (pinfunction "6_6") (pintype "passive"))
      (node (ref "SV13") (pin "8") (pinfunction "8_8") (pintype "passive"))
    )
    (net (code "512") (name "Net-(SV14-Pad1)") (class "Default")
      (node (ref "SV14") (pin "1") (pinfunction "1_1") (pintype "passive"))
      (node (ref "SV14") (pin "3") (pinfunction "3_3") (pintype "passive"))
      (node (ref "SV14") (pin "5") (pinfunction "5_5") (pintype "passive"))
      (node (ref "SV14") (pin "7") (pinfunction "7_7") (pintype "passive"))
      (node (ref "SV14") (pin "9") (pinfunction "9_9") (pintype "passive"))
    )
    (net (code "513") (name "Net-(SV14-Pad10)") (class "Default")
      (node (ref "SV14") (pin "10") (pinfunction "10_10") (pintype "passive"))
      (node (ref "SV14") (pin "2") (pinfunction "2_2") (pintype "passive"))
      (node (ref "SV14") (pin "4") (pinfunction "4_4") (pintype "passive"))
      (node (ref "SV14") (pin "6") (pinfunction "6_6") (pintype "passive"))
      (node (ref "SV14") (pin "8") (pinfunction "8_8") (pintype "passive"))
    )
    (net (code "514") (name "Net-(SV15-Pad1)") (class "Default")
      (node (ref "SV15") (pin "1") (pinfunction "1_1") (pintype "passive"))
      (node (ref "SV15") (pin "3") (pinfunction "3_3") (pintype "passive"))
      (node (ref "SV15") (pin "5") (pinfunction "5_5") (pintype "passive"))
      (node (ref "SV15") (pin "7") (pinfunction "7_7") (pintype "passive"))
      (node (ref "SV15") (pin "9") (pinfunction "9_9") (pintype "passive"))
    )
    (net (code "515") (name "Net-(SV15-Pad10)") (class "Default")
      (node (ref "SV15") (pin "10") (pinfunction "10_10") (pintype "passive"))
      (node (ref "SV15") (pin "2") (pinfunction "2_2") (pintype "passive"))
      (node (ref "SV15") (pin "4") (pinfunction "4_4") (pintype "passive"))
      (node (ref "SV15") (pin "6") (pinfunction "6_6") (pintype "passive"))
      (node (ref "SV15") (pin "8") (pinfunction "8_8") (pintype "passive"))
    )
    (net (code "516") (name "Net-(SV16-Pad1)") (class "Default")
      (node (ref "SV16") (pin "1") (pinfunction "1_1") (pintype "passive"))
      (node (ref "SV16") (pin "3") (pinfunction "3_3") (pintype "passive"))
      (node (ref "SV16") (pin "5") (pinfunction "5_5") (pintype "passive"))
      (node (ref "SV16") (pin "7") (pinfunction "7_7") (pintype "passive"))
      (node (ref "SV16") (pin "9") (pinfunction "9_9") (pintype "passive"))
    )
    (net (code "517") (name "Net-(SV16-Pad10)") (class "Default")
      (node (ref "SV16") (pin "10") (pinfunction "10_10") (pintype "passive"))
      (node (ref "SV16") (pin "2") (pinfunction "2_2") (pintype "passive"))
      (node (ref "SV16") (pin "4") (pinfunction "4_4") (pintype "passive"))
      (node (ref "SV16") (pin "6") (pinfunction "6_6") (pintype "passive"))
      (node (ref "SV16") (pin "8") (pinfunction "8_8") (pintype "passive"))
    )
    (net (code "518") (name "Net-(SV17-Pad1)") (class "Default")
      (node (ref "SV17") (pin "1") (pinfunction "1_1") (pintype "passive"))
      (node (ref "SV17") (pin "3") (pinfunction "3_3") (pintype "passive"))
      (node (ref "SV17") (pin "5") (pinfunction "5_5") (pintype "passive"))
      (node (ref "SV17") (pin "7") (pinfunction "7_7") (pintype "passive"))
      (node (ref "SV17") (pin "9") (pinfunction "9_9") (pintype "passive"))
    )
    (net (code "519") (name "Net-(SV17-Pad10)") (class "Default")
      (node (ref "SV17") (pin "10") (pinfunction "10_10") (pintype "passive"))
      (node (ref "SV17") (pin "2") (pinfunction "2_2") (pintype "passive"))
      (node (ref "SV17") (pin "4") (pinfunction "4_4") (pintype "passive"))
      (node (ref "SV17") (pin "6") (pinfunction "6_6") (pintype "passive"))
      (node (ref "SV17") (pin "8") (pinfunction "8_8") (pintype "passive"))
    )
    (net (code "520") (name "Net-(SV18-Pad1)") (class "Default")
      (node (ref "SV18") (pin "1") (pinfunction "1_1") (pintype "passive"))
      (node (ref "SV18") (pin "3") (pinfunction "3_3") (pintype "passive"))
      (node (ref "SV18") (pin "5") (pinfunction "5_5") (pintype "passive"))
      (node (ref "SV18") (pin "7") (pinfunction "7_7") (pintype "passive"))
      (node (ref "SV18") (pin "9") (pinfunction "9_9") (pintype "passive"))
    )
    (net (code "521") (name "Net-(SV18-Pad10)") (class "Default")
      (node (ref "SV18") (pin "10") (pinfunction "10_10") (pintype "passive"))
      (node (ref "SV18") (pin "2") (pinfunction "2_2") (pintype "passive"))
      (node (ref "SV18") (pin "4") (pinfunction "4_4") (pintype "passive"))
      (node (ref "SV18") (pin "6") (pinfunction "6_6") (pintype "passive"))
      (node (ref "SV18") (pin "8") (pinfunction "8_8") (pintype "passive"))
    )
    (net (code "522") (name "Net-(SV19-Pad1)") (class "Default")
      (node (ref "SV19") (pin "1") (pinfunction "1_1") (pintype "passive"))
      (node (ref "SV19") (pin "3") (pinfunction "3_3") (pintype "passive"))
      (node (ref "SV19") (pin "5") (pinfunction "5_5") (pintype "passive"))
      (node (ref "SV19") (pin "7") (pinfunction "7_7") (pintype "passive"))
      (node (ref "SV19") (pin "9") (pinfunction "9_9") (pintype "passive"))
    )
    (net (code "523") (name "Net-(SV19-Pad10)") (class "Default")
      (node (ref "SV19") (pin "10") (pinfunction "10_10") (pintype "passive"))
      (node (ref "SV19") (pin "2") (pinfunction "2_2") (pintype "passive"))
      (node (ref "SV19") (pin "4") (pinfunction "4_4") (pintype "passive"))
      (node (ref "SV19") (pin "6") (pinfunction "6_6") (pintype "passive"))
      (node (ref "SV19") (pin "8") (pinfunction "8_8") (pintype "passive"))
    )
    (net (code "524") (name "Net-(SV20-Pad1)") (class "Default")
      (node (ref "SV20") (pin "1") (pinfunction "1_1") (pintype "passive"))
      (node (ref "SV20") (pin "3") (pinfunction "3_3") (pintype "passive"))
      (node (ref "SV20") (pin "5") (pinfunction "5_5") (pintype "passive"))
      (node (ref "SV20") (pin "7") (pinfunction "7_7") (pintype "passive"))
      (node (ref "SV20") (pin "9") (pinfunction "9_9") (pintype "passive"))
    )
    (net (code "525") (name "Net-(SV20-Pad10)") (class "Default")
      (node (ref "SV20") (pin "10") (pinfunction "10_10") (pintype "passive"))
      (node (ref "SV20") (pin "2") (pinfunction "2_2") (pintype "passive"))
      (node (ref "SV20") (pin "4") (pinfunction "4_4") (pintype "passive"))
      (node (ref "SV20") (pin "6") (pinfunction "6_6") (pintype "passive"))
      (node (ref "SV20") (pin "8") (pinfunction "8_8") (pintype "passive"))
    )
    (net (code "526") (name "Net-(SV21-Pad1)") (class "Default")
      (node (ref "SV21") (pin "1") (pinfunction "1_1") (pintype "passive"))
      (node (ref "SV21") (pin "3") (pinfunction "3_3") (pintype "passive"))
      (node (ref "SV21") (pin "5") (pinfunction "5_5") (pintype "passive"))
      (node (ref "SV21") (pin "7") (pinfunction "7_7") (pintype "passive"))
      (node (ref "SV21") (pin "9") (pinfunction "9_9") (pintype "passive"))
    )
    (net (code "527") (name "Net-(SV21-Pad10)") (class "Default")
      (node (ref "SV21") (pin "10") (pinfunction "10_10") (pintype "passive"))
      (node (ref "SV21") (pin "2") (pinfunction "2_2") (pintype "passive"))
      (node (ref "SV21") (pin "4") (pinfunction "4_4") (pintype "passive"))
      (node (ref "SV21") (pin "6") (pinfunction "6_6") (pintype "passive"))
      (node (ref "SV21") (pin "8") (pinfunction "8_8") (pintype "passive"))
    )
    (net (code "528") (name "Net-(SV22-Pad1)") (class "Default")
      (node (ref "SV22") (pin "1") (pinfunction "1_1") (pintype "passive"))
      (node (ref "SV22") (pin "3") (pinfunction "3_3") (pintype "passive"))
      (node (ref "SV22") (pin "5") (pinfunction "5_5") (pintype "passive"))
      (node (ref "SV22") (pin "7") (pinfunction "7_7") (pintype "passive"))
      (node (ref "SV22") (pin "9") (pinfunction "9_9") (pintype "passive"))
    )
    (net (code "529") (name "Net-(SV22-Pad10)") (class "Default")
      (node (ref "SV22") (pin "10") (pinfunction "10_10") (pintype "passive"))
      (node (ref "SV22") (pin "2") (pinfunction "2_2") (pintype "passive"))
      (node (ref "SV22") (pin "4") (pinfunction "4_4") (pintype "passive"))
      (node (ref "SV22") (pin "6") (pinfunction "6_6") (pintype "passive"))
      (node (ref "SV22") (pin "8") (pinfunction "8_8") (pintype "passive"))
    )
    (net (code "530") (name "Net-(SV23-Pad1)") (class "Default")
      (node (ref "SV23") (pin "1") (pinfunction "1_1") (pintype "passive"))
      (node (ref "SV23") (pin "3") (pinfunction "3_3") (pintype "passive"))
      (node (ref "SV23") (pin "5") (pinfunction "5_5") (pintype "passive"))
      (node (ref "SV23") (pin "7") (pinfunction "7_7") (pintype "passive"))
      (node (ref "SV23") (pin "9") (pinfunction "9_9") (pintype "passive"))
    )
    (net (code "531") (name "Net-(SV23-Pad10)") (class "Default")
      (node (ref "SV23") (pin "10") (pinfunction "10_10") (pintype "passive"))
      (node (ref "SV23") (pin "2") (pinfunction "2_2") (pintype "passive"))
      (node (ref "SV23") (pin "4") (pinfunction "4_4") (pintype "passive"))
      (node (ref "SV23") (pin "6") (pinfunction "6_6") (pintype "passive"))
      (node (ref "SV23") (pin "8") (pinfunction "8_8") (pintype "passive"))
    )
    (net (code "532") (name "Net-(SV24-Pad1)") (class "Default")
      (node (ref "SV24") (pin "1") (pinfunction "1_1") (pintype "passive"))
      (node (ref "SV24") (pin "3") (pinfunction "3_3") (pintype "passive"))
      (node (ref "SV24") (pin "5") (pinfunction "5_5") (pintype "passive"))
      (node (ref "SV24") (pin "7") (pinfunction "7_7") (pintype "passive"))
      (node (ref "SV24") (pin "9") (pinfunction "9_9") (pintype "passive"))
    )
    (net (code "533") (name "Net-(SV24-Pad10)") (class "Default")
      (node (ref "SV24") (pin "10") (pinfunction "10_10") (pintype "passive"))
      (node (ref "SV24") (pin "2") (pinfunction "2_2") (pintype "passive"))
      (node (ref "SV24") (pin "4") (pinfunction "4_4") (pintype "passive"))
      (node (ref "SV24") (pin "6") (pinfunction "6_6") (pintype "passive"))
      (node (ref "SV24") (pin "8") (pinfunction "8_8") (pintype "passive"))
    )
    (net (code "534") (name "Net-(SV25-Pad1)") (class "Default")
      (node (ref "SV25") (pin "1") (pinfunction "1_1") (pintype "passive"))
      (node (ref "SV25") (pin "3") (pinfunction "3_3") (pintype "passive"))
      (node (ref "SV25") (pin "5") (pinfunction "5_5") (pintype "passive"))
      (node (ref "SV25") (pin "7") (pinfunction "7_7") (pintype "passive"))
      (node (ref "SV25") (pin "9") (pinfunction "9_9") (pintype "passive"))
    )
    (net (code "535") (name "Net-(SV25-Pad10)") (class "Default")
      (node (ref "SV25") (pin "10") (pinfunction "10_10") (pintype "passive"))
      (node (ref "SV25") (pin "2") (pinfunction "2_2") (pintype "passive"))
      (node (ref "SV25") (pin "4") (pinfunction "4_4") (pintype "passive"))
      (node (ref "SV25") (pin "6") (pinfunction "6_6") (pintype "passive"))
      (node (ref "SV25") (pin "8") (pinfunction "8_8") (pintype "passive"))
    )
    (net (code "536") (name "Net-(SV26-Pad1)") (class "Default")
      (node (ref "SV26") (pin "1") (pinfunction "1_1") (pintype "passive"))
      (node (ref "SV26") (pin "3") (pinfunction "3_3") (pintype "passive"))
      (node (ref "SV26") (pin "5") (pinfunction "5_5") (pintype "passive"))
      (node (ref "SV26") (pin "7") (pinfunction "7_7") (pintype "passive"))
      (node (ref "SV26") (pin "9") (pinfunction "9_9") (pintype "passive"))
    )
    (net (code "537") (name "Net-(SV26-Pad10)") (class "Default")
      (node (ref "SV26") (pin "10") (pinfunction "10_10") (pintype "passive"))
      (node (ref "SV26") (pin "2") (pinfunction "2_2") (pintype "passive"))
      (node (ref "SV26") (pin "4") (pinfunction "4_4") (pintype "passive"))
      (node (ref "SV26") (pin "6") (pinfunction "6_6") (pintype "passive"))
      (node (ref "SV26") (pin "8") (pinfunction "8_8") (pintype "passive"))
    )
    (net (code "538") (name "Net-(SV27-Pad1)") (class "Default")
      (node (ref "SV27") (pin "1") (pinfunction "1_1") (pintype "passive"))
      (node (ref "SV27") (pin "3") (pinfunction "3_3") (pintype "passive"))
      (node (ref "SV27") (pin "5") (pinfunction "5_5") (pintype "passive"))
      (node (ref "SV27") (pin "7") (pinfunction "7_7") (pintype "passive"))
      (node (ref "SV27") (pin "9") (pinfunction "9_9") (pintype "passive"))
    )
    (net (code "539") (name "Net-(SV27-Pad10)") (class "Default")
      (node (ref "SV27") (pin "10") (pinfunction "10_10") (pintype "passive"))
      (node (ref "SV27") (pin "2") (pinfunction "2_2") (pintype "passive"))
      (node (ref "SV27") (pin "4") (pinfunction "4_4") (pintype "passive"))
      (node (ref "SV27") (pin "6") (pinfunction "6_6") (pintype "passive"))
      (node (ref "SV27") (pin "8") (pinfunction "8_8") (pintype "passive"))
    )
    (net (code "540") (name "Net-(SV28-Pad1)") (class "Default")
      (node (ref "SV28") (pin "1") (pinfunction "1_1") (pintype "passive"))
      (node (ref "SV28") (pin "3") (pinfunction "3_3") (pintype "passive"))
      (node (ref "SV28") (pin "5") (pinfunction "5_5") (pintype "passive"))
      (node (ref "SV28") (pin "7") (pinfunction "7_7") (pintype "passive"))
      (node (ref "SV28") (pin "9") (pinfunction "9_9") (pintype "passive"))
    )
    (net (code "541") (name "Net-(SV28-Pad10)") (class "Default")
      (node (ref "SV28") (pin "10") (pinfunction "10_10") (pintype "passive"))
      (node (ref "SV28") (pin "2") (pinfunction "2_2") (pintype "passive"))
      (node (ref "SV28") (pin "4") (pinfunction "4_4") (pintype "passive"))
      (node (ref "SV28") (pin "6") (pinfunction "6_6") (pintype "passive"))
      (node (ref "SV28") (pin "8") (pinfunction "8_8") (pintype "passive"))
    )
    (net (code "542") (name "Net-(SV29-Pad1)") (class "Default")
      (node (ref "SV29") (pin "1") (pinfunction "1_1") (pintype "passive"))
      (node (ref "SV29") (pin "3") (pinfunction "3_3") (pintype "passive"))
      (node (ref "SV29") (pin "5") (pinfunction "5_5") (pintype "passive"))
      (node (ref "SV29") (pin "7") (pinfunction "7_7") (pintype "passive"))
      (node (ref "SV29") (pin "9") (pinfunction "9_9") (pintype "passive"))
    )
    (net (code "543") (name "Net-(SV29-Pad10)") (class "Default")
      (node (ref "SV29") (pin "10") (pinfunction "10_10") (pintype "passive"))
      (node (ref "SV29") (pin "2") (pinfunction "2_2") (pintype "passive"))
      (node (ref "SV29") (pin "4") (pinfunction "4_4") (pintype "passive"))
      (node (ref "SV29") (pin "6") (pinfunction "6_6") (pintype "passive"))
      (node (ref "SV29") (pin "8") (pinfunction "8_8") (pintype "passive"))
    )
    (net (code "544") (name "Net-(SV30-Pad1)") (class "Default")
      (node (ref "SV30") (pin "1") (pinfunction "1_1") (pintype "passive"))
      (node (ref "SV30") (pin "3") (pinfunction "3_3") (pintype "passive"))
      (node (ref "SV30") (pin "5") (pinfunction "5_5") (pintype "passive"))
      (node (ref "SV30") (pin "7") (pinfunction "7_7") (pintype "passive"))
      (node (ref "SV30") (pin "9") (pinfunction "9_9") (pintype "passive"))
    )
    (net (code "545") (name "Net-(SV30-Pad10)") (class "Default")
      (node (ref "SV30") (pin "10") (pinfunction "10_10") (pintype "passive"))
      (node (ref "SV30") (pin "2") (pinfunction "2_2") (pintype "passive"))
      (node (ref "SV30") (pin "4") (pinfunction "4_4") (pintype "passive"))
      (node (ref "SV30") (pin "6") (pinfunction "6_6") (pintype "passive"))
      (node (ref "SV30") (pin "8") (pinfunction "8_8") (pintype "passive"))
    )
    (net (code "546") (name "Net-(SV31-Pad1)") (class "Default")
      (node (ref "SV31") (pin "1") (pinfunction "1_1") (pintype "passive"))
      (node (ref "SV31") (pin "3") (pinfunction "3_3") (pintype "passive"))
      (node (ref "SV31") (pin "5") (pinfunction "5_5") (pintype "passive"))
      (node (ref "SV31") (pin "7") (pinfunction "7_7") (pintype "passive"))
      (node (ref "SV31") (pin "9") (pinfunction "9_9") (pintype "passive"))
    )
    (net (code "547") (name "Net-(SV31-Pad10)") (class "Default")
      (node (ref "SV31") (pin "10") (pinfunction "10_10") (pintype "passive"))
      (node (ref "SV31") (pin "2") (pinfunction "2_2") (pintype "passive"))
      (node (ref "SV31") (pin "4") (pinfunction "4_4") (pintype "passive"))
      (node (ref "SV31") (pin "6") (pinfunction "6_6") (pintype "passive"))
      (node (ref "SV31") (pin "8") (pinfunction "8_8") (pintype "passive"))
    )
    (net (code "548") (name "Net-(SV32-Pad1)") (class "Default")
      (node (ref "SV32") (pin "1") (pinfunction "1_1") (pintype "passive"))
      (node (ref "SV32") (pin "3") (pinfunction "3_3") (pintype "passive"))
      (node (ref "SV32") (pin "5") (pinfunction "5_5") (pintype "passive"))
      (node (ref "SV32") (pin "7") (pinfunction "7_7") (pintype "passive"))
      (node (ref "SV32") (pin "9") (pinfunction "9_9") (pintype "passive"))
    )
    (net (code "549") (name "Net-(SV32-Pad10)") (class "Default")
      (node (ref "SV32") (pin "10") (pinfunction "10_10") (pintype "passive"))
      (node (ref "SV32") (pin "2") (pinfunction "2_2") (pintype "passive"))
      (node (ref "SV32") (pin "4") (pinfunction "4_4") (pintype "passive"))
      (node (ref "SV32") (pin "6") (pinfunction "6_6") (pintype "passive"))
      (node (ref "SV32") (pin "8") (pinfunction "8_8") (pintype "passive"))
    )
    (net (code "550") (name "Net-(SV33-Pad1)") (class "Default")
      (node (ref "SV33") (pin "1") (pinfunction "1_1") (pintype "passive"))
      (node (ref "SV33") (pin "3") (pinfunction "3_3") (pintype "passive"))
      (node (ref "SV33") (pin "5") (pinfunction "5_5") (pintype "passive"))
      (node (ref "SV33") (pin "7") (pinfunction "7_7") (pintype "passive"))
      (node (ref "SV33") (pin "9") (pinfunction "9_9") (pintype "passive"))
    )
    (net (code "551") (name "Net-(SV33-Pad10)") (class "Default")
      (node (ref "SV33") (pin "10") (pinfunction "10_10") (pintype "passive"))
      (node (ref "SV33") (pin "2") (pinfunction "2_2") (pintype "passive"))
      (node (ref "SV33") (pin "4") (pinfunction "4_4") (pintype "passive"))
      (node (ref "SV33") (pin "6") (pinfunction "6_6") (pintype "passive"))
      (node (ref "SV33") (pin "8") (pinfunction "8_8") (pintype "passive"))
    )
    (net (code "552") (name "Net-(SV34-Pad1)") (class "Default")
      (node (ref "SV34") (pin "1") (pinfunction "1_1") (pintype "passive"))
      (node (ref "SV34") (pin "3") (pinfunction "3_3") (pintype "passive"))
      (node (ref "SV34") (pin "5") (pinfunction "5_5") (pintype "passive"))
      (node (ref "SV34") (pin "7") (pinfunction "7_7") (pintype "passive"))
      (node (ref "SV34") (pin "9") (pinfunction "9_9") (pintype "passive"))
    )
    (net (code "553") (name "Net-(SV34-Pad10)") (class "Default")
      (node (ref "SV34") (pin "10") (pinfunction "10_10") (pintype "passive"))
      (node (ref "SV34") (pin "2") (pinfunction "2_2") (pintype "passive"))
      (node (ref "SV34") (pin "4") (pinfunction "4_4") (pintype "passive"))
      (node (ref "SV34") (pin "6") (pinfunction "6_6") (pintype "passive"))
      (node (ref "SV34") (pin "8") (pinfunction "8_8") (pintype "passive"))
    )
    (net (code "554") (name "Net-(SV35-Pad1)") (class "Default")
      (node (ref "SV35") (pin "1") (pinfunction "1_1") (pintype "passive"))
      (node (ref "SV35") (pin "3") (pinfunction "3_3") (pintype "passive"))
      (node (ref "SV35") (pin "5") (pinfunction "5_5") (pintype "passive"))
      (node (ref "SV35") (pin "7") (pinfunction "7_7") (pintype "passive"))
      (node (ref "SV35") (pin "9") (pinfunction "9_9") (pintype "passive"))
    )
    (net (code "555") (name "Net-(SV35-Pad10)") (class "Default")
      (node (ref "SV35") (pin "10") (pinfunction "10_10") (pintype "passive"))
      (node (ref "SV35") (pin "2") (pinfunction "2_2") (pintype "passive"))
      (node (ref "SV35") (pin "4") (pinfunction "4_4") (pintype "passive"))
      (node (ref "SV35") (pin "6") (pinfunction "6_6") (pintype "passive"))
      (node (ref "SV35") (pin "8") (pinfunction "8_8") (pintype "passive"))
    )
    (net (code "556") (name "Net-(SV36-Pad1)") (class "Default")
      (node (ref "SV36") (pin "1") (pinfunction "1_1") (pintype "passive"))
      (node (ref "SV36") (pin "3") (pinfunction "3_3") (pintype "passive"))
      (node (ref "SV36") (pin "5") (pinfunction "5_5") (pintype "passive"))
      (node (ref "SV36") (pin "7") (pinfunction "7_7") (pintype "passive"))
      (node (ref "SV36") (pin "9") (pinfunction "9_9") (pintype "passive"))
    )
    (net (code "557") (name "Net-(SV36-Pad10)") (class "Default")
      (node (ref "SV36") (pin "10") (pinfunction "10_10") (pintype "passive"))
      (node (ref "SV36") (pin "2") (pinfunction "2_2") (pintype "passive"))
      (node (ref "SV36") (pin "4") (pinfunction "4_4") (pintype "passive"))
      (node (ref "SV36") (pin "6") (pinfunction "6_6") (pintype "passive"))
      (node (ref "SV36") (pin "8") (pinfunction "8_8") (pintype "passive"))
    )
    (net (code "558") (name "Net-(SV37-Pad1)") (class "Default")
      (node (ref "SV37") (pin "1") (pinfunction "1_1") (pintype "passive"))
      (node (ref "SV37") (pin "3") (pinfunction "3_3") (pintype "passive"))
      (node (ref "SV37") (pin "5") (pinfunction "5_5") (pintype "passive"))
      (node (ref "SV37") (pin "7") (pinfunction "7_7") (pintype "passive"))
      (node (ref "SV37") (pin "9") (pinfunction "9_9") (pintype "passive"))
    )
    (net (code "559") (name "Net-(SV37-Pad10)") (class "Default")
      (node (ref "SV37") (pin "10") (pinfunction "10_10") (pintype "passive"))
      (node (ref "SV37") (pin "2") (pinfunction "2_2") (pintype "passive"))
      (node (ref "SV37") (pin "4") (pinfunction "4_4") (pintype "passive"))
      (node (ref "SV37") (pin "6") (pinfunction "6_6") (pintype "passive"))
      (node (ref "SV37") (pin "8") (pinfunction "8_8") (pintype "passive"))
    )
    (net (code "560") (name "Net-(SV38-Pad1)") (class "Default")
      (node (ref "SV38") (pin "1") (pinfunction "1_1") (pintype "passive"))
      (node (ref "SV38") (pin "3") (pinfunction "3_3") (pintype "passive"))
      (node (ref "SV38") (pin "5") (pinfunction "5_5") (pintype "passive"))
      (node (ref "SV38") (pin "7") (pinfunction "7_7") (pintype "passive"))
      (node (ref "SV38") (pin "9") (pinfunction "9_9") (pintype "passive"))
    )
    (net (code "561") (name "Net-(SV38-Pad10)") (class "Default")
      (node (ref "SV38") (pin "10") (pinfunction "10_10") (pintype "passive"))
      (node (ref "SV38") (pin "2") (pinfunction "2_2") (pintype "passive"))
      (node (ref "SV38") (pin "4") (pinfunction "4_4") (pintype "passive"))
      (node (ref "SV38") (pin "6") (pinfunction "6_6") (pintype "passive"))
      (node (ref "SV38") (pin "8") (pinfunction "8_8") (pintype "passive"))
    )
    (net (code "562") (name "Net-(SV39-Pad1)") (class "Default")
      (node (ref "SV39") (pin "1") (pinfunction "1_1") (pintype "passive"))
      (node (ref "SV39") (pin "3") (pinfunction "3_3") (pintype "passive"))
      (node (ref "SV39") (pin "5") (pinfunction "5_5") (pintype "passive"))
      (node (ref "SV39") (pin "7") (pinfunction "7_7") (pintype "passive"))
      (node (ref "SV39") (pin "9") (pinfunction "9_9") (pintype "passive"))
    )
    (net (code "563") (name "Net-(SV39-Pad10)") (class "Default")
      (node (ref "SV39") (pin "10") (pinfunction "10_10") (pintype "passive"))
      (node (ref "SV39") (pin "2") (pinfunction "2_2") (pintype "passive"))
      (node (ref "SV39") (pin "4") (pinfunction "4_4") (pintype "passive"))
      (node (ref "SV39") (pin "6") (pinfunction "6_6") (pintype "passive"))
      (node (ref "SV39") (pin "8") (pinfunction "8_8") (pintype "passive"))
    )
    (net (code "564") (name "Net-(SV40-Pad1)") (class "Default")
      (node (ref "SV40") (pin "1") (pinfunction "1_1") (pintype "passive"))
      (node (ref "SV40") (pin "3") (pinfunction "3_3") (pintype "passive"))
      (node (ref "SV40") (pin "5") (pinfunction "5_5") (pintype "passive"))
      (node (ref "SV40") (pin "7") (pinfunction "7_7") (pintype "passive"))
      (node (ref "SV40") (pin "9") (pinfunction "9_9") (pintype "passive"))
    )
    (net (code "565") (name "Net-(SV40-Pad10)") (class "Default")
      (node (ref "SV40") (pin "10") (pinfunction "10_10") (pintype "passive"))
      (node (ref "SV40") (pin "2") (pinfunction "2_2") (pintype "passive"))
      (node (ref "SV40") (pin "4") (pinfunction "4_4") (pintype "passive"))
      (node (ref "SV40") (pin "6") (pinfunction "6_6") (pintype "passive"))
      (node (ref "SV40") (pin "8") (pinfunction "8_8") (pintype "passive"))
    )
    (net (code "566") (name "Net-(SV41-Pad1)") (class "Default")
      (node (ref "SV41") (pin "1") (pinfunction "1_1") (pintype "passive"))
      (node (ref "SV41") (pin "3") (pinfunction "3_3") (pintype "passive"))
      (node (ref "SV41") (pin "5") (pinfunction "5_5") (pintype "passive"))
      (node (ref "SV41") (pin "7") (pinfunction "7_7") (pintype "passive"))
      (node (ref "SV41") (pin "9") (pinfunction "9_9") (pintype "passive"))
    )
    (net (code "567") (name "Net-(SV41-Pad10)") (class "Default")
      (node (ref "SV41") (pin "10") (pinfunction "10_10") (pintype "passive"))
      (node (ref "SV41") (pin "2") (pinfunction "2_2") (pintype "passive"))
      (node (ref "SV41") (pin "4") (pinfunction "4_4") (pintype "passive"))
      (node (ref "SV41") (pin "6") (pinfunction "6_6") (pintype "passive"))
      (node (ref "SV41") (pin "8") (pinfunction "8_8") (pintype "passive"))
    )
    (net (code "568") (name "Net-(SV42-Pad1)") (class "Default")
      (node (ref "SV42") (pin "1") (pinfunction "1_1") (pintype "passive"))
      (node (ref "SV42") (pin "3") (pinfunction "3_3") (pintype "passive"))
      (node (ref "SV42") (pin "5") (pinfunction "5_5") (pintype "passive"))
      (node (ref "SV42") (pin "7") (pinfunction "7_7") (pintype "passive"))
      (node (ref "SV42") (pin "9") (pinfunction "9_9") (pintype "passive"))
    )
    (net (code "569") (name "Net-(SV42-Pad10)") (class "Default")
      (node (ref "SV42") (pin "10") (pinfunction "10_10") (pintype "passive"))
      (node (ref "SV42") (pin "2") (pinfunction "2_2") (pintype "passive"))
      (node (ref "SV42") (pin "4") (pinfunction "4_4") (pintype "passive"))
      (node (ref "SV42") (pin "6") (pinfunction "6_6") (pintype "passive"))
      (node (ref "SV42") (pin "8") (pinfunction "8_8") (pintype "passive"))
    )
    (net (code "570") (name "Net-(SV43-Pad1)") (class "Default")
      (node (ref "SV43") (pin "1") (pinfunction "1_1") (pintype "passive"))
      (node (ref "SV43") (pin "3") (pinfunction "3_3") (pintype "passive"))
      (node (ref "SV43") (pin "5") (pinfunction "5_5") (pintype "passive"))
      (node (ref "SV43") (pin "7") (pinfunction "7_7") (pintype "passive"))
      (node (ref "SV43") (pin "9") (pinfunction "9_9") (pintype "passive"))
    )
    (net (code "571") (name "Net-(SV43-Pad10)") (class "Default")
      (node (ref "SV43") (pin "10") (pinfunction "10_10") (pintype "passive"))
      (node (ref "SV43") (pin "2") (pinfunction "2_2") (pintype "passive"))
      (node (ref "SV43") (pin "4") (pinfunction "4_4") (pintype "passive"))
      (node (ref "SV43") (pin "6") (pinfunction "6_6") (pintype "passive"))
      (node (ref "SV43") (pin "8") (pinfunction "8_8") (pintype "passive"))
    )
    (net (code "572") (name "Net-(SV44-Pad1)") (class "Default")
      (node (ref "SV44") (pin "1") (pinfunction "1_1") (pintype "passive"))
      (node (ref "SV44") (pin "3") (pinfunction "3_3") (pintype "passive"))
      (node (ref "SV44") (pin "5") (pinfunction "5_5") (pintype "passive"))
      (node (ref "SV44") (pin "7") (pinfunction "7_7") (pintype "passive"))
      (node (ref "SV44") (pin "9") (pinfunction "9_9") (pintype "passive"))
    )
    (net (code "573") (name "Net-(SV44-Pad10)") (class "Default")
      (node (ref "SV44") (pin "10") (pinfunction "10_10") (pintype "passive"))
      (node (ref "SV44") (pin "2") (pinfunction "2_2") (pintype "passive"))
      (node (ref "SV44") (pin "4") (pinfunction "4_4") (pintype "passive"))
      (node (ref "SV44") (pin "6") (pinfunction "6_6") (pintype "passive"))
      (node (ref "SV44") (pin "8") (pinfunction "8_8") (pintype "passive"))
    )
    (net (code "574") (name "Net-(SV45-Pad1)") (class "Default")
      (node (ref "SV45") (pin "1") (pinfunction "1_1") (pintype "passive"))
      (node (ref "SV45") (pin "3") (pinfunction "3_3") (pintype "passive"))
      (node (ref "SV45") (pin "5") (pinfunction "5_5") (pintype "passive"))
      (node (ref "SV45") (pin "7") (pinfunction "7_7") (pintype "passive"))
      (node (ref "SV45") (pin "9") (pinfunction "9_9") (pintype "passive"))
    )
    (net (code "575") (name "Net-(SV45-Pad10)") (class "Default")
      (node (ref "SV45") (pin "10") (pinfunction "10_10") (pintype "passive"))
      (node (ref "SV45") (pin "2") (pinfunction "2_2") (pintype "passive"))
      (node (ref "SV45") (pin "4") (pinfunction "4_4") (pintype "passive"))
      (node (ref "SV45") (pin "6") (pinfunction "6_6") (pintype "passive"))
      (node (ref "SV45") (pin "8") (pinfunction "8_8") (pintype "passive"))
    )
    (net (code "576") (name "Net-(SV46-Pad1)") (class "Default")
      (node (ref "SV46") (pin "1") (pinfunction "1_1") (pintype "passive"))
      (node (ref "SV46") (pin "3") (pinfunction "3_3") (pintype "passive"))
      (node (ref "SV46") (pin "5") (pinfunction "5_5") (pintype "passive"))
      (node (ref "SV46") (pin "7") (pinfunction "7_7") (pintype "passive"))
      (node (ref "SV46") (pin "9") (pinfunction "9_9") (pintype "passive"))
    )
    (net (code "577") (name "Net-(SV46-Pad10)") (class "Default")
      (node (ref "SV46") (pin "10") (pinfunction "10_10") (pintype "passive"))
      (node (ref "SV46") (pin "2") (pinfunction "2_2") (pintype "passive"))
      (node (ref "SV46") (pin "4") (pinfunction "4_4") (pintype "passive"))
      (node (ref "SV46") (pin "6") (pinfunction "6_6") (pintype "passive"))
      (node (ref "SV46") (pin "8") (pinfunction "8_8") (pintype "passive"))
    )
    (net (code "578") (name "Net-(SV47-Pad1)") (class "Default")
      (node (ref "SV47") (pin "1") (pinfunction "1_1") (pintype "passive"))
      (node (ref "SV47") (pin "3") (pinfunction "3_3") (pintype "passive"))
      (node (ref "SV47") (pin "5") (pinfunction "5_5") (pintype "passive"))
      (node (ref "SV47") (pin "7") (pinfunction "7_7") (pintype "passive"))
      (node (ref "SV47") (pin "9") (pinfunction "9_9") (pintype "passive"))
    )
    (net (code "579") (name "Net-(SV47-Pad10)") (class "Default")
      (node (ref "SV47") (pin "10") (pinfunction "10_10") (pintype "passive"))
      (node (ref "SV47") (pin "2") (pinfunction "2_2") (pintype "passive"))
      (node (ref "SV47") (pin "4") (pinfunction "4_4") (pintype "passive"))
      (node (ref "SV47") (pin "6") (pinfunction "6_6") (pintype "passive"))
      (node (ref "SV47") (pin "8") (pinfunction "8_8") (pintype "passive"))
    )
    (net (code "580") (name "Net-(SV48-Pad1)") (class "Default")
      (node (ref "SV48") (pin "1") (pinfunction "1_1") (pintype "passive"))
      (node (ref "SV48") (pin "3") (pinfunction "3_3") (pintype "passive"))
      (node (ref "SV48") (pin "5") (pinfunction "5_5") (pintype "passive"))
      (node (ref "SV48") (pin "7") (pinfunction "7_7") (pintype "passive"))
      (node (ref "SV48") (pin "9") (pinfunction "9_9") (pintype "passive"))
    )
    (net (code "581") (name "Net-(SV48-Pad10)") (class "Default")
      (node (ref "SV48") (pin "10") (pinfunction "10_10") (pintype "passive"))
      (node (ref "SV48") (pin "2") (pinfunction "2_2") (pintype "passive"))
      (node (ref "SV48") (pin "4") (pinfunction "4_4") (pintype "passive"))
      (node (ref "SV48") (pin "6") (pinfunction "6_6") (pintype "passive"))
      (node (ref "SV48") (pin "8") (pinfunction "8_8") (pintype "passive"))
    )
    (net (code "582") (name "Net-(SV49-Pad1)") (class "Default")
      (node (ref "SV49") (pin "1") (pinfunction "1_1") (pintype "passive"))
      (node (ref "SV49") (pin "3") (pinfunction "3_3") (pintype "passive"))
      (node (ref "SV49") (pin "5") (pinfunction "5_5") (pintype "passive"))
      (node (ref "SV49") (pin "7") (pinfunction "7_7") (pintype "passive"))
      (node (ref "SV49") (pin "9") (pinfunction "9_9") (pintype "passive"))
    )
    (net (code "583") (name "Net-(SV49-Pad10)") (class "Default")
      (node (ref "SV49") (pin "10") (pinfunction "10_10") (pintype "passive"))
      (node (ref "SV49") (pin "2") (pinfunction "2_2") (pintype "passive"))
      (node (ref "SV49") (pin "4") (pinfunction "4_4") (pintype "passive"))
      (node (ref "SV49") (pin "6") (pinfunction "6_6") (pintype "passive"))
      (node (ref "SV49") (pin "8") (pinfunction "8_8") (pintype "passive"))
    )
    (net (code "584") (name "Net-(SV50-Pad1)") (class "Default")
      (node (ref "SV50") (pin "1") (pinfunction "1_1") (pintype "passive"))
      (node (ref "SV50") (pin "3") (pinfunction "3_3") (pintype "passive"))
      (node (ref "SV50") (pin "5") (pinfunction "5_5") (pintype "passive"))
      (node (ref "SV50") (pin "7") (pinfunction "7_7") (pintype "passive"))
      (node (ref "SV50") (pin "9") (pinfunction "9_9") (pintype "passive"))
    )
    (net (code "585") (name "Net-(SV50-Pad10)") (class "Default")
      (node (ref "SV50") (pin "10") (pinfunction "10_10") (pintype "passive"))
      (node (ref "SV50") (pin "2") (pinfunction "2_2") (pintype "passive"))
      (node (ref "SV50") (pin "4") (pinfunction "4_4") (pintype "passive"))
      (node (ref "SV50") (pin "6") (pinfunction "6_6") (pintype "passive"))
      (node (ref "SV50") (pin "8") (pinfunction "8_8") (pintype "passive"))
    )
    (net (code "586") (name "Net-(SV51-Pad1)") (class "Default")
      (node (ref "SV51") (pin "1") (pinfunction "1_1") (pintype "passive"))
      (node (ref "SV51") (pin "3") (pinfunction "3_3") (pintype "passive"))
      (node (ref "SV51") (pin "5") (pinfunction "5_5") (pintype "passive"))
      (node (ref "SV51") (pin "7") (pinfunction "7_7") (pintype "passive"))
      (node (ref "SV51") (pin "9") (pinfunction "9_9") (pintype "passive"))
    )
    (net (code "587") (name "Net-(SV51-Pad10)") (class "Default")
      (node (ref "SV51") (pin "10") (pinfunction "10_10") (pintype "passive"))
      (node (ref "SV51") (pin "2") (pinfunction "2_2") (pintype "passive"))
      (node (ref "SV51") (pin "4") (pinfunction "4_4") (pintype "passive"))
      (node (ref "SV51") (pin "6") (pinfunction "6_6") (pintype "passive"))
      (node (ref "SV51") (pin "8") (pinfunction "8_8") (pintype "passive"))
    )
    (net (code "588") (name "Net-(SV52-Pad1)") (class "Default")
      (node (ref "SV52") (pin "1") (pinfunction "1_1") (pintype "passive"))
      (node (ref "SV52") (pin "3") (pinfunction "3_3") (pintype "passive"))
      (node (ref "SV52") (pin "5") (pinfunction "5_5") (pintype "passive"))
      (node (ref "SV52") (pin "7") (pinfunction "7_7") (pintype "passive"))
      (node (ref "SV52") (pin "9") (pinfunction "9_9") (pintype "passive"))
    )
    (net (code "589") (name "Net-(SV52-Pad10)") (class "Default")
      (node (ref "SV52") (pin "10") (pinfunction "10_10") (pintype "passive"))
      (node (ref "SV52") (pin "2") (pinfunction "2_2") (pintype "passive"))
      (node (ref "SV52") (pin "4") (pinfunction "4_4") (pintype "passive"))
      (node (ref "SV52") (pin "6") (pinfunction "6_6") (pintype "passive"))
      (node (ref "SV52") (pin "8") (pinfunction "8_8") (pintype "passive"))
    )
    (net (code "590") (name "Net-(SV53-Pad1)") (class "Default")
      (node (ref "SV53") (pin "1") (pinfunction "1_1") (pintype "passive"))
      (node (ref "SV53") (pin "3") (pinfunction "3_3") (pintype "passive"))
      (node (ref "SV53") (pin "5") (pinfunction "5_5") (pintype "passive"))
      (node (ref "SV53") (pin "7") (pinfunction "7_7") (pintype "passive"))
      (node (ref "SV53") (pin "9") (pinfunction "9_9") (pintype "passive"))
    )
    (net (code "591") (name "Net-(SV53-Pad10)") (class "Default")
      (node (ref "SV53") (pin "10") (pinfunction "10_10") (pintype "passive"))
      (node (ref "SV53") (pin "2") (pinfunction "2_2") (pintype "passive"))
      (node (ref "SV53") (pin "4") (pinfunction "4_4") (pintype "passive"))
      (node (ref "SV53") (pin "6") (pinfunction "6_6") (pintype "passive"))
      (node (ref "SV53") (pin "8") (pinfunction "8_8") (pintype "passive"))
    )
    (net (code "592") (name "Net-(SV54-Pad1)") (class "Default")
      (node (ref "SV54") (pin "1") (pinfunction "1_1") (pintype "passive"))
      (node (ref "SV54") (pin "3") (pinfunction "3_3") (pintype "passive"))
      (node (ref "SV54") (pin "5") (pinfunction "5_5") (pintype "passive"))
      (node (ref "SV54") (pin "7") (pinfunction "7_7") (pintype "passive"))
      (node (ref "SV54") (pin "9") (pinfunction "9_9") (pintype "passive"))
    )
    (net (code "593") (name "Net-(SV54-Pad10)") (class "Default")
      (node (ref "SV54") (pin "10") (pinfunction "10_10") (pintype "passive"))
      (node (ref "SV54") (pin "2") (pinfunction "2_2") (pintype "passive"))
      (node (ref "SV54") (pin "4") (pinfunction "4_4") (pintype "passive"))
      (node (ref "SV54") (pin "6") (pinfunction "6_6") (pintype "passive"))
      (node (ref "SV54") (pin "8") (pinfunction "8_8") (pintype "passive"))
    )
    (net (code "594") (name "Net-(SV55-Pad1)") (class "Default")
      (node (ref "SV55") (pin "1") (pinfunction "1_1") (pintype "passive"))
      (node (ref "SV55") (pin "3") (pinfunction "3_3") (pintype "passive"))
      (node (ref "SV55") (pin "5") (pinfunction "5_5") (pintype "passive"))
      (node (ref "SV55") (pin "7") (pinfunction "7_7") (pintype "passive"))
      (node (ref "SV55") (pin "9") (pinfunction "9_9") (pintype "passive"))
    )
    (net (code "595") (name "Net-(SV55-Pad10)") (class "Default")
      (node (ref "SV55") (pin "10") (pinfunction "10_10") (pintype "passive"))
      (node (ref "SV55") (pin "2") (pinfunction "2_2") (pintype "passive"))
      (node (ref "SV55") (pin "4") (pinfunction "4_4") (pintype "passive"))
      (node (ref "SV55") (pin "6") (pinfunction "6_6") (pintype "passive"))
      (node (ref "SV55") (pin "8") (pinfunction "8_8") (pintype "passive"))
    )
    (net (code "596") (name "Net-(SV56-Pad1)") (class "Default")
      (node (ref "SV56") (pin "1") (pinfunction "1_1") (pintype "passive"))
      (node (ref "SV56") (pin "3") (pinfunction "3_3") (pintype "passive"))
      (node (ref "SV56") (pin "5") (pinfunction "5_5") (pintype "passive"))
      (node (ref "SV56") (pin "7") (pinfunction "7_7") (pintype "passive"))
      (node (ref "SV56") (pin "9") (pinfunction "9_9") (pintype "passive"))
    )
    (net (code "597") (name "Net-(SV56-Pad10)") (class "Default")
      (node (ref "SV56") (pin "10") (pinfunction "10_10") (pintype "passive"))
      (node (ref "SV56") (pin "2") (pinfunction "2_2") (pintype "passive"))
      (node (ref "SV56") (pin "4") (pinfunction "4_4") (pintype "passive"))
      (node (ref "SV56") (pin "6") (pinfunction "6_6") (pintype "passive"))
      (node (ref "SV56") (pin "8") (pinfunction "8_8") (pintype "passive"))
    )
    (net (code "598") (name "Net-(SV57-Pad1)") (class "Default")
      (node (ref "SV57") (pin "1") (pinfunction "1_1") (pintype "passive"))
      (node (ref "SV57") (pin "3") (pinfunction "3_3") (pintype "passive"))
      (node (ref "SV57") (pin "5") (pinfunction "5_5") (pintype "passive"))
      (node (ref "SV57") (pin "7") (pinfunction "7_7") (pintype "passive"))
      (node (ref "SV57") (pin "9") (pinfunction "9_9") (pintype "passive"))
    )
    (net (code "599") (name "Net-(SV57-Pad10)") (class "Default")
      (node (ref "SV57") (pin "10") (pinfunction "10_10") (pintype "passive"))
      (node (ref "SV57") (pin "2") (pinfunction "2_2") (pintype "passive"))
      (node (ref "SV57") (pin "4") (pinfunction "4_4") (pintype "passive"))
      (node (ref "SV57") (pin "6") (pinfunction "6_6") (pintype "passive"))
      (node (ref "SV57") (pin "8") (pinfunction "8_8") (pintype "passive"))
    )
    (net (code "600") (name "Net-(SV58-Pad1)") (class "Default")
      (node (ref "SV58") (pin "1") (pinfunction "1_1") (pintype "passive"))
      (node (ref "SV58") (pin "3") (pinfunction "3_3") (pintype "passive"))
      (node (ref "SV58") (pin "5") (pinfunction "5_5") (pintype "passive"))
      (node (ref "SV58") (pin "7") (pinfunction "7_7") (pintype "passive"))
      (node (ref "SV58") (pin "9") (pinfunction "9_9") (pintype "passive"))
    )
    (net (code "601") (name "Net-(SV58-Pad10)") (class "Default")
      (node (ref "SV58") (pin "10") (pinfunction "10_10") (pintype "passive"))
      (node (ref "SV58") (pin "2") (pinfunction "2_2") (pintype "passive"))
      (node (ref "SV58") (pin "4") (pinfunction "4_4") (pintype "passive"))
      (node (ref "SV58") (pin "6") (pinfunction "6_6") (pintype "passive"))
      (node (ref "SV58") (pin "8") (pinfunction "8_8") (pintype "passive"))
    )
    (net (code "602") (name "Net-(SV59-Pad1)") (class "Default")
      (node (ref "SV59") (pin "1") (pinfunction "1_1") (pintype "passive"))
      (node (ref "SV59") (pin "3") (pinfunction "3_3") (pintype "passive"))
      (node (ref "SV59") (pin "5") (pinfunction "5_5") (pintype "passive"))
      (node (ref "SV59") (pin "7") (pinfunction "7_7") (pintype "passive"))
      (node (ref "SV59") (pin "9") (pinfunction "9_9") (pintype "passive"))
    )
    (net (code "603") (name "Net-(SV59-Pad10)") (class "Default")
      (node (ref "SV59") (pin "10") (pinfunction "10_10") (pintype "passive"))
      (node (ref "SV59") (pin "2") (pinfunction "2_2") (pintype "passive"))
      (node (ref "SV59") (pin "4") (pinfunction "4_4") (pintype "passive"))
      (node (ref "SV59") (pin "6") (pinfunction "6_6") (pintype "passive"))
      (node (ref "SV59") (pin "8") (pinfunction "8_8") (pintype "passive"))
    )
    (net (code "604") (name "Net-(SV60-Pad1)") (class "Default")
      (node (ref "SV60") (pin "1") (pinfunction "1_1") (pintype "passive"))
      (node (ref "SV60") (pin "3") (pinfunction "3_3") (pintype "passive"))
      (node (ref "SV60") (pin "5") (pinfunction "5_5") (pintype "passive"))
      (node (ref "SV60") (pin "7") (pinfunction "7_7") (pintype "passive"))
      (node (ref "SV60") (pin "9") (pinfunction "9_9") (pintype "passive"))
    )
    (net (code "605") (name "Net-(SV60-Pad10)") (class "Default")
      (node (ref "SV60") (pin "10") (pinfunction "10_10") (pintype "passive"))
      (node (ref "SV60") (pin "2") (pinfunction "2_2") (pintype "passive"))
      (node (ref "SV60") (pin "4") (pinfunction "4_4") (pintype "passive"))
      (node (ref "SV60") (pin "6") (pinfunction "6_6") (pintype "passive"))
      (node (ref "SV60") (pin "8") (pinfunction "8_8") (pintype "passive"))
    )
    (net (code "606") (name "Net-(SV61-Pad1)") (class "Default")
      (node (ref "SV61") (pin "1") (pinfunction "1_1") (pintype "passive"))
      (node (ref "SV61") (pin "3") (pinfunction "3_3") (pintype "passive"))
      (node (ref "SV61") (pin "5") (pinfunction "5_5") (pintype "passive"))
      (node (ref "SV61") (pin "7") (pinfunction "7_7") (pintype "passive"))
      (node (ref "SV61") (pin "9") (pinfunction "9_9") (pintype "passive"))
    )
    (net (code "607") (name "Net-(SV61-Pad10)") (class "Default")
      (node (ref "SV61") (pin "10") (pinfunction "10_10") (pintype "passive"))
      (node (ref "SV61") (pin "2") (pinfunction "2_2") (pintype "passive"))
      (node (ref "SV61") (pin "4") (pinfunction "4_4") (pintype "passive"))
      (node (ref "SV61") (pin "6") (pinfunction "6_6") (pintype "passive"))
      (node (ref "SV61") (pin "8") (pinfunction "8_8") (pintype "passive"))
    )
    (net (code "608") (name "Net-(SV62-Pad1)") (class "Default")
      (node (ref "SV62") (pin "1") (pinfunction "1_1") (pintype "passive"))
      (node (ref "SV62") (pin "3") (pinfunction "3_3") (pintype "passive"))
      (node (ref "SV62") (pin "5") (pinfunction "5_5") (pintype "passive"))
      (node (ref "SV62") (pin "7") (pinfunction "7_7") (pintype "passive"))
      (node (ref "SV62") (pin "9") (pinfunction "9_9") (pintype "passive"))
    )
    (net (code "609") (name "Net-(SV62-Pad10)") (class "Default")
      (node (ref "SV62") (pin "10") (pinfunction "10_10") (pintype "passive"))
      (node (ref "SV62") (pin "2") (pinfunction "2_2") (pintype "passive"))
      (node (ref "SV62") (pin "4") (pinfunction "4_4") (pintype "passive"))
      (node (ref "SV62") (pin "6") (pinfunction "6_6") (pintype "passive"))
      (node (ref "SV62") (pin "8") (pinfunction "8_8") (pintype "passive"))
    )
    (net (code "610") (name "Net-(SV63-Pad1)") (class "Default")
      (node (ref "SV63") (pin "1") (pinfunction "1_1") (pintype "passive"))
      (node (ref "SV63") (pin "3") (pinfunction "3_3") (pintype "passive"))
      (node (ref "SV63") (pin "5") (pinfunction "5_5") (pintype "passive"))
      (node (ref "SV63") (pin "7") (pinfunction "7_7") (pintype "passive"))
      (node (ref "SV63") (pin "9") (pinfunction "9_9") (pintype "passive"))
    )
    (net (code "611") (name "Net-(SV63-Pad10)") (class "Default")
      (node (ref "SV63") (pin "10") (pinfunction "10_10") (pintype "passive"))
      (node (ref "SV63") (pin "2") (pinfunction "2_2") (pintype "passive"))
      (node (ref "SV63") (pin "4") (pinfunction "4_4") (pintype "passive"))
      (node (ref "SV63") (pin "6") (pinfunction "6_6") (pintype "passive"))
      (node (ref "SV63") (pin "8") (pinfunction "8_8") (pintype "passive"))
    )
    (net (code "612") (name "Net-(SV64-Pad1)") (class "Default")
      (node (ref "SV64") (pin "1") (pinfunction "1_1") (pintype "passive"))
      (node (ref "SV64") (pin "3") (pinfunction "3_3") (pintype "passive"))
      (node (ref "SV64") (pin "5") (pinfunction "5_5") (pintype "passive"))
      (node (ref "SV64") (pin "7") (pinfunction "7_7") (pintype "passive"))
      (node (ref "SV64") (pin "9") (pinfunction "9_9") (pintype "passive"))
    )
    (net (code "613") (name "Net-(SV64-Pad10)") (class "Default")
      (node (ref "SV64") (pin "10") (pinfunction "10_10") (pintype "passive"))
      (node (ref "SV64") (pin "2") (pinfunction "2_2") (pintype "passive"))
      (node (ref "SV64") (pin "4") (pinfunction "4_4") (pintype "passive"))
      (node (ref "SV64") (pin "6") (pinfunction "6_6") (pintype "passive"))
      (node (ref "SV64") (pin "8") (pinfunction "8_8") (pintype "passive"))
    )
    (net (code "614") (name "Net-(SV65-Pad1)") (class "Default")
      (node (ref "SV65") (pin "1") (pinfunction "1_1") (pintype "passive"))
      (node (ref "SV65") (pin "3") (pinfunction "3_3") (pintype "passive"))
      (node (ref "SV65") (pin "5") (pinfunction "5_5") (pintype "passive"))
      (node (ref "SV65") (pin "7") (pinfunction "7_7") (pintype "passive"))
      (node (ref "SV65") (pin "9") (pinfunction "9_9") (pintype "passive"))
    )
    (net (code "615") (name "Net-(SV65-Pad10)") (class "Default")
      (node (ref "SV65") (pin "10") (pinfunction "10_10") (pintype "passive"))
      (node (ref "SV65") (pin "2") (pinfunction "2_2") (pintype "passive"))
      (node (ref "SV65") (pin "4") (pinfunction "4_4") (pintype "passive"))
      (node (ref "SV65") (pin "6") (pinfunction "6_6") (pintype "passive"))
      (node (ref "SV65") (pin "8") (pinfunction "8_8") (pintype "passive"))
    )
    (net (code "616") (name "Net-(SV66-Pad1)") (class "Default")
      (node (ref "SV66") (pin "1") (pinfunction "1_1") (pintype "passive"))
      (node (ref "SV66") (pin "3") (pinfunction "3_3") (pintype "passive"))
      (node (ref "SV66") (pin "5") (pinfunction "5_5") (pintype "passive"))
      (node (ref "SV66") (pin "7") (pinfunction "7_7") (pintype "passive"))
      (node (ref "SV66") (pin "9") (pinfunction "9_9") (pintype "passive"))
    )
    (net (code "617") (name "Net-(SV66-Pad10)") (class "Default")
      (node (ref "SV66") (pin "10") (pinfunction "10_10") (pintype "passive"))
      (node (ref "SV66") (pin "2") (pinfunction "2_2") (pintype "passive"))
      (node (ref "SV66") (pin "4") (pinfunction "4_4") (pintype "passive"))
      (node (ref "SV66") (pin "6") (pinfunction "6_6") (pintype "passive"))
      (node (ref "SV66") (pin "8") (pinfunction "8_8") (pintype "passive"))
    )
    (net (code "618") (name "Net-(SV67-Pad1)") (class "Default")
      (node (ref "SV67") (pin "1") (pinfunction "1_1") (pintype "passive"))
      (node (ref "SV67") (pin "3") (pinfunction "3_3") (pintype "passive"))
      (node (ref "SV67") (pin "5") (pinfunction "5_5") (pintype "passive"))
      (node (ref "SV67") (pin "7") (pinfunction "7_7") (pintype "passive"))
      (node (ref "SV67") (pin "9") (pinfunction "9_9") (pintype "passive"))
    )
    (net (code "619") (name "Net-(SV67-Pad10)") (class "Default")
      (node (ref "SV67") (pin "10") (pinfunction "10_10") (pintype "passive"))
      (node (ref "SV67") (pin "2") (pinfunction "2_2") (pintype "passive"))
      (node (ref "SV67") (pin "4") (pinfunction "4_4") (pintype "passive"))
      (node (ref "SV67") (pin "6") (pinfunction "6_6") (pintype "passive"))
      (node (ref "SV67") (pin "8") (pinfunction "8_8") (pintype "passive"))
    )
    (net (code "620") (name "Net-(SV68-Pad1)") (class "Default")
      (node (ref "SV68") (pin "1") (pinfunction "1_1") (pintype "passive"))
      (node (ref "SV68") (pin "3") (pinfunction "3_3") (pintype "passive"))
      (node (ref "SV68") (pin "5") (pinfunction "5_5") (pintype "passive"))
      (node (ref "SV68") (pin "7") (pinfunction "7_7") (pintype "passive"))
      (node (ref "SV68") (pin "9") (pinfunction "9_9") (pintype "passive"))
    )
    (net (code "621") (name "Net-(SV68-Pad10)") (class "Default")
      (node (ref "SV68") (pin "10") (pinfunction "10_10") (pintype "passive"))
      (node (ref "SV68") (pin "2") (pinfunction "2_2") (pintype "passive"))
      (node (ref "SV68") (pin "4") (pinfunction "4_4") (pintype "passive"))
      (node (ref "SV68") (pin "6") (pinfunction "6_6") (pintype "passive"))
      (node (ref "SV68") (pin "8") (pinfunction "8_8") (pintype "passive"))
    )
    (net (code "622") (name "Net-(SV69-Pad1)") (class "Default")
      (node (ref "SV69") (pin "1") (pinfunction "1_1") (pintype "passive"))
      (node (ref "SV69") (pin "3") (pinfunction "3_3") (pintype "passive"))
      (node (ref "SV69") (pin "5") (pinfunction "5_5") (pintype "passive"))
      (node (ref "SV69") (pin "7") (pinfunction "7_7") (pintype "passive"))
      (node (ref "SV69") (pin "9") (pinfunction "9_9") (pintype "passive"))
    )
    (net (code "623") (name "Net-(SV69-Pad10)") (class "Default")
      (node (ref "SV69") (pin "10") (pinfunction "10_10") (pintype "passive"))
      (node (ref "SV69") (pin "2") (pinfunction "2_2") (pintype "passive"))
      (node (ref "SV69") (pin "4") (pinfunction "4_4") (pintype "passive"))
      (node (ref "SV69") (pin "6") (pinfunction "6_6") (pintype "passive"))
      (node (ref "SV69") (pin "8") (pinfunction "8_8") (pintype "passive"))
    )
    (net (code "624") (name "Net-(SV70-Pad1)") (class "Default")
      (node (ref "SV70") (pin "1") (pinfunction "1_1") (pintype "passive"))
      (node (ref "SV70") (pin "3") (pinfunction "3_3") (pintype "passive"))
      (node (ref "SV70") (pin "5") (pinfunction "5_5") (pintype "passive"))
      (node (ref "SV70") (pin "7") (pinfunction "7_7") (pintype "passive"))
      (node (ref "SV70") (pin "9") (pinfunction "9_9") (pintype "passive"))
    )
    (net (code "625") (name "Net-(SV70-Pad10)") (class "Default")
      (node (ref "SV70") (pin "10") (pinfunction "10_10") (pintype "passive"))
      (node (ref "SV70") (pin "2") (pinfunction "2_2") (pintype "passive"))
      (node (ref "SV70") (pin "4") (pinfunction "4_4") (pintype "passive"))
      (node (ref "SV70") (pin "6") (pinfunction "6_6") (pintype "passive"))
      (node (ref "SV70") (pin "8") (pinfunction "8_8") (pintype "passive"))
    )
    (net (code "626") (name "Net-(SV71-Pad1)") (class "Default")
      (node (ref "SV71") (pin "1") (pinfunction "1_1") (pintype "passive"))
      (node (ref "SV71") (pin "3") (pinfunction "3_3") (pintype "passive"))
      (node (ref "SV71") (pin "5") (pinfunction "5_5") (pintype "passive"))
      (node (ref "SV71") (pin "7") (pinfunction "7_7") (pintype "passive"))
      (node (ref "SV71") (pin "9") (pinfunction "9_9") (pintype "passive"))
    )
    (net (code "627") (name "Net-(SV71-Pad10)") (class "Default")
      (node (ref "SV71") (pin "10") (pinfunction "10_10") (pintype "passive"))
      (node (ref "SV71") (pin "2") (pinfunction "2_2") (pintype "passive"))
      (node (ref "SV71") (pin "4") (pinfunction "4_4") (pintype "passive"))
      (node (ref "SV71") (pin "6") (pinfunction "6_6") (pintype "passive"))
      (node (ref "SV71") (pin "8") (pinfunction "8_8") (pintype "passive"))
    )
    (net (code "628") (name "Net-(SV72-Pad1)") (class "Default")
      (node (ref "SV72") (pin "1") (pinfunction "1_1") (pintype "passive"))
      (node (ref "SV72") (pin "3") (pinfunction "3_3") (pintype "passive"))
      (node (ref "SV72") (pin "5") (pinfunction "5_5") (pintype "passive"))
      (node (ref "SV72") (pin "7") (pinfunction "7_7") (pintype "passive"))
      (node (ref "SV72") (pin "9") (pinfunction "9_9") (pintype "passive"))
    )
    (net (code "629") (name "Net-(SV72-Pad10)") (class "Default")
      (node (ref "SV72") (pin "10") (pinfunction "10_10") (pintype "passive"))
      (node (ref "SV72") (pin "2") (pinfunction "2_2") (pintype "passive"))
      (node (ref "SV72") (pin "4") (pinfunction "4_4") (pintype "passive"))
      (node (ref "SV72") (pin "6") (pinfunction "6_6") (pintype "passive"))
      (node (ref "SV72") (pin "8") (pinfunction "8_8") (pintype "passive"))
    )
    (net (code "630") (name "Net-(SV73-Pad1)") (class "Default")
      (node (ref "SV73") (pin "1") (pinfunction "1_1") (pintype "passive"))
      (node (ref "SV73") (pin "3") (pinfunction "3_3") (pintype "passive"))
      (node (ref "SV73") (pin "5") (pinfunction "5_5") (pintype "passive"))
      (node (ref "SV73") (pin "7") (pinfunction "7_7") (pintype "passive"))
      (node (ref "SV73") (pin "9") (pinfunction "9_9") (pintype "passive"))
    )
    (net (code "631") (name "Net-(SV73-Pad10)") (class "Default")
      (node (ref "SV73") (pin "10") (pinfunction "10_10") (pintype "passive"))
      (node (ref "SV73") (pin "2") (pinfunction "2_2") (pintype "passive"))
      (node (ref "SV73") (pin "4") (pinfunction "4_4") (pintype "passive"))
      (node (ref "SV73") (pin "6") (pinfunction "6_6") (pintype "passive"))
      (node (ref "SV73") (pin "8") (pinfunction "8_8") (pintype "passive"))
    )
    (net (code "632") (name "Net-(SV74-Pad1)") (class "Default")
      (node (ref "SV74") (pin "1") (pinfunction "1_1") (pintype "passive"))
      (node (ref "SV74") (pin "3") (pinfunction "3_3") (pintype "passive"))
      (node (ref "SV74") (pin "5") (pinfunction "5_5") (pintype "passive"))
      (node (ref "SV74") (pin "7") (pinfunction "7_7") (pintype "passive"))
      (node (ref "SV74") (pin "9") (pinfunction "9_9") (pintype "passive"))
    )
    (net (code "633") (name "Net-(SV74-Pad10)") (class "Default")
      (node (ref "SV74") (pin "10") (pinfunction "10_10") (pintype "passive"))
      (node (ref "SV74") (pin "2") (pinfunction "2_2") (pintype "passive"))
      (node (ref "SV74") (pin "4") (pinfunction "4_4") (pintype "passive"))
      (node (ref "SV74") (pin "6") (pinfunction "6_6") (pintype "passive"))
      (node (ref "SV74") (pin "8") (pinfunction "8_8") (pintype "passive"))
    )
    (net (code "634") (name "Net-(SV75-Pad1)") (class "Default")
      (node (ref "SV75") (pin "1") (pinfunction "1_1") (pintype "passive"))
      (node (ref "SV75") (pin "3") (pinfunction "3_3") (pintype "passive"))
      (node (ref "SV75") (pin "5") (pinfunction "5_5") (pintype "passive"))
      (node (ref "SV75") (pin "7") (pinfunction "7_7") (pintype "passive"))
      (node (ref "SV75") (pin "9") (pinfunction "9_9") (pintype "passive"))
    )
    (net (code "635") (name "Net-(SV75-Pad10)") (class "Default")
      (node (ref "SV75") (pin "10") (pinfunction "10_10") (pintype "passive"))
      (node (ref "SV75") (pin "2") (pinfunction "2_2") (pintype "passive"))
      (node (ref "SV75") (pin "4") (pinfunction "4_4") (pintype "passive"))
      (node (ref "SV75") (pin "6") (pinfunction "6_6") (pintype "passive"))
      (node (ref "SV75") (pin "8") (pinfunction "8_8") (pintype "passive"))
    )
    (net (code "636") (name "Net-(SV76-Pad1)") (class "Default")
      (node (ref "SV76") (pin "1") (pinfunction "1_1") (pintype "passive"))
      (node (ref "SV76") (pin "3") (pinfunction "3_3") (pintype "passive"))
      (node (ref "SV76") (pin "5") (pinfunction "5_5") (pintype "passive"))
      (node (ref "SV76") (pin "7") (pinfunction "7_7") (pintype "passive"))
      (node (ref "SV76") (pin "9") (pinfunction "9_9") (pintype "passive"))
    )
    (net (code "637") (name "Net-(SV76-Pad10)") (class "Default")
      (node (ref "SV76") (pin "10") (pinfunction "10_10") (pintype "passive"))
      (node (ref "SV76") (pin "2") (pinfunction "2_2") (pintype "passive"))
      (node (ref "SV76") (pin "4") (pinfunction "4_4") (pintype "passive"))
      (node (ref "SV76") (pin "6") (pinfunction "6_6") (pintype "passive"))
      (node (ref "SV76") (pin "8") (pinfunction "8_8") (pintype "passive"))
    )
    (net (code "638") (name "Net-(SV77-Pad1)") (class "Default")
      (node (ref "SV77") (pin "1") (pinfunction "1_1") (pintype "passive"))
      (node (ref "SV77") (pin "3") (pinfunction "3_3") (pintype "passive"))
      (node (ref "SV77") (pin "5") (pinfunction "5_5") (pintype "passive"))
      (node (ref "SV77") (pin "7") (pinfunction "7_7") (pintype "passive"))
      (node (ref "SV77") (pin "9") (pinfunction "9_9") (pintype "passive"))
    )
    (net (code "639") (name "Net-(SV77-Pad10)") (class "Default")
      (node (ref "SV77") (pin "10") (pinfunction "10_10") (pintype "passive"))
      (node (ref "SV77") (pin "2") (pinfunction "2_2") (pintype "passive"))
      (node (ref "SV77") (pin "4") (pinfunction "4_4") (pintype "passive"))
      (node (ref "SV77") (pin "6") (pinfunction "6_6") (pintype "passive"))
      (node (ref "SV77") (pin "8") (pinfunction "8_8") (pintype "passive"))
    )
    (net (code "640") (name "Net-(SV78-Pad1)") (class "Default")
      (node (ref "SV78") (pin "1") (pinfunction "1_1") (pintype "passive"))
      (node (ref "SV78") (pin "3") (pinfunction "3_3") (pintype "passive"))
      (node (ref "SV78") (pin "5") (pinfunction "5_5") (pintype "passive"))
      (node (ref "SV78") (pin "7") (pinfunction "7_7") (pintype "passive"))
      (node (ref "SV78") (pin "9") (pinfunction "9_9") (pintype "passive"))
    )
    (net (code "641") (name "Net-(SV78-Pad10)") (class "Default")
      (node (ref "SV78") (pin "10") (pinfunction "10_10") (pintype "passive"))
      (node (ref "SV78") (pin "2") (pinfunction "2_2") (pintype "passive"))
      (node (ref "SV78") (pin "4") (pinfunction "4_4") (pintype "passive"))
      (node (ref "SV78") (pin "6") (pinfunction "6_6") (pintype "passive"))
      (node (ref "SV78") (pin "8") (pinfunction "8_8") (pintype "passive"))
    )
    (net (code "642") (name "Net-(SV79-Pad1)") (class "Default")
      (node (ref "SV79") (pin "1") (pinfunction "1_1") (pintype "passive"))
      (node (ref "SV79") (pin "3") (pinfunction "3_3") (pintype "passive"))
      (node (ref "SV79") (pin "5") (pinfunction "5_5") (pintype "passive"))
      (node (ref "SV79") (pin "7") (pinfunction "7_7") (pintype "passive"))
      (node (ref "SV79") (pin "9") (pinfunction "9_9") (pintype "passive"))
    )
    (net (code "643") (name "Net-(SV79-Pad10)") (class "Default")
      (node (ref "SV79") (pin "10") (pinfunction "10_10") (pintype "passive"))
      (node (ref "SV79") (pin "2") (pinfunction "2_2") (pintype "passive"))
      (node (ref "SV79") (pin "4") (pinfunction "4_4") (pintype "passive"))
      (node (ref "SV79") (pin "6") (pinfunction "6_6") (pintype "passive"))
      (node (ref "SV79") (pin "8") (pinfunction "8_8") (pintype "passive"))
    )
    (net (code "644") (name "Net-(SV80-Pad1)") (class "Default")
      (node (ref "SV80") (pin "1") (pinfunction "1_1") (pintype "passive"))
      (node (ref "SV80") (pin "3") (pinfunction "3_3") (pintype "passive"))
      (node (ref "SV80") (pin "5") (pinfunction "5_5") (pintype "passive"))
      (node (ref "SV80") (pin "7") (pinfunction "7_7") (pintype "passive"))
      (node (ref "SV80") (pin "9") (pinfunction "9_9") (pintype "passive"))
    )
    (net (code "645") (name "Net-(SV80-Pad10)") (class "Default")
      (node (ref "SV80") (pin "10") (pinfunction "10_10") (pintype "passive"))
      (node (ref "SV80") (pin "2") (pinfunction "2_2") (pintype "passive"))
      (node (ref "SV80") (pin "4") (pinfunction "4_4") (pintype "passive"))
      (node (ref "SV80") (pin "6") (pinfunction "6_6") (pintype "passive"))
      (node (ref "SV80") (pin "8") (pinfunction "8_8") (pintype "passive"))
    )
    (net (code "646") (name "Net-(SV81-Pad1)") (class "Default")
      (node (ref "SV81") (pin "1") (pinfunction "1_1") (pintype "passive"))
      (node (ref "SV81") (pin "3") (pinfunction "3_3") (pintype "passive"))
      (node (ref "SV81") (pin "5") (pinfunction "5_5") (pintype "passive"))
      (node (ref "SV81") (pin "7") (pinfunction "7_7") (pintype "passive"))
      (node (ref "SV81") (pin "9") (pinfunction "9_9") (pintype "passive"))
    )
    (net (code "647") (name "Net-(SV81-Pad10)") (class "Default")
      (node (ref "SV81") (pin "10") (pinfunction "10_10") (pintype "passive"))
      (node (ref "SV81") (pin "2") (pinfunction "2_2") (pintype "passive"))
      (node (ref "SV81") (pin "4") (pinfunction "4_4") (pintype "passive"))
      (node (ref "SV81") (pin "6") (pinfunction "6_6") (pintype "passive"))
      (node (ref "SV81") (pin "8") (pinfunction "8_8") (pintype "passive"))
    )
    (net (code "648") (name "Net-(SV82-Pad1)") (class "Default")
      (node (ref "SV82") (pin "1") (pinfunction "1_1") (pintype "passive"))
      (node (ref "SV82") (pin "3") (pinfunction "3_3") (pintype "passive"))
      (node (ref "SV82") (pin "5") (pinfunction "5_5") (pintype "passive"))
      (node (ref "SV82") (pin "7") (pinfunction "7_7") (pintype "passive"))
      (node (ref "SV82") (pin "9") (pinfunction "9_9") (pintype "passive"))
    )
    (net (code "649") (name "Net-(SV82-Pad10)") (class "Default")
      (node (ref "SV82") (pin "10") (pinfunction "10_10") (pintype "passive"))
      (node (ref "SV82") (pin "2") (pinfunction "2_2") (pintype "passive"))
      (node (ref "SV82") (pin "4") (pinfunction "4_4") (pintype "passive"))
      (node (ref "SV82") (pin "6") (pinfunction "6_6") (pintype "passive"))
      (node (ref "SV82") (pin "8") (pinfunction "8_8") (pintype "passive"))
    )
    (net (code "650") (name "Net-(SV83-Pad1)") (class "Default")
      (node (ref "SV83") (pin "1") (pinfunction "1_1") (pintype "passive"))
      (node (ref "SV83") (pin "3") (pinfunction "3_3") (pintype "passive"))
      (node (ref "SV83") (pin "5") (pinfunction "5_5") (pintype "passive"))
      (node (ref "SV83") (pin "7") (pinfunction "7_7") (pintype "passive"))
      (node (ref "SV83") (pin "9") (pinfunction "9_9") (pintype "passive"))
    )
    (net (code "651") (name "Net-(SV83-Pad10)") (class "Default")
      (node (ref "SV83") (pin "10") (pinfunction "10_10") (pintype "passive"))
      (node (ref "SV83") (pin "2") (pinfunction "2_2") (pintype "passive"))
      (node (ref "SV83") (pin "4") (pinfunction "4_4") (pintype "passive"))
      (node (ref "SV83") (pin "6") (pinfunction "6_6") (pintype "passive"))
      (node (ref "SV83") (pin "8") (pinfunction "8_8") (pintype "passive"))
    )
    (net (code "652") (name "Net-(SV84-Pad1)") (class "Default")
      (node (ref "SV84") (pin "1") (pinfunction "1_1") (pintype "passive"))
      (node (ref "SV84") (pin "3") (pinfunction "3_3") (pintype "passive"))
      (node (ref "SV84") (pin "5") (pinfunction "5_5") (pintype "passive"))
      (node (ref "SV84") (pin "7") (pinfunction "7_7") (pintype "passive"))
      (node (ref "SV84") (pin "9") (pinfunction "9_9") (pintype "passive"))
    )
    (net (code "653") (name "Net-(SV84-Pad10)") (class "Default")
      (node (ref "SV84") (pin "10") (pinfunction "10_10") (pintype "passive"))
      (node (ref "SV84") (pin "2") (pinfunction "2_2") (pintype "passive"))
      (node (ref "SV84") (pin "4") (pinfunction "4_4") (pintype "passive"))
      (node (ref "SV84") (pin "6") (pinfunction "6_6") (pintype "passive"))
      (node (ref "SV84") (pin "8") (pinfunction "8_8") (pintype "passive"))
    )
    (net (code "654") (name "Net-(SV85-Pad1)") (class "Default")
      (node (ref "SV85") (pin "1") (pinfunction "1_1") (pintype "passive"))
      (node (ref "SV85") (pin "3") (pinfunction "3_3") (pintype "passive"))
      (node (ref "SV85") (pin "5") (pinfunction "5_5") (pintype "passive"))
      (node (ref "SV85") (pin "7") (pinfunction "7_7") (pintype "passive"))
      (node (ref "SV85") (pin "9") (pinfunction "9_9") (pintype "passive"))
    )
    (net (code "655") (name "Net-(SV85-Pad10)") (class "Default")
      (node (ref "SV85") (pin "10") (pinfunction "10_10") (pintype "passive"))
      (node (ref "SV85") (pin "2") (pinfunction "2_2") (pintype "passive"))
      (node (ref "SV85") (pin "4") (pinfunction "4_4") (pintype "passive"))
      (node (ref "SV85") (pin "6") (pinfunction "6_6") (pintype "passive"))
      (node (ref "SV85") (pin "8") (pinfunction "8_8") (pintype "passive"))
    )
    (net (code "656") (name "Net-(SV86-Pad1)") (class "Default")
      (node (ref "SV86") (pin "1") (pinfunction "1_1") (pintype "passive"))
      (node (ref "SV86") (pin "3") (pinfunction "3_3") (pintype "passive"))
      (node (ref "SV86") (pin "5") (pinfunction "5_5") (pintype "passive"))
      (node (ref "SV86") (pin "7") (pinfunction "7_7") (pintype "passive"))
      (node (ref "SV86") (pin "9") (pinfunction "9_9") (pintype "passive"))
    )
    (net (code "657") (name "Net-(SV86-Pad10)") (class "Default")
      (node (ref "SV86") (pin "10") (pinfunction "10_10") (pintype "passive"))
      (node (ref "SV86") (pin "2") (pinfunction "2_2") (pintype "passive"))
      (node (ref "SV86") (pin "4") (pinfunction "4_4") (pintype "passive"))
      (node (ref "SV86") (pin "6") (pinfunction "6_6") (pintype "passive"))
      (node (ref "SV86") (pin "8") (pinfunction "8_8") (pintype "passive"))
    )
    (net (code "658") (name "Net-(SV87-Pad1)") (class "Default")
      (node (ref "SV87") (pin "1") (pinfunction "1_1") (pintype "passive"))
      (node (ref "SV87") (pin "3") (pinfunction "3_3") (pintype "passive"))
      (node (ref "SV87") (pin "5") (pinfunction "5_5") (pintype "passive"))
      (node (ref "SV87") (pin "7") (pinfunction "7_7") (pintype "passive"))
      (node (ref "SV87") (pin "9") (pinfunction "9_9") (pintype "passive"))
    )
    (net (code "659") (name "Net-(SV87-Pad10)") (class "Default")
      (node (ref "SV87") (pin "10") (pinfunction "10_10") (pintype "passive"))
      (node (ref "SV87") (pin "2") (pinfunction "2_2") (pintype "passive"))
      (node (ref "SV87") (pin "4") (pinfunction "4_4") (pintype "passive"))
      (node (ref "SV87") (pin "6") (pinfunction "6_6") (pintype "passive"))
      (node (ref "SV87") (pin "8") (pinfunction "8_8") (pintype "passive"))
    )
    (net (code "660") (name "Net-(SV88-Pad1)") (class "Default")
      (node (ref "SV88") (pin "1") (pinfunction "1_1") (pintype "passive"))
      (node (ref "SV88") (pin "3") (pinfunction "3_3") (pintype "passive"))
      (node (ref "SV88") (pin "5") (pinfunction "5_5") (pintype "passive"))
      (node (ref "SV88") (pin "7") (pinfunction "7_7") (pintype "passive"))
      (node (ref "SV88") (pin "9") (pinfunction "9_9") (pintype "passive"))
    )
    (net (code "661") (name "Net-(SV88-Pad10)") (class "Default")
      (node (ref "SV88") (pin "10") (pinfunction "10_10") (pintype "passive"))
      (node (ref "SV88") (pin "2") (pinfunction "2_2") (pintype "passive"))
      (node (ref "SV88") (pin "4") (pinfunction "4_4") (pintype "passive"))
      (node (ref "SV88") (pin "6") (pinfunction "6_6") (pintype "passive"))
      (node (ref "SV88") (pin "8") (pinfunction "8_8") (pintype "passive"))
    )
    (net (code "662") (name "Net-(SV89-Pad1)") (class "Default")
      (node (ref "SV89") (pin "1") (pinfunction "1_1") (pintype "passive"))
      (node (ref "SV89") (pin "3") (pinfunction "3_3") (pintype "passive"))
      (node (ref "SV89") (pin "5") (pinfunction "5_5") (pintype "passive"))
      (node (ref "SV89") (pin "7") (pinfunction "7_7") (pintype "passive"))
      (node (ref "SV89") (pin "9") (pinfunction "9_9") (pintype "passive"))
    )
    (net (code "663") (name "Net-(SV89-Pad10)") (class "Default")
      (node (ref "SV89") (pin "10") (pinfunction "10_10") (pintype "passive"))
      (node (ref "SV89") (pin "2") (pinfunction "2_2") (pintype "passive"))
      (node (ref "SV89") (pin "4") (pinfunction "4_4") (pintype "passive"))
      (node (ref "SV89") (pin "6") (pinfunction "6_6") (pintype "passive"))
      (node (ref "SV89") (pin "8") (pinfunction "8_8") (pintype "passive"))
    )
    (net (code "664") (name "Net-(SV90-Pad1)") (class "Default")
      (node (ref "SV90") (pin "1") (pinfunction "1_1") (pintype "passive"))
      (node (ref "SV90") (pin "3") (pinfunction "3_3") (pintype "passive"))
      (node (ref "SV90") (pin "5") (pinfunction "5_5") (pintype "passive"))
      (node (ref "SV90") (pin "7") (pinfunction "7_7") (pintype "passive"))
      (node (ref "SV90") (pin "9") (pinfunction "9_9") (pintype "passive"))
    )
    (net (code "665") (name "Net-(SV90-Pad10)") (class "Default")
      (node (ref "SV90") (pin "10") (pinfunction "10_10") (pintype "passive"))
      (node (ref "SV90") (pin "2") (pinfunction "2_2") (pintype "passive"))
      (node (ref "SV90") (pin "4") (pinfunction "4_4") (pintype "passive"))
      (node (ref "SV90") (pin "6") (pinfunction "6_6") (pintype "passive"))
      (node (ref "SV90") (pin "8") (pinfunction "8_8") (pintype "passive"))
    )
    (net (code "666") (name "Net-(SV91-Pad1)") (class "Default")
      (node (ref "SV91") (pin "1") (pinfunction "1_1") (pintype "passive"))
      (node (ref "SV91") (pin "3") (pinfunction "3_3") (pintype "passive"))
      (node (ref "SV91") (pin "5") (pinfunction "5_5") (pintype "passive"))
      (node (ref "SV91") (pin "7") (pinfunction "7_7") (pintype "passive"))
      (node (ref "SV91") (pin "9") (pinfunction "9_9") (pintype "passive"))
    )
    (net (code "667") (name "Net-(SV91-Pad10)") (class "Default")
      (node (ref "SV91") (pin "10") (pinfunction "10_10") (pintype "passive"))
      (node (ref "SV91") (pin "2") (pinfunction "2_2") (pintype "passive"))
      (node (ref "SV91") (pin "4") (pinfunction "4_4") (pintype "passive"))
      (node (ref "SV91") (pin "6") (pinfunction "6_6") (pintype "passive"))
      (node (ref "SV91") (pin "8") (pinfunction "8_8") (pintype "passive"))
    )
    (net (code "668") (name "Net-(SV92-Pad1)") (class "Default")
      (node (ref "SV92") (pin "1") (pinfunction "1_1") (pintype "passive"))
      (node (ref "SV92") (pin "3") (pinfunction "3_3") (pintype "passive"))
      (node (ref "SV92") (pin "5") (pinfunction "5_5") (pintype "passive"))
      (node (ref "SV92") (pin "7") (pinfunction "7_7") (pintype "passive"))
      (node (ref "SV92") (pin "9") (pinfunction "9_9") (pintype "passive"))
    )
    (net (code "669") (name "Net-(SV92-Pad10)") (class "Default")
      (node (ref "SV92") (pin "10") (pinfunction "10_10") (pintype "passive"))
      (node (ref "SV92") (pin "2") (pinfunction "2_2") (pintype "passive"))
      (node (ref "SV92") (pin "4") (pinfunction "4_4") (pintype "passive"))
      (node (ref "SV92") (pin "6") (pinfunction "6_6") (pintype "passive"))
      (node (ref "SV92") (pin "8") (pinfunction "8_8") (pintype "passive"))
    )
    (net (code "670") (name "Net-(SV93-Pad1)") (class "Default")
      (node (ref "SV93") (pin "1") (pinfunction "1_1") (pintype "passive"))
      (node (ref "SV93") (pin "3") (pinfunction "3_3") (pintype "passive"))
      (node (ref "SV93") (pin "5") (pinfunction "5_5") (pintype "passive"))
      (node (ref "SV93") (pin "7") (pinfunction "7_7") (pintype "passive"))
      (node (ref "SV93") (pin "9") (pinfunction "9_9") (pintype "passive"))
    )
    (net (code "671") (name "Net-(SV93-Pad10)") (class "Default")
      (node (ref "SV93") (pin "10") (pinfunction "10_10") (pintype "passive"))
      (node (ref "SV93") (pin "2") (pinfunction "2_2") (pintype "passive"))
      (node (ref "SV93") (pin "4") (pinfunction "4_4") (pintype "passive"))
      (node (ref "SV93") (pin "6") (pinfunction "6_6") (pintype "passive"))
      (node (ref "SV93") (pin "8") (pinfunction "8_8") (pintype "passive"))
    )
    (net (code "672") (name "Net-(SV94-Pad1)") (class "Default")
      (node (ref "SV94") (pin "1") (pinfunction "1_1") (pintype "passive"))
      (node (ref "SV94") (pin "3") (pinfunction "3_3") (pintype "passive"))
      (node (ref "SV94") (pin "5") (pinfunction "5_5") (pintype "passive"))
      (node (ref "SV94") (pin "7") (pinfunction "7_7") (pintype "passive"))
      (node (ref "SV94") (pin "9") (pinfunction "9_9") (pintype "passive"))
    )
    (net (code "673") (name "Net-(SV94-Pad10)") (class "Default")
      (node (ref "SV94") (pin "10") (pinfunction "10_10") (pintype "passive"))
      (node (ref "SV94") (pin "2") (pinfunction "2_2") (pintype "passive"))
      (node (ref "SV94") (pin "4") (pinfunction "4_4") (pintype "passive"))
      (node (ref "SV94") (pin "6") (pinfunction "6_6") (pintype "passive"))
      (node (ref "SV94") (pin "8") (pinfunction "8_8") (pintype "passive"))
    )
    (net (code "674") (name "Net-(SV95-Pad1)") (class "Default")
      (node (ref "SV95") (pin "1") (pinfunction "1_1") (pintype "passive"))
      (node (ref "SV95") (pin "3") (pinfunction "3_3") (pintype "passive"))
      (node (ref "SV95") (pin "5") (pinfunction "5_5") (pintype "passive"))
      (node (ref "SV95") (pin "7") (pinfunction "7_7") (pintype "passive"))
      (node (ref "SV95") (pin "9") (pinfunction "9_9") (pintype "passive"))
    )
    (net (code "675") (name "Net-(SV95-Pad10)") (class "Default")
      (node (ref "SV95") (pin "10") (pinfunction "10_10") (pintype "passive"))
      (node (ref "SV95") (pin "2") (pinfunction "2_2") (pintype "passive"))
      (node (ref "SV95") (pin "4") (pinfunction "4_4") (pintype "passive"))
      (node (ref "SV95") (pin "6") (pinfunction "6_6") (pintype "passive"))
      (node (ref "SV95") (pin "8") (pinfunction "8_8") (pintype "passive"))
    )
    (net (code "676") (name "Net-(SV96-Pad1)") (class "Default")
      (node (ref "SV96") (pin "1") (pinfunction "1_1") (pintype "passive"))
      (node (ref "SV96") (pin "3") (pinfunction "3_3") (pintype "passive"))
      (node (ref "SV96") (pin "5") (pinfunction "5_5") (pintype "passive"))
      (node (ref "SV96") (pin "7") (pinfunction "7_7") (pintype "passive"))
      (node (ref "SV96") (pin "9") (pinfunction "9_9") (pintype "passive"))
    )
    (net (code "677") (name "Net-(SV96-Pad10)") (class "Default")
      (node (ref "SV96") (pin "10") (pinfunction "10_10") (pintype "passive"))
      (node (ref "SV96") (pin "2") (pinfunction "2_2") (pintype "passive"))
      (node (ref "SV96") (pin "4") (pinfunction "4_4") (pintype "passive"))
      (node (ref "SV96") (pin "6") (pinfunction "6_6") (pintype "passive"))
      (node (ref "SV96") (pin "8") (pinfunction "8_8") (pintype "passive"))
    )
    (net (code "678") (name "Net-(SV97-Pad1)") (class "Default")
      (node (ref "SV97") (pin "1") (pinfunction "1_1") (pintype "passive"))
      (node (ref "SV97") (pin "3") (pinfunction "3_3") (pintype "passive"))
      (node (ref "SV97") (pin "5") (pinfunction "5_5") (pintype "passive"))
      (node (ref "SV97") (pin "7") (pinfunction "7_7") (pintype "passive"))
      (node (ref "SV97") (pin "9") (pinfunction "9_9") (pintype "passive"))
    )
    (net (code "679") (name "Net-(SV97-Pad10)") (class "Default")
      (node (ref "SV97") (pin "10") (pinfunction "10_10") (pintype "passive"))
      (node (ref "SV97") (pin "2") (pinfunction "2_2") (pintype "passive"))
      (node (ref "SV97") (pin "4") (pinfunction "4_4") (pintype "passive"))
      (node (ref "SV97") (pin "6") (pinfunction "6_6") (pintype "passive"))
      (node (ref "SV97") (pin "8") (pinfunction "8_8") (pintype "passive"))
    )
    (net (code "680") (name "Net-(SV98-Pad1)") (class "Default")
      (node (ref "SV98") (pin "1") (pinfunction "1_1") (pintype "passive"))
      (node (ref "SV98") (pin "3") (pinfunction "3_3") (pintype "passive"))
      (node (ref "SV98") (pin "5") (pinfunction "5_5") (pintype "passive"))
      (node (ref "SV98") (pin "7") (pinfunction "7_7") (pintype "passive"))
      (node (ref "SV98") (pin "9") (pinfunction "9_9") (pintype "passive"))
    )
    (net (code "681") (name "Net-(SV98-Pad10)") (class "Default")
      (node (ref "SV98") (pin "10") (pinfunction "10_10") (pintype "passive"))
      (node (ref "SV98") (pin "2") (pinfunction "2_2") (pintype "passive"))
      (node (ref "SV98") (pin "4") (pinfunction "4_4") (pintype "passive"))
      (node (ref "SV98") (pin "6") (pinfunction "6_6") (pintype "passive"))
      (node (ref "SV98") (pin "8") (pinfunction "8_8") (pintype "passive"))
    )
    (net (code "682") (name "Net-(SV99-Pad1)") (class "Default")
      (node (ref "SV99") (pin "1") (pinfunction "1_1") (pintype "passive"))
      (node (ref "SV99") (pin "3") (pinfunction "3_3") (pintype "passive"))
      (node (ref "SV99") (pin "5") (pinfunction "5_5") (pintype "passive"))
      (node (ref "SV99") (pin "7") (pinfunction "7_7") (pintype "passive"))
      (node (ref "SV99") (pin "9") (pinfunction "9_9") (pintype "passive"))
    )
    (net (code "683") (name "Net-(SV99-Pad10)") (class "Default")
      (node (ref "SV99") (pin "10") (pinfunction "10_10") (pintype "passive"))
      (node (ref "SV99") (pin "2") (pinfunction "2_2") (pintype "passive"))
      (node (ref "SV99") (pin "4") (pinfunction "4_4") (pintype "passive"))
      (node (ref "SV99") (pin "6") (pinfunction "6_6") (pintype "passive"))
      (node (ref "SV99") (pin "8") (pinfunction "8_8") (pintype "passive"))
    )
    (net (code "684") (name "Net-(SV100-Pad1)") (class "Default")
      (node (ref "SV100") (pin "1") (pinfunction "1_1") (pintype "passive"))
      (node (ref "SV100") (pin "3") (pinfunction "3_3") (pintype "passive"))
      (node (ref "SV100") (pin "5") (pinfunction "5_5") (pintype "passive"))
      (node (ref "SV100") (pin "7") (pinfunction "7_7") (pintype "passive"))
      (node (ref "SV100") (pin "9") (pinfunction "9_9") (pintype "passive"))
    )
    (net (code "685") (name "Net-(SV100-Pad10)") (class "Default")
      (node (ref "SV100") (pin "10") (pinfunction "10_10") (pintype "passive"))
      (node (ref "SV100") (pin "2") (pinfunction "2_2") (pintype "passive"))
      (node (ref "SV100") (pin "4") (pinfunction "4_4") (pintype "passive"))
      (node (ref "SV100") (pin "6") (pinfunction "6_6") (pintype "passive"))
      (node (ref "SV100") (pin "8") (pinfunction "8_8") (pintype "passive"))
    )
    (net (code "686") (name "Net-(SV101-Pad1)") (class "Default")
      (node (ref "SV101") (pin "1") (pinfunction "1_1") (pintype "passive"))
      (node (ref "SV101") (pin "3") (pinfunction "3_3") (pintype "passive"))
      (node (ref "SV101") (pin "5") (pinfunction "5_5") (pintype "passive"))
      (node (ref "SV101") (pin "7") (pinfunction "7_7") (pintype "passive"))
      (node (ref "SV101") (pin "9") (pinfunction "9_9") (pintype "passive"))
    )
    (net (code "687") (name "Net-(SV101-Pad10)") (class "Default")
      (node (ref "SV101") (pin "10") (pinfunction "10_10") (pintype "passive"))
      (node (ref "SV101") (pin "2") (pinfunction "2_2") (pintype "passive"))
      (node (ref "SV101") (pin "4") (pinfunction "4_4") (pintype "passive"))
      (node (ref "SV101") (pin "6") (pinfunction "6_6") (pintype "passive"))
      (node (ref "SV101") (pin "8") (pinfunction "8_8") (pintype "passive"))
    )
    (net (code "688") (name "Net-(SV102-Pad1)") (class "Default")
      (node (ref "SV102") (pin "1") (pinfunction "1_1") (pintype "passive"))
      (node (ref "SV102") (pin "3") (pinfunction "3_3") (pintype "passive"))
      (node (ref "SV102") (pin "5") (pinfunction "5_5") (pintype "passive"))
      (node (ref "SV102") (pin "7") (pinfunction "7_7") (pintype "passive"))
      (node (ref "SV102") (pin "9") (pinfunction "9_9") (pintype "passive"))
    )
    (net (code "689") (name "Net-(SV102-Pad10)") (class "Default")
      (node (ref "SV102") (pin "10") (pinfunction "10_10") (pintype "passive"))
      (node (ref "SV102") (pin "2") (pinfunction "2_2") (pintype "passive"))
      (node (ref "SV102") (pin "4") (pinfunction "4_4") (pintype "passive"))
      (node (ref "SV102") (pin "6") (pinfunction "6_6") (pintype "passive"))
      (node (ref "SV102") (pin "8") (pinfunction "8_8") (pintype "passive"))
    )
    (net (code "690") (name "Net-(SV103-Pad1)") (class "Default")
      (node (ref "SV103") (pin "1") (pinfunction "1_1") (pintype "passive"))
      (node (ref "SV103") (pin "3") (pinfunction "3_3") (pintype "passive"))
      (node (ref "SV103") (pin "5") (pinfunction "5_5") (pintype "passive"))
      (node (ref "SV103") (pin "7") (pinfunction "7_7") (pintype "passive"))
      (node (ref "SV103") (pin "9") (pinfunction "9_9") (pintype "passive"))
    )
    (net (code "691") (name "Net-(SV103-Pad10)") (class "Default")
      (node (ref "SV103") (pin "10") (pinfunction "10_10") (pintype "passive"))
      (node (ref "SV103") (pin "2") (pinfunction "2_2") (pintype "passive"))
      (node (ref "SV103") (pin "4") (pinfunction "4_4") (pintype "passive"))
      (node (ref "SV103") (pin "6") (pinfunction "6_6") (pintype "passive"))
      (node (ref "SV103") (pin "8") (pinfunction "8_8") (pintype "passive"))
    )
    (net (code "692") (name "Net-(SV104-Pad1)") (class "Default")
      (node (ref "SV104") (pin "1") (pinfunction "1_1") (pintype "passive"))
      (node (ref "SV104") (pin "3") (pinfunction "3_3") (pintype "passive"))
      (node (ref "SV104") (pin "5") (pinfunction "5_5") (pintype "passive"))
      (node (ref "SV104") (pin "7") (pinfunction "7_7") (pintype "passive"))
      (node (ref "SV104") (pin "9") (pinfunction "9_9") (pintype "passive"))
    )
    (net (code "693") (name "Net-(SV104-Pad10)") (class "Default")
      (node (ref "SV104") (pin "10") (pinfunction "10_10") (pintype "passive"))
      (node (ref "SV104") (pin "2") (pinfunction "2_2") (pintype "passive"))
      (node (ref "SV104") (pin "4") (pinfunction "4_4") (pintype "passive"))
      (node (ref "SV104") (pin "6") (pinfunction "6_6") (pintype "passive"))
      (node (ref "SV104") (pin "8") (pinfunction "8_8") (pintype "passive"))
    )
    (net (code "694") (name "Net-(SV105-Pad1)") (class "Default")
      (node (ref "SV105") (pin "1") (pinfunction "1_1") (pintype "passive"))
      (node (ref "SV105") (pin "3") (pinfunction "3_3") (pintype "passive"))
      (node (ref "SV105") (pin "5") (pinfunction "5_5") (pintype "passive"))
      (node (ref "SV105") (pin "7") (pinfunction "7_7") (pintype "passive"))
      (node (ref "SV105") (pin "9") (pinfunction "9_9") (pintype "passive"))
    )
    (net (code "695") (name "Net-(SV105-Pad10)") (class "Default")
      (node (ref "SV105") (pin "10") (pinfunction "10_10") (pintype "passive"))
      (node (ref "SV105") (pin "2") (pinfunction "2_2") (pintype "passive"))
      (node (ref "SV105") (pin "4") (pinfunction "4_4") (pintype "passive"))
      (node (ref "SV105") (pin "6") (pinfunction "6_6") (pintype "passive"))
      (node (ref "SV105") (pin "8") (pinfunction "8_8") (pintype "passive"))
    )
    (net (code "696") (name "Net-(SV106-Pad1)") (class "Default")
      (node (ref "SV106") (pin "1") (pinfunction "1_1") (pintype "passive"))
      (node (ref "SV106") (pin "3") (pinfunction "3_3") (pintype "passive"))
      (node (ref "SV106") (pin "5") (pinfunction "5_5") (pintype "passive"))
      (node (ref "SV106") (pin "7") (pinfunction "7_7") (pintype "passive"))
      (node (ref "SV106") (pin "9") (pinfunction "9_9") (pintype "passive"))
    )
    (net (code "697") (name "Net-(SV106-Pad10)") (class "Default")
      (node (ref "SV106") (pin "10") (pinfunction "10_10") (pintype "passive"))
      (node (ref "SV106") (pin "2") (pinfunction "2_2") (pintype "passive"))
      (node (ref "SV106") (pin "4") (pinfunction "4_4") (pintype "passive"))
      (node (ref "SV106") (pin "6") (pinfunction "6_6") (pintype "passive"))
      (node (ref "SV106") (pin "8") (pinfunction "8_8") (pintype "passive"))
    )
    (net (code "698") (name "Net-(SV107-Pad1)") (class "Default")
      (node (ref "SV107") (pin "1") (pinfunction "1_1") (pintype "passive"))
      (node (ref "SV107") (pin "3") (pinfunction "3_3") (pintype "passive"))
      (node (ref "SV107") (pin "5") (pinfunction "5_5") (pintype "passive"))
      (node (ref "SV107") (pin "7") (pinfunction "7_7") (pintype "passive"))
      (node (ref "SV107") (pin "9") (pinfunction "9_9") (pintype "passive"))
    )
    (net (code "699") (name "Net-(SV107-Pad10)") (class "Default")
      (node (ref "SV107") (pin "10") (pinfunction "10_10") (pintype "passive"))
      (node (ref "SV107") (pin "2") (pinfunction "2_2") (pintype "passive"))
      (node (ref "SV107") (pin "4") (pinfunction "4_4") (pintype "passive"))
      (node (ref "SV107") (pin "6") (pinfunction "6_6") (pintype "passive"))
      (node (ref "SV107") (pin "8") (pinfunction "8_8") (pintype "passive"))
    )
    (net (code "700") (name "Net-(SV108-Pad1)") (class "Default")
      (node (ref "SV108") (pin "1") (pinfunction "1_1") (pintype "passive"))
      (node (ref "SV108") (pin "3") (pinfunction "3_3") (pintype "passive"))
      (node (ref "SV108") (pin "5") (pinfunction "5_5") (pintype "passive"))
      (node (ref "SV108") (pin "7") (pinfunction "7_7") (pintype "passive"))
      (node (ref "SV108") (pin "9") (pinfunction "9_9") (pintype "passive"))
    )
    (net (code "701") (name "Net-(SV108-Pad10)") (class "Default")
      (node (ref "SV108") (pin "10") (pinfunction "10_10") (pintype "passive"))
      (node (ref "SV108") (pin "2") (pinfunction "2_2") (pintype "passive"))
      (node (ref "SV108") (pin "4") (pinfunction "4_4") (pintype "passive"))
      (node (ref "SV108") (pin "6") (pinfunction "6_6") (pintype "passive"))
      (node (ref "SV108") (pin "8") (pinfunction "8_8") (pintype "passive"))
    )
    (net (code "702") (name "Net-(SV109-Pad1)") (class "Default")
      (node (ref "SV109") (pin "1") (pinfunction "1_1") (pintype "passive"))
      (node (ref "SV109") (pin "3") (pinfunction "3_3") (pintype "passive"))
      (node (ref "SV109") (pin "5") (pinfunction "5_5") (pintype "passive"))
      (node (ref "SV109") (pin "7") (pinfunction "7_7") (pintype "passive"))
      (node (ref "SV109") (pin "9") (pinfunction "9_9") (pintype "passive"))
    )
    (net (code "703") (name "Net-(SV109-Pad10)") (class "Default")
      (node (ref "SV109") (pin "10") (pinfunction "10_10") (pintype "passive"))
      (node (ref "SV109") (pin "2") (pinfunction "2_2") (pintype "passive"))
      (node (ref "SV109") (pin "4") (pinfunction "4_4") (pintype "passive"))
      (node (ref "SV109") (pin "6") (pinfunction "6_6") (pintype "passive"))
      (node (ref "SV109") (pin "8") (pinfunction "8_8") (pintype "passive"))
    )
    (net (code "704") (name "Net-(SV110-Pad1)") (class "Default")
      (node (ref "SV110") (pin "1") (pinfunction "1_1") (pintype "passive"))
      (node (ref "SV110") (pin "3") (pinfunction "3_3") (pintype "passive"))
      (node (ref "SV110") (pin "5") (pinfunction "5_5") (pintype "passive"))
      (node (ref "SV110") (pin "7") (pinfunction "7_7") (pintype "passive"))
      (node (ref "SV110") (pin "9") (pinfunction "9_9") (pintype "passive"))
    )
    (net (code "705") (name "Net-(SV110-Pad10)") (class "Default")
      (node (ref "SV110") (pin "10") (pinfunction "10_10") (pintype "passive"))
      (node (ref "SV110") (pin "2") (pinfunction "2_2") (pintype "passive"))
      (node (ref "SV110") (pin "4") (pinfunction "4_4") (pintype "passive"))
      (node (ref "SV110") (pin "6") (pinfunction "6_6") (pintype "passive"))
      (node (ref "SV110") (pin "8") (pinfunction "8_8") (pintype "passive"))
    )
    (net (code "706") (name "Net-(SV111-Pad1)") (class "Default")
      (node (ref "SV111") (pin "1") (pinfunction "1_1") (pintype "passive"))
      (node (ref "SV111") (pin "3") (pinfunction "3_3") (pintype "passive"))
      (node (ref "SV111") (pin "5") (pinfunction "5_5") (pintype "passive"))
      (node (ref "SV111") (pin "7") (pinfunction "7_7") (pintype "passive"))
      (node (ref "SV111") (pin "9") (pinfunction "9_9") (pintype "passive"))
    )
    (net (code "707") (name "Net-(SV111-Pad10)") (class "Default")
      (node (ref "SV111") (pin "10") (pinfunction "10_10") (pintype "passive"))
      (node (ref "SV111") (pin "2") (pinfunction "2_2") (pintype "passive"))
      (node (ref "SV111") (pin "4") (pinfunction "4_4") (pintype "passive"))
      (node (ref "SV111") (pin "6") (pinfunction "6_6") (pintype "passive"))
      (node (ref "SV111") (pin "8") (pinfunction "8_8") (pintype "passive"))
    )
    (net (code "708") (name "Net-(SV112-Pad1)") (class "Default")
      (node (ref "SV112") (pin "1") (pinfunction "1_1") (pintype "passive"))
      (node (ref "SV112") (pin "3") (pinfunction "3_3") (pintype "passive"))
      (node (ref "SV112") (pin "5") (pinfunction "5_5") (pintype "passive"))
      (node (ref "SV112") (pin "7") (pinfunction "7_7") (pintype "passive"))
      (node (ref "SV112") (pin "9") (pinfunction "9_9") (pintype "passive"))
    )
    (net (code "709") (name "Net-(SV112-Pad10)") (class "Default")
      (node (ref "SV112") (pin "10") (pinfunction "10_10") (pintype "passive"))
      (node (ref "SV112") (pin "2") (pinfunction "2_2") (pintype "passive"))
      (node (ref "SV112") (pin "4") (pinfunction "4_4") (pintype "passive"))
      (node (ref "SV112") (pin "6") (pinfunction "6_6") (pintype "passive"))
      (node (ref "SV112") (pin "8") (pinfunction "8_8") (pintype "passive"))
    )
    (net (code "710") (name "Net-(SV113-Pad1)") (class "Default")
      (node (ref "SV113") (pin "1") (pinfunction "1_1") (pintype "passive"))
      (node (ref "SV113") (pin "3") (pinfunction "3_3") (pintype "passive"))
      (node (ref "SV113") (pin "5") (pinfunction "5_5") (pintype "passive"))
      (node (ref "SV113") (pin "7") (pinfunction "7_7") (pintype "passive"))
      (node (ref "SV113") (pin "9") (pinfunction "9_9") (pintype "passive"))
    )
    (net (code "711") (name "Net-(SV113-Pad10)") (class "Default")
      (node (ref "SV113") (pin "10") (pinfunction "10_10") (pintype "passive"))
      (node (ref "SV113") (pin "2") (pinfunction "2_2") (pintype "passive"))
      (node (ref "SV113") (pin "4") (pinfunction "4_4") (pintype "passive"))
      (node (ref "SV113") (pin "6") (pinfunction "6_6") (pintype "passive"))
      (node (ref "SV113") (pin "8") (pinfunction "8_8") (pintype "passive"))
    )
    (net (code "712") (name "Net-(SV114-Pad1)") (class "Default")
      (node (ref "SV114") (pin "1") (pinfunction "1_1") (pintype "passive"))
      (node (ref "SV114") (pin "3") (pinfunction "3_3") (pintype "passive"))
      (node (ref "SV114") (pin "5") (pinfunction "5_5") (pintype "passive"))
      (node (ref "SV114") (pin "7") (pinfunction "7_7") (pintype "passive"))
      (node (ref "SV114") (pin "9") (pinfunction "9_9") (pintype "passive"))
    )
    (net (code "713") (name "Net-(SV114-Pad10)") (class "Default")
      (node (ref "SV114") (pin "10") (pinfunction "10_10") (pintype "passive"))
      (node (ref "SV114") (pin "2") (pinfunction "2_2") (pintype "passive"))
      (node (ref "SV114") (pin "4") (pinfunction "4_4") (pintype "passive"))
      (node (ref "SV114") (pin "6") (pinfunction "6_6") (pintype "passive"))
      (node (ref "SV114") (pin "8") (pinfunction "8_8") (pintype "passive"))
    )
    (net (code "714") (name "Net-(SV115-Pad1)") (class "Default")
      (node (ref "SV115") (pin "1") (pinfunction "1_1") (pintype "passive"))
      (node (ref "SV115") (pin "3") (pinfunction "3_3") (pintype "passive"))
      (node (ref "SV115") (pin "5") (pinfunction "5_5") (pintype "passive"))
      (node (ref "SV115") (pin "7") (pinfunction "7_7") (pintype "passive"))
      (node (ref "SV115") (pin "9") (pinfunction "9_9") (pintype "passive"))
    )
    (net (code "715") (name "Net-(SV115-Pad10)") (class "Default")
      (node (ref "SV115") (pin "10") (pinfunction "10_10") (pintype "passive"))
      (node (ref "SV115") (pin "2") (pinfunction "2_2") (pintype "passive"))
      (node (ref "SV115") (pin "4") (pinfunction "4_4") (pintype "passive"))
      (node (ref "SV115") (pin "6") (pinfunction "6_6") (pintype "passive"))
      (node (ref "SV115") (pin "8") (pinfunction "8_8") (pintype "passive"))
    )
    (net (code "716") (name "Net-(SV116-Pad1)") (class "Default")
      (node (ref "SV116") (pin "1") (pinfunction "1_1") (pintype "passive"))
      (node (ref "SV116") (pin "3") (pinfunction "3_3") (pintype "passive"))
      (node (ref "SV116") (pin "5") (pinfunction "5_5") (pintype "passive"))
      (node (ref "SV116") (pin "7") (pinfunction "7_7") (pintype "passive"))
      (node (ref "SV116") (pin "9") (pinfunction "9_9") (pintype "passive"))
    )
    (net (code "717") (name "Net-(SV116-Pad10)") (class "Default")
      (node (ref "SV116") (pin "10") (pinfunction "10_10") (pintype "passive"))
      (node (ref "SV116") (pin "2") (pinfunction "2_2") (pintype "passive"))
      (node (ref "SV116") (pin "4") (pinfunction "4_4") (pintype "passive"))
      (node (ref "SV116") (pin "6") (pinfunction "6_6") (pintype "passive"))
      (node (ref "SV116") (pin "8") (pinfunction "8_8") (pintype "passive"))
    )
    (net (code "718") (name "Net-(SV117-Pad1)") (class "Default")
      (node (ref "SV117") (pin "1") (pinfunction "1_1") (pintype "passive"))
      (node (ref "SV117") (pin "3") (pinfunction "3_3") (pintype "passive"))
      (node (ref "SV117") (pin "5") (pinfunction "5_5") (pintype "passive"))
      (node (ref "SV117") (pin "7") (pinfunction "7_7") (pintype "passive"))
      (node (ref "SV117") (pin "9") (pinfunction "9_9") (pintype "passive"))
    )
    (net (code "719") (name "Net-(SV117-Pad10)") (class "Default")
      (node (ref "SV117") (pin "10") (pinfunction "10_10") (pintype "passive"))
      (node (ref "SV117") (pin "2") (pinfunction "2_2") (pintype "passive"))
      (node (ref "SV117") (pin "4") (pinfunction "4_4") (pintype "passive"))
      (node (ref "SV117") (pin "6") (pinfunction "6_6") (pintype "passive"))
      (node (ref "SV117") (pin "8") (pinfunction "8_8") (pintype "passive"))
    )
    (net (code "720") (name "Net-(SV118-Pad1)") (class "Default")
      (node (ref "SV118") (pin "1") (pinfunction "1_1") (pintype "passive"))
      (node (ref "SV118") (pin "3") (pinfunction "3_3") (pintype "passive"))
      (node (ref "SV118") (pin "5") (pinfunction "5_5") (pintype "passive"))
      (node (ref "SV118") (pin "7") (pinfunction "7_7") (pintype "passive"))
      (node (ref "SV118") (pin "9") (pinfunction "9_9") (pintype "passive"))
    )
    (net (code "721") (name "Net-(SV118-Pad10)") (class "Default")
      (node (ref "SV118") (pin "10") (pinfunction "10_10") (pintype "passive"))
      (node (ref "SV118") (pin "2") (pinfunction "2_2") (pintype "passive"))
      (node (ref "SV118") (pin "4") (pinfunction "4_4") (pintype "passive"))
      (node (ref "SV118") (pin "6") (pinfunction "6_6") (pintype "passive"))
      (node (ref "SV118") (pin "8") (pinfunction "8_8") (pintype "passive"))
    )
    (net (code "722") (name "Net-(SV119-Pad1)") (class "Default")
      (node (ref "SV119") (pin "1") (pinfunction "1_1") (pintype "passive"))
      (node (ref "SV119") (pin "3") (pinfunction "3_3") (pintype "passive"))
      (node (ref "SV119") (pin "5") (pinfunction "5_5") (pintype "passive"))
      (node (ref "SV119") (pin "7") (pinfunction "7_7") (pintype "passive"))
      (node (ref "SV119") (pin "9") (pinfunction "9_9") (pintype "passive"))
    )
    (net (code "723") (name "Net-(SV119-Pad10)") (class "Default")
      (node (ref "SV119") (pin "10") (pinfunction "10_10") (pintype "passive"))
      (node (ref "SV119") (pin "2") (pinfunction "2_2") (pintype "passive"))
      (node (ref "SV119") (pin "4") (pinfunction "4_4") (pintype "passive"))
      (node (ref "SV119") (pin "6") (pinfunction "6_6") (pintype "passive"))
      (node (ref "SV119") (pin "8") (pinfunction "8_8") (pintype "passive"))
    )
    (net (code "724") (name "Net-(SV120-Pad1)") (class "Default")
      (node (ref "SV120") (pin "1") (pinfunction "1_1") (pintype "passive"))
      (node (ref "SV120") (pin "3") (pinfunction "3_3") (pintype "passive"))
      (node (ref "SV120") (pin "5") (pinfunction "5_5") (pintype "passive"))
      (node (ref "SV120") (pin "7") (pinfunction "7_7") (pintype "passive"))
      (node (ref "SV120") (pin "9") (pinfunction "9_9") (pintype "passive"))
    )
    (net (code "725") (name "Net-(SV120-Pad10)") (class "Default")
      (node (ref "SV120") (pin "10") (pinfunction "10_10") (pintype "passive"))
      (node (ref "SV120") (pin "2") (pinfunction "2_2") (pintype "passive"))
      (node (ref "SV120") (pin "4") (pinfunction "4_4") (pintype "passive"))
      (node (ref "SV120") (pin "6") (pinfunction "6_6") (pintype "passive"))
      (node (ref "SV120") (pin "8") (pinfunction "8_8") (pintype "passive"))
    )
    (net (code "726") (name "Net-(SV121-Pad1)") (class "Default")
      (node (ref "SV121") (pin "1") (pinfunction "1_1") (pintype "passive"))
      (node (ref "SV121") (pin "3") (pinfunction "3_3") (pintype "passive"))
      (node (ref "SV121") (pin "5") (pinfunction "5_5") (pintype "passive"))
      (node (ref "SV121") (pin "7") (pinfunction "7_7") (pintype "passive"))
      (node (ref "SV121") (pin "9") (pinfunction "9_9") (pintype "passive"))
    )
    (net (code "727") (name "Net-(SV121-Pad10)") (class "Default")
      (node (ref "SV121") (pin "10") (pinfunction "10_10") (pintype "passive"))
      (node (ref "SV121") (pin "2") (pinfunction "2_2") (pintype "passive"))
      (node (ref "SV121") (pin "4") (pinfunction "4_4") (pintype "passive"))
      (node (ref "SV121") (pin "6") (pinfunction "6_6") (pintype "passive"))
      (node (ref "SV121") (pin "8") (pinfunction "8_8") (pintype "passive"))
    )
    (net (code "728") (name "Net-(SV122-Pad1)") (class "Default")
      (node (ref "SV122") (pin "1") (pinfunction "1_1") (pintype "passive"))
      (node (ref "SV122") (pin "3") (pinfunction "3_3") (pintype "passive"))
      (node (ref "SV122") (pin "5") (pinfunction "5_5") (pintype "passive"))
      (node (ref "SV122") (pin "7") (pinfunction "7_7") (pintype "passive"))
      (node (ref "SV122") (pin "9") (pinfunction "9_9") (pintype "passive"))
    )
    (net (code "729") (name "Net-(SV122-Pad10)") (class "Default")
      (node (ref "SV122") (pin "10") (pinfunction "10_10") (pintype "passive"))
      (node (ref "SV122") (pin "2") (pinfunction "2_2") (pintype "passive"))
      (node (ref "SV122") (pin "4") (pinfunction "4_4") (pintype "passive"))
      (node (ref "SV122") (pin "6") (pinfunction "6_6") (pintype "passive"))
      (node (ref "SV122") (pin "8") (pinfunction "8_8") (pintype "passive"))
    )
    (net (code "730") (name "Net-(SV123-Pad1)") (class "Default")
      (node (ref "SV123") (pin "1") (pinfunction "1_1") (pintype "passive"))
      (node (ref "SV123") (pin "3") (pinfunction "3_3") (pintype "passive"))
      (node (ref "SV123") (pin "5") (pinfunction "5_5") (pintype "passive"))
      (node (ref "SV123") (pin "7") (pinfunction "7_7") (pintype "passive"))
      (node (ref "SV123") (pin "9") (pinfunction "9_9") (pintype "passive"))
    )
    (net (code "731") (name "Net-(SV123-Pad10)") (class "Default")
      (node (ref "SV123") (pin "10") (pinfunction "10_10") (pintype "passive"))
      (node (ref "SV123") (pin "2") (pinfunction "2_2") (pintype "passive"))
      (node (ref "SV123") (pin "4") (pinfunction "4_4") (pintype "passive"))
      (node (ref "SV123") (pin "6") (pinfunction "6_6") (pintype "passive"))
      (node (ref "SV123") (pin "8") (pinfunction "8_8") (pintype "passive"))
    )
    (net (code "732") (name "Net-(SV124-Pad1)") (class "Default")
      (node (ref "SV124") (pin "1") (pinfunction "1_1") (pintype "passive"))
      (node (ref "SV124") (pin "3") (pinfunction "3_3") (pintype "passive"))
      (node (ref "SV124") (pin "5") (pinfunction "5_5") (pintype "passive"))
      (node (ref "SV124") (pin "7") (pinfunction "7_7") (pintype "passive"))
      (node (ref "SV124") (pin "9") (pinfunction "9_9") (pintype "passive"))
    )
    (net (code "733") (name "Net-(SV124-Pad10)") (class "Default")
      (node (ref "SV124") (pin "10") (pinfunction "10_10") (pintype "passive"))
      (node (ref "SV124") (pin "2") (pinfunction "2_2") (pintype "passive"))
      (node (ref "SV124") (pin "4") (pinfunction "4_4") (pintype "passive"))
      (node (ref "SV124") (pin "6") (pinfunction "6_6") (pintype "passive"))
      (node (ref "SV124") (pin "8") (pinfunction "8_8") (pintype "passive"))
    )
    (net (code "734") (name "Net-(SV126-Pad1)") (class "Default")
      (node (ref "SV126") (pin "1") (pinfunction "1_1") (pintype "passive"))
      (node (ref "SV126") (pin "3") (pinfunction "3_3") (pintype "passive"))
      (node (ref "SV126") (pin "5") (pinfunction "5_5") (pintype "passive"))
      (node (ref "SV126") (pin "7") (pinfunction "7_7") (pintype "passive"))
      (node (ref "SV126") (pin "9") (pinfunction "9_9") (pintype "passive"))
    )
    (net (code "735") (name "Net-(SV126-Pad10)") (class "Default")
      (node (ref "SV126") (pin "10") (pinfunction "10_10") (pintype "passive"))
      (node (ref "SV126") (pin "2") (pinfunction "2_2") (pintype "passive"))
      (node (ref "SV126") (pin "4") (pinfunction "4_4") (pintype "passive"))
      (node (ref "SV126") (pin "6") (pinfunction "6_6") (pintype "passive"))
      (node (ref "SV126") (pin "8") (pinfunction "8_8") (pintype "passive"))
    )
    (net (code "736") (name "Net-(SV128-Pad1)") (class "Default")
      (node (ref "SV128") (pin "1") (pinfunction "1_1") (pintype "passive"))
      (node (ref "SV128") (pin "3") (pinfunction "3_3") (pintype "passive"))
      (node (ref "SV128") (pin "5") (pinfunction "5_5") (pintype "passive"))
      (node (ref "SV128") (pin "7") (pinfunction "7_7") (pintype "passive"))
      (node (ref "SV128") (pin "9") (pinfunction "9_9") (pintype "passive"))
    )
    (net (code "737") (name "Net-(SV128-Pad10)") (class "Default")
      (node (ref "SV128") (pin "10") (pinfunction "10_10") (pintype "passive"))
      (node (ref "SV128") (pin "2") (pinfunction "2_2") (pintype "passive"))
      (node (ref "SV128") (pin "4") (pinfunction "4_4") (pintype "passive"))
      (node (ref "SV128") (pin "6") (pinfunction "6_6") (pintype "passive"))
      (node (ref "SV128") (pin "8") (pinfunction "8_8") (pintype "passive"))
    )
    (net (code "738") (name "Net-(SV130-Pad1)") (class "Default")
      (node (ref "SV130") (pin "1") (pinfunction "1_1") (pintype "passive"))
      (node (ref "SV130") (pin "3") (pinfunction "3_3") (pintype "passive"))
      (node (ref "SV130") (pin "5") (pinfunction "5_5") (pintype "passive"))
      (node (ref "SV130") (pin "7") (pinfunction "7_7") (pintype "passive"))
      (node (ref "SV130") (pin "9") (pinfunction "9_9") (pintype "passive"))
    )
    (net (code "739") (name "Net-(SV130-Pad10)") (class "Default")
      (node (ref "SV130") (pin "10") (pinfunction "10_10") (pintype "passive"))
      (node (ref "SV130") (pin "2") (pinfunction "2_2") (pintype "passive"))
      (node (ref "SV130") (pin "4") (pinfunction "4_4") (pintype "passive"))
      (node (ref "SV130") (pin "6") (pinfunction "6_6") (pintype "passive"))
      (node (ref "SV130") (pin "8") (pinfunction "8_8") (pintype "passive"))
    )
    (net (code "740") (name "Net-(SV132-Pad1)") (class "Default")
      (node (ref "SV132") (pin "1") (pinfunction "1_1") (pintype "passive"))
      (node (ref "SV132") (pin "3") (pinfunction "3_3") (pintype "passive"))
      (node (ref "SV132") (pin "5") (pinfunction "5_5") (pintype "passive"))
      (node (ref "SV132") (pin "7") (pinfunction "7_7") (pintype "passive"))
      (node (ref "SV132") (pin "9") (pinfunction "9_9") (pintype "passive"))
    )
    (net (code "741") (name "Net-(SV132-Pad10)") (class "Default")
      (node (ref "SV132") (pin "10") (pinfunction "10_10") (pintype "passive"))
      (node (ref "SV132") (pin "2") (pinfunction "2_2") (pintype "passive"))
      (node (ref "SV132") (pin "4") (pinfunction "4_4") (pintype "passive"))
      (node (ref "SV132") (pin "6") (pinfunction "6_6") (pintype "passive"))
      (node (ref "SV132") (pin "8") (pinfunction "8_8") (pintype "passive"))
    )
    (net (code "742") (name "Net-(SV133-Pad1)") (class "Default")
      (node (ref "SV133") (pin "1") (pinfunction "1_1") (pintype "passive"))
      (node (ref "SV133") (pin "3") (pinfunction "3_3") (pintype "passive"))
      (node (ref "SV133") (pin "5") (pinfunction "5_5") (pintype "passive"))
      (node (ref "SV133") (pin "7") (pinfunction "7_7") (pintype "passive"))
      (node (ref "SV133") (pin "9") (pinfunction "9_9") (pintype "passive"))
    )
    (net (code "743") (name "Net-(SV133-Pad10)") (class "Default")
      (node (ref "SV133") (pin "10") (pinfunction "10_10") (pintype "passive"))
      (node (ref "SV133") (pin "2") (pinfunction "2_2") (pintype "passive"))
      (node (ref "SV133") (pin "4") (pinfunction "4_4") (pintype "passive"))
      (node (ref "SV133") (pin "6") (pinfunction "6_6") (pintype "passive"))
      (node (ref "SV133") (pin "8") (pinfunction "8_8") (pintype "passive"))
    )
    (net (code "744") (name "Net-(SV134-Pad1)") (class "Default")
      (node (ref "SV134") (pin "1") (pinfunction "1_1") (pintype "passive"))
      (node (ref "SV134") (pin "3") (pinfunction "3_3") (pintype "passive"))
      (node (ref "SV134") (pin "5") (pinfunction "5_5") (pintype "passive"))
      (node (ref "SV134") (pin "7") (pinfunction "7_7") (pintype "passive"))
      (node (ref "SV134") (pin "9") (pinfunction "9_9") (pintype "passive"))
    )
    (net (code "745") (name "Net-(SV134-Pad10)") (class "Default")
      (node (ref "SV134") (pin "10") (pinfunction "10_10") (pintype "passive"))
      (node (ref "SV134") (pin "2") (pinfunction "2_2") (pintype "passive"))
      (node (ref "SV134") (pin "4") (pinfunction "4_4") (pintype "passive"))
      (node (ref "SV134") (pin "6") (pinfunction "6_6") (pintype "passive"))
      (node (ref "SV134") (pin "8") (pinfunction "8_8") (pintype "passive"))
    )
    (net (code "746") (name "Net-(SV135-Pad1)") (class "Default")
      (node (ref "SV135") (pin "1") (pinfunction "1_1") (pintype "passive"))
      (node (ref "SV135") (pin "3") (pinfunction "3_3") (pintype "passive"))
      (node (ref "SV135") (pin "5") (pinfunction "5_5") (pintype "passive"))
      (node (ref "SV135") (pin "7") (pinfunction "7_7") (pintype "passive"))
      (node (ref "SV135") (pin "9") (pinfunction "9_9") (pintype "passive"))
    )
    (net (code "747") (name "Net-(SV135-Pad10)") (class "Default")
      (node (ref "SV135") (pin "10") (pinfunction "10_10") (pintype "passive"))
      (node (ref "SV135") (pin "2") (pinfunction "2_2") (pintype "passive"))
      (node (ref "SV135") (pin "4") (pinfunction "4_4") (pintype "passive"))
      (node (ref "SV135") (pin "6") (pinfunction "6_6") (pintype "passive"))
      (node (ref "SV135") (pin "8") (pinfunction "8_8") (pintype "passive"))
    )
    (net (code "748") (name "Net-(SV136-Pad1)") (class "Default")
      (node (ref "SV136") (pin "1") (pinfunction "1_1") (pintype "passive"))
      (node (ref "SV136") (pin "3") (pinfunction "3_3") (pintype "passive"))
      (node (ref "SV136") (pin "5") (pinfunction "5_5") (pintype "passive"))
      (node (ref "SV136") (pin "7") (pinfunction "7_7") (pintype "passive"))
      (node (ref "SV136") (pin "9") (pinfunction "9_9") (pintype "passive"))
    )
    (net (code "749") (name "Net-(SV136-Pad10)") (class "Default")
      (node (ref "SV136") (pin "10") (pinfunction "10_10") (pintype "passive"))
      (node (ref "SV136") (pin "2") (pinfunction "2_2") (pintype "passive"))
      (node (ref "SV136") (pin "4") (pinfunction "4_4") (pintype "passive"))
      (node (ref "SV136") (pin "6") (pinfunction "6_6") (pintype "passive"))
      (node (ref "SV136") (pin "8") (pinfunction "8_8") (pintype "passive"))
    )
    (net (code "750") (name "Net-(SV137-Pad1)") (class "Default")
      (node (ref "SV137") (pin "1") (pinfunction "1_1") (pintype "passive"))
      (node (ref "SV137") (pin "3") (pinfunction "3_3") (pintype "passive"))
      (node (ref "SV137") (pin "5") (pinfunction "5_5") (pintype "passive"))
      (node (ref "SV137") (pin "7") (pinfunction "7_7") (pintype "passive"))
      (node (ref "SV137") (pin "9") (pinfunction "9_9") (pintype "passive"))
    )
    (net (code "751") (name "Net-(SV137-Pad10)") (class "Default")
      (node (ref "SV137") (pin "10") (pinfunction "10_10") (pintype "passive"))
      (node (ref "SV137") (pin "2") (pinfunction "2_2") (pintype "passive"))
      (node (ref "SV137") (pin "4") (pinfunction "4_4") (pintype "passive"))
      (node (ref "SV137") (pin "6") (pinfunction "6_6") (pintype "passive"))
      (node (ref "SV137") (pin "8") (pinfunction "8_8") (pintype "passive"))
    )
    (net (code "752") (name "Net-(SV138-Pad1)") (class "Default")
      (node (ref "SV138") (pin "1") (pinfunction "1_1") (pintype "passive"))
      (node (ref "SV138") (pin "3") (pinfunction "3_3") (pintype "passive"))
      (node (ref "SV138") (pin "5") (pinfunction "5_5") (pintype "passive"))
      (node (ref "SV138") (pin "7") (pinfunction "7_7") (pintype "passive"))
      (node (ref "SV138") (pin "9") (pinfunction "9_9") (pintype "passive"))
    )
    (net (code "753") (name "Net-(SV138-Pad10)") (class "Default")
      (node (ref "SV138") (pin "10") (pinfunction "10_10") (pintype "passive"))
      (node (ref "SV138") (pin "2") (pinfunction "2_2") (pintype "passive"))
      (node (ref "SV138") (pin "4") (pinfunction "4_4") (pintype "passive"))
      (node (ref "SV138") (pin "6") (pinfunction "6_6") (pintype "passive"))
      (node (ref "SV138") (pin "8") (pinfunction "8_8") (pintype "passive"))
    )
    (net (code "754") (name "Net-(SV139-Pad1)") (class "Default")
      (node (ref "SV139") (pin "1") (pinfunction "1_1") (pintype "passive"))
      (node (ref "SV139") (pin "3") (pinfunction "3_3") (pintype "passive"))
      (node (ref "SV139") (pin "5") (pinfunction "5_5") (pintype "passive"))
      (node (ref "SV139") (pin "7") (pinfunction "7_7") (pintype "passive"))
      (node (ref "SV139") (pin "9") (pinfunction "9_9") (pintype "passive"))
    )
    (net (code "755") (name "Net-(SV139-Pad10)") (class "Default")
      (node (ref "SV139") (pin "10") (pinfunction "10_10") (pintype "passive"))
      (node (ref "SV139") (pin "2") (pinfunction "2_2") (pintype "passive"))
      (node (ref "SV139") (pin "4") (pinfunction "4_4") (pintype "passive"))
      (node (ref "SV139") (pin "6") (pinfunction "6_6") (pintype "passive"))
      (node (ref "SV139") (pin "8") (pinfunction "8_8") (pintype "passive"))
    )
    (net (code "756") (name "Net-(SV140-Pad1)") (class "Default")
      (node (ref "SV140") (pin "1") (pinfunction "1_1") (pintype "passive"))
      (node (ref "SV140") (pin "3") (pinfunction "3_3") (pintype "passive"))
      (node (ref "SV140") (pin "5") (pinfunction "5_5") (pintype "passive"))
      (node (ref "SV140") (pin "7") (pinfunction "7_7") (pintype "passive"))
      (node (ref "SV140") (pin "9") (pinfunction "9_9") (pintype "passive"))
    )
    (net (code "757") (name "Net-(SV140-Pad10)") (class "Default")
      (node (ref "SV140") (pin "10") (pinfunction "10_10") (pintype "passive"))
      (node (ref "SV140") (pin "2") (pinfunction "2_2") (pintype "passive"))
      (node (ref "SV140") (pin "4") (pinfunction "4_4") (pintype "passive"))
      (node (ref "SV140") (pin "6") (pinfunction "6_6") (pintype "passive"))
      (node (ref "SV140") (pin "8") (pinfunction "8_8") (pintype "passive"))
    )
    (net (code "758") (name "Net-(SV141-Pad1)") (class "Default")
      (node (ref "SV141") (pin "1") (pinfunction "1_1") (pintype "passive"))
      (node (ref "SV141") (pin "3") (pinfunction "3_3") (pintype "passive"))
      (node (ref "SV141") (pin "5") (pinfunction "5_5") (pintype "passive"))
      (node (ref "SV141") (pin "7") (pinfunction "7_7") (pintype "passive"))
      (node (ref "SV141") (pin "9") (pinfunction "9_9") (pintype "passive"))
    )
    (net (code "759") (name "Net-(SV141-Pad10)") (class "Default")
      (node (ref "SV141") (pin "10") (pinfunction "10_10") (pintype "passive"))
      (node (ref "SV141") (pin "2") (pinfunction "2_2") (pintype "passive"))
      (node (ref "SV141") (pin "4") (pinfunction "4_4") (pintype "passive"))
      (node (ref "SV141") (pin "6") (pinfunction "6_6") (pintype "passive"))
      (node (ref "SV141") (pin "8") (pinfunction "8_8") (pintype "passive"))
    )
    (net (code "760") (name "Net-(SV142-Pad1)") (class "Default")
      (node (ref "SV142") (pin "1") (pinfunction "1_1") (pintype "passive"))
      (node (ref "SV142") (pin "3") (pinfunction "3_3") (pintype "passive"))
      (node (ref "SV142") (pin "5") (pinfunction "5_5") (pintype "passive"))
      (node (ref "SV142") (pin "7") (pinfunction "7_7") (pintype "passive"))
      (node (ref "SV142") (pin "9") (pinfunction "9_9") (pintype "passive"))
    )
    (net (code "761") (name "Net-(SV142-Pad10)") (class "Default")
      (node (ref "SV142") (pin "10") (pinfunction "10_10") (pintype "passive"))
      (node (ref "SV142") (pin "2") (pinfunction "2_2") (pintype "passive"))
      (node (ref "SV142") (pin "4") (pinfunction "4_4") (pintype "passive"))
      (node (ref "SV142") (pin "6") (pinfunction "6_6") (pintype "passive"))
      (node (ref "SV142") (pin "8") (pinfunction "8_8") (pintype "passive"))
    )
    (net (code "762") (name "Net-(SV143-Pad1)") (class "Default")
      (node (ref "SV143") (pin "1") (pinfunction "1_1") (pintype "passive"))
      (node (ref "SV143") (pin "3") (pinfunction "3_3") (pintype "passive"))
      (node (ref "SV143") (pin "5") (pinfunction "5_5") (pintype "passive"))
      (node (ref "SV143") (pin "7") (pinfunction "7_7") (pintype "passive"))
      (node (ref "SV143") (pin "9") (pinfunction "9_9") (pintype "passive"))
    )
    (net (code "763") (name "Net-(SV143-Pad10)") (class "Default")
      (node (ref "SV143") (pin "10") (pinfunction "10_10") (pintype "passive"))
      (node (ref "SV143") (pin "2") (pinfunction "2_2") (pintype "passive"))
      (node (ref "SV143") (pin "4") (pinfunction "4_4") (pintype "passive"))
      (node (ref "SV143") (pin "6") (pinfunction "6_6") (pintype "passive"))
      (node (ref "SV143") (pin "8") (pinfunction "8_8") (pintype "passive"))
    )
    (net (code "764") (name "Net-(SV144-Pad1)") (class "Default")
      (node (ref "SV144") (pin "1") (pinfunction "1_1") (pintype "passive"))
      (node (ref "SV144") (pin "3") (pinfunction "3_3") (pintype "passive"))
      (node (ref "SV144") (pin "5") (pinfunction "5_5") (pintype "passive"))
      (node (ref "SV144") (pin "7") (pinfunction "7_7") (pintype "passive"))
      (node (ref "SV144") (pin "9") (pinfunction "9_9") (pintype "passive"))
    )
    (net (code "765") (name "Net-(SV144-Pad10)") (class "Default")
      (node (ref "SV144") (pin "10") (pinfunction "10_10") (pintype "passive"))
      (node (ref "SV144") (pin "2") (pinfunction "2_2") (pintype "passive"))
      (node (ref "SV144") (pin "4") (pinfunction "4_4") (pintype "passive"))
      (node (ref "SV144") (pin "6") (pinfunction "6_6") (pintype "passive"))
      (node (ref "SV144") (pin "8") (pinfunction "8_8") (pintype "passive"))
    )
    (net (code "766") (name "Net-(SV145-Pad1)") (class "Default")
      (node (ref "SV145") (pin "1") (pinfunction "1_1") (pintype "passive"))
      (node (ref "SV145") (pin "3") (pinfunction "3_3") (pintype "passive"))
      (node (ref "SV145") (pin "5") (pinfunction "5_5") (pintype "passive"))
      (node (ref "SV145") (pin "7") (pinfunction "7_7") (pintype "passive"))
      (node (ref "SV145") (pin "9") (pinfunction "9_9") (pintype "passive"))
    )
    (net (code "767") (name "Net-(SV145-Pad10)") (class "Default")
      (node (ref "SV145") (pin "10") (pinfunction "10_10") (pintype "passive"))
      (node (ref "SV145") (pin "2") (pinfunction "2_2") (pintype "passive"))
      (node (ref "SV145") (pin "4") (pinfunction "4_4") (pintype "passive"))
      (node (ref "SV145") (pin "6") (pinfunction "6_6") (pintype "passive"))
      (node (ref "SV145") (pin "8") (pinfunction "8_8") (pintype "passive"))
    )
    (net (code "768") (name "Net-(SV146-Pad1)") (class "Default")
      (node (ref "SV146") (pin "1") (pinfunction "1_1") (pintype "passive"))
      (node (ref "SV146") (pin "3") (pinfunction "3_3") (pintype "passive"))
      (node (ref "SV146") (pin "5") (pinfunction "5_5") (pintype "passive"))
      (node (ref "SV146") (pin "7") (pinfunction "7_7") (pintype "passive"))
      (node (ref "SV146") (pin "9") (pinfunction "9_9") (pintype "passive"))
    )
    (net (code "769") (name "Net-(SV146-Pad10)") (class "Default")
      (node (ref "SV146") (pin "10") (pinfunction "10_10") (pintype "passive"))
      (node (ref "SV146") (pin "2") (pinfunction "2_2") (pintype "passive"))
      (node (ref "SV146") (pin "4") (pinfunction "4_4") (pintype "passive"))
      (node (ref "SV146") (pin "6") (pinfunction "6_6") (pintype "passive"))
      (node (ref "SV146") (pin "8") (pinfunction "8_8") (pintype "passive"))
    )
    (net (code "770") (name "Net-(SV147-Pad1)") (class "Default")
      (node (ref "SV147") (pin "1") (pinfunction "1_1") (pintype "passive"))
      (node (ref "SV147") (pin "3") (pinfunction "3_3") (pintype "passive"))
      (node (ref "SV147") (pin "5") (pinfunction "5_5") (pintype "passive"))
      (node (ref "SV147") (pin "7") (pinfunction "7_7") (pintype "passive"))
      (node (ref "SV147") (pin "9") (pinfunction "9_9") (pintype "passive"))
    )
    (net (code "771") (name "Net-(SV147-Pad10)") (class "Default")
      (node (ref "SV147") (pin "10") (pinfunction "10_10") (pintype "passive"))
      (node (ref "SV147") (pin "2") (pinfunction "2_2") (pintype "passive"))
      (node (ref "SV147") (pin "4") (pinfunction "4_4") (pintype "passive"))
      (node (ref "SV147") (pin "6") (pinfunction "6_6") (pintype "passive"))
      (node (ref "SV147") (pin "8") (pinfunction "8_8") (pintype "passive"))
    )
    (net (code "772") (name "Net-(SV148-Pad1)") (class "Default")
      (node (ref "SV148") (pin "1") (pinfunction "1_1") (pintype "passive"))
      (node (ref "SV148") (pin "3") (pinfunction "3_3") (pintype "passive"))
      (node (ref "SV148") (pin "5") (pinfunction "5_5") (pintype "passive"))
      (node (ref "SV148") (pin "7") (pinfunction "7_7") (pintype "passive"))
      (node (ref "SV148") (pin "9") (pinfunction "9_9") (pintype "passive"))
    )
    (net (code "773") (name "Net-(SV148-Pad10)") (class "Default")
      (node (ref "SV148") (pin "10") (pinfunction "10_10") (pintype "passive"))
      (node (ref "SV148") (pin "2") (pinfunction "2_2") (pintype "passive"))
      (node (ref "SV148") (pin "4") (pinfunction "4_4") (pintype "passive"))
      (node (ref "SV148") (pin "6") (pinfunction "6_6") (pintype "passive"))
      (node (ref "SV148") (pin "8") (pinfunction "8_8") (pintype "passive"))
    )
    (net (code "774") (name "Net-(SV149-Pad1)") (class "Default")
      (node (ref "SV149") (pin "1") (pinfunction "1_1") (pintype "passive"))
      (node (ref "SV149") (pin "3") (pinfunction "3_3") (pintype "passive"))
      (node (ref "SV149") (pin "5") (pinfunction "5_5") (pintype "passive"))
      (node (ref "SV149") (pin "7") (pinfunction "7_7") (pintype "passive"))
      (node (ref "SV149") (pin "9") (pinfunction "9_9") (pintype "passive"))
    )
    (net (code "775") (name "Net-(SV149-Pad10)") (class "Default")
      (node (ref "SV149") (pin "10") (pinfunction "10_10") (pintype "passive"))
      (node (ref "SV149") (pin "2") (pinfunction "2_2") (pintype "passive"))
      (node (ref "SV149") (pin "4") (pinfunction "4_4") (pintype "passive"))
      (node (ref "SV149") (pin "6") (pinfunction "6_6") (pintype "passive"))
      (node (ref "SV149") (pin "8") (pinfunction "8_8") (pintype "passive"))
    )
    (net (code "776") (name "Net-(SV150-Pad1)") (class "Default")
      (node (ref "SV150") (pin "1") (pinfunction "1_1") (pintype "passive"))
      (node (ref "SV150") (pin "3") (pinfunction "3_3") (pintype "passive"))
      (node (ref "SV150") (pin "5") (pinfunction "5_5") (pintype "passive"))
      (node (ref "SV150") (pin "7") (pinfunction "7_7") (pintype "passive"))
      (node (ref "SV150") (pin "9") (pinfunction "9_9") (pintype "passive"))
    )
    (net (code "777") (name "Net-(SV150-Pad10)") (class "Default")
      (node (ref "SV150") (pin "10") (pinfunction "10_10") (pintype "passive"))
      (node (ref "SV150") (pin "2") (pinfunction "2_2") (pintype "passive"))
      (node (ref "SV150") (pin "4") (pinfunction "4_4") (pintype "passive"))
      (node (ref "SV150") (pin "6") (pinfunction "6_6") (pintype "passive"))
      (node (ref "SV150") (pin "8") (pinfunction "8_8") (pintype "passive"))
    )
    (net (code "778") (name "Net-(SV151-Pad1)") (class "Default")
      (node (ref "SV151") (pin "1") (pinfunction "1_1") (pintype "passive"))
      (node (ref "SV151") (pin "3") (pinfunction "3_3") (pintype "passive"))
      (node (ref "SV151") (pin "5") (pinfunction "5_5") (pintype "passive"))
      (node (ref "SV151") (pin "7") (pinfunction "7_7") (pintype "passive"))
      (node (ref "SV151") (pin "9") (pinfunction "9_9") (pintype "passive"))
    )
    (net (code "779") (name "Net-(SV151-Pad10)") (class "Default")
      (node (ref "SV151") (pin "10") (pinfunction "10_10") (pintype "passive"))
      (node (ref "SV151") (pin "2") (pinfunction "2_2") (pintype "passive"))
      (node (ref "SV151") (pin "4") (pinfunction "4_4") (pintype "passive"))
      (node (ref "SV151") (pin "6") (pinfunction "6_6") (pintype "passive"))
      (node (ref "SV151") (pin "8") (pinfunction "8_8") (pintype "passive"))
    )
    (net (code "780") (name "Net-(SV152-Pad1)") (class "Default")
      (node (ref "SV152") (pin "1") (pinfunction "1_1") (pintype "passive"))
      (node (ref "SV152") (pin "3") (pinfunction "3_3") (pintype "passive"))
      (node (ref "SV152") (pin "5") (pinfunction "5_5") (pintype "passive"))
      (node (ref "SV152") (pin "7") (pinfunction "7_7") (pintype "passive"))
      (node (ref "SV152") (pin "9") (pinfunction "9_9") (pintype "passive"))
    )
    (net (code "781") (name "Net-(SV152-Pad10)") (class "Default")
      (node (ref "SV152") (pin "10") (pinfunction "10_10") (pintype "passive"))
      (node (ref "SV152") (pin "2") (pinfunction "2_2") (pintype "passive"))
      (node (ref "SV152") (pin "4") (pinfunction "4_4") (pintype "passive"))
      (node (ref "SV152") (pin "6") (pinfunction "6_6") (pintype "passive"))
      (node (ref "SV152") (pin "8") (pinfunction "8_8") (pintype "passive"))
    )
    (net (code "782") (name "Net-(SV153-Pad1)") (class "Default")
      (node (ref "SV153") (pin "1") (pinfunction "1_1") (pintype "passive"))
      (node (ref "SV153") (pin "3") (pinfunction "3_3") (pintype "passive"))
      (node (ref "SV153") (pin "5") (pinfunction "5_5") (pintype "passive"))
      (node (ref "SV153") (pin "7") (pinfunction "7_7") (pintype "passive"))
      (node (ref "SV153") (pin "9") (pinfunction "9_9") (pintype "passive"))
    )
    (net (code "783") (name "Net-(SV153-Pad10)") (class "Default")
      (node (ref "SV153") (pin "10") (pinfunction "10_10") (pintype "passive"))
      (node (ref "SV153") (pin "2") (pinfunction "2_2") (pintype "passive"))
      (node (ref "SV153") (pin "4") (pinfunction "4_4") (pintype "passive"))
      (node (ref "SV153") (pin "6") (pinfunction "6_6") (pintype "passive"))
      (node (ref "SV153") (pin "8") (pinfunction "8_8") (pintype "passive"))
    )
    (net (code "784") (name "Net-(SV154-Pad1)") (class "Default")
      (node (ref "SV154") (pin "1") (pinfunction "1_1") (pintype "passive"))
      (node (ref "SV154") (pin "3") (pinfunction "3_3") (pintype "passive"))
      (node (ref "SV154") (pin "5") (pinfunction "5_5") (pintype "passive"))
      (node (ref "SV154") (pin "7") (pinfunction "7_7") (pintype "passive"))
      (node (ref "SV154") (pin "9") (pinfunction "9_9") (pintype "passive"))
    )
    (net (code "785") (name "Net-(SV154-Pad10)") (class "Default")
      (node (ref "SV154") (pin "10") (pinfunction "10_10") (pintype "passive"))
      (node (ref "SV154") (pin "2") (pinfunction "2_2") (pintype "passive"))
      (node (ref "SV154") (pin "4") (pinfunction "4_4") (pintype "passive"))
      (node (ref "SV154") (pin "6") (pinfunction "6_6") (pintype "passive"))
      (node (ref "SV154") (pin "8") (pinfunction "8_8") (pintype "passive"))
    )
    (net (code "786") (name "Net-(SV155-Pad1)") (class "Default")
      (node (ref "SV155") (pin "1") (pinfunction "1_1") (pintype "passive"))
      (node (ref "SV155") (pin "3") (pinfunction "3_3") (pintype "passive"))
      (node (ref "SV155") (pin "5") (pinfunction "5_5") (pintype "passive"))
      (node (ref "SV155") (pin "7") (pinfunction "7_7") (pintype "passive"))
      (node (ref "SV155") (pin "9") (pinfunction "9_9") (pintype "passive"))
    )
    (net (code "787") (name "Net-(SV155-Pad10)") (class "Default")
      (node (ref "SV155") (pin "10") (pinfunction "10_10") (pintype "passive"))
      (node (ref "SV155") (pin "2") (pinfunction "2_2") (pintype "passive"))
      (node (ref "SV155") (pin "4") (pinfunction "4_4") (pintype "passive"))
      (node (ref "SV155") (pin "6") (pinfunction "6_6") (pintype "passive"))
      (node (ref "SV155") (pin "8") (pinfunction "8_8") (pintype "passive"))
    )
    (net (code "788") (name "Net-(SV156-Pad1)") (class "Default")
      (node (ref "SV156") (pin "1") (pinfunction "1_1") (pintype "passive"))
      (node (ref "SV156") (pin "3") (pinfunction "3_3") (pintype "passive"))
      (node (ref "SV156") (pin "5") (pinfunction "5_5") (pintype "passive"))
      (node (ref "SV156") (pin "7") (pinfunction "7_7") (pintype "passive"))
      (node (ref "SV156") (pin "9") (pinfunction "9_9") (pintype "passive"))
    )
    (net (code "789") (name "Net-(SV156-Pad10)") (class "Default")
      (node (ref "SV156") (pin "10") (pinfunction "10_10") (pintype "passive"))
      (node (ref "SV156") (pin "2") (pinfunction "2_2") (pintype "passive"))
      (node (ref "SV156") (pin "4") (pinfunction "4_4") (pintype "passive"))
      (node (ref "SV156") (pin "6") (pinfunction "6_6") (pintype "passive"))
      (node (ref "SV156") (pin "8") (pinfunction "8_8") (pintype "passive"))
    )
    (net (code "790") (name "Net-(SV157-Pad1)") (class "Default")
      (node (ref "SV157") (pin "1") (pinfunction "1_1") (pintype "passive"))
      (node (ref "SV157") (pin "3") (pinfunction "3_3") (pintype "passive"))
      (node (ref "SV157") (pin "5") (pinfunction "5_5") (pintype "passive"))
      (node (ref "SV157") (pin "7") (pinfunction "7_7") (pintype "passive"))
      (node (ref "SV157") (pin "9") (pinfunction "9_9") (pintype "passive"))
    )
    (net (code "791") (name "Net-(SV157-Pad10)") (class "Default")
      (node (ref "SV157") (pin "10") (pinfunction "10_10") (pintype "passive"))
      (node (ref "SV157") (pin "2") (pinfunction "2_2") (pintype "passive"))
      (node (ref "SV157") (pin "4") (pinfunction "4_4") (pintype "passive"))
      (node (ref "SV157") (pin "6") (pinfunction "6_6") (pintype "passive"))
      (node (ref "SV157") (pin "8") (pinfunction "8_8") (pintype "passive"))
    )
    (net (code "792") (name "Net-(SV158-Pad1)") (class "Default")
      (node (ref "SV158") (pin "1") (pinfunction "1_1") (pintype "passive"))
      (node (ref "SV158") (pin "3") (pinfunction "3_3") (pintype "passive"))
      (node (ref "SV158") (pin "5") (pinfunction "5_5") (pintype "passive"))
      (node (ref "SV158") (pin "7") (pinfunction "7_7") (pintype "passive"))
      (node (ref "SV158") (pin "9") (pinfunction "9_9") (pintype "passive"))
    )
    (net (code "793") (name "Net-(SV158-Pad10)") (class "Default")
      (node (ref "SV158") (pin "10") (pinfunction "10_10") (pintype "passive"))
      (node (ref "SV158") (pin "2") (pinfunction "2_2") (pintype "passive"))
      (node (ref "SV158") (pin "4") (pinfunction "4_4") (pintype "passive"))
      (node (ref "SV158") (pin "6") (pinfunction "6_6") (pintype "passive"))
      (node (ref "SV158") (pin "8") (pinfunction "8_8") (pintype "passive"))
    )
    (net (code "794") (name "Net-(SV159-Pad1)") (class "Default")
      (node (ref "SV159") (pin "1") (pinfunction "1_1") (pintype "passive"))
      (node (ref "SV159") (pin "3") (pinfunction "3_3") (pintype "passive"))
      (node (ref "SV159") (pin "5") (pinfunction "5_5") (pintype "passive"))
      (node (ref "SV159") (pin "7") (pinfunction "7_7") (pintype "passive"))
      (node (ref "SV159") (pin "9") (pinfunction "9_9") (pintype "passive"))
    )
    (net (code "795") (name "Net-(SV159-Pad10)") (class "Default")
      (node (ref "SV159") (pin "10") (pinfunction "10_10") (pintype "passive"))
      (node (ref "SV159") (pin "2") (pinfunction "2_2") (pintype "passive"))
      (node (ref "SV159") (pin "4") (pinfunction "4_4") (pintype "passive"))
      (node (ref "SV159") (pin "6") (pinfunction "6_6") (pintype "passive"))
      (node (ref "SV159") (pin "8") (pinfunction "8_8") (pintype "passive"))
    )
    (net (code "796") (name "Net-(SV160-Pad1)") (class "Default")
      (node (ref "SV160") (pin "1") (pinfunction "1_1") (pintype "passive"))
      (node (ref "SV160") (pin "3") (pinfunction "3_3") (pintype "passive"))
      (node (ref "SV160") (pin "5") (pinfunction "5_5") (pintype "passive"))
      (node (ref "SV160") (pin "7") (pinfunction "7_7") (pintype "passive"))
      (node (ref "SV160") (pin "9") (pinfunction "9_9") (pintype "passive"))
    )
    (net (code "797") (name "Net-(SV160-Pad10)") (class "Default")
      (node (ref "SV160") (pin "10") (pinfunction "10_10") (pintype "passive"))
      (node (ref "SV160") (pin "2") (pinfunction "2_2") (pintype "passive"))
      (node (ref "SV160") (pin "4") (pinfunction "4_4") (pintype "passive"))
      (node (ref "SV160") (pin "6") (pinfunction "6_6") (pintype "passive"))
      (node (ref "SV160") (pin "8") (pinfunction "8_8") (pintype "passive"))
    )
    (net (code "798") (name "Net-(SV161-Pad1)") (class "Default")
      (node (ref "SV161") (pin "1") (pinfunction "1_1") (pintype "passive"))
      (node (ref "SV161") (pin "3") (pinfunction "3_3") (pintype "passive"))
      (node (ref "SV161") (pin "5") (pinfunction "5_5") (pintype "passive"))
      (node (ref "SV161") (pin "7") (pinfunction "7_7") (pintype "passive"))
      (node (ref "SV161") (pin "9") (pinfunction "9_9") (pintype "passive"))
    )
    (net (code "799") (name "Net-(SV161-Pad10)") (class "Default")
      (node (ref "SV161") (pin "10") (pinfunction "10_10") (pintype "passive"))
      (node (ref "SV161") (pin "2") (pinfunction "2_2") (pintype "passive"))
      (node (ref "SV161") (pin "4") (pinfunction "4_4") (pintype "passive"))
      (node (ref "SV161") (pin "6") (pinfunction "6_6") (pintype "passive"))
      (node (ref "SV161") (pin "8") (pinfunction "8_8") (pintype "passive"))
    )
    (net (code "800") (name "Net-(SV162-Pad1)") (class "Default")
      (node (ref "SV162") (pin "1") (pinfunction "1_1") (pintype "passive"))
      (node (ref "SV162") (pin "3") (pinfunction "3_3") (pintype "passive"))
      (node (ref "SV162") (pin "5") (pinfunction "5_5") (pintype "passive"))
      (node (ref "SV162") (pin "7") (pinfunction "7_7") (pintype "passive"))
      (node (ref "SV162") (pin "9") (pinfunction "9_9") (pintype "passive"))
    )
    (net (code "801") (name "Net-(SV162-Pad10)") (class "Default")
      (node (ref "SV162") (pin "10") (pinfunction "10_10") (pintype "passive"))
      (node (ref "SV162") (pin "2") (pinfunction "2_2") (pintype "passive"))
      (node (ref "SV162") (pin "4") (pinfunction "4_4") (pintype "passive"))
      (node (ref "SV162") (pin "6") (pinfunction "6_6") (pintype "passive"))
      (node (ref "SV162") (pin "8") (pinfunction "8_8") (pintype "passive"))
    )
    (net (code "802") (name "Net-(SV163-Pad1)") (class "Default")
      (node (ref "SV163") (pin "1") (pinfunction "1_1") (pintype "passive"))
      (node (ref "SV163") (pin "3") (pinfunction "3_3") (pintype "passive"))
      (node (ref "SV163") (pin "5") (pinfunction "5_5") (pintype "passive"))
      (node (ref "SV163") (pin "7") (pinfunction "7_7") (pintype "passive"))
      (node (ref "SV163") (pin "9") (pinfunction "9_9") (pintype "passive"))
    )
    (net (code "803") (name "Net-(SV163-Pad10)") (class "Default")
      (node (ref "SV163") (pin "10") (pinfunction "10_10") (pintype "passive"))
      (node (ref "SV163") (pin "2") (pinfunction "2_2") (pintype "passive"))
      (node (ref "SV163") (pin "4") (pinfunction "4_4") (pintype "passive"))
      (node (ref "SV163") (pin "6") (pinfunction "6_6") (pintype "passive"))
      (node (ref "SV163") (pin "8") (pinfunction "8_8") (pintype "passive"))
    )
    (net (code "804") (name "Net-(SV164-Pad1)") (class "Default")
      (node (ref "SV164") (pin "1") (pinfunction "1_1") (pintype "passive"))
      (node (ref "SV164") (pin "3") (pinfunction "3_3") (pintype "passive"))
      (node (ref "SV164") (pin "5") (pinfunction "5_5") (pintype "passive"))
      (node (ref "SV164") (pin "7") (pinfunction "7_7") (pintype "passive"))
      (node (ref "SV164") (pin "9") (pinfunction "9_9") (pintype "passive"))
    )
    (net (code "805") (name "Net-(SV164-Pad10)") (class "Default")
      (node (ref "SV164") (pin "10") (pinfunction "10_10") (pintype "passive"))
      (node (ref "SV164") (pin "2") (pinfunction "2_2") (pintype "passive"))
      (node (ref "SV164") (pin "4") (pinfunction "4_4") (pintype "passive"))
      (node (ref "SV164") (pin "6") (pinfunction "6_6") (pintype "passive"))
      (node (ref "SV164") (pin "8") (pinfunction "8_8") (pintype "passive"))
    )
    (net (code "806") (name "Net-(SV165-Pad1)") (class "Default")
      (node (ref "SV165") (pin "1") (pinfunction "1_1") (pintype "passive"))
      (node (ref "SV165") (pin "3") (pinfunction "3_3") (pintype "passive"))
      (node (ref "SV165") (pin "5") (pinfunction "5_5") (pintype "passive"))
      (node (ref "SV165") (pin "7") (pinfunction "7_7") (pintype "passive"))
      (node (ref "SV165") (pin "9") (pinfunction "9_9") (pintype "passive"))
    )
    (net (code "807") (name "Net-(SV165-Pad10)") (class "Default")
      (node (ref "SV165") (pin "10") (pinfunction "10_10") (pintype "passive"))
      (node (ref "SV165") (pin "2") (pinfunction "2_2") (pintype "passive"))
      (node (ref "SV165") (pin "4") (pinfunction "4_4") (pintype "passive"))
      (node (ref "SV165") (pin "6") (pinfunction "6_6") (pintype "passive"))
      (node (ref "SV165") (pin "8") (pinfunction "8_8") (pintype "passive"))
    )
    (net (code "808") (name "Net-(SV166-Pad1)") (class "Default")
      (node (ref "SV166") (pin "1") (pinfunction "1_1") (pintype "passive"))
      (node (ref "SV166") (pin "3") (pinfunction "3_3") (pintype "passive"))
      (node (ref "SV166") (pin "5") (pinfunction "5_5") (pintype "passive"))
      (node (ref "SV166") (pin "7") (pinfunction "7_7") (pintype "passive"))
      (node (ref "SV166") (pin "9") (pinfunction "9_9") (pintype "passive"))
    )
    (net (code "809") (name "Net-(SV166-Pad10)") (class "Default")
      (node (ref "SV166") (pin "10") (pinfunction "10_10") (pintype "passive"))
      (node (ref "SV166") (pin "2") (pinfunction "2_2") (pintype "passive"))
      (node (ref "SV166") (pin "4") (pinfunction "4_4") (pintype "passive"))
      (node (ref "SV166") (pin "6") (pinfunction "6_6") (pintype "passive"))
      (node (ref "SV166") (pin "8") (pinfunction "8_8") (pintype "passive"))
    )
    (net (code "810") (name "Net-(SV167-Pad1)") (class "Default")
      (node (ref "SV167") (pin "1") (pinfunction "1_1") (pintype "passive"))
      (node (ref "SV167") (pin "3") (pinfunction "3_3") (pintype "passive"))
      (node (ref "SV167") (pin "5") (pinfunction "5_5") (pintype "passive"))
      (node (ref "SV167") (pin "7") (pinfunction "7_7") (pintype "passive"))
      (node (ref "SV167") (pin "9") (pinfunction "9_9") (pintype "passive"))
    )
    (net (code "811") (name "Net-(SV167-Pad10)") (class "Default")
      (node (ref "SV167") (pin "10") (pinfunction "10_10") (pintype "passive"))
      (node (ref "SV167") (pin "2") (pinfunction "2_2") (pintype "passive"))
      (node (ref "SV167") (pin "4") (pinfunction "4_4") (pintype "passive"))
      (node (ref "SV167") (pin "6") (pinfunction "6_6") (pintype "passive"))
      (node (ref "SV167") (pin "8") (pinfunction "8_8") (pintype "passive"))
    )
    (net (code "812") (name "Net-(SV168-Pad1)") (class "Default")
      (node (ref "SV168") (pin "1") (pinfunction "1_1") (pintype "passive"))
      (node (ref "SV168") (pin "3") (pinfunction "3_3") (pintype "passive"))
      (node (ref "SV168") (pin "5") (pinfunction "5_5") (pintype "passive"))
      (node (ref "SV168") (pin "7") (pinfunction "7_7") (pintype "passive"))
      (node (ref "SV168") (pin "9") (pinfunction "9_9") (pintype "passive"))
    )
    (net (code "813") (name "Net-(SV168-Pad10)") (class "Default")
      (node (ref "SV168") (pin "10") (pinfunction "10_10") (pintype "passive"))
      (node (ref "SV168") (pin "2") (pinfunction "2_2") (pintype "passive"))
      (node (ref "SV168") (pin "4") (pinfunction "4_4") (pintype "passive"))
      (node (ref "SV168") (pin "6") (pinfunction "6_6") (pintype "passive"))
      (node (ref "SV168") (pin "8") (pinfunction "8_8") (pintype "passive"))
    )
    (net (code "814") (name "Net-(SV169-Pad1)") (class "Default")
      (node (ref "SV169") (pin "1") (pinfunction "1_1") (pintype "passive"))
      (node (ref "SV169") (pin "3") (pinfunction "3_3") (pintype "passive"))
      (node (ref "SV169") (pin "5") (pinfunction "5_5") (pintype "passive"))
      (node (ref "SV169") (pin "7") (pinfunction "7_7") (pintype "passive"))
      (node (ref "SV169") (pin "9") (pinfunction "9_9") (pintype "passive"))
    )
    (net (code "815") (name "Net-(SV169-Pad10)") (class "Default")
      (node (ref "SV169") (pin "10") (pinfunction "10_10") (pintype "passive"))
      (node (ref "SV169") (pin "2") (pinfunction "2_2") (pintype "passive"))
      (node (ref "SV169") (pin "4") (pinfunction "4_4") (pintype "passive"))
      (node (ref "SV169") (pin "6") (pinfunction "6_6") (pintype "passive"))
      (node (ref "SV169") (pin "8") (pinfunction "8_8") (pintype "passive"))
    )
    (net (code "816") (name "Net-(SV170-Pad1)") (class "Default")
      (node (ref "SV170") (pin "1") (pinfunction "1_1") (pintype "passive"))
      (node (ref "SV170") (pin "3") (pinfunction "3_3") (pintype "passive"))
      (node (ref "SV170") (pin "5") (pinfunction "5_5") (pintype "passive"))
      (node (ref "SV170") (pin "7") (pinfunction "7_7") (pintype "passive"))
      (node (ref "SV170") (pin "9") (pinfunction "9_9") (pintype "passive"))
    )
    (net (code "817") (name "Net-(SV170-Pad10)") (class "Default")
      (node (ref "SV170") (pin "10") (pinfunction "10_10") (pintype "passive"))
      (node (ref "SV170") (pin "2") (pinfunction "2_2") (pintype "passive"))
      (node (ref "SV170") (pin "4") (pinfunction "4_4") (pintype "passive"))
      (node (ref "SV170") (pin "6") (pinfunction "6_6") (pintype "passive"))
      (node (ref "SV170") (pin "8") (pinfunction "8_8") (pintype "passive"))
    )
    (net (code "818") (name "Net-(SV171-Pad1)") (class "Default")
      (node (ref "SV171") (pin "1") (pinfunction "1_1") (pintype "passive"))
      (node (ref "SV171") (pin "3") (pinfunction "3_3") (pintype "passive"))
      (node (ref "SV171") (pin "5") (pinfunction "5_5") (pintype "passive"))
      (node (ref "SV171") (pin "7") (pinfunction "7_7") (pintype "passive"))
      (node (ref "SV171") (pin "9") (pinfunction "9_9") (pintype "passive"))
    )
    (net (code "819") (name "Net-(SV171-Pad10)") (class "Default")
      (node (ref "SV171") (pin "10") (pinfunction "10_10") (pintype "passive"))
      (node (ref "SV171") (pin "2") (pinfunction "2_2") (pintype "passive"))
      (node (ref "SV171") (pin "4") (pinfunction "4_4") (pintype "passive"))
      (node (ref "SV171") (pin "6") (pinfunction "6_6") (pintype "passive"))
      (node (ref "SV171") (pin "8") (pinfunction "8_8") (pintype "passive"))
    )
    (net (code "820") (name "Net-(SV172-Pad1)") (class "Default")
      (node (ref "SV172") (pin "1") (pinfunction "1_1") (pintype "passive"))
      (node (ref "SV172") (pin "3") (pinfunction "3_3") (pintype "passive"))
      (node (ref "SV172") (pin "5") (pinfunction "5_5") (pintype "passive"))
      (node (ref "SV172") (pin "7") (pinfunction "7_7") (pintype "passive"))
      (node (ref "SV172") (pin "9") (pinfunction "9_9") (pintype "passive"))
    )
    (net (code "821") (name "Net-(SV172-Pad10)") (class "Default")
      (node (ref "SV172") (pin "10") (pinfunction "10_10") (pintype "passive"))
      (node (ref "SV172") (pin "2") (pinfunction "2_2") (pintype "passive"))
      (node (ref "SV172") (pin "4") (pinfunction "4_4") (pintype "passive"))
      (node (ref "SV172") (pin "6") (pinfunction "6_6") (pintype "passive"))
      (node (ref "SV172") (pin "8") (pinfunction "8_8") (pintype "passive"))
    )
    (net (code "822") (name "Net-(SV173-Pad1)") (class "Default")
      (node (ref "SV173") (pin "1") (pinfunction "1_1") (pintype "passive"))
      (node (ref "SV173") (pin "3") (pinfunction "3_3") (pintype "passive"))
      (node (ref "SV173") (pin "5") (pinfunction "5_5") (pintype "passive"))
      (node (ref "SV173") (pin "7") (pinfunction "7_7") (pintype "passive"))
      (node (ref "SV173") (pin "9") (pinfunction "9_9") (pintype "passive"))
    )
    (net (code "823") (name "Net-(SV173-Pad10)") (class "Default")
      (node (ref "SV173") (pin "10") (pinfunction "10_10") (pintype "passive"))
      (node (ref "SV173") (pin "2") (pinfunction "2_2") (pintype "passive"))
      (node (ref "SV173") (pin "4") (pinfunction "4_4") (pintype "passive"))
      (node (ref "SV173") (pin "6") (pinfunction "6_6") (pintype "passive"))
      (node (ref "SV173") (pin "8") (pinfunction "8_8") (pintype "passive"))
    )
    (net (code "824") (name "Net-(SV174-Pad1)") (class "Default")
      (node (ref "SV174") (pin "1") (pinfunction "1_1") (pintype "passive"))
      (node (ref "SV174") (pin "3") (pinfunction "3_3") (pintype "passive"))
      (node (ref "SV174") (pin "5") (pinfunction "5_5") (pintype "passive"))
      (node (ref "SV174") (pin "7") (pinfunction "7_7") (pintype "passive"))
      (node (ref "SV174") (pin "9") (pinfunction "9_9") (pintype "passive"))
    )
    (net (code "825") (name "Net-(SV174-Pad10)") (class "Default")
      (node (ref "SV174") (pin "10") (pinfunction "10_10") (pintype "passive"))
      (node (ref "SV174") (pin "2") (pinfunction "2_2") (pintype "passive"))
      (node (ref "SV174") (pin "4") (pinfunction "4_4") (pintype "passive"))
      (node (ref "SV174") (pin "6") (pinfunction "6_6") (pintype "passive"))
      (node (ref "SV174") (pin "8") (pinfunction "8_8") (pintype "passive"))
    )
    (net (code "826") (name "Net-(U$2A-1)") (class "Default")
      (node (ref "D9") (pin "1") (pinfunction "1_1") (pintype "passive"))
      (node (ref "U$2") (pin "AA1") (pinfunction "1_AA1") (pintype "passive"))
    )
    (net (code "827") (name "Net-(U$2AK-1)") (class "Default")
      (node (ref "D7") (pin "1") (pinfunction "1_1") (pintype "passive"))
      (node (ref "U$2") (pin "BA1") (pinfunction "1_BA1") (pintype "passive"))
    )
    (net (code "828") (name "Net-(U$2AM-1)") (class "Default")
      (node (ref "D7") (pin "2") (pinfunction "2_2") (pintype "passive"))
      (node (ref "U$2") (pin "BB1") (pinfunction "1_BB1") (pintype "passive"))
    )
    (net (code "829") (name "Net-(U$2BN-1)") (class "Default")
      (node (ref "D8") (pin "15") (pinfunction "15_15") (pintype "passive"))
      (node (ref "U$2") (pin "BS2") (pinfunction "1_BS2") (pintype "passive"))
    )
    (net (code "830") (name "Net-(U$2BU-1)") (class "Default")
      (node (ref "D11") (pin "1") (pinfunction "1_1") (pintype "passive"))
      (node (ref "U$2") (pin "CA1") (pinfunction "1_CA1") (pintype "passive"))
    )
    (net (code "831") (name "Net-(U$2BW-1)") (class "Default")
      (node (ref "D11") (pin "2") (pinfunction "2_2") (pintype "passive"))
      (node (ref "U$2") (pin "CB1") (pinfunction "1_CB1") (pintype "passive"))
    )
    (net (code "832") (name "Net-(U$2C-1)") (class "Default")
      (node (ref "D9") (pin "2") (pinfunction "2_2") (pintype "passive"))
      (node (ref "U$2") (pin "AB1") (pinfunction "1_AB1") (pintype "passive"))
    )
    (net (code "833") (name "Net-(U$2DE-1)") (class "Default")
      (node (ref "D13") (pin "1") (pinfunction "1_1") (pintype "passive"))
      (node (ref "U$2") (pin "DA1") (pinfunction "1_DA1") (pintype "passive"))
    )
    (net (code "834") (name "Net-(U$2DG-1)") (class "Default")
      (node (ref "D13") (pin "2") (pinfunction "2_2") (pintype "passive"))
      (node (ref "U$2") (pin "DB1") (pinfunction "1_DB1") (pintype "passive"))
    )
    (net (code "835") (name "POWER_OK") (class "Default")
      (node (ref "D8") (pin "18") (pinfunction "18_18") (pintype "passive"))
      (node (ref "R6") (pin "1") (pinfunction "1_1") (pintype "passive"))
      (node (ref "U$2") (pin "BV2") (pinfunction "1_BV2") (pintype "passive"))
    )
    (net (code "836") (name "PULSE_LA") (class "Default")
      (node (ref "D14") (pin "14") (pinfunction "14_14") (pintype "passive"))
      (node (ref "U$2") (pin "DR2") (pinfunction "1_DR2") (pintype "passive"))
    )
    (net (code "837") (name "RETURN") (class "Default")
      (node (ref "D10") (pin "14") (pinfunction "14_14") (pintype "passive"))
      (node (ref "U$2") (pin "AR2") (pinfunction "1_AR2") (pintype "passive"))
    )
    (net (code "838") (name "SOURCE") (class "Default")
      (node (ref "D10") (pin "10") (pinfunction "10_10") (pintype "passive"))
      (node (ref "IC8") (pin "6") (pinfunction "A5_6") (pintype "input"))
      (node (ref "U$2") (pin "AL2") (pinfunction "1_AL2") (pintype "passive"))
    )
    (net (code "839") (name "STROBE") (class "Default")
      (node (ref "D10") (pin "11") (pinfunction "11_11") (pintype "passive"))
      (node (ref "U$2") (pin "AM2") (pinfunction "1_AM2") (pintype "passive"))
    )
    (net (code "840") (name "SWITCH") (class "Default")
      (node (ref "D14") (pin "18") (pinfunction "18_18") (pintype "passive"))
      (node (ref "U$2") (pin "DV2") (pinfunction "1_DV2") (pintype "passive"))
    )
    (net (code "841") (name "TP1") (class "Default")
      (node (ref "D12") (pin "4") (pinfunction "4_4") (pintype "passive"))
      (node (ref "U$2") (pin "CD2") (pinfunction "1_CD2") (pintype "passive"))
    )
    (net (code "842") (name "TP2") (class "Default")
      (node (ref "D12") (pin "5") (pinfunction "5_5") (pintype "passive"))
      (node (ref "U$2") (pin "CE2") (pinfunction "1_CE2") (pintype "passive"))
    )
    (net (code "843") (name "TP3") (class "Default")
      (node (ref "D12") (pin "7") (pinfunction "7_7") (pintype "passive"))
      (node (ref "U$2") (pin "CH2") (pinfunction "1_CH2") (pintype "passive"))
    )
    (net (code "844") (name "TP4") (class "Default")
      (node (ref "D12") (pin "8") (pinfunction "8_8") (pintype "passive"))
      (node (ref "U$2") (pin "CJ2") (pinfunction "1_CJ2") (pintype "passive"))
    )
    (net (code "845") (name "V+") (class "Default")
      (node (ref "C1") (pin "1") (pinfunction "1_1") (pintype "passive"))
      (node (ref "C3") (pin "1") (pinfunction "1_1") (pintype "passive"))
      (node (ref "D1") (pin "C") (pinfunction "C_C") (pintype "passive"))
      (node (ref "D2") (pin "C") (pinfunction "C_C") (pintype "passive"))
      (node (ref "IC3") (pin "28") (pinfunction "VCC_28") (pintype "power_in"))
      (node (ref "IC4") (pin "28") (pinfunction "VCC_28") (pintype "power_in"))
      (node (ref "R7") (pin "2") (pinfunction "2_2") (pintype "passive"))
    )
    (net (code "846") (name "VCC") (class "Default")
      (node (ref "C10") (pin "+") (pinfunction "+_+") (pintype "passive"))
      (node (ref "C4") (pin "1") (pinfunction "1_1") (pintype "passive"))
      (node (ref "C5") (pin "1") (pinfunction "1_1") (pintype "passive"))
      (node (ref "C6") (pin "1") (pinfunction "1_1") (pintype "passive"))
      (node (ref "C7") (pin "1") (pinfunction "1_1") (pintype "passive"))
      (node (ref "C8") (pin "1") (pinfunction "1_1") (pintype "passive"))
      (node (ref "C9") (pin "1") (pinfunction "1_1") (pintype "passive"))
      (node (ref "D10") (pin "1") (pinfunction "1_1") (pintype "passive"))
      (node (ref "D12") (pin "1") (pinfunction "1_1") (pintype "passive"))
      (node (ref "D2") (pin "A") (pinfunction "A_A") (pintype "passive"))
      (node (ref "D8") (pin "1") (pinfunction "1_1") (pintype "passive"))
      (node (ref "IC7") (pin "1") (pinfunction "I0_1") (pintype "input"))
      (node (ref "IC7") (pin "12") (pinfunction "I2_12") (pintype "input"))
      (node (ref "IC7") (pin "13") (pinfunction "I3_13") (pintype "input"))
      (node (ref "R5") (pin "10") (pinfunction "2_10") (pintype "passive"))
      (node (ref "R5") (pin "11") (pinfunction "2_11") (pintype "passive"))
      (node (ref "R5") (pin "12") (pinfunction "2_12") (pintype "passive"))
      (node (ref "R5") (pin "13") (pinfunction "2_13") (pintype "passive"))
      (node (ref "R5") (pin "14") (pinfunction "2_14") (pintype "passive"))
      (node (ref "R5") (pin "15") (pinfunction "2_15") (pintype "passive"))
      (node (ref "R5") (pin "16") (pinfunction "2_16") (pintype "passive"))
      (node (ref "R5") (pin "9") (pinfunction "2_9") (pintype "passive"))
      (node (ref "SV11") (pin "1") (pinfunction "1_1") (pintype "passive"))
      (node (ref "SV11") (pin "10") (pinfunction "10_10") (pintype "passive"))
      (node (ref "SV11") (pin "2") (pinfunction "2_2") (pintype "passive"))
      (node (ref "SV11") (pin "3") (pinfunction "3_3") (pintype "passive"))
      (node (ref "SV11") (pin "4") (pinfunction "4_4") (pintype "passive"))
      (node (ref "SV11") (pin "5") (pinfunction "5_5") (pintype "passive"))
      (node (ref "SV11") (pin "6") (pinfunction "6_6") (pintype "passive"))
      (node (ref "SV11") (pin "7") (pinfunction "7_7") (pintype "passive"))
      (node (ref "SV11") (pin "8") (pinfunction "8_8") (pintype "passive"))
      (node (ref "SV11") (pin "9") (pinfunction "9_9") (pintype "passive"))
      (node (ref "SV125") (pin "1") (pinfunction "1_1") (pintype "passive"))
      (node (ref "SV125") (pin "10") (pinfunction "10_10") (pintype "passive"))
      (node (ref "SV125") (pin "11") (pinfunction "11_11") (pintype "passive"))
      (node (ref "SV125") (pin "12") (pinfunction "12_12") (pintype "passive"))
      (node (ref "SV125") (pin "13") (pinfunction "13_13") (pintype "passive"))
      (node (ref "SV125") (pin "14") (pinfunction "14_14") (pintype "passive"))
      (node (ref "SV125") (pin "15") (pinfunction "15_15") (pintype "passive"))
      (node (ref "SV125") (pin "16") (pinfunction "16_16") (pintype "passive"))
      (node (ref "SV125") (pin "17") (pinfunction "17_17") (pintype "passive"))
      (node (ref "SV125") (pin "18") (pinfunction "18_18") (pintype "passive"))
      (node (ref "SV125") (pin "19") (pinfunction "19_19") (pintype "passive"))
      (node (ref "SV125") (pin "2") (pinfunction "2_2") (pintype "passive"))
      (node (ref "SV125") (pin "20") (pinfunction "20_20") (pintype "passive"))
      (node (ref "SV125") (pin "3") (pinfunction "3_3") (pintype "passive"))
      (node (ref "SV125") (pin "4") (pinfunction "4_4") (pintype "passive"))
      (node (ref "SV125") (pin "5") (pinfunction "5_5") (pintype "passive"))
      (node (ref "SV125") (pin "6") (pinfunction "6_6") (pintype "passive"))
      (node (ref "SV125") (pin "7") (pinfunction "7_7") (pintype "passive"))
      (node (ref "SV125") (pin "8") (pinfunction "8_8") (pintype "passive"))
      (node (ref "SV125") (pin "9") (pinfunction "9_9") (pintype "passive"))
      (node (ref "SV127") (pin "1") (pinfunction "1_1") (pintype "passive"))
      (node (ref "SV127") (pin "2") (pinfunction "2_2") (pintype "passive"))
      (node (ref "SV127") (pin "3") (pinfunction "3_3") (pintype "passive"))
      (node (ref "SV127") (pin "4") (pinfunction "4_4") (pintype "passive"))
      (node (ref "SV127") (pin "5") (pinfunction "5_5") (pintype "passive"))
      (node (ref "SV127") (pin "6") (pinfunction "6_6") (pintype "passive"))
      (node (ref "SV127") (pin "7") (pinfunction "7_7") (pintype "passive"))
      (node (ref "SV127") (pin "8") (pinfunction "8_8") (pintype "passive"))
      (node (ref "SV129") (pin "1") (pinfunction "1_1") (pintype "passive"))
      (node (ref "SV129") (pin "10") (pinfunction "10_10") (pintype "passive"))
      (node (ref "SV129") (pin "2") (pinfunction "2_2") (pintype "passive"))
      (node (ref "SV129") (pin "3") (pinfunction "3_3") (pintype "passive"))
      (node (ref "SV129") (pin "4") (pinfunction "4_4") (pintype "passive"))
      (node (ref "SV129") (pin "5") (pinfunction "5_5") (pintype "passive"))
      (node (ref "SV129") (pin "6") (pinfunction "6_6") (pintype "passive"))
      (node (ref "SV129") (pin "7") (pinfunction "7_7") (pintype "passive"))
      (node (ref "SV129") (pin "8") (pinfunction "8_8") (pintype "passive"))
      (node (ref "SV129") (pin "9") (pinfunction "9_9") (pintype "passive"))
      (node (ref "SV131") (pin "1") (pinfunction "1_1") (pintype "passive"))
      (node (ref "SV131") (pin "10") (pinfunction "10_10") (pintype "passive"))
      (node (ref "SV131") (pin "11") (pinfunction "11_11") (pintype "passive"))
      (node (ref "SV131") (pin "12") (pinfunction "12_12") (pintype "passive"))
      (node (ref "SV131") (pin "13") (pinfunction "13_13") (pintype "passive"))
      (node (ref "SV131") (pin "14") (pinfunction "14_14") (pintype "passive"))
      (node (ref "SV131") (pin "15") (pinfunction "15_15") (pintype "passive"))
      (node (ref "SV131") (pin "16") (pinfunction "16_16") (pintype "passive"))
      (node (ref "SV131") (pin "17") (pinfunction "17_17") (pintype "passive"))
      (node (ref "SV131") (pin "18") (pinfunction "18_18") (pintype "passive"))
      (node (ref "SV131") (pin "19") (pinfunction "19_19") (pintype "passive"))
      (node (ref "SV131") (pin "2") (pinfunction "2_2") (pintype "passive"))
      (node (ref "SV131") (pin "20") (pinfunction "20_20") (pintype "passive"))
      (node (ref "SV131") (pin "3") (pinfunction "3_3") (pintype "passive"))
      (node (ref "SV131") (pin "4") (pinfunction "4_4") (pintype "passive"))
      (node (ref "SV131") (pin "5") (pinfunction "5_5") (pintype "passive"))
      (node (ref "SV131") (pin "6") (pinfunction "6_6") (pintype "passive"))
      (node (ref "SV131") (pin "7") (pinfunction "7_7") (pintype "passive"))
      (node (ref "SV131") (pin "8") (pinfunction "8_8") (pintype "passive"))
      (node (ref "SV131") (pin "9") (pinfunction "9_9") (pintype "passive"))
      (node (ref "SV175") (pin "1") (pinfunction "1_1") (pintype "passive"))
      (node (ref "SV175") (pin "10") (pinfunction "10_10") (pintype "passive"))
      (node (ref "SV175") (pin "11") (pinfunction "11_11") (pintype "passive"))
      (node (ref "SV175") (pin "12") (pinfunction "12_12") (pintype "passive"))
      (node (ref "SV175") (pin "13") (pinfunction "13_13") (pintype "passive"))
      (node (ref "SV175") (pin "14") (pinfunction "14_14") (pintype "passive"))
      (node (ref "SV175") (pin "15") (pinfunction "15_15") (pintype "passive"))
      (node (ref "SV175") (pin "16") (pinfunction "16_16") (pintype "passive"))
      (node (ref "SV175") (pin "17") (pinfunction "17_17") (pintype "passive"))
      (node (ref "SV175") (pin "18") (pinfunction "18_18") (pintype "passive"))
      (node (ref "SV175") (pin "19") (pinfunction "19_19") (pintype "passive"))
      (node (ref "SV175") (pin "2") (pinfunction "2_2") (pintype "passive"))
      (node (ref "SV175") (pin "20") (pinfunction "20_20") (pintype "passive"))
      (node (ref "SV175") (pin "3") (pinfunction "3_3") (pintype "passive"))
      (node (ref "SV175") (pin "4") (pinfunction "4_4") (pintype "passive"))
      (node (ref "SV175") (pin "5") (pinfunction "5_5") (pintype "passive"))
      (node (ref "SV175") (pin "6") (pinfunction "6_6") (pintype "passive"))
      (node (ref "SV175") (pin "7") (pinfunction "7_7") (pintype "passive"))
      (node (ref "SV175") (pin "8") (pinfunction "8_8") (pintype "passive"))
      (node (ref "SV175") (pin "9") (pinfunction "9_9") (pintype "passive"))
      (node (ref "SV177") (pin "1") (pinfunction "1_1") (pintype "passive"))
      (node (ref "SV177") (pin "2") (pinfunction "2_2") (pintype "passive"))
      (node (ref "SV177") (pin "3") (pinfunction "3_3") (pintype "passive"))
      (node (ref "SV177") (pin "4") (pinfunction "4_4") (pintype "passive"))
      (node (ref "SV177") (pin "5") (pinfunction "5_5") (pintype "passive"))
      (node (ref "SV177") (pin "6") (pinfunction "6_6") (pintype "passive"))
      (node (ref "SV177") (pin "7") (pinfunction "7_7") (pintype "passive"))
      (node (ref "SV177") (pin "8") (pinfunction "8_8") (pintype "passive"))
      (node (ref "SV178") (pin "1") (pinfunction "1_1") (pintype "passive"))
      (node (ref "SV178") (pin "2") (pinfunction "2_2") (pintype "passive"))
      (node (ref "SV178") (pin "3") (pinfunction "3_3") (pintype "passive"))
      (node (ref "SV178") (pin "4") (pinfunction "4_4") (pintype "passive"))
      (node (ref "SV178") (pin "5") (pinfunction "5_5") (pintype "passive"))
      (node (ref "SV178") (pin "6") (pinfunction "6_6") (pintype "passive"))
      (node (ref "SV178") (pin "7") (pinfunction "7_7") (pintype "passive"))
      (node (ref "SV178") (pin "8") (pinfunction "8_8") (pintype "passive"))
      (node (ref "SV179") (pin "1") (pinfunction "1_1") (pintype "passive"))
      (node (ref "SV179") (pin "10") (pinfunction "10_10") (pintype "passive"))
      (node (ref "SV179") (pin "2") (pinfunction "2_2") (pintype "passive"))
      (node (ref "SV179") (pin "3") (pinfunction "3_3") (pintype "passive"))
      (node (ref "SV179") (pin "4") (pinfunction "4_4") (pintype "passive"))
      (node (ref "SV179") (pin "5") (pinfunction "5_5") (pintype "passive"))
      (node (ref "SV179") (pin "6") (pinfunction "6_6") (pintype "passive"))
      (node (ref "SV179") (pin "7") (pinfunction "7_7") (pintype "passive"))
      (node (ref "SV179") (pin "8") (pinfunction "8_8") (pintype "passive"))
      (node (ref "SV179") (pin "9") (pinfunction "9_9") (pintype "passive"))
      (node (ref "SV3") (pin "1") (pinfunction "1_1") (pintype "passive"))
      (node (ref "SV3") (pin "10") (pinfunction "10_10") (pintype "passive"))
      (node (ref "SV3") (pin "11") (pinfunction "11_11") (pintype "passive"))
      (node (ref "SV3") (pin "12") (pinfunction "12_12") (pintype "passive"))
      (node (ref "SV3") (pin "13") (pinfunction "13_13") (pintype "passive"))
      (node (ref "SV3") (pin "14") (pinfunction "14_14") (pintype "passive"))
      (node (ref "SV3") (pin "15") (pinfunction "15_15") (pintype "passive"))
      (node (ref "SV3") (pin "16") (pinfunction "16_16") (pintype "passive"))
      (node (ref "SV3") (pin "17") (pinfunction "17_17") (pintype "passive"))
      (node (ref "SV3") (pin "18") (pinfunction "18_18") (pintype "passive"))
      (node (ref "SV3") (pin "19") (pinfunction "19_19") (pintype "passive"))
      (node (ref "SV3") (pin "2") (pinfunction "2_2") (pintype "passive"))
      (node (ref "SV3") (pin "20") (pinfunction "20_20") (pintype "passive"))
      (node (ref "SV3") (pin "3") (pinfunction "3_3") (pintype "passive"))
      (node (ref "SV3") (pin "4") (pinfunction "4_4") (pintype "passive"))
      (node (ref "SV3") (pin "5") (pinfunction "5_5") (pintype "passive"))
      (node (ref "SV3") (pin "6") (pinfunction "6_6") (pintype "passive"))
      (node (ref "SV3") (pin "7") (pinfunction "7_7") (pintype "passive"))
      (node (ref "SV3") (pin "8") (pinfunction "8_8") (pintype "passive"))
      (node (ref "SV3") (pin "9") (pinfunction "9_9") (pintype "passive"))
      (node (ref "SV5") (pin "1") (pinfunction "1_1") (pintype "passive"))
      (node (ref "SV5") (pin "10") (pinfunction "10_10") (pintype "passive"))
      (node (ref "SV5") (pin "11") (pinfunction "11_11") (pintype "passive"))
      (node (ref "SV5") (pin "12") (pinfunction "12_12") (pintype "passive"))
      (node (ref "SV5") (pin "13") (pinfunction "13_13") (pintype "passive"))
      (node (ref "SV5") (pin "14") (pinfunction "14_14") (pintype "passive"))
      (node (ref "SV5") (pin "15") (pinfunction "15_15") (pintype "passive"))
      (node (ref "SV5") (pin "16") (pinfunction "16_16") (pintype "passive"))
      (node (ref "SV5") (pin "17") (pinfunction "17_17") (pintype "passive"))
      (node (ref "SV5") (pin "18") (pinfunction "18_18") (pintype "passive"))
      (node (ref "SV5") (pin "19") (pinfunction "19_19") (pintype "passive"))
      (node (ref "SV5") (pin "2") (pinfunction "2_2") (pintype "passive"))
      (node (ref "SV5") (pin "20") (pinfunction "20_20") (pintype "passive"))
      (node (ref "SV5") (pin "3") (pinfunction "3_3") (pintype "passive"))
      (node (ref "SV5") (pin "4") (pinfunction "4_4") (pintype "passive"))
      (node (ref "SV5") (pin "5") (pinfunction "5_5") (pintype "passive"))
      (node (ref "SV5") (pin "6") (pinfunction "6_6") (pintype "passive"))
      (node (ref "SV5") (pin "7") (pinfunction "7_7") (pintype "passive"))
      (node (ref "SV5") (pin "8") (pinfunction "8_8") (pintype "passive"))
      (node (ref "SV5") (pin "9") (pinfunction "9_9") (pintype "passive"))
      (node (ref "SV9") (pin "1") (pinfunction "1_1") (pintype "passive"))
      (node (ref "SV9") (pin "2") (pinfunction "2_2") (pintype "passive"))
      (node (ref "SV9") (pin "3") (pinfunction "3_3") (pintype "passive"))
      (node (ref "SV9") (pin "4") (pinfunction "4_4") (pintype "passive"))
      (node (ref "SV9") (pin "5") (pinfunction "5_5") (pintype "passive"))
      (node (ref "SV9") (pin "6") (pinfunction "6_6") (pintype "passive"))
      (node (ref "SV9") (pin "7") (pinfunction "7_7") (pintype "passive"))
      (node (ref "SV9") (pin "8") (pinfunction "8_8") (pintype "passive"))
      (node (ref "U$2") (pin "AA2") (pinfunction "1_AA2") (pintype "passive"))
      (node (ref "U$2") (pin "BA2") (pinfunction "1_BA2") (pintype "passive"))
      (node (ref "U$2") (pin "CA2") (pinfunction "1_CA2") (pintype "passive"))
      (node (ref "VCC1") (pin "1") (pinfunction "1_1") (pintype "passive"))
      (node (ref "VCC1") (pin "2") (pinfunction "2_2") (pintype "passive"))
      (node (ref "VCC10") (pin "1") (pinfunction "1_1") (pintype "passive"))
      (node (ref "VCC10") (pin "2") (pinfunction "2_2") (pintype "passive"))
      (node (ref "VCC11") (pin "1") (pinfunction "1_1") (pintype "passive"))
      (node (ref "VCC11") (pin "2") (pinfunction "2_2") (pintype "passive"))
      (node (ref "VCC12") (pin "1") (pinfunction "1_1") (pintype "passive"))
      (node (ref "VCC12") (pin "2") (pinfunction "2_2") (pintype "passive"))
      (node (ref "VCC13") (pin "1") (pinfunction "1_1") (pintype "passive"))
      (node (ref "VCC13") (pin "2") (pinfunction "2_2") (pintype "passive"))
      (node (ref "VCC14") (pin "1") (pinfunction "1_1") (pintype "passive"))
      (node (ref "VCC14") (pin "2") (pinfunction "2_2") (pintype "passive"))
      (node (ref "VCC15") (pin "1") (pinfunction "1_1") (pintype "passive"))
      (node (ref "VCC15") (pin "2") (pinfunction "2_2") (pintype "passive"))
      (node (ref "VCC16") (pin "1") (pinfunction "1_1") (pintype "passive"))
      (node (ref "VCC16") (pin "2") (pinfunction "2_2") (pintype "passive"))
      (node (ref "VCC17") (pin "1") (pinfunction "1_1") (pintype "passive"))
      (node (ref "VCC17") (pin "2") (pinfunction "2_2") (pintype "passive"))
      (node (ref "VCC18") (pin "1") (pinfunction "1_1") (pintype "passive"))
      (node (ref "VCC18") (pin "2") (pinfunction "2_2") (pintype "passive"))
      (node (ref "VCC19") (pin "1") (pinfunction "1_1") (pintype "passive"))
      (node (ref "VCC19") (pin "2") (pinfunction "2_2") (pintype "passive"))
      (node (ref "VCC2") (pin "1") (pinfunction "1_1") (pintype "passive"))
      (node (ref "VCC2") (pin "2") (pinfunction "2_2") (pintype "passive"))
      (node (ref "VCC20") (pin "1") (pinfunction "1_1") (pintype "passive"))
      (node (ref "VCC20") (pin "2") (pinfunction "2_2") (pintype "passive"))
      (node (ref "VCC21") (pin "1") (pinfunction "1_1") (pintype "passive"))
      (node (ref "VCC21") (pin "2") (pinfunction "2_2") (pintype "passive"))
      (node (ref "VCC22") (pin "1") (pinfunction "1_1") (pintype "passive"))
      (node (ref "VCC22") (pin "2") (pinfunction "2_2") (pintype "passive"))
      (node (ref "VCC23") (pin "1") (pinfunction "1_1") (pintype "passive"))
      (node (ref "VCC23") (pin "2") (pinfunction "2_2") (pintype "passive"))
      (node (ref "VCC24") (pin "1") (pinfunction "1_1") (pintype "passive"))
      (node (ref "VCC24") (pin "2") (pinfunction "2_2") (pintype "passive"))
      (node (ref "VCC25") (pin "1") (pinfunction "1_1") (pintype "passive"))
      (node (ref "VCC25") (pin "2") (pinfunction "2_2") (pintype "passive"))
      (node (ref "VCC26") (pin "1") (pinfunction "1_1") (pintype "passive"))
      (node (ref "VCC26") (pin "2") (pinfunction "2_2") (pintype "passive"))
      (node (ref "VCC27") (pin "1") (pinfunction "1_1") (pintype "passive"))
      (node (ref "VCC27") (pin "2") (pinfunction "2_2") (pintype "passive"))
      (node (ref "VCC28") (pin "1") (pinfunction "1_1") (pintype "passive"))
      (node (ref "VCC28") (pin "2") (pinfunction "2_2") (pintype "passive"))
      (node (ref "VCC29") (pin "1") (pinfunction "1_1") (pintype "passive"))
      (node (ref "VCC29") (pin "2") (pinfunction "2_2") (pintype "passive"))
      (node (ref "VCC3") (pin "1") (pinfunction "1_1") (pintype "passive"))
      (node (ref "VCC3") (pin "2") (pinfunction "2_2") (pintype "passive"))
      (node (ref "VCC30") (pin "1") (pinfunction "1_1") (pintype "passive"))
      (node (ref "VCC30") (pin "2") (pinfunction "2_2") (pintype "passive"))
      (node (ref "VCC31") (pin "1") (pinfunction "1_1") (pintype "passive"))
      (node (ref "VCC31") (pin "2") (pinfunction "2_2") (pintype "passive"))
      (node (ref "VCC32") (pin "1") (pinfunction "1_1") (pintype "passive"))
      (node (ref "VCC32") (pin "2") (pinfunction "2_2") (pintype "passive"))
      (node (ref "VCC33") (pin "1") (pinfunction "1_1") (pintype "passive"))
      (node (ref "VCC33") (pin "2") (pinfunction "2_2") (pintype "passive"))
      (node (ref "VCC34") (pin "1") (pinfunction "1_1") (pintype "passive"))
      (node (ref "VCC34") (pin "2") (pinfunction "2_2") (pintype "passive"))
      (node (ref "VCC35") (pin "1") (pinfunction "1_1") (pintype "passive"))
      (node (ref "VCC35") (pin "2") (pinfunction "2_2") (pintype "passive"))
      (node (ref "VCC36") (pin "1") (pinfunction "1_1") (pintype "passive"))
      (node (ref "VCC36") (pin "2") (pinfunction "2_2") (pintype "passive"))
      (node (ref "VCC37") (pin "1") (pinfunction "1_1") (pintype "passive"))
      (node (ref "VCC37") (pin "2") (pinfunction "2_2") (pintype "passive"))
      (node (ref "VCC38") (pin "1") (pinfunction "1_1") (pintype "passive"))
      (node (ref "VCC38") (pin "2") (pinfunction "2_2") (pintype "passive"))
      (node (ref "VCC39") (pin "1") (pinfunction "1_1") (pintype "passive"))
      (node (ref "VCC39") (pin "2") (pinfunction "2_2") (pintype "passive"))
      (node (ref "VCC4") (pin "1") (pinfunction "1_1") (pintype "passive"))
      (node (ref "VCC4") (pin "2") (pinfunction "2_2") (pintype "passive"))
      (node (ref "VCC40") (pin "1") (pinfunction "1_1") (pintype "passive"))
      (node (ref "VCC40") (pin "2") (pinfunction "2_2") (pintype "passive"))
      (node (ref "VCC41") (pin "1") (pinfunction "1_1") (pintype "passive"))
      (node (ref "VCC41") (pin "2") (pinfunction "2_2") (pintype "passive"))
      (node (ref "VCC42") (pin "1") (pinfunction "1_1") (pintype "passive"))
      (node (ref "VCC42") (pin "2") (pinfunction "2_2") (pintype "passive"))
      (node (ref "VCC43") (pin "1") (pinfunction "1_1") (pintype "passive"))
      (node (ref "VCC43") (pin "2") (pinfunction "2_2") (pintype "passive"))
      (node (ref "VCC44") (pin "1") (pinfunction "1_1") (pintype "passive"))
      (node (ref "VCC44") (pin "2") (pinfunction "2_2") (pintype "passive"))
      (node (ref "VCC5") (pin "1") (pinfunction "1_1") (pintype "passive"))
      (node (ref "VCC5") (pin "2") (pinfunction "2_2") (pintype "passive"))
      (node (ref "VCC6") (pin "1") (pinfunction "1_1") (pintype "passive"))
      (node (ref "VCC6") (pin "2") (pinfunction "2_2") (pintype "passive"))
      (node (ref "VCC7") (pin "1") (pinfunction "1_1") (pintype "passive"))
      (node (ref "VCC7") (pin "2") (pinfunction "2_2") (pintype "passive"))
      (node (ref "VCC8") (pin "1") (pinfunction "1_1") (pintype "passive"))
      (node (ref "VCC8") (pin "2") (pinfunction "2_2") (pintype "passive"))
      (node (ref "VCC9") (pin "1") (pinfunction "1_1") (pintype "passive"))
      (node (ref "VCC9") (pin "2") (pinfunction "2_2") (pintype "passive"))
    )
    (net (code "847") (name "WRITE") (class "Default")
      (node (ref "D10") (pin "15") (pinfunction "15_15") (pintype "passive"))
      (node (ref "IC8") (pin "4") (pinfunction "A3_4") (pintype "input"))
      (node (ref "U$2") (pin "AS2") (pinfunction "1_AS2") (pintype "passive"))
    )
    (net (code "848") (name "unconnected-(IC8A-Y8-Pad11)") (class "Default")
      (node (ref "IC8") (pin "11") (pinfunction "Y8_11") (pintype "tri_state"))
    )
    (net (code "849") (name "~{BREAK_CYCLE}") (class "Default")
      (node (ref "D8") (pin "10") (pinfunction "10_10") (pintype "passive"))
      (node (ref "U$2") (pin "BL2") (pinfunction "1_BL2") (pintype "passive"))
    )
    (net (code "850") (name "~{BRK_DATA_CONT}") (class "Default")
      (node (ref "D8") (pin "9") (pinfunction "9_9") (pintype "passive"))
      (node (ref "U$2") (pin "BK2") (pinfunction "1_BK2") (pintype "passive"))
    )
    (net (code "851") (name "~{BRK_IN_PROG}") (class "Default")
      (node (ref "D8") (pin "5") (pinfunction "5_5") (pintype "passive"))
      (node (ref "U$2") (pin "BE2") (pinfunction "1_BE2") (pintype "passive"))
    )
    (net (code "852") (name "~{BUS_STROBE}") (class "Default")
      (node (ref "D11") (pin "9") (pinfunction "9_9") (pintype "passive"))
      (node (ref "U$2") (pin "CK1") (pinfunction "1_CK1") (pintype "passive"))
    )
    (net (code "853") (name "~{C0}") (class "Default")
      (node (ref "D11") (pin "5") (pinfunction "5_5") (pintype "passive"))
      (node (ref "U$2") (pin "CE1") (pinfunction "1_CE1") (pintype "passive"))
    )
    (net (code "854") (name "~{C1}") (class "Default")
      (node (ref "D11") (pin "7") (pinfunction "7_7") (pintype "passive"))
      (node (ref "U$2") (pin "CH1") (pinfunction "1_CH1") (pintype "passive"))
    )
    (net (code "855") (name "~{C2}") (class "Default")
      (node (ref "D11") (pin "8") (pinfunction "8_8") (pintype "passive"))
      (node (ref "U$2") (pin "CJ1") (pinfunction "1_CJ1") (pintype "passive"))
    )
    (net (code "856") (name "~{CE}") (class "Default")
      (node (ref "C2") (pin "1") (pinfunction "1_1") (pintype "passive"))
      (node (ref "IC3") (pin "20") (pinfunction "~{CE}_20") (pintype "input"))
      (node (ref "IC4") (pin "20") (pinfunction "~{CE}_20") (pintype "input"))
      (node (ref "Q1") (pin "1") (pinfunction "C_1") (pintype "passive"))
      (node (ref "R7") (pin "1") (pinfunction "1_1") (pintype "passive"))
    )
    (net (code "857") (name "~{CPMA_DISABLE}") (class "Default")
      (node (ref "D11") (pin "17") (pinfunction "17_17") (pintype "passive"))
      (node (ref "U$2") (pin "CU1") (pinfunction "1_CU1") (pintype "passive"))
    )
    (net (code "858") (name "~{DATA0}") (class "Default")
      (node (ref "D9") (pin "14") (pinfunction "14_14") (pintype "passive"))
      (node (ref "U$2") (pin "AR1") (pinfunction "1_AR1") (pintype "passive"))
    )
    (net (code "859") (name "~{DATA1}") (class "Default")
      (node (ref "D9") (pin "15") (pinfunction "15_15") (pintype "passive"))
      (node (ref "U$2") (pin "AS1") (pinfunction "1_AS1") (pintype "passive"))
    )
    (net (code "860") (name "~{DATA2}") (class "Default")
      (node (ref "D9") (pin "17") (pinfunction "17_17") (pintype "passive"))
      (node (ref "U$2") (pin "AU1") (pinfunction "1_AU1") (pintype "passive"))
    )
    (net (code "861") (name "~{DATA3}") (class "Default")
      (node (ref "D9") (pin "18") (pinfunction "18_18") (pintype "passive"))
      (node (ref "U$2") (pin "AV1") (pinfunction "1_AV1") (pintype "passive"))
    )
    (net (code "862") (name "~{DATA4}") (class "Default")
      (node (ref "D7") (pin "14") (pinfunction "14_14") (pintype "passive"))
      (node (ref "U$2") (pin "BR1") (pinfunction "1_BR1") (pintype "passive"))
    )
    (net (code "863") (name "~{DATA5}") (class "Default")
      (node (ref "D7") (pin "15") (pinfunction "15_15") (pintype "passive"))
      (node (ref "U$2") (pin "BS1") (pinfunction "1_BS1") (pintype "passive"))
    )
    (net (code "864") (name "~{DATA6}") (class "Default")
      (node (ref "D7") (pin "17") (pinfunction "17_17") (pintype "passive"))
      (node (ref "U$2") (pin "BU1") (pinfunction "1_BU1") (pintype "passive"))
    )
    (net (code "865") (name "~{DATA7}") (class "Default")
      (node (ref "D7") (pin "18") (pinfunction "18_18") (pintype "passive"))
      (node (ref "U$2") (pin "BV1") (pinfunction "1_BV1") (pintype "passive"))
    )
    (net (code "866") (name "~{DATA8}") (class "Default")
      (node (ref "D13") (pin "14") (pinfunction "14_14") (pintype "passive"))
      (node (ref "U$2") (pin "DR1") (pinfunction "1_DR1") (pintype "passive"))
    )
    (net (code "867") (name "~{DATA9}") (class "Default")
      (node (ref "D13") (pin "15") (pinfunction "15_15") (pintype "passive"))
      (node (ref "U$2") (pin "DS1") (pinfunction "1_DS1") (pintype "passive"))
    )
    (net (code "868") (name "~{DATA10}") (class "Default")
      (node (ref "D13") (pin "17") (pinfunction "17_17") (pintype "passive"))
      (node (ref "U$2") (pin "DU1") (pinfunction "1_DU1") (pintype "passive"))
    )
    (net (code "869") (name "~{DATA11}") (class "Default")
      (node (ref "D13") (pin "18") (pinfunction "18_18") (pintype "passive"))
      (node (ref "U$2") (pin "DV1") (pinfunction "1_DV1") (pintype "passive"))
    )
    (net (code "870") (name "~{D}") (class "Default")
      (node (ref "D14") (pin "9") (pinfunction "9_9") (pintype "passive"))
      (node (ref "U$2") (pin "DK2") (pinfunction "1_DK2") (pintype "passive"))
    )
    (net (code "871") (name "~{EMA0}") (class "Default")
      (node (ref "D10") (pin "4") (pinfunction "4_4") (pintype "passive"))
      (node (ref "IC3") (pin "8") (pinfunction "A2_8") (pintype "input"))
      (node (ref "IC4") (pin "8") (pinfunction "A2_8") (pintype "input"))
      (node (ref "IC5") (pin "1") (pinfunction "A_1") (pintype "input"))
      (node (ref "U$2") (pin "AD2") (pinfunction "1_AD2") (pintype "passive"))
    )
    (net (code "872") (name "~{EMA1}") (class "Default")
      (node (ref "D10") (pin "5") (pinfunction "5_5") (pintype "passive"))
      (node (ref "IC3") (pin "9") (pinfunction "A1_9") (pintype "input"))
      (node (ref "IC4") (pin "9") (pinfunction "A1_9") (pintype "input"))
      (node (ref "IC5") (pin "2") (pinfunction "B_2") (pintype "input"))
      (node (ref "U$2") (pin "AE2") (pinfunction "1_AE2") (pintype "passive"))
    )
    (net (code "873") (name "~{EMA2}") (class "Default")
      (node (ref "D10") (pin "7") (pinfunction "7_7") (pintype "passive"))
      (node (ref "IC3") (pin "10") (pinfunction "A0_10") (pintype "input"))
      (node (ref "IC4") (pin "10") (pinfunction "A0_10") (pintype "input"))
      (node (ref "IC5") (pin "3") (pinfunction "C_3") (pintype "input"))
      (node (ref "U$2") (pin "AH2") (pinfunction "1_AH2") (pintype "passive"))
    )
    (net (code "874") (name "~{E}") (class "Default")
      (node (ref "D14") (pin "10") (pinfunction "10_10") (pintype "passive"))
      (node (ref "U$2") (pin "DL2") (pinfunction "1_DL2") (pintype "passive"))
    )
    (net (code "875") (name "~{FSET}") (class "Default")
      (node (ref "D14") (pin "13") (pinfunction "13_13") (pintype "passive"))
      (node (ref "U$2") (pin "DP2") (pinfunction "1_DP2") (pintype "passive"))
    )
    (net (code "876") (name "~{F}") (class "Default")
      (node (ref "D14") (pin "8") (pinfunction "8_8") (pintype "passive"))
      (node (ref "U$2") (pin "DJ2") (pinfunction "1_DJ2") (pintype "passive"))
    )
    (net (code "877") (name "~{IND1}") (class "Default")
      (node (ref "D12") (pin "17") (pinfunction "17_17") (pintype "passive"))
      (node (ref "U$2") (pin "CU2") (pinfunction "1_CU2") (pintype "passive"))
    )
    (net (code "878") (name "~{IND2}") (class "Default")
      (node (ref "D12") (pin "18") (pinfunction "18_18") (pintype "passive"))
      (node (ref "U$2") (pin "CV2") (pinfunction "1_CV2") (pintype "passive"))
    )
    (net (code "879") (name "~{INTERNAL_IO}") (class "Default")
      (node (ref "D11") (pin "10") (pinfunction "10_10") (pintype "passive"))
      (node (ref "U$2") (pin "CL1") (pinfunction "1_CL1") (pintype "passive"))
    )
    (net (code "880") (name "~{INT_RQST}") (class "Default")
      (node (ref "D11") (pin "13") (pinfunction "13_13") (pintype "passive"))
      (node (ref "U$2") (pin "CP1") (pinfunction "1_CP1") (pintype "passive"))
    )
    (net (code "881") (name "~{IO_PAUSE}") (class "Default")
      (node (ref "D11") (pin "4") (pinfunction "4_4") (pintype "passive"))
      (node (ref "U$2") (pin "CD1") (pinfunction "1_CD1") (pintype "passive"))
    )
    (net (code "882") (name "~{IR0}") (class "Default")
      (node (ref "D14") (pin "4") (pinfunction "4_4") (pintype "passive"))
      (node (ref "U$2") (pin "DD2") (pinfunction "1_DD2") (pintype "passive"))
    )
    (net (code "883") (name "~{IR1}") (class "Default")
      (node (ref "D14") (pin "5") (pinfunction "5_5") (pintype "passive"))
      (node (ref "U$2") (pin "DE2") (pinfunction "1_DE2") (pintype "passive"))
    )
    (net (code "884") (name "~{IR2}") (class "Default")
      (node (ref "D14") (pin "7") (pinfunction "7_7") (pintype "passive"))
      (node (ref "U$2") (pin "DH2") (pinfunction "1_DH2") (pintype "passive"))
    )
    (net (code "885") (name "~{KEY_CONT}") (class "Default")
      (node (ref "D14") (pin "17") (pinfunction "17_17") (pintype "passive"))
      (node (ref "U$2") (pin "DU2") (pinfunction "1_DU2") (pintype "passive"))
    )
    (net (code "886") (name "~{LA_ENABLE}") (class "Default")
      (node (ref "D8") (pin "11") (pinfunction "11_11") (pintype "passive"))
      (node (ref "U$2") (pin "BM2") (pinfunction "1_BM2") (pintype "passive"))
    )
    (net (code "887") (name "~{LINK_DATA}") (class "Default")
      (node (ref "D12") (pin "14") (pinfunction "14_14") (pintype "passive"))
      (node (ref "U$2") (pin "CR2") (pinfunction "1_CR2") (pintype "passive"))
    )
    (net (code "888") (name "~{LINK_LOAD}") (class "Default")
      (node (ref "D12") (pin "15") (pinfunction "15_15") (pintype "passive"))
      (node (ref "U$2") (pin "CS2") (pinfunction "1_CS2") (pintype "passive"))
    )
    (net (code "889") (name "~{LINK}") (class "Default")
      (node (ref "D10") (pin "18") (pinfunction "18_18") (pintype "passive"))
      (node (ref "U$2") (pin "AV2") (pinfunction "1_AV2") (pintype "passive"))
    )
    (net (code "890") (name "~{LOAD_CONT}") (class "Default")
      (node (ref "D8") (pin "7") (pinfunction "7_7") (pintype "passive"))
      (node (ref "U$2") (pin "BH2") (pinfunction "1_BH2") (pintype "passive"))
    )
    (net (code "891") (name "~{MA00}") (class "Default")
      (node (ref "D9") (pin "4") (pinfunction "4_4") (pintype "passive"))
      (node (ref "IC3") (pin "21") (pinfunction "A10_21") (pintype "input"))
      (node (ref "IC4") (pin "21") (pinfunction "A10_21") (pintype "input"))
      (node (ref "U$2") (pin "AD1") (pinfunction "1_AD1") (pintype "passive"))
    )
    (net (code "892") (name "~{MA01}") (class "Default")
      (node (ref "D9") (pin "5") (pinfunction "5_5") (pintype "passive"))
      (node (ref "IC3") (pin "23") (pinfunction "A11_23") (pintype "input"))
      (node (ref "IC4") (pin "23") (pinfunction "A11_23") (pintype "input"))
      (node (ref "U$2") (pin "AE1") (pinfunction "1_AE1") (pintype "passive"))
    )
    (net (code "893") (name "~{MA02}") (class "Default")
      (node (ref "D9") (pin "7") (pinfunction "7_7") (pintype "passive"))
      (node (ref "IC3") (pin "24") (pinfunction "A9_24") (pintype "input"))
      (node (ref "IC4") (pin "24") (pinfunction "A9_24") (pintype "input"))
      (node (ref "U$2") (pin "AH1") (pinfunction "1_AH1") (pintype "passive"))
    )
    (net (code "894") (name "~{MA03}") (class "Default")
      (node (ref "D9") (pin "8") (pinfunction "8_8") (pintype "passive"))
      (node (ref "IC3") (pin "25") (pinfunction "A8_25") (pintype "input"))
      (node (ref "IC4") (pin "25") (pinfunction "A8_25") (pintype "input"))
      (node (ref "U$2") (pin "AJ1") (pinfunction "1_AJ1") (pintype "passive"))
    )
    (net (code "895") (name "~{MA04}") (class "Default")
      (node (ref "D7") (pin "4") (pinfunction "4_4") (pintype "passive"))
      (node (ref "IC3") (pin "26") (pinfunction "A13_26") (pintype "input"))
      (node (ref "IC4") (pin "26") (pinfunction "A13_26") (pintype "input"))
      (node (ref "U$2") (pin "BD1") (pinfunction "1_BD1") (pintype "passive"))
    )
    (net (code "896") (name "~{MA05}") (class "Default")
      (node (ref "D7") (pin "5") (pinfunction "5_5") (pintype "passive"))
      (node (ref "IC3") (pin "1") (pinfunction "A14_1") (pintype "input"))
      (node (ref "IC4") (pin "1") (pinfunction "A14_1") (pintype "input"))
      (node (ref "U$2") (pin "BE1") (pinfunction "1_BE1") (pintype "passive"))
    )
    (net (code "897") (name "~{MA06}") (class "Default")
      (node (ref "D7") (pin "7") (pinfunction "7_7") (pintype "passive"))
      (node (ref "IC3") (pin "2") (pinfunction "A12_2") (pintype "input"))
      (node (ref "IC4") (pin "2") (pinfunction "A12_2") (pintype "input"))
      (node (ref "U$2") (pin "BH1") (pinfunction "1_BH1") (pintype "passive"))
    )
    (net (code "898") (name "~{MA07}") (class "Default")
      (node (ref "D7") (pin "8") (pinfunction "8_8") (pintype "passive"))
      (node (ref "IC3") (pin "3") (pinfunction "A7_3") (pintype "input"))
      (node (ref "IC4") (pin "3") (pinfunction "A7_3") (pintype "input"))
      (node (ref "U$2") (pin "BJ1") (pinfunction "1_BJ1") (pintype "passive"))
    )
    (net (code "899") (name "~{MA08}") (class "Default")
      (node (ref "D13") (pin "4") (pinfunction "4_4") (pintype "passive"))
      (node (ref "IC3") (pin "4") (pinfunction "A6_4") (pintype "input"))
      (node (ref "IC4") (pin "4") (pinfunction "A6_4") (pintype "input"))
      (node (ref "U$2") (pin "DD1") (pinfunction "1_DD1") (pintype "passive"))
    )
    (net (code "900") (name "~{MA09}") (class "Default")
      (node (ref "D13") (pin "5") (pinfunction "5_5") (pintype "passive"))
      (node (ref "IC3") (pin "5") (pinfunction "A5_5") (pintype "input"))
      (node (ref "IC4") (pin "5") (pinfunction "A5_5") (pintype "input"))
      (node (ref "U$2") (pin "DE1") (pinfunction "1_DE1") (pintype "passive"))
    )
    (net (code "901") (name "~{MA10}") (class "Default")
      (node (ref "D13") (pin "7") (pinfunction "7_7") (pintype "passive"))
      (node (ref "IC3") (pin "6") (pinfunction "A4_6") (pintype "input"))
      (node (ref "IC4") (pin "6") (pinfunction "A4_6") (pintype "input"))
      (node (ref "U$2") (pin "DH1") (pinfunction "1_DH1") (pintype "passive"))
    )
    (net (code "902") (name "~{MA11}") (class "Default")
      (node (ref "D13") (pin "8") (pinfunction "8_8") (pintype "passive"))
      (node (ref "IC3") (pin "7") (pinfunction "A3_7") (pintype "input"))
      (node (ref "IC4") (pin "7") (pinfunction "A3_7") (pintype "input"))
      (node (ref "U$2") (pin "DJ1") (pinfunction "1_DJ1") (pintype "passive"))
    )
    (net (code "903") (name "~{MD00}") (class "Default")
      (node (ref "D9") (pin "9") (pinfunction "9_9") (pintype "passive"))
      (node (ref "IC1") (pin "2") (pinfunction "A1_2") (pintype "bidirectional"))
      (node (ref "U$2") (pin "AK1") (pinfunction "1_AK1") (pintype "passive"))
    )
    (net (code "904") (name "~{MD01}") (class "Default")
      (node (ref "D9") (pin "10") (pinfunction "10_10") (pintype "passive"))
      (node (ref "IC1") (pin "3") (pinfunction "A2_3") (pintype "bidirectional"))
      (node (ref "U$2") (pin "AL1") (pinfunction "1_AL1") (pintype "passive"))
    )
    (net (code "905") (name "~{MD02}") (class "Default")
      (node (ref "D9") (pin "11") (pinfunction "11_11") (pintype "passive"))
      (node (ref "IC1") (pin "4") (pinfunction "A3_4") (pintype "bidirectional"))
      (node (ref "U$2") (pin "AM1") (pinfunction "1_AM1") (pintype "passive"))
    )
    (net (code "906") (name "~{MD03}") (class "Default")
      (node (ref "D9") (pin "13") (pinfunction "13_13") (pintype "passive"))
      (node (ref "IC1") (pin "5") (pinfunction "A4_5") (pintype "bidirectional"))
      (node (ref "U$2") (pin "AP1") (pinfunction "1_AP1") (pintype "passive"))
    )
    (net (code "907") (name "~{MD04}") (class "Default")
      (node (ref "D7") (pin "9") (pinfunction "9_9") (pintype "passive"))
      (node (ref "IC1") (pin "6") (pinfunction "A5_6") (pintype "bidirectional"))
      (node (ref "U$2") (pin "BK1") (pinfunction "1_BK1") (pintype "passive"))
    )
    (net (code "908") (name "~{MD05}") (class "Default")
      (node (ref "D7") (pin "10") (pinfunction "10_10") (pintype "passive"))
      (node (ref "IC1") (pin "7") (pinfunction "A6_7") (pintype "bidirectional"))
      (node (ref "U$2") (pin "BL1") (pinfunction "1_BL1") (pintype "passive"))
    )
    (net (code "909") (name "~{MD06}") (class "Default")
      (node (ref "D7") (pin "11") (pinfunction "11_11") (pintype "passive"))
      (node (ref "IC1") (pin "8") (pinfunction "A7_8") (pintype "bidirectional"))
      (node (ref "U$2") (pin "BM1") (pinfunction "1_BM1") (pintype "passive"))
    )
    (net (code "910") (name "~{MD07}") (class "Default")
      (node (ref "D7") (pin "13") (pinfunction "13_13") (pintype "passive"))
      (node (ref "IC1") (pin "9") (pinfunction "A8_9") (pintype "bidirectional"))
      (node (ref "U$2") (pin "BP1") (pinfunction "1_BP1") (pintype "passive"))
    )
    (net (code "911") (name "~{MD08}") (class "Default")
      (node (ref "D13") (pin "9") (pinfunction "9_9") (pintype "passive"))
      (node (ref "IC2") (pin "2") (pinfunction "A1_2") (pintype "bidirectional"))
      (node (ref "U$2") (pin "DK1") (pinfunction "1_DK1") (pintype "passive"))
    )
    (net (code "912") (name "~{MD09}") (class "Default")
      (node (ref "D13") (pin "10") (pinfunction "10_10") (pintype "passive"))
      (node (ref "IC2") (pin "3") (pinfunction "A2_3") (pintype "bidirectional"))
      (node (ref "U$2") (pin "DL1") (pinfunction "1_DL1") (pintype "passive"))
    )
    (net (code "913") (name "~{MD10}") (class "Default")
      (node (ref "D13") (pin "11") (pinfunction "11_11") (pintype "passive"))
      (node (ref "IC2") (pin "4") (pinfunction "A3_4") (pintype "bidirectional"))
      (node (ref "U$2") (pin "DM1") (pinfunction "1_DM1") (pintype "passive"))
    )
    (net (code "914") (name "~{MD11}") (class "Default")
      (node (ref "D13") (pin "13") (pinfunction "13_13") (pintype "passive"))
      (node (ref "IC2") (pin "5") (pinfunction "A4_5") (pintype "bidirectional"))
      (node (ref "U$2") (pin "DP1") (pinfunction "1_DP1") (pintype "passive"))
    )
    (net (code "915") (name "~{MD_DIR}") (class "Default")
      (node (ref "D10") (pin "9") (pinfunction "9_9") (pintype "passive"))
      (node (ref "IC8") (pin "2") (pinfunction "A1_2") (pintype "input"))
      (node (ref "U$2") (pin "AK2") (pinfunction "1_AK2") (pintype "passive"))
    )
    (net (code "916") (name "~{MEM_START}") (class "Default")
      (node (ref "D10") (pin "8") (pinfunction "8_8") (pintype "passive"))
      (node (ref "U$2") (pin "AJ2") (pinfunction "1_AJ2") (pintype "passive"))
    )
    (net (code "917") (name "~{MS_DISABLE}") (class "Default")
      (node (ref "D11") (pin "18") (pinfunction "18_18") (pintype "passive"))
      (node (ref "U$2") (pin "CV1") (pinfunction "1_CV1") (pintype "passive"))
    )
    (net (code "918") (name "~{NOT_LAST_TR}") (class "Default")
      (node (ref "D11") (pin "11") (pinfunction "11_11") (pintype "passive"))
      (node (ref "U$2") (pin "CM1") (pinfunction "1_CM1") (pintype "passive"))
    )
    (net (code "919") (name "~{NTS_STALL}") (class "Default")
      (node (ref "D8") (pin "14") (pinfunction "14_14") (pintype "passive"))
      (node (ref "U$2") (pin "BR2") (pinfunction "1_BR2") (pintype "passive"))
    )
    (net (code "920") (name "~{OVERFLOW}") (class "Default")
      (node (ref "D8") (pin "8") (pinfunction "8_8") (pintype "passive"))
      (node (ref "U$2") (pin "BJ2") (pinfunction "1_BJ2") (pintype "passive"))
    )
    (net (code "921") (name "~{READ_EN}") (class "Default")
      (node (ref "IC1") (pin "1") (pinfunction "DIR_1") (pintype "input"))
      (node (ref "IC2") (pin "1") (pinfunction "DIR_1") (pintype "input"))
      (node (ref "IC3") (pin "22") (pinfunction "~{OE}_22") (pintype "input"))
      (node (ref "IC4") (pin "22") (pinfunction "~{OE}_22") (pintype "input"))
      (node (ref "IC7") (pin "8") (pinfunction "O_8") (pintype "output"))
    )
    (net (code "922") (name "~{ROM_ADDR}") (class "Default")
      (node (ref "D10") (pin "17") (pinfunction "17_17") (pintype "passive"))
      (node (ref "IC5") (pin "6") (pinfunction "G1_6") (pintype "input"))
      (node (ref "U$2") (pin "AU2") (pinfunction "1_AU2") (pintype "passive"))
    )
    (net (code "923") (name "~{RUN}") (class "Default")
      (node (ref "D8") (pin "17") (pinfunction "17_17") (pintype "passive"))
      (node (ref "U$2") (pin "BU2") (pinfunction "1_BU2") (pintype "passive"))
    )
    (net (code "924") (name "~{SKIP}") (class "Default")
      (node (ref "D11") (pin "15") (pinfunction "15_15") (pintype "passive"))
      (node (ref "U$2") (pin "CS1") (pinfunction "1_CS1") (pintype "passive"))
    )
    (net (code "925") (name "~{STOP}") (class "Default")
      (node (ref "D14") (pin "15") (pinfunction "15_15") (pintype "passive"))
      (node (ref "U$2") (pin "DS2") (pinfunction "1_DS2") (pintype "passive"))
    )
    (net (code "926") (name "~{TS1}") (class "Default")
      (node (ref "D12") (pin "9") (pinfunction "9_9") (pintype "passive"))
      (node (ref "U$2") (pin "CK2") (pinfunction "1_CK2") (pintype "passive"))
    )
    (net (code "927") (name "~{TS2}") (class "Default")
      (node (ref "D12") (pin "10") (pinfunction "10_10") (pintype "passive"))
      (node (ref "U$2") (pin "CL2") (pinfunction "1_CL2") (pintype "passive"))
    )
    (net (code "928") (name "~{TS3}") (class "Default")
      (node (ref "D12") (pin "11") (pinfunction "11_11") (pintype "passive"))
      (node (ref "U$2") (pin "CM2") (pinfunction "1_CM2") (pintype "passive"))
    )
    (net (code "929") (name "~{TS4}") (class "Default")
      (node (ref "D12") (pin "13") (pinfunction "13_13") (pintype "passive"))
      (node (ref "U$2") (pin "CP2") (pinfunction "1_CP2") (pintype "passive"))
    )
    (net (code "930") (name "~{USER_MODE}") (class "Default")
      (node (ref "D14") (pin "11") (pinfunction "11_11") (pintype "passive"))
      (node (ref "U$2") (pin "DM2") (pinfunction "1_DM2") (pintype "passive"))
    )
    (net (code "931") (name "~{WRITE_EN}") (class "Default")
      (node (ref "IC3") (pin "27") (pinfunction "~{WE}_27") (pintype "input"))
      (node (ref "IC4") (pin "27") (pinfunction "~{WE}_27") (pintype "input"))
      (node (ref "IC7") (pin "6") (pinfunction "O_6") (pintype "output"))
    )
  )
)
